# DRI-flexpcb-12s4p-compact.net
KiCad netlist of a schematic drawn in EAGLE
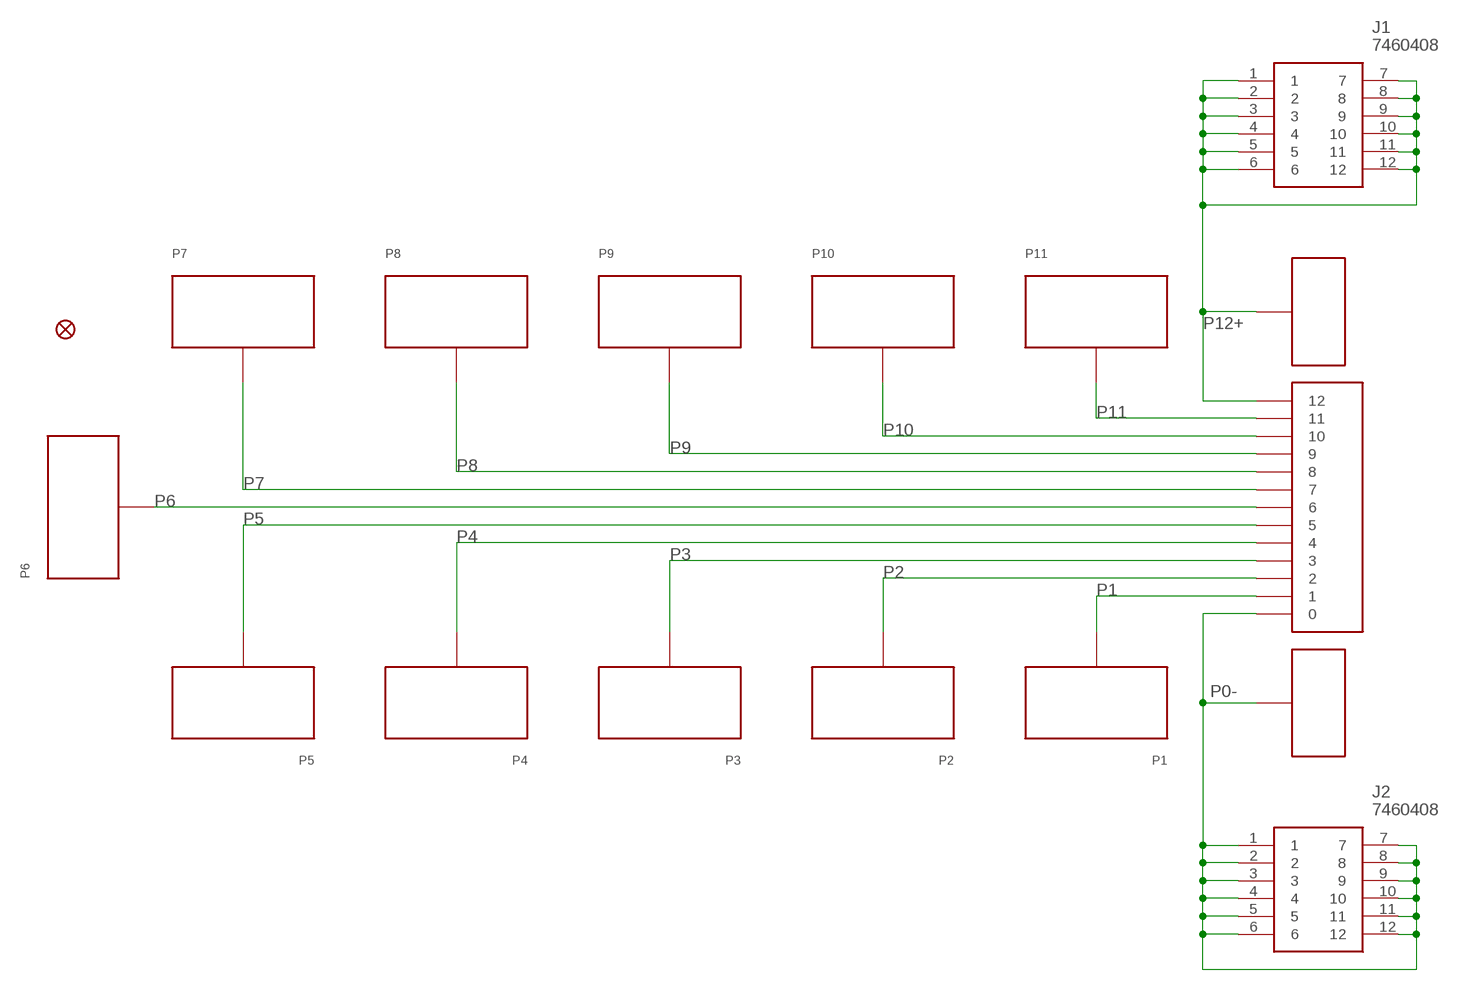
[diagram p0: schematic, sheet 1]

(export (version "E")
  (design (tool "Eeschema 10.0.6"))
  (components
    (comp (ref "FD2")
      (value "FIDUCIAL1X2")
      (footprint "eagle-import:FIDUCIAL-1X2")
      (libsource (lib "eagle-import") (part "FIDUCIAL1X2"))
    )
    (comp (ref "J1")
      (value "7460408")
      (footprint "eagle-import:7460408")
      (fields (field (name "MOUSER_PART_NUMBER") "710-7460408"))
      (libsource (lib "eagle-import") (part "7460408"))
    )
    (comp (ref "J2")
      (value "7460408")
      (footprint "eagle-import:7460408")
      (fields (field (name "MOUSER_PART_NUMBER") "710-7460408"))
      (libsource (lib "eagle-import") (part "7460408"))
    )
    (comp (ref "JP1")
      (value "13P-JST-2MM")
      (footprint "eagle-import:13P-JST-2MM")
      (libsource (lib "eagle-import") (part "13P-JST-2MM"))
    )
    (comp (ref "P0")
      (value "BUS-TERM-PAD-")
      (footprint "eagle-import:TERM-PAD-")
      (libsource (lib "eagle-import") (part "BUS-TERM-PAD-"))
    )
    (comp (ref "P1")
      (value "BAT-TERM-L")
      (footprint "eagle-import:BAT-TERM-L")
      (libsource (lib "eagle-import") (part "BAT-TERM-L"))
    )
    (comp (ref "P2")
      (value "BAT-TERM-L")
      (footprint "eagle-import:BAT-TERM-L")
      (libsource (lib "eagle-import") (part "BAT-TERM-L"))
    )
    (comp (ref "P3")
      (value "BAT-TERM-L")
      (footprint "eagle-import:BAT-TERM-L")
      (libsource (lib "eagle-import") (part "BAT-TERM-L"))
    )
    (comp (ref "P4")
      (value "BAT-TERM-L")
      (footprint "eagle-import:BAT-TERM-L")
      (libsource (lib "eagle-import") (part "BAT-TERM-L"))
    )
    (comp (ref "P5")
      (value "BAT-TERM-L")
      (footprint "eagle-import:BAT-TERM-L")
      (libsource (lib "eagle-import") (part "BAT-TERM-L"))
    )
    (comp (ref "P6")
      (value "BAT-TERM-END")
      (footprint "eagle-import:BAT-TERM-END")
      (libsource (lib "eagle-import") (part "BAT-TERM-END"))
    )
    (comp (ref "P7")
      (value "BAT-TERM-L")
      (footprint "eagle-import:BAT-TERM-L")
      (libsource (lib "eagle-import") (part "BAT-TERM-L"))
    )
    (comp (ref "P8")
      (value "BAT-TERM-L")
      (footprint "eagle-import:BAT-TERM-L")
      (libsource (lib "eagle-import") (part "BAT-TERM-L"))
    )
    (comp (ref "P9")
      (value "BAT-TERM-L")
      (footprint "eagle-import:BAT-TERM-L")
      (libsource (lib "eagle-import") (part "BAT-TERM-L"))
    )
    (comp (ref "P10")
      (value "BAT-TERM-L")
      (footprint "eagle-import:BAT-TERM-L")
      (libsource (lib "eagle-import") (part "BAT-TERM-L"))
    )
    (comp (ref "P11")
      (value "BAT-TERM-L")
      (footprint "eagle-import:BAT-TERM-L")
      (libsource (lib "eagle-import") (part "BAT-TERM-L"))
    )
    (comp (ref "P12")
      (value "BUS-TERM-PAD+")
      (footprint "eagle-import:TERM-PAD-")
      (libsource (lib "eagle-import") (part "BUS-TERM-PAD+"))
    )
  )
  (nets
    (net (code "1") (name "/P0-") (class "Default")
      (node (ref "J2") (pin "1") (pinfunction "1_1") (pintype "bidirectional"))
      (node (ref "J2") (pin "10") (pinfunction "10_10") (pintype "bidirectional"))
      (node (ref "J2") (pin "11") (pinfunction "11_11") (pintype "bidirectional"))
      (node (ref "J2") (pin "12") (pinfunction "12_12") (pintype "bidirectional"))
      (node (ref "J2") (pin "2") (pinfunction "2_2") (pintype "bidirectional"))
      (node (ref "J2") (pin "3") (pinfunction "3_3") (pintype "bidirectional"))
      (node (ref "J2") (pin "4") (pinfunction "4_4") (pintype "bidirectional"))
      (node (ref "J2") (pin "5") (pinfunction "5_5") (pintype "bidirectional"))
      (node (ref "J2") (pin "6") (pinfunction "6_6") (pintype "bidirectional"))
      (node (ref "J2") (pin "7") (pinfunction "7_7") (pintype "bidirectional"))
      (node (ref "J2") (pin "8") (pinfunction "8_8") (pintype "bidirectional"))
      (node (ref "J2") (pin "9") (pinfunction "9_9") (pintype "bidirectional"))
      (node (ref "JP1") (pin "P$1") (pinfunction "0_P$1") (pintype "bidirectional"))
      (node (ref "P0") (pin "P$10") (pinfunction "P$0_P$10") (pintype "power_in"))
      (node (ref "P0") (pin "P$100") (pinfunction "P$0_P$100") (pintype "power_in"))
      (node (ref "P0") (pin "P$101") (pinfunction "P$0_P$101") (pintype "power_in"))
      (node (ref "P0") (pin "P$102") (pinfunction "P$0_P$102") (pintype "power_in"))
      (node (ref "P0") (pin "P$103") (pinfunction "P$0_P$103") (pintype "power_in"))
      (node (ref "P0") (pin "P$104") (pinfunction "P$0_P$104") (pintype "power_in"))
      (node (ref "P0") (pin "P$105") (pinfunction "P$0_P$105") (pintype "power_in"))
      (node (ref "P0") (pin "P$106") (pinfunction "P$0_P$106") (pintype "power_in"))
      (node (ref "P0") (pin "P$107") (pinfunction "P$0_P$107") (pintype "power_in"))
      (node (ref "P0") (pin "P$108") (pinfunction "P$0_P$108") (pintype "power_in"))
      (node (ref "P0") (pin "P$109") (pinfunction "P$0_P$109") (pintype "power_in"))
      (node (ref "P0") (pin "P$11") (pinfunction "P$0_P$11") (pintype "power_in"))
      (node (ref "P0") (pin "P$110") (pinfunction "P$0_P$110") (pintype "power_in"))
      (node (ref "P0") (pin "P$12") (pinfunction "P$0_P$12") (pintype "power_in"))
      (node (ref "P0") (pin "P$13") (pinfunction "P$0_P$13") (pintype "power_in"))
      (node (ref "P0") (pin "P$14") (pinfunction "P$0_P$14") (pintype "power_in"))
      (node (ref "P0") (pin "P$15") (pinfunction "P$0_P$15") (pintype "power_in"))
      (node (ref "P0") (pin "P$16") (pinfunction "P$0_P$16") (pintype "power_in"))
      (node (ref "P0") (pin "P$17") (pinfunction "P$0_P$17") (pintype "power_in"))
      (node (ref "P0") (pin "P$18") (pinfunction "P$0_P$18") (pintype "power_in"))
      (node (ref "P0") (pin "P$181") (pinfunction "P$0_P$181") (pintype "power_in"))
      (node (ref "P0") (pin "P$182") (pinfunction "P$0_P$182") (pintype "power_in"))
      (node (ref "P0") (pin "P$183") (pinfunction "P$0_P$183") (pintype "power_in"))
      (node (ref "P0") (pin "P$184") (pinfunction "P$0_P$184") (pintype "power_in"))
      (node (ref "P0") (pin "P$185") (pinfunction "P$0_P$185") (pintype "power_in"))
      (node (ref "P0") (pin "P$186") (pinfunction "P$0_P$186") (pintype "power_in"))
      (node (ref "P0") (pin "P$187") (pinfunction "P$0_P$187") (pintype "power_in"))
      (node (ref "P0") (pin "P$188") (pinfunction "P$0_P$188") (pintype "power_in"))
      (node (ref "P0") (pin "P$189") (pinfunction "P$0_P$189") (pintype "power_in"))
      (node (ref "P0") (pin "P$19") (pinfunction "P$0_P$19") (pintype "power_in"))
      (node (ref "P0") (pin "P$190") (pinfunction "P$0_P$190") (pintype "power_in"))
      (node (ref "P0") (pin "P$191") (pinfunction "P$0_P$191") (pintype "power_in"))
      (node (ref "P0") (pin "P$192") (pinfunction "P$0_P$192") (pintype "power_in"))
      (node (ref "P0") (pin "P$193") (pinfunction "P$0_P$193") (pintype "power_in"))
      (node (ref "P0") (pin "P$194") (pinfunction "P$0_P$194") (pintype "power_in"))
      (node (ref "P0") (pin "P$195") (pinfunction "P$0_P$195") (pintype "power_in"))
      (node (ref "P0") (pin "P$196") (pinfunction "P$0_P$196") (pintype "power_in"))
      (node (ref "P0") (pin "P$197") (pinfunction "P$0_P$197") (pintype "power_in"))
      (node (ref "P0") (pin "P$198") (pinfunction "P$0_P$198") (pintype "power_in"))
      (node (ref "P0") (pin "P$199") (pinfunction "P$0_P$199") (pintype "power_in"))
      (node (ref "P0") (pin "P$20") (pinfunction "P$0_P$20") (pintype "power_in"))
      (node (ref "P0") (pin "P$200") (pinfunction "P$0_P$200") (pintype "power_in"))
      (node (ref "P0") (pin "P$201") (pinfunction "P$0_P$201") (pintype "power_in"))
      (node (ref "P0") (pin "P$202") (pinfunction "P$0_P$202") (pintype "power_in"))
      (node (ref "P0") (pin "P$203") (pinfunction "P$0_P$203") (pintype "power_in"))
      (node (ref "P0") (pin "P$204") (pinfunction "P$0_P$204") (pintype "power_in"))
      (node (ref "P0") (pin "P$205") (pinfunction "P$0_P$205") (pintype "power_in"))
      (node (ref "P0") (pin "P$206") (pinfunction "P$0_P$206") (pintype "power_in"))
      (node (ref "P0") (pin "P$207") (pinfunction "P$0_P$207") (pintype "power_in"))
      (node (ref "P0") (pin "P$208") (pinfunction "P$0_P$208") (pintype "power_in"))
      (node (ref "P0") (pin "P$209") (pinfunction "P$0_P$209") (pintype "power_in"))
      (node (ref "P0") (pin "P$21") (pinfunction "P$0_P$21") (pintype "power_in"))
      (node (ref "P0") (pin "P$210") (pinfunction "P$0_P$210") (pintype "power_in"))
      (node (ref "P0") (pin "P$211") (pinfunction "P$0_P$211") (pintype "power_in"))
      (node (ref "P0") (pin "P$212") (pinfunction "P$0_P$212") (pintype "power_in"))
      (node (ref "P0") (pin "P$213") (pinfunction "P$0_P$213") (pintype "power_in"))
      (node (ref "P0") (pin "P$214") (pinfunction "P$0_P$214") (pintype "power_in"))
      (node (ref "P0") (pin "P$215") (pinfunction "P$0_P$215") (pintype "power_in"))
      (node (ref "P0") (pin "P$216") (pinfunction "P$0_P$216") (pintype "power_in"))
      (node (ref "P0") (pin "P$217") (pinfunction "P$0_P$217") (pintype "power_in"))
      (node (ref "P0") (pin "P$218") (pinfunction "P$0_P$218") (pintype "power_in"))
      (node (ref "P0") (pin "P$219") (pinfunction "P$0_P$219") (pintype "power_in"))
      (node (ref "P0") (pin "P$22") (pinfunction "P$0_P$22") (pintype "power_in"))
      (node (ref "P0") (pin "P$220") (pinfunction "P$0_P$220") (pintype "power_in"))
      (node (ref "P0") (pin "P$221") (pinfunction "P$0_P$221") (pintype "power_in"))
      (node (ref "P0") (pin "P$222") (pinfunction "P$0_P$222") (pintype "power_in"))
      (node (ref "P0") (pin "P$223") (pinfunction "P$0_P$223") (pintype "power_in"))
      (node (ref "P0") (pin "P$224") (pinfunction "P$0_P$224") (pintype "power_in"))
      (node (ref "P0") (pin "P$225") (pinfunction "P$0_P$225") (pintype "power_in"))
      (node (ref "P0") (pin "P$226") (pinfunction "P$0_P$226") (pintype "power_in"))
      (node (ref "P0") (pin "P$227") (pinfunction "P$0_P$227") (pintype "power_in"))
      (node (ref "P0") (pin "P$228") (pinfunction "P$0_P$228") (pintype "power_in"))
      (node (ref "P0") (pin "P$229") (pinfunction "P$0_P$229") (pintype "power_in"))
      (node (ref "P0") (pin "P$23") (pinfunction "P$0_P$23") (pintype "power_in"))
      (node (ref "P0") (pin "P$230") (pinfunction "P$0_P$230") (pintype "power_in"))
      (node (ref "P0") (pin "P$231") (pinfunction "P$0_P$231") (pintype "power_in"))
      (node (ref "P0") (pin "P$232") (pinfunction "P$0_P$232") (pintype "power_in"))
      (node (ref "P0") (pin "P$233") (pinfunction "P$0_P$233") (pintype "power_in"))
      (node (ref "P0") (pin "P$234") (pinfunction "P$0_P$234") (pintype "power_in"))
      (node (ref "P0") (pin "P$235") (pinfunction "P$0_P$235") (pintype "power_in"))
      (node (ref "P0") (pin "P$236") (pinfunction "P$0_P$236") (pintype "power_in"))
      (node (ref "P0") (pin "P$237") (pinfunction "P$0_P$237") (pintype "power_in"))
      (node (ref "P0") (pin "P$238") (pinfunction "P$0_P$238") (pintype "power_in"))
      (node (ref "P0") (pin "P$239") (pinfunction "P$0_P$239") (pintype "power_in"))
      (node (ref "P0") (pin "P$24") (pinfunction "P$0_P$24") (pintype "power_in"))
      (node (ref "P0") (pin "P$240") (pinfunction "P$0_P$240") (pintype "power_in"))
      (node (ref "P0") (pin "P$241") (pinfunction "P$0_P$241") (pintype "power_in"))
      (node (ref "P0") (pin "P$242") (pinfunction "P$0_P$242") (pintype "power_in"))
      (node (ref "P0") (pin "P$243") (pinfunction "P$0_P$243") (pintype "power_in"))
      (node (ref "P0") (pin "P$244") (pinfunction "P$0_P$244") (pintype "power_in"))
      (node (ref "P0") (pin "P$245") (pinfunction "P$0_P$245") (pintype "power_in"))
      (node (ref "P0") (pin "P$246") (pinfunction "P$0_P$246") (pintype "power_in"))
      (node (ref "P0") (pin "P$247") (pinfunction "P$0_P$247") (pintype "power_in"))
      (node (ref "P0") (pin "P$248") (pinfunction "P$0_P$248") (pintype "power_in"))
      (node (ref "P0") (pin "P$249") (pinfunction "P$0_P$249") (pintype "power_in"))
      (node (ref "P0") (pin "P$25") (pinfunction "P$0_P$25") (pintype "power_in"))
      (node (ref "P0") (pin "P$250") (pinfunction "P$0_P$250") (pintype "power_in"))
      (node (ref "P0") (pin "P$251") (pinfunction "P$0_P$251") (pintype "power_in"))
      (node (ref "P0") (pin "P$252") (pinfunction "P$0_P$252") (pintype "power_in"))
      (node (ref "P0") (pin "P$253") (pinfunction "P$0_P$253") (pintype "power_in"))
      (node (ref "P0") (pin "P$254") (pinfunction "P$0_P$254") (pintype "power_in"))
      (node (ref "P0") (pin "P$255") (pinfunction "P$0_P$255") (pintype "power_in"))
      (node (ref "P0") (pin "P$256") (pinfunction "P$0_P$256") (pintype "power_in"))
      (node (ref "P0") (pin "P$257") (pinfunction "P$0_P$257") (pintype "power_in"))
      (node (ref "P0") (pin "P$258") (pinfunction "P$0_P$258") (pintype "power_in"))
      (node (ref "P0") (pin "P$259") (pinfunction "P$0_P$259") (pintype "power_in"))
      (node (ref "P0") (pin "P$26") (pinfunction "P$0_P$26") (pintype "power_in"))
      (node (ref "P0") (pin "P$260") (pinfunction "P$0_P$260") (pintype "power_in"))
      (node (ref "P0") (pin "P$261") (pinfunction "P$0_P$261") (pintype "power_in"))
      (node (ref "P0") (pin "P$262") (pinfunction "P$0_P$262") (pintype "power_in"))
      (node (ref "P0") (pin "P$263") (pinfunction "P$0_P$263") (pintype "power_in"))
      (node (ref "P0") (pin "P$264") (pinfunction "P$0_P$264") (pintype "power_in"))
      (node (ref "P0") (pin "P$265") (pinfunction "P$0_P$265") (pintype "power_in"))
      (node (ref "P0") (pin "P$266") (pinfunction "P$0_P$266") (pintype "power_in"))
      (node (ref "P0") (pin "P$267") (pinfunction "P$0_P$267") (pintype "power_in"))
      (node (ref "P0") (pin "P$268") (pinfunction "P$0_P$268") (pintype "power_in"))
      (node (ref "P0") (pin "P$269") (pinfunction "P$0_P$269") (pintype "power_in"))
      (node (ref "P0") (pin "P$27") (pinfunction "P$0_P$27") (pintype "power_in"))
      (node (ref "P0") (pin "P$270") (pinfunction "P$0_P$270") (pintype "power_in"))
      (node (ref "P0") (pin "P$271") (pinfunction "P$0_P$271") (pintype "power_in"))
      (node (ref "P0") (pin "P$272") (pinfunction "P$0_P$272") (pintype "power_in"))
      (node (ref "P0") (pin "P$273") (pinfunction "P$0_P$273") (pintype "power_in"))
      (node (ref "P0") (pin "P$274") (pinfunction "P$0_P$274") (pintype "power_in"))
      (node (ref "P0") (pin "P$275") (pinfunction "P$0_P$275") (pintype "power_in"))
      (node (ref "P0") (pin "P$276") (pinfunction "P$0_P$276") (pintype "power_in"))
      (node (ref "P0") (pin "P$277") (pinfunction "P$0_P$277") (pintype "power_in"))
      (node (ref "P0") (pin "P$278") (pinfunction "P$0_P$278") (pintype "power_in"))
      (node (ref "P0") (pin "P$279") (pinfunction "P$0_P$279") (pintype "power_in"))
      (node (ref "P0") (pin "P$28") (pinfunction "P$0_P$28") (pintype "power_in"))
      (node (ref "P0") (pin "P$280") (pinfunction "P$0_P$280") (pintype "power_in"))
      (node (ref "P0") (pin "P$281") (pinfunction "P$0_P$281") (pintype "power_in"))
      (node (ref "P0") (pin "P$282") (pinfunction "P$0_P$282") (pintype "power_in"))
      (node (ref "P0") (pin "P$283") (pinfunction "P$0_P$283") (pintype "power_in"))
      (node (ref "P0") (pin "P$284") (pinfunction "P$0_P$284") (pintype "power_in"))
      (node (ref "P0") (pin "P$285") (pinfunction "P$0_P$285") (pintype "power_in"))
      (node (ref "P0") (pin "P$286") (pinfunction "P$0_P$286") (pintype "power_in"))
      (node (ref "P0") (pin "P$287") (pinfunction "P$0_P$287") (pintype "power_in"))
      (node (ref "P0") (pin "P$288") (pinfunction "P$0_P$288") (pintype "power_in"))
      (node (ref "P0") (pin "P$289") (pinfunction "P$0_P$289") (pintype "power_in"))
      (node (ref "P0") (pin "P$29") (pinfunction "P$0_P$29") (pintype "power_in"))
      (node (ref "P0") (pin "P$290") (pinfunction "P$0_P$290") (pintype "power_in"))
      (node (ref "P0") (pin "P$291") (pinfunction "P$0_P$291") (pintype "power_in"))
      (node (ref "P0") (pin "P$292") (pinfunction "P$0_P$292") (pintype "power_in"))
      (node (ref "P0") (pin "P$293") (pinfunction "P$0_P$293") (pintype "power_in"))
      (node (ref "P0") (pin "P$294") (pinfunction "P$0_P$294") (pintype "power_in"))
      (node (ref "P0") (pin "P$295") (pinfunction "P$0_P$295") (pintype "power_in"))
      (node (ref "P0") (pin "P$296") (pinfunction "P$0_P$296") (pintype "power_in"))
      (node (ref "P0") (pin "P$297") (pinfunction "P$0_P$297") (pintype "power_in"))
      (node (ref "P0") (pin "P$298") (pinfunction "P$0_P$298") (pintype "power_in"))
      (node (ref "P0") (pin "P$299") (pinfunction "P$0_P$299") (pintype "power_in"))
      (node (ref "P0") (pin "P$3") (pinfunction "P$0_P$3") (pintype "power_in"))
      (node (ref "P0") (pin "P$30") (pinfunction "P$0_P$30") (pintype "power_in"))
      (node (ref "P0") (pin "P$300") (pinfunction "P$0_P$300") (pintype "power_in"))
      (node (ref "P0") (pin "P$301") (pinfunction "P$0_P$301") (pintype "power_in"))
      (node (ref "P0") (pin "P$302") (pinfunction "P$0_P$302") (pintype "power_in"))
      (node (ref "P0") (pin "P$303") (pinfunction "P$0_P$303") (pintype "power_in"))
      (node (ref "P0") (pin "P$304") (pinfunction "P$0_P$304") (pintype "power_in"))
      (node (ref "P0") (pin "P$305") (pinfunction "P$0_P$305") (pintype "power_in"))
      (node (ref "P0") (pin "P$306") (pinfunction "P$0_P$306") (pintype "power_in"))
      (node (ref "P0") (pin "P$307") (pinfunction "P$0_P$307") (pintype "power_in"))
      (node (ref "P0") (pin "P$308") (pinfunction "P$0_P$308") (pintype "power_in"))
      (node (ref "P0") (pin "P$309") (pinfunction "P$0_P$309") (pintype "power_in"))
      (node (ref "P0") (pin "P$31") (pinfunction "P$0_P$31") (pintype "power_in"))
      (node (ref "P0") (pin "P$310") (pinfunction "P$0_P$310") (pintype "power_in"))
      (node (ref "P0") (pin "P$311") (pinfunction "P$0_P$311") (pintype "power_in"))
      (node (ref "P0") (pin "P$312") (pinfunction "P$0_P$312") (pintype "power_in"))
      (node (ref "P0") (pin "P$313") (pinfunction "P$0_P$313") (pintype "power_in"))
      (node (ref "P0") (pin "P$314") (pinfunction "P$0_P$314") (pintype "power_in"))
      (node (ref "P0") (pin "P$315") (pinfunction "P$0_P$315") (pintype "power_in"))
      (node (ref "P0") (pin "P$316") (pinfunction "P$0_P$316") (pintype "power_in"))
      (node (ref "P0") (pin "P$317") (pinfunction "P$0_P$317") (pintype "power_in"))
      (node (ref "P0") (pin "P$318") (pinfunction "P$0_P$318") (pintype "power_in"))
      (node (ref "P0") (pin "P$319") (pinfunction "P$0_P$319") (pintype "power_in"))
      (node (ref "P0") (pin "P$32") (pinfunction "P$0_P$32") (pintype "power_in"))
      (node (ref "P0") (pin "P$320") (pinfunction "P$0_P$320") (pintype "power_in"))
      (node (ref "P0") (pin "P$321") (pinfunction "P$0_P$321") (pintype "power_in"))
      (node (ref "P0") (pin "P$322") (pinfunction "P$0_P$322") (pintype "power_in"))
      (node (ref "P0") (pin "P$323") (pinfunction "P$0_P$323") (pintype "power_in"))
      (node (ref "P0") (pin "P$324") (pinfunction "P$0_P$324") (pintype "power_in"))
      (node (ref "P0") (pin "P$325") (pinfunction "P$0_P$325") (pintype "power_in"))
      (node (ref "P0") (pin "P$326") (pinfunction "P$0_P$326") (pintype "power_in"))
      (node (ref "P0") (pin "P$327") (pinfunction "P$0_P$327") (pintype "power_in"))
      (node (ref "P0") (pin "P$328") (pinfunction "P$0_P$328") (pintype "power_in"))
      (node (ref "P0") (pin "P$329") (pinfunction "P$0_P$329") (pintype "power_in"))
      (node (ref "P0") (pin "P$33") (pinfunction "P$0_P$33") (pintype "power_in"))
      (node (ref "P0") (pin "P$330") (pinfunction "P$0_P$330") (pintype "power_in"))
      (node (ref "P0") (pin "P$331") (pinfunction "P$0_P$331") (pintype "power_in"))
      (node (ref "P0") (pin "P$332") (pinfunction "P$0_P$332") (pintype "power_in"))
      (node (ref "P0") (pin "P$333") (pinfunction "P$0_P$333") (pintype "power_in"))
      (node (ref "P0") (pin "P$334") (pinfunction "P$0_P$334") (pintype "power_in"))
      (node (ref "P0") (pin "P$335") (pinfunction "P$0_P$335") (pintype "power_in"))
      (node (ref "P0") (pin "P$336") (pinfunction "P$0_P$336") (pintype "power_in"))
      (node (ref "P0") (pin "P$337") (pinfunction "P$0_P$337") (pintype "power_in"))
      (node (ref "P0") (pin "P$338") (pinfunction "P$0_P$338") (pintype "power_in"))
      (node (ref "P0") (pin "P$339") (pinfunction "P$0_P$339") (pintype "power_in"))
      (node (ref "P0") (pin "P$34") (pinfunction "P$0_P$34") (pintype "power_in"))
      (node (ref "P0") (pin "P$340") (pinfunction "P$0_P$340") (pintype "power_in"))
      (node (ref "P0") (pin "P$341") (pinfunction "P$0_P$341") (pintype "power_in"))
      (node (ref "P0") (pin "P$342") (pinfunction "P$0_P$342") (pintype "power_in"))
      (node (ref "P0") (pin "P$343") (pinfunction "P$0_P$343") (pintype "power_in"))
      (node (ref "P0") (pin "P$344") (pinfunction "P$0_P$344") (pintype "power_in"))
      (node (ref "P0") (pin "P$345") (pinfunction "P$0_P$345") (pintype "power_in"))
      (node (ref "P0") (pin "P$346") (pinfunction "P$0_P$346") (pintype "power_in"))
      (node (ref "P0") (pin "P$347") (pinfunction "P$0_P$347") (pintype "power_in"))
      (node (ref "P0") (pin "P$348") (pinfunction "P$0_P$348") (pintype "power_in"))
      (node (ref "P0") (pin "P$349") (pinfunction "P$0_P$349") (pintype "power_in"))
      (node (ref "P0") (pin "P$35") (pinfunction "P$0_P$35") (pintype "power_in"))
      (node (ref "P0") (pin "P$350") (pinfunction "P$0_P$350") (pintype "power_in"))
      (node (ref "P0") (pin "P$351") (pinfunction "P$0_P$351") (pintype "power_in"))
      (node (ref "P0") (pin "P$352") (pinfunction "P$0_P$352") (pintype "power_in"))
      (node (ref "P0") (pin "P$353") (pinfunction "P$0_P$353") (pintype "power_in"))
      (node (ref "P0") (pin "P$354") (pinfunction "P$0_P$354") (pintype "power_in"))
      (node (ref "P0") (pin "P$355") (pinfunction "P$0_P$355") (pintype "power_in"))
      (node (ref "P0") (pin "P$356") (pinfunction "P$0_P$356") (pintype "power_in"))
      (node (ref "P0") (pin "P$357") (pinfunction "P$0_P$357") (pintype "power_in"))
      (node (ref "P0") (pin "P$358") (pinfunction "P$0_P$358") (pintype "power_in"))
      (node (ref "P0") (pin "P$359") (pinfunction "P$0_P$359") (pintype "power_in"))
      (node (ref "P0") (pin "P$36") (pinfunction "P$0_P$36") (pintype "power_in"))
      (node (ref "P0") (pin "P$360") (pinfunction "P$0_P$360") (pintype "power_in"))
      (node (ref "P0") (pin "P$37") (pinfunction "P$0_P$37") (pintype "power_in"))
      (node (ref "P0") (pin "P$38") (pinfunction "P$0_P$38") (pintype "power_in"))
      (node (ref "P0") (pin "P$39") (pinfunction "P$0_P$39") (pintype "power_in"))
      (node (ref "P0") (pin "P$4") (pinfunction "P$0_P$4") (pintype "power_in"))
      (node (ref "P0") (pin "P$40") (pinfunction "P$0_P$40") (pintype "power_in"))
      (node (ref "P0") (pin "P$41") (pinfunction "P$0_P$41") (pintype "power_in"))
      (node (ref "P0") (pin "P$42") (pinfunction "P$0_P$42") (pintype "power_in"))
      (node (ref "P0") (pin "P$43") (pinfunction "P$0_P$43") (pintype "power_in"))
      (node (ref "P0") (pin "P$44") (pinfunction "P$0_P$44") (pintype "power_in"))
      (node (ref "P0") (pin "P$45") (pinfunction "P$0_P$45") (pintype "power_in"))
      (node (ref "P0") (pin "P$46") (pinfunction "P$0_P$46") (pintype "power_in"))
      (node (ref "P0") (pin "P$47") (pinfunction "P$0_P$47") (pintype "power_in"))
      (node (ref "P0") (pin "P$48") (pinfunction "P$0_P$48") (pintype "power_in"))
      (node (ref "P0") (pin "P$49") (pinfunction "P$0_P$49") (pintype "power_in"))
      (node (ref "P0") (pin "P$5") (pinfunction "P$0_P$5") (pintype "power_in"))
      (node (ref "P0") (pin "P$50") (pinfunction "P$0_P$50") (pintype "power_in"))
      (node (ref "P0") (pin "P$51") (pinfunction "P$0_P$51") (pintype "power_in"))
      (node (ref "P0") (pin "P$52") (pinfunction "P$0_P$52") (pintype "power_in"))
      (node (ref "P0") (pin "P$53") (pinfunction "P$0_P$53") (pintype "power_in"))
      (node (ref "P0") (pin "P$54") (pinfunction "P$0_P$54") (pintype "power_in"))
      (node (ref "P0") (pin "P$55") (pinfunction "P$0_P$55") (pintype "power_in"))
      (node (ref "P0") (pin "P$56") (pinfunction "P$0_P$56") (pintype "power_in"))
      (node (ref "P0") (pin "P$57") (pinfunction "P$0_P$57") (pintype "power_in"))
      (node (ref "P0") (pin "P$58") (pinfunction "P$0_P$58") (pintype "power_in"))
      (node (ref "P0") (pin "P$59") (pinfunction "P$0_P$59") (pintype "power_in"))
      (node (ref "P0") (pin "P$6") (pinfunction "P$0_P$6") (pintype "power_in"))
      (node (ref "P0") (pin "P$60") (pinfunction "P$0_P$60") (pintype "power_in"))
      (node (ref "P0") (pin "P$61") (pinfunction "P$0_P$61") (pintype "power_in"))
      (node (ref "P0") (pin "P$62") (pinfunction "P$0_P$62") (pintype "power_in"))
      (node (ref "P0") (pin "P$63") (pinfunction "P$0_P$63") (pintype "power_in"))
      (node (ref "P0") (pin "P$64") (pinfunction "P$0_P$64") (pintype "power_in"))
      (node (ref "P0") (pin "P$65") (pinfunction "P$0_P$65") (pintype "power_in"))
      (node (ref "P0") (pin "P$66") (pinfunction "P$0_P$66") (pintype "power_in"))
      (node (ref "P0") (pin "P$67") (pinfunction "P$0_P$67") (pintype "power_in"))
      (node (ref "P0") (pin "P$68") (pinfunction "P$0_P$68") (pintype "power_in"))
      (node (ref "P0") (pin "P$69") (pinfunction "P$0_P$69") (pintype "power_in"))
      (node (ref "P0") (pin "P$7") (pinfunction "P$0_P$7") (pintype "power_in"))
      (node (ref "P0") (pin "P$70") (pinfunction "P$0_P$70") (pintype "power_in"))
      (node (ref "P0") (pin "P$71") (pinfunction "P$0_P$71") (pintype "power_in"))
      (node (ref "P0") (pin "P$72") (pinfunction "P$0_P$72") (pintype "power_in"))
      (node (ref "P0") (pin "P$73") (pinfunction "P$0_P$73") (pintype "power_in"))
      (node (ref "P0") (pin "P$74") (pinfunction "P$0_P$74") (pintype "power_in"))
      (node (ref "P0") (pin "P$75") (pinfunction "P$0_P$75") (pintype "power_in"))
      (node (ref "P0") (pin "P$76") (pinfunction "P$0_P$76") (pintype "power_in"))
      (node (ref "P0") (pin "P$77") (pinfunction "P$0_P$77") (pintype "power_in"))
      (node (ref "P0") (pin "P$78") (pinfunction "P$0_P$78") (pintype "power_in"))
      (node (ref "P0") (pin "P$79") (pinfunction "P$0_P$79") (pintype "power_in"))
      (node (ref "P0") (pin "P$8") (pinfunction "P$0_P$8") (pintype "power_in"))
      (node (ref "P0") (pin "P$80") (pinfunction "P$0_P$80") (pintype "power_in"))
      (node (ref "P0") (pin "P$81") (pinfunction "P$0_P$81") (pintype "power_in"))
      (node (ref "P0") (pin "P$82") (pinfunction "P$0_P$82") (pintype "power_in"))
      (node (ref "P0") (pin "P$83") (pinfunction "P$0_P$83") (pintype "power_in"))
      (node (ref "P0") (pin "P$84") (pinfunction "P$0_P$84") (pintype "power_in"))
      (node (ref "P0") (pin "P$85") (pinfunction "P$0_P$85") (pintype "power_in"))
      (node (ref "P0") (pin "P$86") (pinfunction "P$0_P$86") (pintype "power_in"))
      (node (ref "P0") (pin "P$87") (pinfunction "P$0_P$87") (pintype "power_in"))
      (node (ref "P0") (pin "P$88") (pinfunction "P$0_P$88") (pintype "power_in"))
      (node (ref "P0") (pin "P$89") (pinfunction "P$0_P$89") (pintype "power_in"))
      (node (ref "P0") (pin "P$9") (pinfunction "P$0_P$9") (pintype "power_in"))
      (node (ref "P0") (pin "P$90") (pinfunction "P$0_P$90") (pintype "power_in"))
      (node (ref "P0") (pin "P$91") (pinfunction "P$0_P$91") (pintype "power_in"))
      (node (ref "P0") (pin "P$92") (pinfunction "P$0_P$92") (pintype "power_in"))
      (node (ref "P0") (pin "P$93") (pinfunction "P$0_P$93") (pintype "power_in"))
      (node (ref "P0") (pin "P$94") (pinfunction "P$0_P$94") (pintype "power_in"))
      (node (ref "P0") (pin "P$95") (pinfunction "P$0_P$95") (pintype "power_in"))
      (node (ref "P0") (pin "P$96") (pinfunction "P$0_P$96") (pintype "power_in"))
      (node (ref "P0") (pin "P$97") (pinfunction "P$0_P$97") (pintype "power_in"))
      (node (ref "P0") (pin "P$98") (pinfunction "P$0_P$98") (pintype "power_in"))
      (node (ref "P0") (pin "P$99") (pinfunction "P$0_P$99") (pintype "power_in"))
    )
    (net (code "2") (name "/P1") (class "Default")
      (node (ref "JP1") (pin "P$2") (pinfunction "1_P$2") (pintype "bidirectional"))
      (node (ref "P1") (pin "P$1") (pinfunction "P$1_P$1") (pintype "power_in"))
      (node (ref "P1") (pin "P$10") (pinfunction "P$1_P$10") (pintype "power_in"))
      (node (ref "P1") (pin "P$100") (pinfunction "P$1_P$100") (pintype "power_in"))
      (node (ref "P1") (pin "P$101") (pinfunction "P$1_P$101") (pintype "power_in"))
      (node (ref "P1") (pin "P$102") (pinfunction "P$1_P$102") (pintype "power_in"))
      (node (ref "P1") (pin "P$103") (pinfunction "P$1_P$103") (pintype "power_in"))
      (node (ref "P1") (pin "P$104") (pinfunction "P$1_P$104") (pintype "power_in"))
      (node (ref "P1") (pin "P$105") (pinfunction "P$1_P$105") (pintype "power_in"))
      (node (ref "P1") (pin "P$106") (pinfunction "P$1_P$106") (pintype "power_in"))
      (node (ref "P1") (pin "P$107") (pinfunction "P$1_P$107") (pintype "power_in"))
      (node (ref "P1") (pin "P$108") (pinfunction "P$1_P$108") (pintype "power_in"))
      (node (ref "P1") (pin "P$109") (pinfunction "P$1_P$109") (pintype "power_in"))
      (node (ref "P1") (pin "P$11") (pinfunction "P$1_P$11") (pintype "power_in"))
      (node (ref "P1") (pin "P$110") (pinfunction "P$1_P$110") (pintype "power_in"))
      (node (ref "P1") (pin "P$111") (pinfunction "P$1_P$111") (pintype "power_in"))
      (node (ref "P1") (pin "P$112") (pinfunction "P$1_P$112") (pintype "power_in"))
      (node (ref "P1") (pin "P$113") (pinfunction "P$1_P$113") (pintype "power_in"))
      (node (ref "P1") (pin "P$114") (pinfunction "P$1_P$114") (pintype "power_in"))
      (node (ref "P1") (pin "P$115") (pinfunction "P$1_P$115") (pintype "power_in"))
      (node (ref "P1") (pin "P$116") (pinfunction "P$1_P$116") (pintype "power_in"))
      (node (ref "P1") (pin "P$117") (pinfunction "P$1_P$117") (pintype "power_in"))
      (node (ref "P1") (pin "P$118") (pinfunction "P$1_P$118") (pintype "power_in"))
      (node (ref "P1") (pin "P$119") (pinfunction "P$1_P$119") (pintype "power_in"))
      (node (ref "P1") (pin "P$12") (pinfunction "P$1_P$12") (pintype "power_in"))
      (node (ref "P1") (pin "P$120") (pinfunction "P$1_P$120") (pintype "power_in"))
      (node (ref "P1") (pin "P$121") (pinfunction "P$1_P$121") (pintype "power_in"))
      (node (ref "P1") (pin "P$122") (pinfunction "P$1_P$122") (pintype "power_in"))
      (node (ref "P1") (pin "P$123") (pinfunction "P$1_P$123") (pintype "power_in"))
      (node (ref "P1") (pin "P$124") (pinfunction "P$1_P$124") (pintype "power_in"))
      (node (ref "P1") (pin "P$125") (pinfunction "P$1_P$125") (pintype "power_in"))
      (node (ref "P1") (pin "P$126") (pinfunction "P$1_P$126") (pintype "power_in"))
      (node (ref "P1") (pin "P$127") (pinfunction "P$1_P$127") (pintype "power_in"))
      (node (ref "P1") (pin "P$128") (pinfunction "P$1_P$128") (pintype "power_in"))
      (node (ref "P1") (pin "P$129") (pinfunction "P$1_P$129") (pintype "power_in"))
      (node (ref "P1") (pin "P$13") (pinfunction "P$1_P$13") (pintype "power_in"))
      (node (ref "P1") (pin "P$130") (pinfunction "P$1_P$130") (pintype "power_in"))
      (node (ref "P1") (pin "P$131") (pinfunction "P$1_P$131") (pintype "power_in"))
      (node (ref "P1") (pin "P$132") (pinfunction "P$1_P$132") (pintype "power_in"))
      (node (ref "P1") (pin "P$133") (pinfunction "P$1_P$133") (pintype "power_in"))
      (node (ref "P1") (pin "P$134") (pinfunction "P$1_P$134") (pintype "power_in"))
      (node (ref "P1") (pin "P$135") (pinfunction "P$1_P$135") (pintype "power_in"))
      (node (ref "P1") (pin "P$136") (pinfunction "P$1_P$136") (pintype "power_in"))
      (node (ref "P1") (pin "P$137") (pinfunction "P$1_P$137") (pintype "power_in"))
      (node (ref "P1") (pin "P$138") (pinfunction "P$1_P$138") (pintype "power_in"))
      (node (ref "P1") (pin "P$139") (pinfunction "P$1_P$139") (pintype "power_in"))
      (node (ref "P1") (pin "P$14") (pinfunction "P$1_P$14") (pintype "power_in"))
      (node (ref "P1") (pin "P$140") (pinfunction "P$1_P$140") (pintype "power_in"))
      (node (ref "P1") (pin "P$141") (pinfunction "P$1_P$141") (pintype "power_in"))
      (node (ref "P1") (pin "P$142") (pinfunction "P$1_P$142") (pintype "power_in"))
      (node (ref "P1") (pin "P$143") (pinfunction "P$1_P$143") (pintype "power_in"))
      (node (ref "P1") (pin "P$144") (pinfunction "P$1_P$144") (pintype "power_in"))
      (node (ref "P1") (pin "P$145") (pinfunction "P$1_P$145") (pintype "power_in"))
      (node (ref "P1") (pin "P$146") (pinfunction "P$1_P$146") (pintype "power_in"))
      (node (ref "P1") (pin "P$147") (pinfunction "P$1_P$147") (pintype "power_in"))
      (node (ref "P1") (pin "P$148") (pinfunction "P$1_P$148") (pintype "power_in"))
      (node (ref "P1") (pin "P$149") (pinfunction "P$1_P$149") (pintype "power_in"))
      (node (ref "P1") (pin "P$15") (pinfunction "P$1_P$15") (pintype "power_in"))
      (node (ref "P1") (pin "P$150") (pinfunction "P$1_P$150") (pintype "power_in"))
      (node (ref "P1") (pin "P$151") (pinfunction "P$1_P$151") (pintype "power_in"))
      (node (ref "P1") (pin "P$152") (pinfunction "P$1_P$152") (pintype "power_in"))
      (node (ref "P1") (pin "P$153") (pinfunction "P$1_P$153") (pintype "power_in"))
      (node (ref "P1") (pin "P$154") (pinfunction "P$1_P$154") (pintype "power_in"))
      (node (ref "P1") (pin "P$155") (pinfunction "P$1_P$155") (pintype "power_in"))
      (node (ref "P1") (pin "P$156") (pinfunction "P$1_P$156") (pintype "power_in"))
      (node (ref "P1") (pin "P$157") (pinfunction "P$1_P$157") (pintype "power_in"))
      (node (ref "P1") (pin "P$158") (pinfunction "P$1_P$158") (pintype "power_in"))
      (node (ref "P1") (pin "P$159") (pinfunction "P$1_P$159") (pintype "power_in"))
      (node (ref "P1") (pin "P$16") (pinfunction "P$1_P$16") (pintype "power_in"))
      (node (ref "P1") (pin "P$160") (pinfunction "P$1_P$160") (pintype "power_in"))
      (node (ref "P1") (pin "P$161") (pinfunction "P$1_P$161") (pintype "power_in"))
      (node (ref "P1") (pin "P$162") (pinfunction "P$1_P$162") (pintype "power_in"))
      (node (ref "P1") (pin "P$163") (pinfunction "P$1_P$163") (pintype "power_in"))
      (node (ref "P1") (pin "P$164") (pinfunction "P$1_P$164") (pintype "power_in"))
      (node (ref "P1") (pin "P$165") (pinfunction "P$1_P$165") (pintype "power_in"))
      (node (ref "P1") (pin "P$166") (pinfunction "P$1_P$166") (pintype "power_in"))
      (node (ref "P1") (pin "P$167") (pinfunction "P$1_P$167") (pintype "power_in"))
      (node (ref "P1") (pin "P$168") (pinfunction "P$1_P$168") (pintype "power_in"))
      (node (ref "P1") (pin "P$169") (pinfunction "P$1_P$169") (pintype "power_in"))
      (node (ref "P1") (pin "P$17") (pinfunction "P$1_P$17") (pintype "power_in"))
      (node (ref "P1") (pin "P$170") (pinfunction "P$1_P$170") (pintype "power_in"))
      (node (ref "P1") (pin "P$171") (pinfunction "P$1_P$171") (pintype "power_in"))
      (node (ref "P1") (pin "P$172") (pinfunction "P$1_P$172") (pintype "power_in"))
      (node (ref "P1") (pin "P$173") (pinfunction "P$1_P$173") (pintype "power_in"))
      (node (ref "P1") (pin "P$174") (pinfunction "P$1_P$174") (pintype "power_in"))
      (node (ref "P1") (pin "P$175") (pinfunction "P$1_P$175") (pintype "power_in"))
      (node (ref "P1") (pin "P$176") (pinfunction "P$1_P$176") (pintype "power_in"))
      (node (ref "P1") (pin "P$177") (pinfunction "P$1_P$177") (pintype "power_in"))
      (node (ref "P1") (pin "P$178") (pinfunction "P$1_P$178") (pintype "power_in"))
      (node (ref "P1") (pin "P$179") (pinfunction "P$1_P$179") (pintype "power_in"))
      (node (ref "P1") (pin "P$18") (pinfunction "P$1_P$18") (pintype "power_in"))
      (node (ref "P1") (pin "P$180") (pinfunction "P$1_P$180") (pintype "power_in"))
      (node (ref "P1") (pin "P$181") (pinfunction "P$1_P$181") (pintype "power_in"))
      (node (ref "P1") (pin "P$182") (pinfunction "P$1_P$182") (pintype "power_in"))
      (node (ref "P1") (pin "P$183") (pinfunction "P$1_P$183") (pintype "power_in"))
      (node (ref "P1") (pin "P$184") (pinfunction "P$1_P$184") (pintype "power_in"))
      (node (ref "P1") (pin "P$185") (pinfunction "P$1_P$185") (pintype "power_in"))
      (node (ref "P1") (pin "P$186") (pinfunction "P$1_P$186") (pintype "power_in"))
      (node (ref "P1") (pin "P$187") (pinfunction "P$1_P$187") (pintype "power_in"))
      (node (ref "P1") (pin "P$188") (pinfunction "P$1_P$188") (pintype "power_in"))
      (node (ref "P1") (pin "P$189") (pinfunction "P$1_P$189") (pintype "power_in"))
      (node (ref "P1") (pin "P$19") (pinfunction "P$1_P$19") (pintype "power_in"))
      (node (ref "P1") (pin "P$190") (pinfunction "P$1_P$190") (pintype "power_in"))
      (node (ref "P1") (pin "P$191") (pinfunction "P$1_P$191") (pintype "power_in"))
      (node (ref "P1") (pin "P$192") (pinfunction "P$1_P$192") (pintype "power_in"))
      (node (ref "P1") (pin "P$193") (pinfunction "P$1_P$193") (pintype "power_in"))
      (node (ref "P1") (pin "P$194") (pinfunction "P$1_P$194") (pintype "power_in"))
      (node (ref "P1") (pin "P$195") (pinfunction "P$1_P$195") (pintype "power_in"))
      (node (ref "P1") (pin "P$196") (pinfunction "P$1_P$196") (pintype "power_in"))
      (node (ref "P1") (pin "P$197") (pinfunction "P$1_P$197") (pintype "power_in"))
      (node (ref "P1") (pin "P$198") (pinfunction "P$1_P$198") (pintype "power_in"))
      (node (ref "P1") (pin "P$199") (pinfunction "P$1_P$199") (pintype "power_in"))
      (node (ref "P1") (pin "P$2") (pinfunction "P$1_P$2") (pintype "power_in"))
      (node (ref "P1") (pin "P$20") (pinfunction "P$1_P$20") (pintype "power_in"))
      (node (ref "P1") (pin "P$200") (pinfunction "P$1_P$200") (pintype "power_in"))
      (node (ref "P1") (pin "P$201") (pinfunction "P$1_P$201") (pintype "power_in"))
      (node (ref "P1") (pin "P$202") (pinfunction "P$1_P$202") (pintype "power_in"))
      (node (ref "P1") (pin "P$203") (pinfunction "P$1_P$203") (pintype "power_in"))
      (node (ref "P1") (pin "P$204") (pinfunction "P$1_P$204") (pintype "power_in"))
      (node (ref "P1") (pin "P$205") (pinfunction "P$1_P$205") (pintype "power_in"))
      (node (ref "P1") (pin "P$206") (pinfunction "P$1_P$206") (pintype "power_in"))
      (node (ref "P1") (pin "P$207") (pinfunction "P$1_P$207") (pintype "power_in"))
      (node (ref "P1") (pin "P$208") (pinfunction "P$1_P$208") (pintype "power_in"))
      (node (ref "P1") (pin "P$209") (pinfunction "P$1_P$209") (pintype "power_in"))
      (node (ref "P1") (pin "P$21") (pinfunction "P$1_P$21") (pintype "power_in"))
      (node (ref "P1") (pin "P$210") (pinfunction "P$1_P$210") (pintype "power_in"))
      (node (ref "P1") (pin "P$211") (pinfunction "P$1_P$211") (pintype "power_in"))
      (node (ref "P1") (pin "P$212") (pinfunction "P$1_P$212") (pintype "power_in"))
      (node (ref "P1") (pin "P$213") (pinfunction "P$1_P$213") (pintype "power_in"))
      (node (ref "P1") (pin "P$214") (pinfunction "P$1_P$214") (pintype "power_in"))
      (node (ref "P1") (pin "P$215") (pinfunction "P$1_P$215") (pintype "power_in"))
      (node (ref "P1") (pin "P$216") (pinfunction "P$1_P$216") (pintype "power_in"))
      (node (ref "P1") (pin "P$217") (pinfunction "P$1_P$217") (pintype "power_in"))
      (node (ref "P1") (pin "P$218") (pinfunction "P$1_P$218") (pintype "power_in"))
      (node (ref "P1") (pin "P$219") (pinfunction "P$1_P$219") (pintype "power_in"))
      (node (ref "P1") (pin "P$22") (pinfunction "P$1_P$22") (pintype "power_in"))
      (node (ref "P1") (pin "P$220") (pinfunction "P$1_P$220") (pintype "power_in"))
      (node (ref "P1") (pin "P$221") (pinfunction "P$1_P$221") (pintype "power_in"))
      (node (ref "P1") (pin "P$222") (pinfunction "P$1_P$222") (pintype "power_in"))
      (node (ref "P1") (pin "P$223") (pinfunction "P$1_P$223") (pintype "power_in"))
      (node (ref "P1") (pin "P$224") (pinfunction "P$1_P$224") (pintype "power_in"))
      (node (ref "P1") (pin "P$225") (pinfunction "P$1_P$225") (pintype "power_in"))
      (node (ref "P1") (pin "P$226") (pinfunction "P$1_P$226") (pintype "power_in"))
      (node (ref "P1") (pin "P$227") (pinfunction "P$1_P$227") (pintype "power_in"))
      (node (ref "P1") (pin "P$228") (pinfunction "P$1_P$228") (pintype "power_in"))
      (node (ref "P1") (pin "P$229") (pinfunction "P$1_P$229") (pintype "power_in"))
      (node (ref "P1") (pin "P$23") (pinfunction "P$1_P$23") (pintype "power_in"))
      (node (ref "P1") (pin "P$230") (pinfunction "P$1_P$230") (pintype "power_in"))
      (node (ref "P1") (pin "P$231") (pinfunction "P$1_P$231") (pintype "power_in"))
      (node (ref "P1") (pin "P$232") (pinfunction "P$1_P$232") (pintype "power_in"))
      (node (ref "P1") (pin "P$233") (pinfunction "P$1_P$233") (pintype "power_in"))
      (node (ref "P1") (pin "P$234") (pinfunction "P$1_P$234") (pintype "power_in"))
      (node (ref "P1") (pin "P$235") (pinfunction "P$1_P$235") (pintype "power_in"))
      (node (ref "P1") (pin "P$236") (pinfunction "P$1_P$236") (pintype "power_in"))
      (node (ref "P1") (pin "P$237") (pinfunction "P$1_P$237") (pintype "power_in"))
      (node (ref "P1") (pin "P$238") (pinfunction "P$1_P$238") (pintype "power_in"))
      (node (ref "P1") (pin "P$239") (pinfunction "P$1_P$239") (pintype "power_in"))
      (node (ref "P1") (pin "P$24") (pinfunction "P$1_P$24") (pintype "power_in"))
      (node (ref "P1") (pin "P$240") (pinfunction "P$1_P$240") (pintype "power_in"))
      (node (ref "P1") (pin "P$241") (pinfunction "P$1_P$241") (pintype "power_in"))
      (node (ref "P1") (pin "P$242") (pinfunction "P$1_P$242") (pintype "power_in"))
      (node (ref "P1") (pin "P$243") (pinfunction "P$1_P$243") (pintype "power_in"))
      (node (ref "P1") (pin "P$244") (pinfunction "P$1_P$244") (pintype "power_in"))
      (node (ref "P1") (pin "P$245") (pinfunction "P$1_P$245") (pintype "power_in"))
      (node (ref "P1") (pin "P$246") (pinfunction "P$1_P$246") (pintype "power_in"))
      (node (ref "P1") (pin "P$247") (pinfunction "P$1_P$247") (pintype "power_in"))
      (node (ref "P1") (pin "P$248") (pinfunction "P$1_P$248") (pintype "power_in"))
      (node (ref "P1") (pin "P$249") (pinfunction "P$1_P$249") (pintype "power_in"))
      (node (ref "P1") (pin "P$25") (pinfunction "P$1_P$25") (pintype "power_in"))
      (node (ref "P1") (pin "P$250") (pinfunction "P$1_P$250") (pintype "power_in"))
      (node (ref "P1") (pin "P$251") (pinfunction "P$1_P$251") (pintype "power_in"))
      (node (ref "P1") (pin "P$252") (pinfunction "P$1_P$252") (pintype "power_in"))
      (node (ref "P1") (pin "P$253") (pinfunction "P$1_P$253") (pintype "power_in"))
      (node (ref "P1") (pin "P$254") (pinfunction "P$1_P$254") (pintype "power_in"))
      (node (ref "P1") (pin "P$255") (pinfunction "P$1_P$255") (pintype "power_in"))
      (node (ref "P1") (pin "P$256") (pinfunction "P$1_P$256") (pintype "power_in"))
      (node (ref "P1") (pin "P$257") (pinfunction "P$1_P$257") (pintype "power_in"))
      (node (ref "P1") (pin "P$258") (pinfunction "P$1_P$258") (pintype "power_in"))
      (node (ref "P1") (pin "P$259") (pinfunction "P$1_P$259") (pintype "power_in"))
      (node (ref "P1") (pin "P$26") (pinfunction "P$1_P$26") (pintype "power_in"))
      (node (ref "P1") (pin "P$260") (pinfunction "P$1_P$260") (pintype "power_in"))
      (node (ref "P1") (pin "P$261") (pinfunction "P$1_P$261") (pintype "power_in"))
      (node (ref "P1") (pin "P$262") (pinfunction "P$1_P$262") (pintype "power_in"))
      (node (ref "P1") (pin "P$263") (pinfunction "P$1_P$263") (pintype "power_in"))
      (node (ref "P1") (pin "P$264") (pinfunction "P$1_P$264") (pintype "power_in"))
      (node (ref "P1") (pin "P$265") (pinfunction "P$1_P$265") (pintype "power_in"))
      (node (ref "P1") (pin "P$266") (pinfunction "P$1_P$266") (pintype "power_in"))
      (node (ref "P1") (pin "P$267") (pinfunction "P$1_P$267") (pintype "power_in"))
      (node (ref "P1") (pin "P$268") (pinfunction "P$1_P$268") (pintype "power_in"))
      (node (ref "P1") (pin "P$269") (pinfunction "P$1_P$269") (pintype "power_in"))
      (node (ref "P1") (pin "P$27") (pinfunction "P$1_P$27") (pintype "power_in"))
      (node (ref "P1") (pin "P$270") (pinfunction "P$1_P$270") (pintype "power_in"))
      (node (ref "P1") (pin "P$271") (pinfunction "P$1_P$271") (pintype "power_in"))
      (node (ref "P1") (pin "P$272") (pinfunction "P$1_P$272") (pintype "power_in"))
      (node (ref "P1") (pin "P$273") (pinfunction "P$1_P$273") (pintype "power_in"))
      (node (ref "P1") (pin "P$274") (pinfunction "P$1_P$274") (pintype "power_in"))
      (node (ref "P1") (pin "P$275") (pinfunction "P$1_P$275") (pintype "power_in"))
      (node (ref "P1") (pin "P$276") (pinfunction "P$1_P$276") (pintype "power_in"))
      (node (ref "P1") (pin "P$277") (pinfunction "P$1_P$277") (pintype "power_in"))
      (node (ref "P1") (pin "P$278") (pinfunction "P$1_P$278") (pintype "power_in"))
      (node (ref "P1") (pin "P$279") (pinfunction "P$1_P$279") (pintype "power_in"))
      (node (ref "P1") (pin "P$28") (pinfunction "P$1_P$28") (pintype "power_in"))
      (node (ref "P1") (pin "P$280") (pinfunction "P$1_P$280") (pintype "power_in"))
      (node (ref "P1") (pin "P$281") (pinfunction "P$1_P$281") (pintype "power_in"))
      (node (ref "P1") (pin "P$282") (pinfunction "P$1_P$282") (pintype "power_in"))
      (node (ref "P1") (pin "P$283") (pinfunction "P$1_P$283") (pintype "power_in"))
      (node (ref "P1") (pin "P$284") (pinfunction "P$1_P$284") (pintype "power_in"))
      (node (ref "P1") (pin "P$285") (pinfunction "P$1_P$285") (pintype "power_in"))
      (node (ref "P1") (pin "P$286") (pinfunction "P$1_P$286") (pintype "power_in"))
      (node (ref "P1") (pin "P$287") (pinfunction "P$1_P$287") (pintype "power_in"))
      (node (ref "P1") (pin "P$288") (pinfunction "P$1_P$288") (pintype "power_in"))
      (node (ref "P1") (pin "P$29") (pinfunction "P$1_P$29") (pintype "power_in"))
      (node (ref "P1") (pin "P$3") (pinfunction "P$1_P$3") (pintype "power_in"))
      (node (ref "P1") (pin "P$30") (pinfunction "P$1_P$30") (pintype "power_in"))
      (node (ref "P1") (pin "P$31") (pinfunction "P$1_P$31") (pintype "power_in"))
      (node (ref "P1") (pin "P$32") (pinfunction "P$1_P$32") (pintype "power_in"))
      (node (ref "P1") (pin "P$33") (pinfunction "P$1_P$33") (pintype "power_in"))
      (node (ref "P1") (pin "P$34") (pinfunction "P$1_P$34") (pintype "power_in"))
      (node (ref "P1") (pin "P$35") (pinfunction "P$1_P$35") (pintype "power_in"))
      (node (ref "P1") (pin "P$36") (pinfunction "P$1_P$36") (pintype "power_in"))
      (node (ref "P1") (pin "P$37") (pinfunction "P$1_P$37") (pintype "power_in"))
      (node (ref "P1") (pin "P$38") (pinfunction "P$1_P$38") (pintype "power_in"))
      (node (ref "P1") (pin "P$39") (pinfunction "P$1_P$39") (pintype "power_in"))
      (node (ref "P1") (pin "P$4") (pinfunction "P$1_P$4") (pintype "power_in"))
      (node (ref "P1") (pin "P$40") (pinfunction "P$1_P$40") (pintype "power_in"))
      (node (ref "P1") (pin "P$41") (pinfunction "P$1_P$41") (pintype "power_in"))
      (node (ref "P1") (pin "P$42") (pinfunction "P$1_P$42") (pintype "power_in"))
      (node (ref "P1") (pin "P$43") (pinfunction "P$1_P$43") (pintype "power_in"))
      (node (ref "P1") (pin "P$44") (pinfunction "P$1_P$44") (pintype "power_in"))
      (node (ref "P1") (pin "P$45") (pinfunction "P$1_P$45") (pintype "power_in"))
      (node (ref "P1") (pin "P$46") (pinfunction "P$1_P$46") (pintype "power_in"))
      (node (ref "P1") (pin "P$47") (pinfunction "P$1_P$47") (pintype "power_in"))
      (node (ref "P1") (pin "P$48") (pinfunction "P$1_P$48") (pintype "power_in"))
      (node (ref "P1") (pin "P$49") (pinfunction "P$1_P$49") (pintype "power_in"))
      (node (ref "P1") (pin "P$5") (pinfunction "P$1_P$5") (pintype "power_in"))
      (node (ref "P1") (pin "P$50") (pinfunction "P$1_P$50") (pintype "power_in"))
      (node (ref "P1") (pin "P$51") (pinfunction "P$1_P$51") (pintype "power_in"))
      (node (ref "P1") (pin "P$52") (pinfunction "P$1_P$52") (pintype "power_in"))
      (node (ref "P1") (pin "P$53") (pinfunction "P$1_P$53") (pintype "power_in"))
      (node (ref "P1") (pin "P$54") (pinfunction "P$1_P$54") (pintype "power_in"))
      (node (ref "P1") (pin "P$55") (pinfunction "P$1_P$55") (pintype "power_in"))
      (node (ref "P1") (pin "P$56") (pinfunction "P$1_P$56") (pintype "power_in"))
      (node (ref "P1") (pin "P$57") (pinfunction "P$1_P$57") (pintype "power_in"))
      (node (ref "P1") (pin "P$58") (pinfunction "P$1_P$58") (pintype "power_in"))
      (node (ref "P1") (pin "P$59") (pinfunction "P$1_P$59") (pintype "power_in"))
      (node (ref "P1") (pin "P$6") (pinfunction "P$1_P$6") (pintype "power_in"))
      (node (ref "P1") (pin "P$60") (pinfunction "P$1_P$60") (pintype "power_in"))
      (node (ref "P1") (pin "P$61") (pinfunction "P$1_P$61") (pintype "power_in"))
      (node (ref "P1") (pin "P$62") (pinfunction "P$1_P$62") (pintype "power_in"))
      (node (ref "P1") (pin "P$63") (pinfunction "P$1_P$63") (pintype "power_in"))
      (node (ref "P1") (pin "P$64") (pinfunction "P$1_P$64") (pintype "power_in"))
      (node (ref "P1") (pin "P$65") (pinfunction "P$1_P$65") (pintype "power_in"))
      (node (ref "P1") (pin "P$66") (pinfunction "P$1_P$66") (pintype "power_in"))
      (node (ref "P1") (pin "P$67") (pinfunction "P$1_P$67") (pintype "power_in"))
      (node (ref "P1") (pin "P$68") (pinfunction "P$1_P$68") (pintype "power_in"))
      (node (ref "P1") (pin "P$69") (pinfunction "P$1_P$69") (pintype "power_in"))
      (node (ref "P1") (pin "P$7") (pinfunction "P$1_P$7") (pintype "power_in"))
      (node (ref "P1") (pin "P$70") (pinfunction "P$1_P$70") (pintype "power_in"))
      (node (ref "P1") (pin "P$71") (pinfunction "P$1_P$71") (pintype "power_in"))
      (node (ref "P1") (pin "P$72") (pinfunction "P$1_P$72") (pintype "power_in"))
      (node (ref "P1") (pin "P$73") (pinfunction "P$1_P$73") (pintype "power_in"))
      (node (ref "P1") (pin "P$74") (pinfunction "P$1_P$74") (pintype "power_in"))
      (node (ref "P1") (pin "P$75") (pinfunction "P$1_P$75") (pintype "power_in"))
      (node (ref "P1") (pin "P$76") (pinfunction "P$1_P$76") (pintype "power_in"))
      (node (ref "P1") (pin "P$77") (pinfunction "P$1_P$77") (pintype "power_in"))
      (node (ref "P1") (pin "P$78") (pinfunction "P$1_P$78") (pintype "power_in"))
      (node (ref "P1") (pin "P$79") (pinfunction "P$1_P$79") (pintype "power_in"))
      (node (ref "P1") (pin "P$8") (pinfunction "P$1_P$8") (pintype "power_in"))
      (node (ref "P1") (pin "P$80") (pinfunction "P$1_P$80") (pintype "power_in"))
      (node (ref "P1") (pin "P$81") (pinfunction "P$1_P$81") (pintype "power_in"))
      (node (ref "P1") (pin "P$82") (pinfunction "P$1_P$82") (pintype "power_in"))
      (node (ref "P1") (pin "P$83") (pinfunction "P$1_P$83") (pintype "power_in"))
      (node (ref "P1") (pin "P$84") (pinfunction "P$1_P$84") (pintype "power_in"))
      (node (ref "P1") (pin "P$85") (pinfunction "P$1_P$85") (pintype "power_in"))
      (node (ref "P1") (pin "P$86") (pinfunction "P$1_P$86") (pintype "power_in"))
      (node (ref "P1") (pin "P$87") (pinfunction "P$1_P$87") (pintype "power_in"))
      (node (ref "P1") (pin "P$88") (pinfunction "P$1_P$88") (pintype "power_in"))
      (node (ref "P1") (pin "P$89") (pinfunction "P$1_P$89") (pintype "power_in"))
      (node (ref "P1") (pin "P$9") (pinfunction "P$1_P$9") (pintype "power_in"))
      (node (ref "P1") (pin "P$90") (pinfunction "P$1_P$90") (pintype "power_in"))
      (node (ref "P1") (pin "P$91") (pinfunction "P$1_P$91") (pintype "power_in"))
      (node (ref "P1") (pin "P$92") (pinfunction "P$1_P$92") (pintype "power_in"))
      (node (ref "P1") (pin "P$93") (pinfunction "P$1_P$93") (pintype "power_in"))
      (node (ref "P1") (pin "P$94") (pinfunction "P$1_P$94") (pintype "power_in"))
      (node (ref "P1") (pin "P$95") (pinfunction "P$1_P$95") (pintype "power_in"))
      (node (ref "P1") (pin "P$96") (pinfunction "P$1_P$96") (pintype "power_in"))
      (node (ref "P1") (pin "P$97") (pinfunction "P$1_P$97") (pintype "power_in"))
      (node (ref "P1") (pin "P$98") (pinfunction "P$1_P$98") (pintype "power_in"))
      (node (ref "P1") (pin "P$99") (pinfunction "P$1_P$99") (pintype "power_in"))
    )
    (net (code "3") (name "/P2") (class "Default")
      (node (ref "JP1") (pin "P$3") (pinfunction "2_P$3") (pintype "bidirectional"))
      (node (ref "P2") (pin "P$1") (pinfunction "P$1_P$1") (pintype "power_in"))
      (node (ref "P2") (pin "P$10") (pinfunction "P$1_P$10") (pintype "power_in"))
      (node (ref "P2") (pin "P$100") (pinfunction "P$1_P$100") (pintype "power_in"))
      (node (ref "P2") (pin "P$101") (pinfunction "P$1_P$101") (pintype "power_in"))
      (node (ref "P2") (pin "P$102") (pinfunction "P$1_P$102") (pintype "power_in"))
      (node (ref "P2") (pin "P$103") (pinfunction "P$1_P$103") (pintype "power_in"))
      (node (ref "P2") (pin "P$104") (pinfunction "P$1_P$104") (pintype "power_in"))
      (node (ref "P2") (pin "P$105") (pinfunction "P$1_P$105") (pintype "power_in"))
      (node (ref "P2") (pin "P$106") (pinfunction "P$1_P$106") (pintype "power_in"))
      (node (ref "P2") (pin "P$107") (pinfunction "P$1_P$107") (pintype "power_in"))
      (node (ref "P2") (pin "P$108") (pinfunction "P$1_P$108") (pintype "power_in"))
      (node (ref "P2") (pin "P$109") (pinfunction "P$1_P$109") (pintype "power_in"))
      (node (ref "P2") (pin "P$11") (pinfunction "P$1_P$11") (pintype "power_in"))
      (node (ref "P2") (pin "P$110") (pinfunction "P$1_P$110") (pintype "power_in"))
      (node (ref "P2") (pin "P$111") (pinfunction "P$1_P$111") (pintype "power_in"))
      (node (ref "P2") (pin "P$112") (pinfunction "P$1_P$112") (pintype "power_in"))
      (node (ref "P2") (pin "P$113") (pinfunction "P$1_P$113") (pintype "power_in"))
      (node (ref "P2") (pin "P$114") (pinfunction "P$1_P$114") (pintype "power_in"))
      (node (ref "P2") (pin "P$115") (pinfunction "P$1_P$115") (pintype "power_in"))
      (node (ref "P2") (pin "P$116") (pinfunction "P$1_P$116") (pintype "power_in"))
      (node (ref "P2") (pin "P$117") (pinfunction "P$1_P$117") (pintype "power_in"))
      (node (ref "P2") (pin "P$118") (pinfunction "P$1_P$118") (pintype "power_in"))
      (node (ref "P2") (pin "P$119") (pinfunction "P$1_P$119") (pintype "power_in"))
      (node (ref "P2") (pin "P$12") (pinfunction "P$1_P$12") (pintype "power_in"))
      (node (ref "P2") (pin "P$120") (pinfunction "P$1_P$120") (pintype "power_in"))
      (node (ref "P2") (pin "P$121") (pinfunction "P$1_P$121") (pintype "power_in"))
      (node (ref "P2") (pin "P$122") (pinfunction "P$1_P$122") (pintype "power_in"))
      (node (ref "P2") (pin "P$123") (pinfunction "P$1_P$123") (pintype "power_in"))
      (node (ref "P2") (pin "P$124") (pinfunction "P$1_P$124") (pintype "power_in"))
      (node (ref "P2") (pin "P$125") (pinfunction "P$1_P$125") (pintype "power_in"))
      (node (ref "P2") (pin "P$126") (pinfunction "P$1_P$126") (pintype "power_in"))
      (node (ref "P2") (pin "P$127") (pinfunction "P$1_P$127") (pintype "power_in"))
      (node (ref "P2") (pin "P$128") (pinfunction "P$1_P$128") (pintype "power_in"))
      (node (ref "P2") (pin "P$129") (pinfunction "P$1_P$129") (pintype "power_in"))
      (node (ref "P2") (pin "P$13") (pinfunction "P$1_P$13") (pintype "power_in"))
      (node (ref "P2") (pin "P$130") (pinfunction "P$1_P$130") (pintype "power_in"))
      (node (ref "P2") (pin "P$131") (pinfunction "P$1_P$131") (pintype "power_in"))
      (node (ref "P2") (pin "P$132") (pinfunction "P$1_P$132") (pintype "power_in"))
      (node (ref "P2") (pin "P$133") (pinfunction "P$1_P$133") (pintype "power_in"))
      (node (ref "P2") (pin "P$134") (pinfunction "P$1_P$134") (pintype "power_in"))
      (node (ref "P2") (pin "P$135") (pinfunction "P$1_P$135") (pintype "power_in"))
      (node (ref "P2") (pin "P$136") (pinfunction "P$1_P$136") (pintype "power_in"))
      (node (ref "P2") (pin "P$137") (pinfunction "P$1_P$137") (pintype "power_in"))
      (node (ref "P2") (pin "P$138") (pinfunction "P$1_P$138") (pintype "power_in"))
      (node (ref "P2") (pin "P$139") (pinfunction "P$1_P$139") (pintype "power_in"))
      (node (ref "P2") (pin "P$14") (pinfunction "P$1_P$14") (pintype "power_in"))
      (node (ref "P2") (pin "P$140") (pinfunction "P$1_P$140") (pintype "power_in"))
      (node (ref "P2") (pin "P$141") (pinfunction "P$1_P$141") (pintype "power_in"))
      (node (ref "P2") (pin "P$142") (pinfunction "P$1_P$142") (pintype "power_in"))
      (node (ref "P2") (pin "P$143") (pinfunction "P$1_P$143") (pintype "power_in"))
      (node (ref "P2") (pin "P$144") (pinfunction "P$1_P$144") (pintype "power_in"))
      (node (ref "P2") (pin "P$145") (pinfunction "P$1_P$145") (pintype "power_in"))
      (node (ref "P2") (pin "P$146") (pinfunction "P$1_P$146") (pintype "power_in"))
      (node (ref "P2") (pin "P$147") (pinfunction "P$1_P$147") (pintype "power_in"))
      (node (ref "P2") (pin "P$148") (pinfunction "P$1_P$148") (pintype "power_in"))
      (node (ref "P2") (pin "P$149") (pinfunction "P$1_P$149") (pintype "power_in"))
      (node (ref "P2") (pin "P$15") (pinfunction "P$1_P$15") (pintype "power_in"))
      (node (ref "P2") (pin "P$150") (pinfunction "P$1_P$150") (pintype "power_in"))
      (node (ref "P2") (pin "P$151") (pinfunction "P$1_P$151") (pintype "power_in"))
      (node (ref "P2") (pin "P$152") (pinfunction "P$1_P$152") (pintype "power_in"))
      (node (ref "P2") (pin "P$153") (pinfunction "P$1_P$153") (pintype "power_in"))
      (node (ref "P2") (pin "P$154") (pinfunction "P$1_P$154") (pintype "power_in"))
      (node (ref "P2") (pin "P$155") (pinfunction "P$1_P$155") (pintype "power_in"))
      (node (ref "P2") (pin "P$156") (pinfunction "P$1_P$156") (pintype "power_in"))
      (node (ref "P2") (pin "P$157") (pinfunction "P$1_P$157") (pintype "power_in"))
      (node (ref "P2") (pin "P$158") (pinfunction "P$1_P$158") (pintype "power_in"))
      (node (ref "P2") (pin "P$159") (pinfunction "P$1_P$159") (pintype "power_in"))
      (node (ref "P2") (pin "P$16") (pinfunction "P$1_P$16") (pintype "power_in"))
      (node (ref "P2") (pin "P$160") (pinfunction "P$1_P$160") (pintype "power_in"))
      (node (ref "P2") (pin "P$161") (pinfunction "P$1_P$161") (pintype "power_in"))
      (node (ref "P2") (pin "P$162") (pinfunction "P$1_P$162") (pintype "power_in"))
      (node (ref "P2") (pin "P$163") (pinfunction "P$1_P$163") (pintype "power_in"))
      (node (ref "P2") (pin "P$164") (pinfunction "P$1_P$164") (pintype "power_in"))
      (node (ref "P2") (pin "P$165") (pinfunction "P$1_P$165") (pintype "power_in"))
      (node (ref "P2") (pin "P$166") (pinfunction "P$1_P$166") (pintype "power_in"))
      (node (ref "P2") (pin "P$167") (pinfunction "P$1_P$167") (pintype "power_in"))
      (node (ref "P2") (pin "P$168") (pinfunction "P$1_P$168") (pintype "power_in"))
      (node (ref "P2") (pin "P$169") (pinfunction "P$1_P$169") (pintype "power_in"))
      (node (ref "P2") (pin "P$17") (pinfunction "P$1_P$17") (pintype "power_in"))
      (node (ref "P2") (pin "P$170") (pinfunction "P$1_P$170") (pintype "power_in"))
      (node (ref "P2") (pin "P$171") (pinfunction "P$1_P$171") (pintype "power_in"))
      (node (ref "P2") (pin "P$172") (pinfunction "P$1_P$172") (pintype "power_in"))
      (node (ref "P2") (pin "P$173") (pinfunction "P$1_P$173") (pintype "power_in"))
      (node (ref "P2") (pin "P$174") (pinfunction "P$1_P$174") (pintype "power_in"))
      (node (ref "P2") (pin "P$175") (pinfunction "P$1_P$175") (pintype "power_in"))
      (node (ref "P2") (pin "P$176") (pinfunction "P$1_P$176") (pintype "power_in"))
      (node (ref "P2") (pin "P$177") (pinfunction "P$1_P$177") (pintype "power_in"))
      (node (ref "P2") (pin "P$178") (pinfunction "P$1_P$178") (pintype "power_in"))
      (node (ref "P2") (pin "P$179") (pinfunction "P$1_P$179") (pintype "power_in"))
      (node (ref "P2") (pin "P$18") (pinfunction "P$1_P$18") (pintype "power_in"))
      (node (ref "P2") (pin "P$180") (pinfunction "P$1_P$180") (pintype "power_in"))
      (node (ref "P2") (pin "P$181") (pinfunction "P$1_P$181") (pintype "power_in"))
      (node (ref "P2") (pin "P$182") (pinfunction "P$1_P$182") (pintype "power_in"))
      (node (ref "P2") (pin "P$183") (pinfunction "P$1_P$183") (pintype "power_in"))
      (node (ref "P2") (pin "P$184") (pinfunction "P$1_P$184") (pintype "power_in"))
      (node (ref "P2") (pin "P$185") (pinfunction "P$1_P$185") (pintype "power_in"))
      (node (ref "P2") (pin "P$186") (pinfunction "P$1_P$186") (pintype "power_in"))
      (node (ref "P2") (pin "P$187") (pinfunction "P$1_P$187") (pintype "power_in"))
      (node (ref "P2") (pin "P$188") (pinfunction "P$1_P$188") (pintype "power_in"))
      (node (ref "P2") (pin "P$189") (pinfunction "P$1_P$189") (pintype "power_in"))
      (node (ref "P2") (pin "P$19") (pinfunction "P$1_P$19") (pintype "power_in"))
      (node (ref "P2") (pin "P$190") (pinfunction "P$1_P$190") (pintype "power_in"))
      (node (ref "P2") (pin "P$191") (pinfunction "P$1_P$191") (pintype "power_in"))
      (node (ref "P2") (pin "P$192") (pinfunction "P$1_P$192") (pintype "power_in"))
      (node (ref "P2") (pin "P$193") (pinfunction "P$1_P$193") (pintype "power_in"))
      (node (ref "P2") (pin "P$194") (pinfunction "P$1_P$194") (pintype "power_in"))
      (node (ref "P2") (pin "P$195") (pinfunction "P$1_P$195") (pintype "power_in"))
      (node (ref "P2") (pin "P$196") (pinfunction "P$1_P$196") (pintype "power_in"))
      (node (ref "P2") (pin "P$197") (pinfunction "P$1_P$197") (pintype "power_in"))
      (node (ref "P2") (pin "P$198") (pinfunction "P$1_P$198") (pintype "power_in"))
      (node (ref "P2") (pin "P$199") (pinfunction "P$1_P$199") (pintype "power_in"))
      (node (ref "P2") (pin "P$2") (pinfunction "P$1_P$2") (pintype "power_in"))
      (node (ref "P2") (pin "P$20") (pinfunction "P$1_P$20") (pintype "power_in"))
      (node (ref "P2") (pin "P$200") (pinfunction "P$1_P$200") (pintype "power_in"))
      (node (ref "P2") (pin "P$201") (pinfunction "P$1_P$201") (pintype "power_in"))
      (node (ref "P2") (pin "P$202") (pinfunction "P$1_P$202") (pintype "power_in"))
      (node (ref "P2") (pin "P$203") (pinfunction "P$1_P$203") (pintype "power_in"))
      (node (ref "P2") (pin "P$204") (pinfunction "P$1_P$204") (pintype "power_in"))
      (node (ref "P2") (pin "P$205") (pinfunction "P$1_P$205") (pintype "power_in"))
      (node (ref "P2") (pin "P$206") (pinfunction "P$1_P$206") (pintype "power_in"))
      (node (ref "P2") (pin "P$207") (pinfunction "P$1_P$207") (pintype "power_in"))
      (node (ref "P2") (pin "P$208") (pinfunction "P$1_P$208") (pintype "power_in"))
      (node (ref "P2") (pin "P$209") (pinfunction "P$1_P$209") (pintype "power_in"))
      (node (ref "P2") (pin "P$21") (pinfunction "P$1_P$21") (pintype "power_in"))
      (node (ref "P2") (pin "P$210") (pinfunction "P$1_P$210") (pintype "power_in"))
      (node (ref "P2") (pin "P$211") (pinfunction "P$1_P$211") (pintype "power_in"))
      (node (ref "P2") (pin "P$212") (pinfunction "P$1_P$212") (pintype "power_in"))
      (node (ref "P2") (pin "P$213") (pinfunction "P$1_P$213") (pintype "power_in"))
      (node (ref "P2") (pin "P$214") (pinfunction "P$1_P$214") (pintype "power_in"))
      (node (ref "P2") (pin "P$215") (pinfunction "P$1_P$215") (pintype "power_in"))
      (node (ref "P2") (pin "P$216") (pinfunction "P$1_P$216") (pintype "power_in"))
      (node (ref "P2") (pin "P$217") (pinfunction "P$1_P$217") (pintype "power_in"))
      (node (ref "P2") (pin "P$218") (pinfunction "P$1_P$218") (pintype "power_in"))
      (node (ref "P2") (pin "P$219") (pinfunction "P$1_P$219") (pintype "power_in"))
      (node (ref "P2") (pin "P$22") (pinfunction "P$1_P$22") (pintype "power_in"))
      (node (ref "P2") (pin "P$220") (pinfunction "P$1_P$220") (pintype "power_in"))
      (node (ref "P2") (pin "P$221") (pinfunction "P$1_P$221") (pintype "power_in"))
      (node (ref "P2") (pin "P$222") (pinfunction "P$1_P$222") (pintype "power_in"))
      (node (ref "P2") (pin "P$223") (pinfunction "P$1_P$223") (pintype "power_in"))
      (node (ref "P2") (pin "P$224") (pinfunction "P$1_P$224") (pintype "power_in"))
      (node (ref "P2") (pin "P$225") (pinfunction "P$1_P$225") (pintype "power_in"))
      (node (ref "P2") (pin "P$226") (pinfunction "P$1_P$226") (pintype "power_in"))
      (node (ref "P2") (pin "P$227") (pinfunction "P$1_P$227") (pintype "power_in"))
      (node (ref "P2") (pin "P$228") (pinfunction "P$1_P$228") (pintype "power_in"))
      (node (ref "P2") (pin "P$229") (pinfunction "P$1_P$229") (pintype "power_in"))
      (node (ref "P2") (pin "P$23") (pinfunction "P$1_P$23") (pintype "power_in"))
      (node (ref "P2") (pin "P$230") (pinfunction "P$1_P$230") (pintype "power_in"))
      (node (ref "P2") (pin "P$231") (pinfunction "P$1_P$231") (pintype "power_in"))
      (node (ref "P2") (pin "P$232") (pinfunction "P$1_P$232") (pintype "power_in"))
      (node (ref "P2") (pin "P$233") (pinfunction "P$1_P$233") (pintype "power_in"))
      (node (ref "P2") (pin "P$234") (pinfunction "P$1_P$234") (pintype "power_in"))
      (node (ref "P2") (pin "P$235") (pinfunction "P$1_P$235") (pintype "power_in"))
      (node (ref "P2") (pin "P$236") (pinfunction "P$1_P$236") (pintype "power_in"))
      (node (ref "P2") (pin "P$237") (pinfunction "P$1_P$237") (pintype "power_in"))
      (node (ref "P2") (pin "P$238") (pinfunction "P$1_P$238") (pintype "power_in"))
      (node (ref "P2") (pin "P$239") (pinfunction "P$1_P$239") (pintype "power_in"))
      (node (ref "P2") (pin "P$24") (pinfunction "P$1_P$24") (pintype "power_in"))
      (node (ref "P2") (pin "P$240") (pinfunction "P$1_P$240") (pintype "power_in"))
      (node (ref "P2") (pin "P$241") (pinfunction "P$1_P$241") (pintype "power_in"))
      (node (ref "P2") (pin "P$242") (pinfunction "P$1_P$242") (pintype "power_in"))
      (node (ref "P2") (pin "P$243") (pinfunction "P$1_P$243") (pintype "power_in"))
      (node (ref "P2") (pin "P$244") (pinfunction "P$1_P$244") (pintype "power_in"))
      (node (ref "P2") (pin "P$245") (pinfunction "P$1_P$245") (pintype "power_in"))
      (node (ref "P2") (pin "P$246") (pinfunction "P$1_P$246") (pintype "power_in"))
      (node (ref "P2") (pin "P$247") (pinfunction "P$1_P$247") (pintype "power_in"))
      (node (ref "P2") (pin "P$248") (pinfunction "P$1_P$248") (pintype "power_in"))
      (node (ref "P2") (pin "P$249") (pinfunction "P$1_P$249") (pintype "power_in"))
      (node (ref "P2") (pin "P$25") (pinfunction "P$1_P$25") (pintype "power_in"))
      (node (ref "P2") (pin "P$250") (pinfunction "P$1_P$250") (pintype "power_in"))
      (node (ref "P2") (pin "P$251") (pinfunction "P$1_P$251") (pintype "power_in"))
      (node (ref "P2") (pin "P$252") (pinfunction "P$1_P$252") (pintype "power_in"))
      (node (ref "P2") (pin "P$253") (pinfunction "P$1_P$253") (pintype "power_in"))
      (node (ref "P2") (pin "P$254") (pinfunction "P$1_P$254") (pintype "power_in"))
      (node (ref "P2") (pin "P$255") (pinfunction "P$1_P$255") (pintype "power_in"))
      (node (ref "P2") (pin "P$256") (pinfunction "P$1_P$256") (pintype "power_in"))
      (node (ref "P2") (pin "P$257") (pinfunction "P$1_P$257") (pintype "power_in"))
      (node (ref "P2") (pin "P$258") (pinfunction "P$1_P$258") (pintype "power_in"))
      (node (ref "P2") (pin "P$259") (pinfunction "P$1_P$259") (pintype "power_in"))
      (node (ref "P2") (pin "P$26") (pinfunction "P$1_P$26") (pintype "power_in"))
      (node (ref "P2") (pin "P$260") (pinfunction "P$1_P$260") (pintype "power_in"))
      (node (ref "P2") (pin "P$261") (pinfunction "P$1_P$261") (pintype "power_in"))
      (node (ref "P2") (pin "P$262") (pinfunction "P$1_P$262") (pintype "power_in"))
      (node (ref "P2") (pin "P$263") (pinfunction "P$1_P$263") (pintype "power_in"))
      (node (ref "P2") (pin "P$264") (pinfunction "P$1_P$264") (pintype "power_in"))
      (node (ref "P2") (pin "P$265") (pinfunction "P$1_P$265") (pintype "power_in"))
      (node (ref "P2") (pin "P$266") (pinfunction "P$1_P$266") (pintype "power_in"))
      (node (ref "P2") (pin "P$267") (pinfunction "P$1_P$267") (pintype "power_in"))
      (node (ref "P2") (pin "P$268") (pinfunction "P$1_P$268") (pintype "power_in"))
      (node (ref "P2") (pin "P$269") (pinfunction "P$1_P$269") (pintype "power_in"))
      (node (ref "P2") (pin "P$27") (pinfunction "P$1_P$27") (pintype "power_in"))
      (node (ref "P2") (pin "P$270") (pinfunction "P$1_P$270") (pintype "power_in"))
      (node (ref "P2") (pin "P$271") (pinfunction "P$1_P$271") (pintype "power_in"))
      (node (ref "P2") (pin "P$272") (pinfunction "P$1_P$272") (pintype "power_in"))
      (node (ref "P2") (pin "P$273") (pinfunction "P$1_P$273") (pintype "power_in"))
      (node (ref "P2") (pin "P$274") (pinfunction "P$1_P$274") (pintype "power_in"))
      (node (ref "P2") (pin "P$275") (pinfunction "P$1_P$275") (pintype "power_in"))
      (node (ref "P2") (pin "P$276") (pinfunction "P$1_P$276") (pintype "power_in"))
      (node (ref "P2") (pin "P$277") (pinfunction "P$1_P$277") (pintype "power_in"))
      (node (ref "P2") (pin "P$278") (pinfunction "P$1_P$278") (pintype "power_in"))
      (node (ref "P2") (pin "P$279") (pinfunction "P$1_P$279") (pintype "power_in"))
      (node (ref "P2") (pin "P$28") (pinfunction "P$1_P$28") (pintype "power_in"))
      (node (ref "P2") (pin "P$280") (pinfunction "P$1_P$280") (pintype "power_in"))
      (node (ref "P2") (pin "P$281") (pinfunction "P$1_P$281") (pintype "power_in"))
      (node (ref "P2") (pin "P$282") (pinfunction "P$1_P$282") (pintype "power_in"))
      (node (ref "P2") (pin "P$283") (pinfunction "P$1_P$283") (pintype "power_in"))
      (node (ref "P2") (pin "P$284") (pinfunction "P$1_P$284") (pintype "power_in"))
      (node (ref "P2") (pin "P$285") (pinfunction "P$1_P$285") (pintype "power_in"))
      (node (ref "P2") (pin "P$286") (pinfunction "P$1_P$286") (pintype "power_in"))
      (node (ref "P2") (pin "P$287") (pinfunction "P$1_P$287") (pintype "power_in"))
      (node (ref "P2") (pin "P$288") (pinfunction "P$1_P$288") (pintype "power_in"))
      (node (ref "P2") (pin "P$29") (pinfunction "P$1_P$29") (pintype "power_in"))
      (node (ref "P2") (pin "P$3") (pinfunction "P$1_P$3") (pintype "power_in"))
      (node (ref "P2") (pin "P$30") (pinfunction "P$1_P$30") (pintype "power_in"))
      (node (ref "P2") (pin "P$31") (pinfunction "P$1_P$31") (pintype "power_in"))
      (node (ref "P2") (pin "P$32") (pinfunction "P$1_P$32") (pintype "power_in"))
      (node (ref "P2") (pin "P$33") (pinfunction "P$1_P$33") (pintype "power_in"))
      (node (ref "P2") (pin "P$34") (pinfunction "P$1_P$34") (pintype "power_in"))
      (node (ref "P2") (pin "P$35") (pinfunction "P$1_P$35") (pintype "power_in"))
      (node (ref "P2") (pin "P$36") (pinfunction "P$1_P$36") (pintype "power_in"))
      (node (ref "P2") (pin "P$37") (pinfunction "P$1_P$37") (pintype "power_in"))
      (node (ref "P2") (pin "P$38") (pinfunction "P$1_P$38") (pintype "power_in"))
      (node (ref "P2") (pin "P$39") (pinfunction "P$1_P$39") (pintype "power_in"))
      (node (ref "P2") (pin "P$4") (pinfunction "P$1_P$4") (pintype "power_in"))
      (node (ref "P2") (pin "P$40") (pinfunction "P$1_P$40") (pintype "power_in"))
      (node (ref "P2") (pin "P$41") (pinfunction "P$1_P$41") (pintype "power_in"))
      (node (ref "P2") (pin "P$42") (pinfunction "P$1_P$42") (pintype "power_in"))
      (node (ref "P2") (pin "P$43") (pinfunction "P$1_P$43") (pintype "power_in"))
      (node (ref "P2") (pin "P$44") (pinfunction "P$1_P$44") (pintype "power_in"))
      (node (ref "P2") (pin "P$45") (pinfunction "P$1_P$45") (pintype "power_in"))
      (node (ref "P2") (pin "P$46") (pinfunction "P$1_P$46") (pintype "power_in"))
      (node (ref "P2") (pin "P$47") (pinfunction "P$1_P$47") (pintype "power_in"))
      (node (ref "P2") (pin "P$48") (pinfunction "P$1_P$48") (pintype "power_in"))
      (node (ref "P2") (pin "P$49") (pinfunction "P$1_P$49") (pintype "power_in"))
      (node (ref "P2") (pin "P$5") (pinfunction "P$1_P$5") (pintype "power_in"))
      (node (ref "P2") (pin "P$50") (pinfunction "P$1_P$50") (pintype "power_in"))
      (node (ref "P2") (pin "P$51") (pinfunction "P$1_P$51") (pintype "power_in"))
      (node (ref "P2") (pin "P$52") (pinfunction "P$1_P$52") (pintype "power_in"))
      (node (ref "P2") (pin "P$53") (pinfunction "P$1_P$53") (pintype "power_in"))
      (node (ref "P2") (pin "P$54") (pinfunction "P$1_P$54") (pintype "power_in"))
      (node (ref "P2") (pin "P$55") (pinfunction "P$1_P$55") (pintype "power_in"))
      (node (ref "P2") (pin "P$56") (pinfunction "P$1_P$56") (pintype "power_in"))
      (node (ref "P2") (pin "P$57") (pinfunction "P$1_P$57") (pintype "power_in"))
      (node (ref "P2") (pin "P$58") (pinfunction "P$1_P$58") (pintype "power_in"))
      (node (ref "P2") (pin "P$59") (pinfunction "P$1_P$59") (pintype "power_in"))
      (node (ref "P2") (pin "P$6") (pinfunction "P$1_P$6") (pintype "power_in"))
      (node (ref "P2") (pin "P$60") (pinfunction "P$1_P$60") (pintype "power_in"))
      (node (ref "P2") (pin "P$61") (pinfunction "P$1_P$61") (pintype "power_in"))
      (node (ref "P2") (pin "P$62") (pinfunction "P$1_P$62") (pintype "power_in"))
      (node (ref "P2") (pin "P$63") (pinfunction "P$1_P$63") (pintype "power_in"))
      (node (ref "P2") (pin "P$64") (pinfunction "P$1_P$64") (pintype "power_in"))
      (node (ref "P2") (pin "P$65") (pinfunction "P$1_P$65") (pintype "power_in"))
      (node (ref "P2") (pin "P$66") (pinfunction "P$1_P$66") (pintype "power_in"))
      (node (ref "P2") (pin "P$67") (pinfunction "P$1_P$67") (pintype "power_in"))
      (node (ref "P2") (pin "P$68") (pinfunction "P$1_P$68") (pintype "power_in"))
      (node (ref "P2") (pin "P$69") (pinfunction "P$1_P$69") (pintype "power_in"))
      (node (ref "P2") (pin "P$7") (pinfunction "P$1_P$7") (pintype "power_in"))
      (node (ref "P2") (pin "P$70") (pinfunction "P$1_P$70") (pintype "power_in"))
      (node (ref "P2") (pin "P$71") (pinfunction "P$1_P$71") (pintype "power_in"))
      (node (ref "P2") (pin "P$72") (pinfunction "P$1_P$72") (pintype "power_in"))
      (node (ref "P2") (pin "P$73") (pinfunction "P$1_P$73") (pintype "power_in"))
      (node (ref "P2") (pin "P$74") (pinfunction "P$1_P$74") (pintype "power_in"))
      (node (ref "P2") (pin "P$75") (pinfunction "P$1_P$75") (pintype "power_in"))
      (node (ref "P2") (pin "P$76") (pinfunction "P$1_P$76") (pintype "power_in"))
      (node (ref "P2") (pin "P$77") (pinfunction "P$1_P$77") (pintype "power_in"))
      (node (ref "P2") (pin "P$78") (pinfunction "P$1_P$78") (pintype "power_in"))
      (node (ref "P2") (pin "P$79") (pinfunction "P$1_P$79") (pintype "power_in"))
      (node (ref "P2") (pin "P$8") (pinfunction "P$1_P$8") (pintype "power_in"))
      (node (ref "P2") (pin "P$80") (pinfunction "P$1_P$80") (pintype "power_in"))
      (node (ref "P2") (pin "P$81") (pinfunction "P$1_P$81") (pintype "power_in"))
      (node (ref "P2") (pin "P$82") (pinfunction "P$1_P$82") (pintype "power_in"))
      (node (ref "P2") (pin "P$83") (pinfunction "P$1_P$83") (pintype "power_in"))
      (node (ref "P2") (pin "P$84") (pinfunction "P$1_P$84") (pintype "power_in"))
      (node (ref "P2") (pin "P$85") (pinfunction "P$1_P$85") (pintype "power_in"))
      (node (ref "P2") (pin "P$86") (pinfunction "P$1_P$86") (pintype "power_in"))
      (node (ref "P2") (pin "P$87") (pinfunction "P$1_P$87") (pintype "power_in"))
      (node (ref "P2") (pin "P$88") (pinfunction "P$1_P$88") (pintype "power_in"))
      (node (ref "P2") (pin "P$89") (pinfunction "P$1_P$89") (pintype "power_in"))
      (node (ref "P2") (pin "P$9") (pinfunction "P$1_P$9") (pintype "power_in"))
      (node (ref "P2") (pin "P$90") (pinfunction "P$1_P$90") (pintype "power_in"))
      (node (ref "P2") (pin "P$91") (pinfunction "P$1_P$91") (pintype "power_in"))
      (node (ref "P2") (pin "P$92") (pinfunction "P$1_P$92") (pintype "power_in"))
      (node (ref "P2") (pin "P$93") (pinfunction "P$1_P$93") (pintype "power_in"))
      (node (ref "P2") (pin "P$94") (pinfunction "P$1_P$94") (pintype "power_in"))
      (node (ref "P2") (pin "P$95") (pinfunction "P$1_P$95") (pintype "power_in"))
      (node (ref "P2") (pin "P$96") (pinfunction "P$1_P$96") (pintype "power_in"))
      (node (ref "P2") (pin "P$97") (pinfunction "P$1_P$97") (pintype "power_in"))
      (node (ref "P2") (pin "P$98") (pinfunction "P$1_P$98") (pintype "power_in"))
      (node (ref "P2") (pin "P$99") (pinfunction "P$1_P$99") (pintype "power_in"))
    )
    (net (code "4") (name "/P3") (class "Default")
      (node (ref "JP1") (pin "P$4") (pinfunction "3_P$4") (pintype "bidirectional"))
      (node (ref "P3") (pin "P$1") (pinfunction "P$1_P$1") (pintype "power_in"))
      (node (ref "P3") (pin "P$10") (pinfunction "P$1_P$10") (pintype "power_in"))
      (node (ref "P3") (pin "P$100") (pinfunction "P$1_P$100") (pintype "power_in"))
      (node (ref "P3") (pin "P$101") (pinfunction "P$1_P$101") (pintype "power_in"))
      (node (ref "P3") (pin "P$102") (pinfunction "P$1_P$102") (pintype "power_in"))
      (node (ref "P3") (pin "P$103") (pinfunction "P$1_P$103") (pintype "power_in"))
      (node (ref "P3") (pin "P$104") (pinfunction "P$1_P$104") (pintype "power_in"))
      (node (ref "P3") (pin "P$105") (pinfunction "P$1_P$105") (pintype "power_in"))
      (node (ref "P3") (pin "P$106") (pinfunction "P$1_P$106") (pintype "power_in"))
      (node (ref "P3") (pin "P$107") (pinfunction "P$1_P$107") (pintype "power_in"))
      (node (ref "P3") (pin "P$108") (pinfunction "P$1_P$108") (pintype "power_in"))
      (node (ref "P3") (pin "P$109") (pinfunction "P$1_P$109") (pintype "power_in"))
      (node (ref "P3") (pin "P$11") (pinfunction "P$1_P$11") (pintype "power_in"))
      (node (ref "P3") (pin "P$110") (pinfunction "P$1_P$110") (pintype "power_in"))
      (node (ref "P3") (pin "P$111") (pinfunction "P$1_P$111") (pintype "power_in"))
      (node (ref "P3") (pin "P$112") (pinfunction "P$1_P$112") (pintype "power_in"))
      (node (ref "P3") (pin "P$113") (pinfunction "P$1_P$113") (pintype "power_in"))
      (node (ref "P3") (pin "P$114") (pinfunction "P$1_P$114") (pintype "power_in"))
      (node (ref "P3") (pin "P$115") (pinfunction "P$1_P$115") (pintype "power_in"))
      (node (ref "P3") (pin "P$116") (pinfunction "P$1_P$116") (pintype "power_in"))
      (node (ref "P3") (pin "P$117") (pinfunction "P$1_P$117") (pintype "power_in"))
      (node (ref "P3") (pin "P$118") (pinfunction "P$1_P$118") (pintype "power_in"))
      (node (ref "P3") (pin "P$119") (pinfunction "P$1_P$119") (pintype "power_in"))
      (node (ref "P3") (pin "P$12") (pinfunction "P$1_P$12") (pintype "power_in"))
      (node (ref "P3") (pin "P$120") (pinfunction "P$1_P$120") (pintype "power_in"))
      (node (ref "P3") (pin "P$121") (pinfunction "P$1_P$121") (pintype "power_in"))
      (node (ref "P3") (pin "P$122") (pinfunction "P$1_P$122") (pintype "power_in"))
      (node (ref "P3") (pin "P$123") (pinfunction "P$1_P$123") (pintype "power_in"))
      (node (ref "P3") (pin "P$124") (pinfunction "P$1_P$124") (pintype "power_in"))
      (node (ref "P3") (pin "P$125") (pinfunction "P$1_P$125") (pintype "power_in"))
      (node (ref "P3") (pin "P$126") (pinfunction "P$1_P$126") (pintype "power_in"))
      (node (ref "P3") (pin "P$127") (pinfunction "P$1_P$127") (pintype "power_in"))
      (node (ref "P3") (pin "P$128") (pinfunction "P$1_P$128") (pintype "power_in"))
      (node (ref "P3") (pin "P$129") (pinfunction "P$1_P$129") (pintype "power_in"))
      (node (ref "P3") (pin "P$13") (pinfunction "P$1_P$13") (pintype "power_in"))
      (node (ref "P3") (pin "P$130") (pinfunction "P$1_P$130") (pintype "power_in"))
      (node (ref "P3") (pin "P$131") (pinfunction "P$1_P$131") (pintype "power_in"))
      (node (ref "P3") (pin "P$132") (pinfunction "P$1_P$132") (pintype "power_in"))
      (node (ref "P3") (pin "P$133") (pinfunction "P$1_P$133") (pintype "power_in"))
      (node (ref "P3") (pin "P$134") (pinfunction "P$1_P$134") (pintype "power_in"))
      (node (ref "P3") (pin "P$135") (pinfunction "P$1_P$135") (pintype "power_in"))
      (node (ref "P3") (pin "P$136") (pinfunction "P$1_P$136") (pintype "power_in"))
      (node (ref "P3") (pin "P$137") (pinfunction "P$1_P$137") (pintype "power_in"))
      (node (ref "P3") (pin "P$138") (pinfunction "P$1_P$138") (pintype "power_in"))
      (node (ref "P3") (pin "P$139") (pinfunction "P$1_P$139") (pintype "power_in"))
      (node (ref "P3") (pin "P$14") (pinfunction "P$1_P$14") (pintype "power_in"))
      (node (ref "P3") (pin "P$140") (pinfunction "P$1_P$140") (pintype "power_in"))
      (node (ref "P3") (pin "P$141") (pinfunction "P$1_P$141") (pintype "power_in"))
      (node (ref "P3") (pin "P$142") (pinfunction "P$1_P$142") (pintype "power_in"))
      (node (ref "P3") (pin "P$143") (pinfunction "P$1_P$143") (pintype "power_in"))
      (node (ref "P3") (pin "P$144") (pinfunction "P$1_P$144") (pintype "power_in"))
      (node (ref "P3") (pin "P$145") (pinfunction "P$1_P$145") (pintype "power_in"))
      (node (ref "P3") (pin "P$146") (pinfunction "P$1_P$146") (pintype "power_in"))
      (node (ref "P3") (pin "P$147") (pinfunction "P$1_P$147") (pintype "power_in"))
      (node (ref "P3") (pin "P$148") (pinfunction "P$1_P$148") (pintype "power_in"))
      (node (ref "P3") (pin "P$149") (pinfunction "P$1_P$149") (pintype "power_in"))
      (node (ref "P3") (pin "P$15") (pinfunction "P$1_P$15") (pintype "power_in"))
      (node (ref "P3") (pin "P$150") (pinfunction "P$1_P$150") (pintype "power_in"))
      (node (ref "P3") (pin "P$151") (pinfunction "P$1_P$151") (pintype "power_in"))
      (node (ref "P3") (pin "P$152") (pinfunction "P$1_P$152") (pintype "power_in"))
      (node (ref "P3") (pin "P$153") (pinfunction "P$1_P$153") (pintype "power_in"))
      (node (ref "P3") (pin "P$154") (pinfunction "P$1_P$154") (pintype "power_in"))
      (node (ref "P3") (pin "P$155") (pinfunction "P$1_P$155") (pintype "power_in"))
      (node (ref "P3") (pin "P$156") (pinfunction "P$1_P$156") (pintype "power_in"))
      (node (ref "P3") (pin "P$157") (pinfunction "P$1_P$157") (pintype "power_in"))
      (node (ref "P3") (pin "P$158") (pinfunction "P$1_P$158") (pintype "power_in"))
      (node (ref "P3") (pin "P$159") (pinfunction "P$1_P$159") (pintype "power_in"))
      (node (ref "P3") (pin "P$16") (pinfunction "P$1_P$16") (pintype "power_in"))
      (node (ref "P3") (pin "P$160") (pinfunction "P$1_P$160") (pintype "power_in"))
      (node (ref "P3") (pin "P$161") (pinfunction "P$1_P$161") (pintype "power_in"))
      (node (ref "P3") (pin "P$162") (pinfunction "P$1_P$162") (pintype "power_in"))
      (node (ref "P3") (pin "P$163") (pinfunction "P$1_P$163") (pintype "power_in"))
      (node (ref "P3") (pin "P$164") (pinfunction "P$1_P$164") (pintype "power_in"))
      (node (ref "P3") (pin "P$165") (pinfunction "P$1_P$165") (pintype "power_in"))
      (node (ref "P3") (pin "P$166") (pinfunction "P$1_P$166") (pintype "power_in"))
      (node (ref "P3") (pin "P$167") (pinfunction "P$1_P$167") (pintype "power_in"))
      (node (ref "P3") (pin "P$168") (pinfunction "P$1_P$168") (pintype "power_in"))
      (node (ref "P3") (pin "P$169") (pinfunction "P$1_P$169") (pintype "power_in"))
      (node (ref "P3") (pin "P$17") (pinfunction "P$1_P$17") (pintype "power_in"))
      (node (ref "P3") (pin "P$170") (pinfunction "P$1_P$170") (pintype "power_in"))
      (node (ref "P3") (pin "P$171") (pinfunction "P$1_P$171") (pintype "power_in"))
      (node (ref "P3") (pin "P$172") (pinfunction "P$1_P$172") (pintype "power_in"))
      (node (ref "P3") (pin "P$173") (pinfunction "P$1_P$173") (pintype "power_in"))
      (node (ref "P3") (pin "P$174") (pinfunction "P$1_P$174") (pintype "power_in"))
      (node (ref "P3") (pin "P$175") (pinfunction "P$1_P$175") (pintype "power_in"))
      (node (ref "P3") (pin "P$176") (pinfunction "P$1_P$176") (pintype "power_in"))
      (node (ref "P3") (pin "P$177") (pinfunction "P$1_P$177") (pintype "power_in"))
      (node (ref "P3") (pin "P$178") (pinfunction "P$1_P$178") (pintype "power_in"))
      (node (ref "P3") (pin "P$179") (pinfunction "P$1_P$179") (pintype "power_in"))
      (node (ref "P3") (pin "P$18") (pinfunction "P$1_P$18") (pintype "power_in"))
      (node (ref "P3") (pin "P$180") (pinfunction "P$1_P$180") (pintype "power_in"))
      (node (ref "P3") (pin "P$181") (pinfunction "P$1_P$181") (pintype "power_in"))
      (node (ref "P3") (pin "P$182") (pinfunction "P$1_P$182") (pintype "power_in"))
      (node (ref "P3") (pin "P$183") (pinfunction "P$1_P$183") (pintype "power_in"))
      (node (ref "P3") (pin "P$184") (pinfunction "P$1_P$184") (pintype "power_in"))
      (node (ref "P3") (pin "P$185") (pinfunction "P$1_P$185") (pintype "power_in"))
      (node (ref "P3") (pin "P$186") (pinfunction "P$1_P$186") (pintype "power_in"))
      (node (ref "P3") (pin "P$187") (pinfunction "P$1_P$187") (pintype "power_in"))
      (node (ref "P3") (pin "P$188") (pinfunction "P$1_P$188") (pintype "power_in"))
      (node (ref "P3") (pin "P$189") (pinfunction "P$1_P$189") (pintype "power_in"))
      (node (ref "P3") (pin "P$19") (pinfunction "P$1_P$19") (pintype "power_in"))
      (node (ref "P3") (pin "P$190") (pinfunction "P$1_P$190") (pintype "power_in"))
      (node (ref "P3") (pin "P$191") (pinfunction "P$1_P$191") (pintype "power_in"))
      (node (ref "P3") (pin "P$192") (pinfunction "P$1_P$192") (pintype "power_in"))
      (node (ref "P3") (pin "P$193") (pinfunction "P$1_P$193") (pintype "power_in"))
      (node (ref "P3") (pin "P$194") (pinfunction "P$1_P$194") (pintype "power_in"))
      (node (ref "P3") (pin "P$195") (pinfunction "P$1_P$195") (pintype "power_in"))
      (node (ref "P3") (pin "P$196") (pinfunction "P$1_P$196") (pintype "power_in"))
      (node (ref "P3") (pin "P$197") (pinfunction "P$1_P$197") (pintype "power_in"))
      (node (ref "P3") (pin "P$198") (pinfunction "P$1_P$198") (pintype "power_in"))
      (node (ref "P3") (pin "P$199") (pinfunction "P$1_P$199") (pintype "power_in"))
      (node (ref "P3") (pin "P$2") (pinfunction "P$1_P$2") (pintype "power_in"))
      (node (ref "P3") (pin "P$20") (pinfunction "P$1_P$20") (pintype "power_in"))
      (node (ref "P3") (pin "P$200") (pinfunction "P$1_P$200") (pintype "power_in"))
      (node (ref "P3") (pin "P$201") (pinfunction "P$1_P$201") (pintype "power_in"))
      (node (ref "P3") (pin "P$202") (pinfunction "P$1_P$202") (pintype "power_in"))
      (node (ref "P3") (pin "P$203") (pinfunction "P$1_P$203") (pintype "power_in"))
      (node (ref "P3") (pin "P$204") (pinfunction "P$1_P$204") (pintype "power_in"))
      (node (ref "P3") (pin "P$205") (pinfunction "P$1_P$205") (pintype "power_in"))
      (node (ref "P3") (pin "P$206") (pinfunction "P$1_P$206") (pintype "power_in"))
      (node (ref "P3") (pin "P$207") (pinfunction "P$1_P$207") (pintype "power_in"))
      (node (ref "P3") (pin "P$208") (pinfunction "P$1_P$208") (pintype "power_in"))
      (node (ref "P3") (pin "P$209") (pinfunction "P$1_P$209") (pintype "power_in"))
      (node (ref "P3") (pin "P$21") (pinfunction "P$1_P$21") (pintype "power_in"))
      (node (ref "P3") (pin "P$210") (pinfunction "P$1_P$210") (pintype "power_in"))
      (node (ref "P3") (pin "P$211") (pinfunction "P$1_P$211") (pintype "power_in"))
      (node (ref "P3") (pin "P$212") (pinfunction "P$1_P$212") (pintype "power_in"))
      (node (ref "P3") (pin "P$213") (pinfunction "P$1_P$213") (pintype "power_in"))
      (node (ref "P3") (pin "P$214") (pinfunction "P$1_P$214") (pintype "power_in"))
      (node (ref "P3") (pin "P$215") (pinfunction "P$1_P$215") (pintype "power_in"))
      (node (ref "P3") (pin "P$216") (pinfunction "P$1_P$216") (pintype "power_in"))
      (node (ref "P3") (pin "P$217") (pinfunction "P$1_P$217") (pintype "power_in"))
      (node (ref "P3") (pin "P$218") (pinfunction "P$1_P$218") (pintype "power_in"))
      (node (ref "P3") (pin "P$219") (pinfunction "P$1_P$219") (pintype "power_in"))
      (node (ref "P3") (pin "P$22") (pinfunction "P$1_P$22") (pintype "power_in"))
      (node (ref "P3") (pin "P$220") (pinfunction "P$1_P$220") (pintype "power_in"))
      (node (ref "P3") (pin "P$221") (pinfunction "P$1_P$221") (pintype "power_in"))
      (node (ref "P3") (pin "P$222") (pinfunction "P$1_P$222") (pintype "power_in"))
      (node (ref "P3") (pin "P$223") (pinfunction "P$1_P$223") (pintype "power_in"))
      (node (ref "P3") (pin "P$224") (pinfunction "P$1_P$224") (pintype "power_in"))
      (node (ref "P3") (pin "P$225") (pinfunction "P$1_P$225") (pintype "power_in"))
      (node (ref "P3") (pin "P$226") (pinfunction "P$1_P$226") (pintype "power_in"))
      (node (ref "P3") (pin "P$227") (pinfunction "P$1_P$227") (pintype "power_in"))
      (node (ref "P3") (pin "P$228") (pinfunction "P$1_P$228") (pintype "power_in"))
      (node (ref "P3") (pin "P$229") (pinfunction "P$1_P$229") (pintype "power_in"))
      (node (ref "P3") (pin "P$23") (pinfunction "P$1_P$23") (pintype "power_in"))
      (node (ref "P3") (pin "P$230") (pinfunction "P$1_P$230") (pintype "power_in"))
      (node (ref "P3") (pin "P$231") (pinfunction "P$1_P$231") (pintype "power_in"))
      (node (ref "P3") (pin "P$232") (pinfunction "P$1_P$232") (pintype "power_in"))
      (node (ref "P3") (pin "P$233") (pinfunction "P$1_P$233") (pintype "power_in"))
      (node (ref "P3") (pin "P$234") (pinfunction "P$1_P$234") (pintype "power_in"))
      (node (ref "P3") (pin "P$235") (pinfunction "P$1_P$235") (pintype "power_in"))
      (node (ref "P3") (pin "P$236") (pinfunction "P$1_P$236") (pintype "power_in"))
      (node (ref "P3") (pin "P$237") (pinfunction "P$1_P$237") (pintype "power_in"))
      (node (ref "P3") (pin "P$238") (pinfunction "P$1_P$238") (pintype "power_in"))
      (node (ref "P3") (pin "P$239") (pinfunction "P$1_P$239") (pintype "power_in"))
      (node (ref "P3") (pin "P$24") (pinfunction "P$1_P$24") (pintype "power_in"))
      (node (ref "P3") (pin "P$240") (pinfunction "P$1_P$240") (pintype "power_in"))
      (node (ref "P3") (pin "P$241") (pinfunction "P$1_P$241") (pintype "power_in"))
      (node (ref "P3") (pin "P$242") (pinfunction "P$1_P$242") (pintype "power_in"))
      (node (ref "P3") (pin "P$243") (pinfunction "P$1_P$243") (pintype "power_in"))
      (node (ref "P3") (pin "P$244") (pinfunction "P$1_P$244") (pintype "power_in"))
      (node (ref "P3") (pin "P$245") (pinfunction "P$1_P$245") (pintype "power_in"))
      (node (ref "P3") (pin "P$246") (pinfunction "P$1_P$246") (pintype "power_in"))
      (node (ref "P3") (pin "P$247") (pinfunction "P$1_P$247") (pintype "power_in"))
      (node (ref "P3") (pin "P$248") (pinfunction "P$1_P$248") (pintype "power_in"))
      (node (ref "P3") (pin "P$249") (pinfunction "P$1_P$249") (pintype "power_in"))
      (node (ref "P3") (pin "P$25") (pinfunction "P$1_P$25") (pintype "power_in"))
      (node (ref "P3") (pin "P$250") (pinfunction "P$1_P$250") (pintype "power_in"))
      (node (ref "P3") (pin "P$251") (pinfunction "P$1_P$251") (pintype "power_in"))
      (node (ref "P3") (pin "P$252") (pinfunction "P$1_P$252") (pintype "power_in"))
      (node (ref "P3") (pin "P$253") (pinfunction "P$1_P$253") (pintype "power_in"))
      (node (ref "P3") (pin "P$254") (pinfunction "P$1_P$254") (pintype "power_in"))
      (node (ref "P3") (pin "P$255") (pinfunction "P$1_P$255") (pintype "power_in"))
      (node (ref "P3") (pin "P$256") (pinfunction "P$1_P$256") (pintype "power_in"))
      (node (ref "P3") (pin "P$257") (pinfunction "P$1_P$257") (pintype "power_in"))
      (node (ref "P3") (pin "P$258") (pinfunction "P$1_P$258") (pintype "power_in"))
      (node (ref "P3") (pin "P$259") (pinfunction "P$1_P$259") (pintype "power_in"))
      (node (ref "P3") (pin "P$26") (pinfunction "P$1_P$26") (pintype "power_in"))
      (node (ref "P3") (pin "P$260") (pinfunction "P$1_P$260") (pintype "power_in"))
      (node (ref "P3") (pin "P$261") (pinfunction "P$1_P$261") (pintype "power_in"))
      (node (ref "P3") (pin "P$262") (pinfunction "P$1_P$262") (pintype "power_in"))
      (node (ref "P3") (pin "P$263") (pinfunction "P$1_P$263") (pintype "power_in"))
      (node (ref "P3") (pin "P$264") (pinfunction "P$1_P$264") (pintype "power_in"))
      (node (ref "P3") (pin "P$265") (pinfunction "P$1_P$265") (pintype "power_in"))
      (node (ref "P3") (pin "P$266") (pinfunction "P$1_P$266") (pintype "power_in"))
      (node (ref "P3") (pin "P$267") (pinfunction "P$1_P$267") (pintype "power_in"))
      (node (ref "P3") (pin "P$268") (pinfunction "P$1_P$268") (pintype "power_in"))
      (node (ref "P3") (pin "P$269") (pinfunction "P$1_P$269") (pintype "power_in"))
      (node (ref "P3") (pin "P$27") (pinfunction "P$1_P$27") (pintype "power_in"))
      (node (ref "P3") (pin "P$270") (pinfunction "P$1_P$270") (pintype "power_in"))
      (node (ref "P3") (pin "P$271") (pinfunction "P$1_P$271") (pintype "power_in"))
      (node (ref "P3") (pin "P$272") (pinfunction "P$1_P$272") (pintype "power_in"))
      (node (ref "P3") (pin "P$273") (pinfunction "P$1_P$273") (pintype "power_in"))
      (node (ref "P3") (pin "P$274") (pinfunction "P$1_P$274") (pintype "power_in"))
      (node (ref "P3") (pin "P$275") (pinfunction "P$1_P$275") (pintype "power_in"))
      (node (ref "P3") (pin "P$276") (pinfunction "P$1_P$276") (pintype "power_in"))
      (node (ref "P3") (pin "P$277") (pinfunction "P$1_P$277") (pintype "power_in"))
      (node (ref "P3") (pin "P$278") (pinfunction "P$1_P$278") (pintype "power_in"))
      (node (ref "P3") (pin "P$279") (pinfunction "P$1_P$279") (pintype "power_in"))
      (node (ref "P3") (pin "P$28") (pinfunction "P$1_P$28") (pintype "power_in"))
      (node (ref "P3") (pin "P$280") (pinfunction "P$1_P$280") (pintype "power_in"))
      (node (ref "P3") (pin "P$281") (pinfunction "P$1_P$281") (pintype "power_in"))
      (node (ref "P3") (pin "P$282") (pinfunction "P$1_P$282") (pintype "power_in"))
      (node (ref "P3") (pin "P$283") (pinfunction "P$1_P$283") (pintype "power_in"))
      (node (ref "P3") (pin "P$284") (pinfunction "P$1_P$284") (pintype "power_in"))
      (node (ref "P3") (pin "P$285") (pinfunction "P$1_P$285") (pintype "power_in"))
      (node (ref "P3") (pin "P$286") (pinfunction "P$1_P$286") (pintype "power_in"))
      (node (ref "P3") (pin "P$287") (pinfunction "P$1_P$287") (pintype "power_in"))
      (node (ref "P3") (pin "P$288") (pinfunction "P$1_P$288") (pintype "power_in"))
      (node (ref "P3") (pin "P$29") (pinfunction "P$1_P$29") (pintype "power_in"))
      (node (ref "P3") (pin "P$3") (pinfunction "P$1_P$3") (pintype "power_in"))
      (node (ref "P3") (pin "P$30") (pinfunction "P$1_P$30") (pintype "power_in"))
      (node (ref "P3") (pin "P$31") (pinfunction "P$1_P$31") (pintype "power_in"))
      (node (ref "P3") (pin "P$32") (pinfunction "P$1_P$32") (pintype "power_in"))
      (node (ref "P3") (pin "P$33") (pinfunction "P$1_P$33") (pintype "power_in"))
      (node (ref "P3") (pin "P$34") (pinfunction "P$1_P$34") (pintype "power_in"))
      (node (ref "P3") (pin "P$35") (pinfunction "P$1_P$35") (pintype "power_in"))
      (node (ref "P3") (pin "P$36") (pinfunction "P$1_P$36") (pintype "power_in"))
      (node (ref "P3") (pin "P$37") (pinfunction "P$1_P$37") (pintype "power_in"))
      (node (ref "P3") (pin "P$38") (pinfunction "P$1_P$38") (pintype "power_in"))
      (node (ref "P3") (pin "P$39") (pinfunction "P$1_P$39") (pintype "power_in"))
      (node (ref "P3") (pin "P$4") (pinfunction "P$1_P$4") (pintype "power_in"))
      (node (ref "P3") (pin "P$40") (pinfunction "P$1_P$40") (pintype "power_in"))
      (node (ref "P3") (pin "P$41") (pinfunction "P$1_P$41") (pintype "power_in"))
      (node (ref "P3") (pin "P$42") (pinfunction "P$1_P$42") (pintype "power_in"))
      (node (ref "P3") (pin "P$43") (pinfunction "P$1_P$43") (pintype "power_in"))
      (node (ref "P3") (pin "P$44") (pinfunction "P$1_P$44") (pintype "power_in"))
      (node (ref "P3") (pin "P$45") (pinfunction "P$1_P$45") (pintype "power_in"))
      (node (ref "P3") (pin "P$46") (pinfunction "P$1_P$46") (pintype "power_in"))
      (node (ref "P3") (pin "P$47") (pinfunction "P$1_P$47") (pintype "power_in"))
      (node (ref "P3") (pin "P$48") (pinfunction "P$1_P$48") (pintype "power_in"))
      (node (ref "P3") (pin "P$49") (pinfunction "P$1_P$49") (pintype "power_in"))
      (node (ref "P3") (pin "P$5") (pinfunction "P$1_P$5") (pintype "power_in"))
      (node (ref "P3") (pin "P$50") (pinfunction "P$1_P$50") (pintype "power_in"))
      (node (ref "P3") (pin "P$51") (pinfunction "P$1_P$51") (pintype "power_in"))
      (node (ref "P3") (pin "P$52") (pinfunction "P$1_P$52") (pintype "power_in"))
      (node (ref "P3") (pin "P$53") (pinfunction "P$1_P$53") (pintype "power_in"))
      (node (ref "P3") (pin "P$54") (pinfunction "P$1_P$54") (pintype "power_in"))
      (node (ref "P3") (pin "P$55") (pinfunction "P$1_P$55") (pintype "power_in"))
      (node (ref "P3") (pin "P$56") (pinfunction "P$1_P$56") (pintype "power_in"))
      (node (ref "P3") (pin "P$57") (pinfunction "P$1_P$57") (pintype "power_in"))
      (node (ref "P3") (pin "P$58") (pinfunction "P$1_P$58") (pintype "power_in"))
      (node (ref "P3") (pin "P$59") (pinfunction "P$1_P$59") (pintype "power_in"))
      (node (ref "P3") (pin "P$6") (pinfunction "P$1_P$6") (pintype "power_in"))
      (node (ref "P3") (pin "P$60") (pinfunction "P$1_P$60") (pintype "power_in"))
      (node (ref "P3") (pin "P$61") (pinfunction "P$1_P$61") (pintype "power_in"))
      (node (ref "P3") (pin "P$62") (pinfunction "P$1_P$62") (pintype "power_in"))
      (node (ref "P3") (pin "P$63") (pinfunction "P$1_P$63") (pintype "power_in"))
      (node (ref "P3") (pin "P$64") (pinfunction "P$1_P$64") (pintype "power_in"))
      (node (ref "P3") (pin "P$65") (pinfunction "P$1_P$65") (pintype "power_in"))
      (node (ref "P3") (pin "P$66") (pinfunction "P$1_P$66") (pintype "power_in"))
      (node (ref "P3") (pin "P$67") (pinfunction "P$1_P$67") (pintype "power_in"))
      (node (ref "P3") (pin "P$68") (pinfunction "P$1_P$68") (pintype "power_in"))
      (node (ref "P3") (pin "P$69") (pinfunction "P$1_P$69") (pintype "power_in"))
      (node (ref "P3") (pin "P$7") (pinfunction "P$1_P$7") (pintype "power_in"))
      (node (ref "P3") (pin "P$70") (pinfunction "P$1_P$70") (pintype "power_in"))
      (node (ref "P3") (pin "P$71") (pinfunction "P$1_P$71") (pintype "power_in"))
      (node (ref "P3") (pin "P$72") (pinfunction "P$1_P$72") (pintype "power_in"))
      (node (ref "P3") (pin "P$73") (pinfunction "P$1_P$73") (pintype "power_in"))
      (node (ref "P3") (pin "P$74") (pinfunction "P$1_P$74") (pintype "power_in"))
      (node (ref "P3") (pin "P$75") (pinfunction "P$1_P$75") (pintype "power_in"))
      (node (ref "P3") (pin "P$76") (pinfunction "P$1_P$76") (pintype "power_in"))
      (node (ref "P3") (pin "P$77") (pinfunction "P$1_P$77") (pintype "power_in"))
      (node (ref "P3") (pin "P$78") (pinfunction "P$1_P$78") (pintype "power_in"))
      (node (ref "P3") (pin "P$79") (pinfunction "P$1_P$79") (pintype "power_in"))
      (node (ref "P3") (pin "P$8") (pinfunction "P$1_P$8") (pintype "power_in"))
      (node (ref "P3") (pin "P$80") (pinfunction "P$1_P$80") (pintype "power_in"))
      (node (ref "P3") (pin "P$81") (pinfunction "P$1_P$81") (pintype "power_in"))
      (node (ref "P3") (pin "P$82") (pinfunction "P$1_P$82") (pintype "power_in"))
      (node (ref "P3") (pin "P$83") (pinfunction "P$1_P$83") (pintype "power_in"))
      (node (ref "P3") (pin "P$84") (pinfunction "P$1_P$84") (pintype "power_in"))
      (node (ref "P3") (pin "P$85") (pinfunction "P$1_P$85") (pintype "power_in"))
      (node (ref "P3") (pin "P$86") (pinfunction "P$1_P$86") (pintype "power_in"))
      (node (ref "P3") (pin "P$87") (pinfunction "P$1_P$87") (pintype "power_in"))
      (node (ref "P3") (pin "P$88") (pinfunction "P$1_P$88") (pintype "power_in"))
      (node (ref "P3") (pin "P$89") (pinfunction "P$1_P$89") (pintype "power_in"))
      (node (ref "P3") (pin "P$9") (pinfunction "P$1_P$9") (pintype "power_in"))
      (node (ref "P3") (pin "P$90") (pinfunction "P$1_P$90") (pintype "power_in"))
      (node (ref "P3") (pin "P$91") (pinfunction "P$1_P$91") (pintype "power_in"))
      (node (ref "P3") (pin "P$92") (pinfunction "P$1_P$92") (pintype "power_in"))
      (node (ref "P3") (pin "P$93") (pinfunction "P$1_P$93") (pintype "power_in"))
      (node (ref "P3") (pin "P$94") (pinfunction "P$1_P$94") (pintype "power_in"))
      (node (ref "P3") (pin "P$95") (pinfunction "P$1_P$95") (pintype "power_in"))
      (node (ref "P3") (pin "P$96") (pinfunction "P$1_P$96") (pintype "power_in"))
      (node (ref "P3") (pin "P$97") (pinfunction "P$1_P$97") (pintype "power_in"))
      (node (ref "P3") (pin "P$98") (pinfunction "P$1_P$98") (pintype "power_in"))
      (node (ref "P3") (pin "P$99") (pinfunction "P$1_P$99") (pintype "power_in"))
    )
    (net (code "5") (name "/P4") (class "Default")
      (node (ref "JP1") (pin "P$5") (pinfunction "4_P$5") (pintype "bidirectional"))
      (node (ref "P4") (pin "P$1") (pinfunction "P$1_P$1") (pintype "power_in"))
      (node (ref "P4") (pin "P$10") (pinfunction "P$1_P$10") (pintype "power_in"))
      (node (ref "P4") (pin "P$100") (pinfunction "P$1_P$100") (pintype "power_in"))
      (node (ref "P4") (pin "P$101") (pinfunction "P$1_P$101") (pintype "power_in"))
      (node (ref "P4") (pin "P$102") (pinfunction "P$1_P$102") (pintype "power_in"))
      (node (ref "P4") (pin "P$103") (pinfunction "P$1_P$103") (pintype "power_in"))
      (node (ref "P4") (pin "P$104") (pinfunction "P$1_P$104") (pintype "power_in"))
      (node (ref "P4") (pin "P$105") (pinfunction "P$1_P$105") (pintype "power_in"))
      (node (ref "P4") (pin "P$106") (pinfunction "P$1_P$106") (pintype "power_in"))
      (node (ref "P4") (pin "P$107") (pinfunction "P$1_P$107") (pintype "power_in"))
      (node (ref "P4") (pin "P$108") (pinfunction "P$1_P$108") (pintype "power_in"))
      (node (ref "P4") (pin "P$109") (pinfunction "P$1_P$109") (pintype "power_in"))
      (node (ref "P4") (pin "P$11") (pinfunction "P$1_P$11") (pintype "power_in"))
      (node (ref "P4") (pin "P$110") (pinfunction "P$1_P$110") (pintype "power_in"))
      (node (ref "P4") (pin "P$111") (pinfunction "P$1_P$111") (pintype "power_in"))
      (node (ref "P4") (pin "P$112") (pinfunction "P$1_P$112") (pintype "power_in"))
      (node (ref "P4") (pin "P$113") (pinfunction "P$1_P$113") (pintype "power_in"))
      (node (ref "P4") (pin "P$114") (pinfunction "P$1_P$114") (pintype "power_in"))
      (node (ref "P4") (pin "P$115") (pinfunction "P$1_P$115") (pintype "power_in"))
      (node (ref "P4") (pin "P$116") (pinfunction "P$1_P$116") (pintype "power_in"))
      (node (ref "P4") (pin "P$117") (pinfunction "P$1_P$117") (pintype "power_in"))
      (node (ref "P4") (pin "P$118") (pinfunction "P$1_P$118") (pintype "power_in"))
      (node (ref "P4") (pin "P$119") (pinfunction "P$1_P$119") (pintype "power_in"))
      (node (ref "P4") (pin "P$12") (pinfunction "P$1_P$12") (pintype "power_in"))
      (node (ref "P4") (pin "P$120") (pinfunction "P$1_P$120") (pintype "power_in"))
      (node (ref "P4") (pin "P$121") (pinfunction "P$1_P$121") (pintype "power_in"))
      (node (ref "P4") (pin "P$122") (pinfunction "P$1_P$122") (pintype "power_in"))
      (node (ref "P4") (pin "P$123") (pinfunction "P$1_P$123") (pintype "power_in"))
      (node (ref "P4") (pin "P$124") (pinfunction "P$1_P$124") (pintype "power_in"))
      (node (ref "P4") (pin "P$125") (pinfunction "P$1_P$125") (pintype "power_in"))
      (node (ref "P4") (pin "P$126") (pinfunction "P$1_P$126") (pintype "power_in"))
      (node (ref "P4") (pin "P$127") (pinfunction "P$1_P$127") (pintype "power_in"))
      (node (ref "P4") (pin "P$128") (pinfunction "P$1_P$128") (pintype "power_in"))
      (node (ref "P4") (pin "P$129") (pinfunction "P$1_P$129") (pintype "power_in"))
      (node (ref "P4") (pin "P$13") (pinfunction "P$1_P$13") (pintype "power_in"))
      (node (ref "P4") (pin "P$130") (pinfunction "P$1_P$130") (pintype "power_in"))
      (node (ref "P4") (pin "P$131") (pinfunction "P$1_P$131") (pintype "power_in"))
      (node (ref "P4") (pin "P$132") (pinfunction "P$1_P$132") (pintype "power_in"))
      (node (ref "P4") (pin "P$133") (pinfunction "P$1_P$133") (pintype "power_in"))
      (node (ref "P4") (pin "P$134") (pinfunction "P$1_P$134") (pintype "power_in"))
      (node (ref "P4") (pin "P$135") (pinfunction "P$1_P$135") (pintype "power_in"))
      (node (ref "P4") (pin "P$136") (pinfunction "P$1_P$136") (pintype "power_in"))
      (node (ref "P4") (pin "P$137") (pinfunction "P$1_P$137") (pintype "power_in"))
      (node (ref "P4") (pin "P$138") (pinfunction "P$1_P$138") (pintype "power_in"))
      (node (ref "P4") (pin "P$139") (pinfunction "P$1_P$139") (pintype "power_in"))
      (node (ref "P4") (pin "P$14") (pinfunction "P$1_P$14") (pintype "power_in"))
      (node (ref "P4") (pin "P$140") (pinfunction "P$1_P$140") (pintype "power_in"))
      (node (ref "P4") (pin "P$141") (pinfunction "P$1_P$141") (pintype "power_in"))
      (node (ref "P4") (pin "P$142") (pinfunction "P$1_P$142") (pintype "power_in"))
      (node (ref "P4") (pin "P$143") (pinfunction "P$1_P$143") (pintype "power_in"))
      (node (ref "P4") (pin "P$144") (pinfunction "P$1_P$144") (pintype "power_in"))
      (node (ref "P4") (pin "P$145") (pinfunction "P$1_P$145") (pintype "power_in"))
      (node (ref "P4") (pin "P$146") (pinfunction "P$1_P$146") (pintype "power_in"))
      (node (ref "P4") (pin "P$147") (pinfunction "P$1_P$147") (pintype "power_in"))
      (node (ref "P4") (pin "P$148") (pinfunction "P$1_P$148") (pintype "power_in"))
      (node (ref "P4") (pin "P$149") (pinfunction "P$1_P$149") (pintype "power_in"))
      (node (ref "P4") (pin "P$15") (pinfunction "P$1_P$15") (pintype "power_in"))
      (node (ref "P4") (pin "P$150") (pinfunction "P$1_P$150") (pintype "power_in"))
      (node (ref "P4") (pin "P$151") (pinfunction "P$1_P$151") (pintype "power_in"))
      (node (ref "P4") (pin "P$152") (pinfunction "P$1_P$152") (pintype "power_in"))
      (node (ref "P4") (pin "P$153") (pinfunction "P$1_P$153") (pintype "power_in"))
      (node (ref "P4") (pin "P$154") (pinfunction "P$1_P$154") (pintype "power_in"))
      (node (ref "P4") (pin "P$155") (pinfunction "P$1_P$155") (pintype "power_in"))
      (node (ref "P4") (pin "P$156") (pinfunction "P$1_P$156") (pintype "power_in"))
      (node (ref "P4") (pin "P$157") (pinfunction "P$1_P$157") (pintype "power_in"))
      (node (ref "P4") (pin "P$158") (pinfunction "P$1_P$158") (pintype "power_in"))
      (node (ref "P4") (pin "P$159") (pinfunction "P$1_P$159") (pintype "power_in"))
      (node (ref "P4") (pin "P$16") (pinfunction "P$1_P$16") (pintype "power_in"))
      (node (ref "P4") (pin "P$160") (pinfunction "P$1_P$160") (pintype "power_in"))
      (node (ref "P4") (pin "P$161") (pinfunction "P$1_P$161") (pintype "power_in"))
      (node (ref "P4") (pin "P$162") (pinfunction "P$1_P$162") (pintype "power_in"))
      (node (ref "P4") (pin "P$163") (pinfunction "P$1_P$163") (pintype "power_in"))
      (node (ref "P4") (pin "P$164") (pinfunction "P$1_P$164") (pintype "power_in"))
      (node (ref "P4") (pin "P$165") (pinfunction "P$1_P$165") (pintype "power_in"))
      (node (ref "P4") (pin "P$166") (pinfunction "P$1_P$166") (pintype "power_in"))
      (node (ref "P4") (pin "P$167") (pinfunction "P$1_P$167") (pintype "power_in"))
      (node (ref "P4") (pin "P$168") (pinfunction "P$1_P$168") (pintype "power_in"))
      (node (ref "P4") (pin "P$169") (pinfunction "P$1_P$169") (pintype "power_in"))
      (node (ref "P4") (pin "P$17") (pinfunction "P$1_P$17") (pintype "power_in"))
      (node (ref "P4") (pin "P$170") (pinfunction "P$1_P$170") (pintype "power_in"))
      (node (ref "P4") (pin "P$171") (pinfunction "P$1_P$171") (pintype "power_in"))
      (node (ref "P4") (pin "P$172") (pinfunction "P$1_P$172") (pintype "power_in"))
      (node (ref "P4") (pin "P$173") (pinfunction "P$1_P$173") (pintype "power_in"))
      (node (ref "P4") (pin "P$174") (pinfunction "P$1_P$174") (pintype "power_in"))
      (node (ref "P4") (pin "P$175") (pinfunction "P$1_P$175") (pintype "power_in"))
      (node (ref "P4") (pin "P$176") (pinfunction "P$1_P$176") (pintype "power_in"))
      (node (ref "P4") (pin "P$177") (pinfunction "P$1_P$177") (pintype "power_in"))
      (node (ref "P4") (pin "P$178") (pinfunction "P$1_P$178") (pintype "power_in"))
      (node (ref "P4") (pin "P$179") (pinfunction "P$1_P$179") (pintype "power_in"))
      (node (ref "P4") (pin "P$18") (pinfunction "P$1_P$18") (pintype "power_in"))
      (node (ref "P4") (pin "P$180") (pinfunction "P$1_P$180") (pintype "power_in"))
      (node (ref "P4") (pin "P$181") (pinfunction "P$1_P$181") (pintype "power_in"))
      (node (ref "P4") (pin "P$182") (pinfunction "P$1_P$182") (pintype "power_in"))
      (node (ref "P4") (pin "P$183") (pinfunction "P$1_P$183") (pintype "power_in"))
      (node (ref "P4") (pin "P$184") (pinfunction "P$1_P$184") (pintype "power_in"))
      (node (ref "P4") (pin "P$185") (pinfunction "P$1_P$185") (pintype "power_in"))
      (node (ref "P4") (pin "P$186") (pinfunction "P$1_P$186") (pintype "power_in"))
      (node (ref "P4") (pin "P$187") (pinfunction "P$1_P$187") (pintype "power_in"))
      (node (ref "P4") (pin "P$188") (pinfunction "P$1_P$188") (pintype "power_in"))
      (node (ref "P4") (pin "P$189") (pinfunction "P$1_P$189") (pintype "power_in"))
      (node (ref "P4") (pin "P$19") (pinfunction "P$1_P$19") (pintype "power_in"))
      (node (ref "P4") (pin "P$190") (pinfunction "P$1_P$190") (pintype "power_in"))
      (node (ref "P4") (pin "P$191") (pinfunction "P$1_P$191") (pintype "power_in"))
      (node (ref "P4") (pin "P$192") (pinfunction "P$1_P$192") (pintype "power_in"))
      (node (ref "P4") (pin "P$193") (pinfunction "P$1_P$193") (pintype "power_in"))
      (node (ref "P4") (pin "P$194") (pinfunction "P$1_P$194") (pintype "power_in"))
      (node (ref "P4") (pin "P$195") (pinfunction "P$1_P$195") (pintype "power_in"))
      (node (ref "P4") (pin "P$196") (pinfunction "P$1_P$196") (pintype "power_in"))
      (node (ref "P4") (pin "P$197") (pinfunction "P$1_P$197") (pintype "power_in"))
      (node (ref "P4") (pin "P$198") (pinfunction "P$1_P$198") (pintype "power_in"))
      (node (ref "P4") (pin "P$199") (pinfunction "P$1_P$199") (pintype "power_in"))
      (node (ref "P4") (pin "P$2") (pinfunction "P$1_P$2") (pintype "power_in"))
      (node (ref "P4") (pin "P$20") (pinfunction "P$1_P$20") (pintype "power_in"))
      (node (ref "P4") (pin "P$200") (pinfunction "P$1_P$200") (pintype "power_in"))
      (node (ref "P4") (pin "P$201") (pinfunction "P$1_P$201") (pintype "power_in"))
      (node (ref "P4") (pin "P$202") (pinfunction "P$1_P$202") (pintype "power_in"))
      (node (ref "P4") (pin "P$203") (pinfunction "P$1_P$203") (pintype "power_in"))
      (node (ref "P4") (pin "P$204") (pinfunction "P$1_P$204") (pintype "power_in"))
      (node (ref "P4") (pin "P$205") (pinfunction "P$1_P$205") (pintype "power_in"))
      (node (ref "P4") (pin "P$206") (pinfunction "P$1_P$206") (pintype "power_in"))
      (node (ref "P4") (pin "P$207") (pinfunction "P$1_P$207") (pintype "power_in"))
      (node (ref "P4") (pin "P$208") (pinfunction "P$1_P$208") (pintype "power_in"))
      (node (ref "P4") (pin "P$209") (pinfunction "P$1_P$209") (pintype "power_in"))
      (node (ref "P4") (pin "P$21") (pinfunction "P$1_P$21") (pintype "power_in"))
      (node (ref "P4") (pin "P$210") (pinfunction "P$1_P$210") (pintype "power_in"))
      (node (ref "P4") (pin "P$211") (pinfunction "P$1_P$211") (pintype "power_in"))
      (node (ref "P4") (pin "P$212") (pinfunction "P$1_P$212") (pintype "power_in"))
      (node (ref "P4") (pin "P$213") (pinfunction "P$1_P$213") (pintype "power_in"))
      (node (ref "P4") (pin "P$214") (pinfunction "P$1_P$214") (pintype "power_in"))
      (node (ref "P4") (pin "P$215") (pinfunction "P$1_P$215") (pintype "power_in"))
      (node (ref "P4") (pin "P$216") (pinfunction "P$1_P$216") (pintype "power_in"))
      (node (ref "P4") (pin "P$217") (pinfunction "P$1_P$217") (pintype "power_in"))
      (node (ref "P4") (pin "P$218") (pinfunction "P$1_P$218") (pintype "power_in"))
      (node (ref "P4") (pin "P$219") (pinfunction "P$1_P$219") (pintype "power_in"))
      (node (ref "P4") (pin "P$22") (pinfunction "P$1_P$22") (pintype "power_in"))
      (node (ref "P4") (pin "P$220") (pinfunction "P$1_P$220") (pintype "power_in"))
      (node (ref "P4") (pin "P$221") (pinfunction "P$1_P$221") (pintype "power_in"))
      (node (ref "P4") (pin "P$222") (pinfunction "P$1_P$222") (pintype "power_in"))
      (node (ref "P4") (pin "P$223") (pinfunction "P$1_P$223") (pintype "power_in"))
      (node (ref "P4") (pin "P$224") (pinfunction "P$1_P$224") (pintype "power_in"))
      (node (ref "P4") (pin "P$225") (pinfunction "P$1_P$225") (pintype "power_in"))
      (node (ref "P4") (pin "P$226") (pinfunction "P$1_P$226") (pintype "power_in"))
      (node (ref "P4") (pin "P$227") (pinfunction "P$1_P$227") (pintype "power_in"))
      (node (ref "P4") (pin "P$228") (pinfunction "P$1_P$228") (pintype "power_in"))
      (node (ref "P4") (pin "P$229") (pinfunction "P$1_P$229") (pintype "power_in"))
      (node (ref "P4") (pin "P$23") (pinfunction "P$1_P$23") (pintype "power_in"))
      (node (ref "P4") (pin "P$230") (pinfunction "P$1_P$230") (pintype "power_in"))
      (node (ref "P4") (pin "P$231") (pinfunction "P$1_P$231") (pintype "power_in"))
      (node (ref "P4") (pin "P$232") (pinfunction "P$1_P$232") (pintype "power_in"))
      (node (ref "P4") (pin "P$233") (pinfunction "P$1_P$233") (pintype "power_in"))
      (node (ref "P4") (pin "P$234") (pinfunction "P$1_P$234") (pintype "power_in"))
      (node (ref "P4") (pin "P$235") (pinfunction "P$1_P$235") (pintype "power_in"))
      (node (ref "P4") (pin "P$236") (pinfunction "P$1_P$236") (pintype "power_in"))
      (node (ref "P4") (pin "P$237") (pinfunction "P$1_P$237") (pintype "power_in"))
      (node (ref "P4") (pin "P$238") (pinfunction "P$1_P$238") (pintype "power_in"))
      (node (ref "P4") (pin "P$239") (pinfunction "P$1_P$239") (pintype "power_in"))
      (node (ref "P4") (pin "P$24") (pinfunction "P$1_P$24") (pintype "power_in"))
      (node (ref "P4") (pin "P$240") (pinfunction "P$1_P$240") (pintype "power_in"))
      (node (ref "P4") (pin "P$241") (pinfunction "P$1_P$241") (pintype "power_in"))
      (node (ref "P4") (pin "P$242") (pinfunction "P$1_P$242") (pintype "power_in"))
      (node (ref "P4") (pin "P$243") (pinfunction "P$1_P$243") (pintype "power_in"))
      (node (ref "P4") (pin "P$244") (pinfunction "P$1_P$244") (pintype "power_in"))
      (node (ref "P4") (pin "P$245") (pinfunction "P$1_P$245") (pintype "power_in"))
      (node (ref "P4") (pin "P$246") (pinfunction "P$1_P$246") (pintype "power_in"))
      (node (ref "P4") (pin "P$247") (pinfunction "P$1_P$247") (pintype "power_in"))
      (node (ref "P4") (pin "P$248") (pinfunction "P$1_P$248") (pintype "power_in"))
      (node (ref "P4") (pin "P$249") (pinfunction "P$1_P$249") (pintype "power_in"))
      (node (ref "P4") (pin "P$25") (pinfunction "P$1_P$25") (pintype "power_in"))
      (node (ref "P4") (pin "P$250") (pinfunction "P$1_P$250") (pintype "power_in"))
      (node (ref "P4") (pin "P$251") (pinfunction "P$1_P$251") (pintype "power_in"))
      (node (ref "P4") (pin "P$252") (pinfunction "P$1_P$252") (pintype "power_in"))
      (node (ref "P4") (pin "P$253") (pinfunction "P$1_P$253") (pintype "power_in"))
      (node (ref "P4") (pin "P$254") (pinfunction "P$1_P$254") (pintype "power_in"))
      (node (ref "P4") (pin "P$255") (pinfunction "P$1_P$255") (pintype "power_in"))
      (node (ref "P4") (pin "P$256") (pinfunction "P$1_P$256") (pintype "power_in"))
      (node (ref "P4") (pin "P$257") (pinfunction "P$1_P$257") (pintype "power_in"))
      (node (ref "P4") (pin "P$258") (pinfunction "P$1_P$258") (pintype "power_in"))
      (node (ref "P4") (pin "P$259") (pinfunction "P$1_P$259") (pintype "power_in"))
      (node (ref "P4") (pin "P$26") (pinfunction "P$1_P$26") (pintype "power_in"))
      (node (ref "P4") (pin "P$260") (pinfunction "P$1_P$260") (pintype "power_in"))
      (node (ref "P4") (pin "P$261") (pinfunction "P$1_P$261") (pintype "power_in"))
      (node (ref "P4") (pin "P$262") (pinfunction "P$1_P$262") (pintype "power_in"))
      (node (ref "P4") (pin "P$263") (pinfunction "P$1_P$263") (pintype "power_in"))
      (node (ref "P4") (pin "P$264") (pinfunction "P$1_P$264") (pintype "power_in"))
      (node (ref "P4") (pin "P$265") (pinfunction "P$1_P$265") (pintype "power_in"))
      (node (ref "P4") (pin "P$266") (pinfunction "P$1_P$266") (pintype "power_in"))
      (node (ref "P4") (pin "P$267") (pinfunction "P$1_P$267") (pintype "power_in"))
      (node (ref "P4") (pin "P$268") (pinfunction "P$1_P$268") (pintype "power_in"))
      (node (ref "P4") (pin "P$269") (pinfunction "P$1_P$269") (pintype "power_in"))
      (node (ref "P4") (pin "P$27") (pinfunction "P$1_P$27") (pintype "power_in"))
      (node (ref "P4") (pin "P$270") (pinfunction "P$1_P$270") (pintype "power_in"))
      (node (ref "P4") (pin "P$271") (pinfunction "P$1_P$271") (pintype "power_in"))
      (node (ref "P4") (pin "P$272") (pinfunction "P$1_P$272") (pintype "power_in"))
      (node (ref "P4") (pin "P$273") (pinfunction "P$1_P$273") (pintype "power_in"))
      (node (ref "P4") (pin "P$274") (pinfunction "P$1_P$274") (pintype "power_in"))
      (node (ref "P4") (pin "P$275") (pinfunction "P$1_P$275") (pintype "power_in"))
      (node (ref "P4") (pin "P$276") (pinfunction "P$1_P$276") (pintype "power_in"))
      (node (ref "P4") (pin "P$277") (pinfunction "P$1_P$277") (pintype "power_in"))
      (node (ref "P4") (pin "P$278") (pinfunction "P$1_P$278") (pintype "power_in"))
      (node (ref "P4") (pin "P$279") (pinfunction "P$1_P$279") (pintype "power_in"))
      (node (ref "P4") (pin "P$28") (pinfunction "P$1_P$28") (pintype "power_in"))
      (node (ref "P4") (pin "P$280") (pinfunction "P$1_P$280") (pintype "power_in"))
      (node (ref "P4") (pin "P$281") (pinfunction "P$1_P$281") (pintype "power_in"))
      (node (ref "P4") (pin "P$282") (pinfunction "P$1_P$282") (pintype "power_in"))
      (node (ref "P4") (pin "P$283") (pinfunction "P$1_P$283") (pintype "power_in"))
      (node (ref "P4") (pin "P$284") (pinfunction "P$1_P$284") (pintype "power_in"))
      (node (ref "P4") (pin "P$285") (pinfunction "P$1_P$285") (pintype "power_in"))
      (node (ref "P4") (pin "P$286") (pinfunction "P$1_P$286") (pintype "power_in"))
      (node (ref "P4") (pin "P$287") (pinfunction "P$1_P$287") (pintype "power_in"))
      (node (ref "P4") (pin "P$288") (pinfunction "P$1_P$288") (pintype "power_in"))
      (node (ref "P4") (pin "P$29") (pinfunction "P$1_P$29") (pintype "power_in"))
      (node (ref "P4") (pin "P$3") (pinfunction "P$1_P$3") (pintype "power_in"))
      (node (ref "P4") (pin "P$30") (pinfunction "P$1_P$30") (pintype "power_in"))
      (node (ref "P4") (pin "P$31") (pinfunction "P$1_P$31") (pintype "power_in"))
      (node (ref "P4") (pin "P$32") (pinfunction "P$1_P$32") (pintype "power_in"))
      (node (ref "P4") (pin "P$33") (pinfunction "P$1_P$33") (pintype "power_in"))
      (node (ref "P4") (pin "P$34") (pinfunction "P$1_P$34") (pintype "power_in"))
      (node (ref "P4") (pin "P$35") (pinfunction "P$1_P$35") (pintype "power_in"))
      (node (ref "P4") (pin "P$36") (pinfunction "P$1_P$36") (pintype "power_in"))
      (node (ref "P4") (pin "P$37") (pinfunction "P$1_P$37") (pintype "power_in"))
      (node (ref "P4") (pin "P$38") (pinfunction "P$1_P$38") (pintype "power_in"))
      (node (ref "P4") (pin "P$39") (pinfunction "P$1_P$39") (pintype "power_in"))
      (node (ref "P4") (pin "P$4") (pinfunction "P$1_P$4") (pintype "power_in"))
      (node (ref "P4") (pin "P$40") (pinfunction "P$1_P$40") (pintype "power_in"))
      (node (ref "P4") (pin "P$41") (pinfunction "P$1_P$41") (pintype "power_in"))
      (node (ref "P4") (pin "P$42") (pinfunction "P$1_P$42") (pintype "power_in"))
      (node (ref "P4") (pin "P$43") (pinfunction "P$1_P$43") (pintype "power_in"))
      (node (ref "P4") (pin "P$44") (pinfunction "P$1_P$44") (pintype "power_in"))
      (node (ref "P4") (pin "P$45") (pinfunction "P$1_P$45") (pintype "power_in"))
      (node (ref "P4") (pin "P$46") (pinfunction "P$1_P$46") (pintype "power_in"))
      (node (ref "P4") (pin "P$47") (pinfunction "P$1_P$47") (pintype "power_in"))
      (node (ref "P4") (pin "P$48") (pinfunction "P$1_P$48") (pintype "power_in"))
      (node (ref "P4") (pin "P$49") (pinfunction "P$1_P$49") (pintype "power_in"))
      (node (ref "P4") (pin "P$5") (pinfunction "P$1_P$5") (pintype "power_in"))
      (node (ref "P4") (pin "P$50") (pinfunction "P$1_P$50") (pintype "power_in"))
      (node (ref "P4") (pin "P$51") (pinfunction "P$1_P$51") (pintype "power_in"))
      (node (ref "P4") (pin "P$52") (pinfunction "P$1_P$52") (pintype "power_in"))
      (node (ref "P4") (pin "P$53") (pinfunction "P$1_P$53") (pintype "power_in"))
      (node (ref "P4") (pin "P$54") (pinfunction "P$1_P$54") (pintype "power_in"))
      (node (ref "P4") (pin "P$55") (pinfunction "P$1_P$55") (pintype "power_in"))
      (node (ref "P4") (pin "P$56") (pinfunction "P$1_P$56") (pintype "power_in"))
      (node (ref "P4") (pin "P$57") (pinfunction "P$1_P$57") (pintype "power_in"))
      (node (ref "P4") (pin "P$58") (pinfunction "P$1_P$58") (pintype "power_in"))
      (node (ref "P4") (pin "P$59") (pinfunction "P$1_P$59") (pintype "power_in"))
      (node (ref "P4") (pin "P$6") (pinfunction "P$1_P$6") (pintype "power_in"))
      (node (ref "P4") (pin "P$60") (pinfunction "P$1_P$60") (pintype "power_in"))
      (node (ref "P4") (pin "P$61") (pinfunction "P$1_P$61") (pintype "power_in"))
      (node (ref "P4") (pin "P$62") (pinfunction "P$1_P$62") (pintype "power_in"))
      (node (ref "P4") (pin "P$63") (pinfunction "P$1_P$63") (pintype "power_in"))
      (node (ref "P4") (pin "P$64") (pinfunction "P$1_P$64") (pintype "power_in"))
      (node (ref "P4") (pin "P$65") (pinfunction "P$1_P$65") (pintype "power_in"))
      (node (ref "P4") (pin "P$66") (pinfunction "P$1_P$66") (pintype "power_in"))
      (node (ref "P4") (pin "P$67") (pinfunction "P$1_P$67") (pintype "power_in"))
      (node (ref "P4") (pin "P$68") (pinfunction "P$1_P$68") (pintype "power_in"))
      (node (ref "P4") (pin "P$69") (pinfunction "P$1_P$69") (pintype "power_in"))
      (node (ref "P4") (pin "P$7") (pinfunction "P$1_P$7") (pintype "power_in"))
      (node (ref "P4") (pin "P$70") (pinfunction "P$1_P$70") (pintype "power_in"))
      (node (ref "P4") (pin "P$71") (pinfunction "P$1_P$71") (pintype "power_in"))
      (node (ref "P4") (pin "P$72") (pinfunction "P$1_P$72") (pintype "power_in"))
      (node (ref "P4") (pin "P$73") (pinfunction "P$1_P$73") (pintype "power_in"))
      (node (ref "P4") (pin "P$74") (pinfunction "P$1_P$74") (pintype "power_in"))
      (node (ref "P4") (pin "P$75") (pinfunction "P$1_P$75") (pintype "power_in"))
      (node (ref "P4") (pin "P$76") (pinfunction "P$1_P$76") (pintype "power_in"))
      (node (ref "P4") (pin "P$77") (pinfunction "P$1_P$77") (pintype "power_in"))
      (node (ref "P4") (pin "P$78") (pinfunction "P$1_P$78") (pintype "power_in"))
      (node (ref "P4") (pin "P$79") (pinfunction "P$1_P$79") (pintype "power_in"))
      (node (ref "P4") (pin "P$8") (pinfunction "P$1_P$8") (pintype "power_in"))
      (node (ref "P4") (pin "P$80") (pinfunction "P$1_P$80") (pintype "power_in"))
      (node (ref "P4") (pin "P$81") (pinfunction "P$1_P$81") (pintype "power_in"))
      (node (ref "P4") (pin "P$82") (pinfunction "P$1_P$82") (pintype "power_in"))
      (node (ref "P4") (pin "P$83") (pinfunction "P$1_P$83") (pintype "power_in"))
      (node (ref "P4") (pin "P$84") (pinfunction "P$1_P$84") (pintype "power_in"))
      (node (ref "P4") (pin "P$85") (pinfunction "P$1_P$85") (pintype "power_in"))
      (node (ref "P4") (pin "P$86") (pinfunction "P$1_P$86") (pintype "power_in"))
      (node (ref "P4") (pin "P$87") (pinfunction "P$1_P$87") (pintype "power_in"))
      (node (ref "P4") (pin "P$88") (pinfunction "P$1_P$88") (pintype "power_in"))
      (node (ref "P4") (pin "P$89") (pinfunction "P$1_P$89") (pintype "power_in"))
      (node (ref "P4") (pin "P$9") (pinfunction "P$1_P$9") (pintype "power_in"))
      (node (ref "P4") (pin "P$90") (pinfunction "P$1_P$90") (pintype "power_in"))
      (node (ref "P4") (pin "P$91") (pinfunction "P$1_P$91") (pintype "power_in"))
      (node (ref "P4") (pin "P$92") (pinfunction "P$1_P$92") (pintype "power_in"))
      (node (ref "P4") (pin "P$93") (pinfunction "P$1_P$93") (pintype "power_in"))
      (node (ref "P4") (pin "P$94") (pinfunction "P$1_P$94") (pintype "power_in"))
      (node (ref "P4") (pin "P$95") (pinfunction "P$1_P$95") (pintype "power_in"))
      (node (ref "P4") (pin "P$96") (pinfunction "P$1_P$96") (pintype "power_in"))
      (node (ref "P4") (pin "P$97") (pinfunction "P$1_P$97") (pintype "power_in"))
      (node (ref "P4") (pin "P$98") (pinfunction "P$1_P$98") (pintype "power_in"))
      (node (ref "P4") (pin "P$99") (pinfunction "P$1_P$99") (pintype "power_in"))
    )
    (net (code "6") (name "/P5") (class "Default")
      (node (ref "JP1") (pin "P$6") (pinfunction "5_P$6") (pintype "bidirectional"))
      (node (ref "P5") (pin "P$1") (pinfunction "P$1_P$1") (pintype "power_in"))
      (node (ref "P5") (pin "P$10") (pinfunction "P$1_P$10") (pintype "power_in"))
      (node (ref "P5") (pin "P$100") (pinfunction "P$1_P$100") (pintype "power_in"))
      (node (ref "P5") (pin "P$101") (pinfunction "P$1_P$101") (pintype "power_in"))
      (node (ref "P5") (pin "P$102") (pinfunction "P$1_P$102") (pintype "power_in"))
      (node (ref "P5") (pin "P$103") (pinfunction "P$1_P$103") (pintype "power_in"))
      (node (ref "P5") (pin "P$104") (pinfunction "P$1_P$104") (pintype "power_in"))
      (node (ref "P5") (pin "P$105") (pinfunction "P$1_P$105") (pintype "power_in"))
      (node (ref "P5") (pin "P$106") (pinfunction "P$1_P$106") (pintype "power_in"))
      (node (ref "P5") (pin "P$107") (pinfunction "P$1_P$107") (pintype "power_in"))
      (node (ref "P5") (pin "P$108") (pinfunction "P$1_P$108") (pintype "power_in"))
      (node (ref "P5") (pin "P$109") (pinfunction "P$1_P$109") (pintype "power_in"))
      (node (ref "P5") (pin "P$11") (pinfunction "P$1_P$11") (pintype "power_in"))
      (node (ref "P5") (pin "P$110") (pinfunction "P$1_P$110") (pintype "power_in"))
      (node (ref "P5") (pin "P$111") (pinfunction "P$1_P$111") (pintype "power_in"))
      (node (ref "P5") (pin "P$112") (pinfunction "P$1_P$112") (pintype "power_in"))
      (node (ref "P5") (pin "P$113") (pinfunction "P$1_P$113") (pintype "power_in"))
      (node (ref "P5") (pin "P$114") (pinfunction "P$1_P$114") (pintype "power_in"))
      (node (ref "P5") (pin "P$115") (pinfunction "P$1_P$115") (pintype "power_in"))
      (node (ref "P5") (pin "P$116") (pinfunction "P$1_P$116") (pintype "power_in"))
      (node (ref "P5") (pin "P$117") (pinfunction "P$1_P$117") (pintype "power_in"))
      (node (ref "P5") (pin "P$118") (pinfunction "P$1_P$118") (pintype "power_in"))
      (node (ref "P5") (pin "P$119") (pinfunction "P$1_P$119") (pintype "power_in"))
      (node (ref "P5") (pin "P$12") (pinfunction "P$1_P$12") (pintype "power_in"))
      (node (ref "P5") (pin "P$120") (pinfunction "P$1_P$120") (pintype "power_in"))
      (node (ref "P5") (pin "P$121") (pinfunction "P$1_P$121") (pintype "power_in"))
      (node (ref "P5") (pin "P$122") (pinfunction "P$1_P$122") (pintype "power_in"))
      (node (ref "P5") (pin "P$123") (pinfunction "P$1_P$123") (pintype "power_in"))
      (node (ref "P5") (pin "P$124") (pinfunction "P$1_P$124") (pintype "power_in"))
      (node (ref "P5") (pin "P$125") (pinfunction "P$1_P$125") (pintype "power_in"))
      (node (ref "P5") (pin "P$126") (pinfunction "P$1_P$126") (pintype "power_in"))
      (node (ref "P5") (pin "P$127") (pinfunction "P$1_P$127") (pintype "power_in"))
      (node (ref "P5") (pin "P$128") (pinfunction "P$1_P$128") (pintype "power_in"))
      (node (ref "P5") (pin "P$129") (pinfunction "P$1_P$129") (pintype "power_in"))
      (node (ref "P5") (pin "P$13") (pinfunction "P$1_P$13") (pintype "power_in"))
      (node (ref "P5") (pin "P$130") (pinfunction "P$1_P$130") (pintype "power_in"))
      (node (ref "P5") (pin "P$131") (pinfunction "P$1_P$131") (pintype "power_in"))
      (node (ref "P5") (pin "P$132") (pinfunction "P$1_P$132") (pintype "power_in"))
      (node (ref "P5") (pin "P$133") (pinfunction "P$1_P$133") (pintype "power_in"))
      (node (ref "P5") (pin "P$134") (pinfunction "P$1_P$134") (pintype "power_in"))
      (node (ref "P5") (pin "P$135") (pinfunction "P$1_P$135") (pintype "power_in"))
      (node (ref "P5") (pin "P$136") (pinfunction "P$1_P$136") (pintype "power_in"))
      (node (ref "P5") (pin "P$137") (pinfunction "P$1_P$137") (pintype "power_in"))
      (node (ref "P5") (pin "P$138") (pinfunction "P$1_P$138") (pintype "power_in"))
      (node (ref "P5") (pin "P$139") (pinfunction "P$1_P$139") (pintype "power_in"))
      (node (ref "P5") (pin "P$14") (pinfunction "P$1_P$14") (pintype "power_in"))
      (node (ref "P5") (pin "P$140") (pinfunction "P$1_P$140") (pintype "power_in"))
      (node (ref "P5") (pin "P$141") (pinfunction "P$1_P$141") (pintype "power_in"))
      (node (ref "P5") (pin "P$142") (pinfunction "P$1_P$142") (pintype "power_in"))
      (node (ref "P5") (pin "P$143") (pinfunction "P$1_P$143") (pintype "power_in"))
      (node (ref "P5") (pin "P$144") (pinfunction "P$1_P$144") (pintype "power_in"))
      (node (ref "P5") (pin "P$145") (pinfunction "P$1_P$145") (pintype "power_in"))
      (node (ref "P5") (pin "P$146") (pinfunction "P$1_P$146") (pintype "power_in"))
      (node (ref "P5") (pin "P$147") (pinfunction "P$1_P$147") (pintype "power_in"))
      (node (ref "P5") (pin "P$148") (pinfunction "P$1_P$148") (pintype "power_in"))
      (node (ref "P5") (pin "P$149") (pinfunction "P$1_P$149") (pintype "power_in"))
      (node (ref "P5") (pin "P$15") (pinfunction "P$1_P$15") (pintype "power_in"))
      (node (ref "P5") (pin "P$150") (pinfunction "P$1_P$150") (pintype "power_in"))
      (node (ref "P5") (pin "P$151") (pinfunction "P$1_P$151") (pintype "power_in"))
      (node (ref "P5") (pin "P$152") (pinfunction "P$1_P$152") (pintype "power_in"))
      (node (ref "P5") (pin "P$153") (pinfunction "P$1_P$153") (pintype "power_in"))
      (node (ref "P5") (pin "P$154") (pinfunction "P$1_P$154") (pintype "power_in"))
      (node (ref "P5") (pin "P$155") (pinfunction "P$1_P$155") (pintype "power_in"))
      (node (ref "P5") (pin "P$156") (pinfunction "P$1_P$156") (pintype "power_in"))
      (node (ref "P5") (pin "P$157") (pinfunction "P$1_P$157") (pintype "power_in"))
      (node (ref "P5") (pin "P$158") (pinfunction "P$1_P$158") (pintype "power_in"))
      (node (ref "P5") (pin "P$159") (pinfunction "P$1_P$159") (pintype "power_in"))
      (node (ref "P5") (pin "P$16") (pinfunction "P$1_P$16") (pintype "power_in"))
      (node (ref "P5") (pin "P$160") (pinfunction "P$1_P$160") (pintype "power_in"))
      (node (ref "P5") (pin "P$161") (pinfunction "P$1_P$161") (pintype "power_in"))
      (node (ref "P5") (pin "P$162") (pinfunction "P$1_P$162") (pintype "power_in"))
      (node (ref "P5") (pin "P$163") (pinfunction "P$1_P$163") (pintype "power_in"))
      (node (ref "P5") (pin "P$164") (pinfunction "P$1_P$164") (pintype "power_in"))
      (node (ref "P5") (pin "P$165") (pinfunction "P$1_P$165") (pintype "power_in"))
      (node (ref "P5") (pin "P$166") (pinfunction "P$1_P$166") (pintype "power_in"))
      (node (ref "P5") (pin "P$167") (pinfunction "P$1_P$167") (pintype "power_in"))
      (node (ref "P5") (pin "P$168") (pinfunction "P$1_P$168") (pintype "power_in"))
      (node (ref "P5") (pin "P$169") (pinfunction "P$1_P$169") (pintype "power_in"))
      (node (ref "P5") (pin "P$17") (pinfunction "P$1_P$17") (pintype "power_in"))
      (node (ref "P5") (pin "P$170") (pinfunction "P$1_P$170") (pintype "power_in"))
      (node (ref "P5") (pin "P$171") (pinfunction "P$1_P$171") (pintype "power_in"))
      (node (ref "P5") (pin "P$172") (pinfunction "P$1_P$172") (pintype "power_in"))
      (node (ref "P5") (pin "P$173") (pinfunction "P$1_P$173") (pintype "power_in"))
      (node (ref "P5") (pin "P$174") (pinfunction "P$1_P$174") (pintype "power_in"))
      (node (ref "P5") (pin "P$175") (pinfunction "P$1_P$175") (pintype "power_in"))
      (node (ref "P5") (pin "P$176") (pinfunction "P$1_P$176") (pintype "power_in"))
      (node (ref "P5") (pin "P$177") (pinfunction "P$1_P$177") (pintype "power_in"))
      (node (ref "P5") (pin "P$178") (pinfunction "P$1_P$178") (pintype "power_in"))
      (node (ref "P5") (pin "P$179") (pinfunction "P$1_P$179") (pintype "power_in"))
      (node (ref "P5") (pin "P$18") (pinfunction "P$1_P$18") (pintype "power_in"))
      (node (ref "P5") (pin "P$180") (pinfunction "P$1_P$180") (pintype "power_in"))
      (node (ref "P5") (pin "P$181") (pinfunction "P$1_P$181") (pintype "power_in"))
      (node (ref "P5") (pin "P$182") (pinfunction "P$1_P$182") (pintype "power_in"))
      (node (ref "P5") (pin "P$183") (pinfunction "P$1_P$183") (pintype "power_in"))
      (node (ref "P5") (pin "P$184") (pinfunction "P$1_P$184") (pintype "power_in"))
      (node (ref "P5") (pin "P$185") (pinfunction "P$1_P$185") (pintype "power_in"))
      (node (ref "P5") (pin "P$186") (pinfunction "P$1_P$186") (pintype "power_in"))
      (node (ref "P5") (pin "P$187") (pinfunction "P$1_P$187") (pintype "power_in"))
      (node (ref "P5") (pin "P$188") (pinfunction "P$1_P$188") (pintype "power_in"))
      (node (ref "P5") (pin "P$189") (pinfunction "P$1_P$189") (pintype "power_in"))
      (node (ref "P5") (pin "P$19") (pinfunction "P$1_P$19") (pintype "power_in"))
      (node (ref "P5") (pin "P$190") (pinfunction "P$1_P$190") (pintype "power_in"))
      (node (ref "P5") (pin "P$191") (pinfunction "P$1_P$191") (pintype "power_in"))
      (node (ref "P5") (pin "P$192") (pinfunction "P$1_P$192") (pintype "power_in"))
      (node (ref "P5") (pin "P$193") (pinfunction "P$1_P$193") (pintype "power_in"))
      (node (ref "P5") (pin "P$194") (pinfunction "P$1_P$194") (pintype "power_in"))
      (node (ref "P5") (pin "P$195") (pinfunction "P$1_P$195") (pintype "power_in"))
      (node (ref "P5") (pin "P$196") (pinfunction "P$1_P$196") (pintype "power_in"))
      (node (ref "P5") (pin "P$197") (pinfunction "P$1_P$197") (pintype "power_in"))
      (node (ref "P5") (pin "P$198") (pinfunction "P$1_P$198") (pintype "power_in"))
      (node (ref "P5") (pin "P$199") (pinfunction "P$1_P$199") (pintype "power_in"))
      (node (ref "P5") (pin "P$2") (pinfunction "P$1_P$2") (pintype "power_in"))
      (node (ref "P5") (pin "P$20") (pinfunction "P$1_P$20") (pintype "power_in"))
      (node (ref "P5") (pin "P$200") (pinfunction "P$1_P$200") (pintype "power_in"))
      (node (ref "P5") (pin "P$201") (pinfunction "P$1_P$201") (pintype "power_in"))
      (node (ref "P5") (pin "P$202") (pinfunction "P$1_P$202") (pintype "power_in"))
      (node (ref "P5") (pin "P$203") (pinfunction "P$1_P$203") (pintype "power_in"))
      (node (ref "P5") (pin "P$204") (pinfunction "P$1_P$204") (pintype "power_in"))
      (node (ref "P5") (pin "P$205") (pinfunction "P$1_P$205") (pintype "power_in"))
      (node (ref "P5") (pin "P$206") (pinfunction "P$1_P$206") (pintype "power_in"))
      (node (ref "P5") (pin "P$207") (pinfunction "P$1_P$207") (pintype "power_in"))
      (node (ref "P5") (pin "P$208") (pinfunction "P$1_P$208") (pintype "power_in"))
      (node (ref "P5") (pin "P$209") (pinfunction "P$1_P$209") (pintype "power_in"))
      (node (ref "P5") (pin "P$21") (pinfunction "P$1_P$21") (pintype "power_in"))
      (node (ref "P5") (pin "P$210") (pinfunction "P$1_P$210") (pintype "power_in"))
      (node (ref "P5") (pin "P$211") (pinfunction "P$1_P$211") (pintype "power_in"))
      (node (ref "P5") (pin "P$212") (pinfunction "P$1_P$212") (pintype "power_in"))
      (node (ref "P5") (pin "P$213") (pinfunction "P$1_P$213") (pintype "power_in"))
      (node (ref "P5") (pin "P$214") (pinfunction "P$1_P$214") (pintype "power_in"))
      (node (ref "P5") (pin "P$215") (pinfunction "P$1_P$215") (pintype "power_in"))
      (node (ref "P5") (pin "P$216") (pinfunction "P$1_P$216") (pintype "power_in"))
      (node (ref "P5") (pin "P$217") (pinfunction "P$1_P$217") (pintype "power_in"))
      (node (ref "P5") (pin "P$218") (pinfunction "P$1_P$218") (pintype "power_in"))
      (node (ref "P5") (pin "P$219") (pinfunction "P$1_P$219") (pintype "power_in"))
      (node (ref "P5") (pin "P$22") (pinfunction "P$1_P$22") (pintype "power_in"))
      (node (ref "P5") (pin "P$220") (pinfunction "P$1_P$220") (pintype "power_in"))
      (node (ref "P5") (pin "P$221") (pinfunction "P$1_P$221") (pintype "power_in"))
      (node (ref "P5") (pin "P$222") (pinfunction "P$1_P$222") (pintype "power_in"))
      (node (ref "P5") (pin "P$223") (pinfunction "P$1_P$223") (pintype "power_in"))
      (node (ref "P5") (pin "P$224") (pinfunction "P$1_P$224") (pintype "power_in"))
      (node (ref "P5") (pin "P$225") (pinfunction "P$1_P$225") (pintype "power_in"))
      (node (ref "P5") (pin "P$226") (pinfunction "P$1_P$226") (pintype "power_in"))
      (node (ref "P5") (pin "P$227") (pinfunction "P$1_P$227") (pintype "power_in"))
      (node (ref "P5") (pin "P$228") (pinfunction "P$1_P$228") (pintype "power_in"))
      (node (ref "P5") (pin "P$229") (pinfunction "P$1_P$229") (pintype "power_in"))
      (node (ref "P5") (pin "P$23") (pinfunction "P$1_P$23") (pintype "power_in"))
      (node (ref "P5") (pin "P$230") (pinfunction "P$1_P$230") (pintype "power_in"))
      (node (ref "P5") (pin "P$231") (pinfunction "P$1_P$231") (pintype "power_in"))
      (node (ref "P5") (pin "P$232") (pinfunction "P$1_P$232") (pintype "power_in"))
      (node (ref "P5") (pin "P$233") (pinfunction "P$1_P$233") (pintype "power_in"))
      (node (ref "P5") (pin "P$234") (pinfunction "P$1_P$234") (pintype "power_in"))
      (node (ref "P5") (pin "P$235") (pinfunction "P$1_P$235") (pintype "power_in"))
      (node (ref "P5") (pin "P$236") (pinfunction "P$1_P$236") (pintype "power_in"))
      (node (ref "P5") (pin "P$237") (pinfunction "P$1_P$237") (pintype "power_in"))
      (node (ref "P5") (pin "P$238") (pinfunction "P$1_P$238") (pintype "power_in"))
      (node (ref "P5") (pin "P$239") (pinfunction "P$1_P$239") (pintype "power_in"))
      (node (ref "P5") (pin "P$24") (pinfunction "P$1_P$24") (pintype "power_in"))
      (node (ref "P5") (pin "P$240") (pinfunction "P$1_P$240") (pintype "power_in"))
      (node (ref "P5") (pin "P$241") (pinfunction "P$1_P$241") (pintype "power_in"))
      (node (ref "P5") (pin "P$242") (pinfunction "P$1_P$242") (pintype "power_in"))
      (node (ref "P5") (pin "P$243") (pinfunction "P$1_P$243") (pintype "power_in"))
      (node (ref "P5") (pin "P$244") (pinfunction "P$1_P$244") (pintype "power_in"))
      (node (ref "P5") (pin "P$245") (pinfunction "P$1_P$245") (pintype "power_in"))
      (node (ref "P5") (pin "P$246") (pinfunction "P$1_P$246") (pintype "power_in"))
      (node (ref "P5") (pin "P$247") (pinfunction "P$1_P$247") (pintype "power_in"))
      (node (ref "P5") (pin "P$248") (pinfunction "P$1_P$248") (pintype "power_in"))
      (node (ref "P5") (pin "P$249") (pinfunction "P$1_P$249") (pintype "power_in"))
      (node (ref "P5") (pin "P$25") (pinfunction "P$1_P$25") (pintype "power_in"))
      (node (ref "P5") (pin "P$250") (pinfunction "P$1_P$250") (pintype "power_in"))
      (node (ref "P5") (pin "P$251") (pinfunction "P$1_P$251") (pintype "power_in"))
      (node (ref "P5") (pin "P$252") (pinfunction "P$1_P$252") (pintype "power_in"))
      (node (ref "P5") (pin "P$253") (pinfunction "P$1_P$253") (pintype "power_in"))
      (node (ref "P5") (pin "P$254") (pinfunction "P$1_P$254") (pintype "power_in"))
      (node (ref "P5") (pin "P$255") (pinfunction "P$1_P$255") (pintype "power_in"))
      (node (ref "P5") (pin "P$256") (pinfunction "P$1_P$256") (pintype "power_in"))
      (node (ref "P5") (pin "P$257") (pinfunction "P$1_P$257") (pintype "power_in"))
      (node (ref "P5") (pin "P$258") (pinfunction "P$1_P$258") (pintype "power_in"))
      (node (ref "P5") (pin "P$259") (pinfunction "P$1_P$259") (pintype "power_in"))
      (node (ref "P5") (pin "P$26") (pinfunction "P$1_P$26") (pintype "power_in"))
      (node (ref "P5") (pin "P$260") (pinfunction "P$1_P$260") (pintype "power_in"))
      (node (ref "P5") (pin "P$261") (pinfunction "P$1_P$261") (pintype "power_in"))
      (node (ref "P5") (pin "P$262") (pinfunction "P$1_P$262") (pintype "power_in"))
      (node (ref "P5") (pin "P$263") (pinfunction "P$1_P$263") (pintype "power_in"))
      (node (ref "P5") (pin "P$264") (pinfunction "P$1_P$264") (pintype "power_in"))
      (node (ref "P5") (pin "P$265") (pinfunction "P$1_P$265") (pintype "power_in"))
      (node (ref "P5") (pin "P$266") (pinfunction "P$1_P$266") (pintype "power_in"))
      (node (ref "P5") (pin "P$267") (pinfunction "P$1_P$267") (pintype "power_in"))
      (node (ref "P5") (pin "P$268") (pinfunction "P$1_P$268") (pintype "power_in"))
      (node (ref "P5") (pin "P$269") (pinfunction "P$1_P$269") (pintype "power_in"))
      (node (ref "P5") (pin "P$27") (pinfunction "P$1_P$27") (pintype "power_in"))
      (node (ref "P5") (pin "P$270") (pinfunction "P$1_P$270") (pintype "power_in"))
      (node (ref "P5") (pin "P$271") (pinfunction "P$1_P$271") (pintype "power_in"))
      (node (ref "P5") (pin "P$272") (pinfunction "P$1_P$272") (pintype "power_in"))
      (node (ref "P5") (pin "P$273") (pinfunction "P$1_P$273") (pintype "power_in"))
      (node (ref "P5") (pin "P$274") (pinfunction "P$1_P$274") (pintype "power_in"))
      (node (ref "P5") (pin "P$275") (pinfunction "P$1_P$275") (pintype "power_in"))
      (node (ref "P5") (pin "P$276") (pinfunction "P$1_P$276") (pintype "power_in"))
      (node (ref "P5") (pin "P$277") (pinfunction "P$1_P$277") (pintype "power_in"))
      (node (ref "P5") (pin "P$278") (pinfunction "P$1_P$278") (pintype "power_in"))
      (node (ref "P5") (pin "P$279") (pinfunction "P$1_P$279") (pintype "power_in"))
      (node (ref "P5") (pin "P$28") (pinfunction "P$1_P$28") (pintype "power_in"))
      (node (ref "P5") (pin "P$280") (pinfunction "P$1_P$280") (pintype "power_in"))
      (node (ref "P5") (pin "P$281") (pinfunction "P$1_P$281") (pintype "power_in"))
      (node (ref "P5") (pin "P$282") (pinfunction "P$1_P$282") (pintype "power_in"))
      (node (ref "P5") (pin "P$283") (pinfunction "P$1_P$283") (pintype "power_in"))
      (node (ref "P5") (pin "P$284") (pinfunction "P$1_P$284") (pintype "power_in"))
      (node (ref "P5") (pin "P$285") (pinfunction "P$1_P$285") (pintype "power_in"))
      (node (ref "P5") (pin "P$286") (pinfunction "P$1_P$286") (pintype "power_in"))
      (node (ref "P5") (pin "P$287") (pinfunction "P$1_P$287") (pintype "power_in"))
      (node (ref "P5") (pin "P$288") (pinfunction "P$1_P$288") (pintype "power_in"))
      (node (ref "P5") (pin "P$29") (pinfunction "P$1_P$29") (pintype "power_in"))
      (node (ref "P5") (pin "P$3") (pinfunction "P$1_P$3") (pintype "power_in"))
      (node (ref "P5") (pin "P$30") (pinfunction "P$1_P$30") (pintype "power_in"))
      (node (ref "P5") (pin "P$31") (pinfunction "P$1_P$31") (pintype "power_in"))
      (node (ref "P5") (pin "P$32") (pinfunction "P$1_P$32") (pintype "power_in"))
      (node (ref "P5") (pin "P$33") (pinfunction "P$1_P$33") (pintype "power_in"))
      (node (ref "P5") (pin "P$34") (pinfunction "P$1_P$34") (pintype "power_in"))
      (node (ref "P5") (pin "P$35") (pinfunction "P$1_P$35") (pintype "power_in"))
      (node (ref "P5") (pin "P$36") (pinfunction "P$1_P$36") (pintype "power_in"))
      (node (ref "P5") (pin "P$37") (pinfunction "P$1_P$37") (pintype "power_in"))
      (node (ref "P5") (pin "P$38") (pinfunction "P$1_P$38") (pintype "power_in"))
      (node (ref "P5") (pin "P$39") (pinfunction "P$1_P$39") (pintype "power_in"))
      (node (ref "P5") (pin "P$4") (pinfunction "P$1_P$4") (pintype "power_in"))
      (node (ref "P5") (pin "P$40") (pinfunction "P$1_P$40") (pintype "power_in"))
      (node (ref "P5") (pin "P$41") (pinfunction "P$1_P$41") (pintype "power_in"))
      (node (ref "P5") (pin "P$42") (pinfunction "P$1_P$42") (pintype "power_in"))
      (node (ref "P5") (pin "P$43") (pinfunction "P$1_P$43") (pintype "power_in"))
      (node (ref "P5") (pin "P$44") (pinfunction "P$1_P$44") (pintype "power_in"))
      (node (ref "P5") (pin "P$45") (pinfunction "P$1_P$45") (pintype "power_in"))
      (node (ref "P5") (pin "P$46") (pinfunction "P$1_P$46") (pintype "power_in"))
      (node (ref "P5") (pin "P$47") (pinfunction "P$1_P$47") (pintype "power_in"))
      (node (ref "P5") (pin "P$48") (pinfunction "P$1_P$48") (pintype "power_in"))
      (node (ref "P5") (pin "P$49") (pinfunction "P$1_P$49") (pintype "power_in"))
      (node (ref "P5") (pin "P$5") (pinfunction "P$1_P$5") (pintype "power_in"))
      (node (ref "P5") (pin "P$50") (pinfunction "P$1_P$50") (pintype "power_in"))
      (node (ref "P5") (pin "P$51") (pinfunction "P$1_P$51") (pintype "power_in"))
      (node (ref "P5") (pin "P$52") (pinfunction "P$1_P$52") (pintype "power_in"))
      (node (ref "P5") (pin "P$53") (pinfunction "P$1_P$53") (pintype "power_in"))
      (node (ref "P5") (pin "P$54") (pinfunction "P$1_P$54") (pintype "power_in"))
      (node (ref "P5") (pin "P$55") (pinfunction "P$1_P$55") (pintype "power_in"))
      (node (ref "P5") (pin "P$56") (pinfunction "P$1_P$56") (pintype "power_in"))
      (node (ref "P5") (pin "P$57") (pinfunction "P$1_P$57") (pintype "power_in"))
      (node (ref "P5") (pin "P$58") (pinfunction "P$1_P$58") (pintype "power_in"))
      (node (ref "P5") (pin "P$59") (pinfunction "P$1_P$59") (pintype "power_in"))
      (node (ref "P5") (pin "P$6") (pinfunction "P$1_P$6") (pintype "power_in"))
      (node (ref "P5") (pin "P$60") (pinfunction "P$1_P$60") (pintype "power_in"))
      (node (ref "P5") (pin "P$61") (pinfunction "P$1_P$61") (pintype "power_in"))
      (node (ref "P5") (pin "P$62") (pinfunction "P$1_P$62") (pintype "power_in"))
      (node (ref "P5") (pin "P$63") (pinfunction "P$1_P$63") (pintype "power_in"))
      (node (ref "P5") (pin "P$64") (pinfunction "P$1_P$64") (pintype "power_in"))
      (node (ref "P5") (pin "P$65") (pinfunction "P$1_P$65") (pintype "power_in"))
      (node (ref "P5") (pin "P$66") (pinfunction "P$1_P$66") (pintype "power_in"))
      (node (ref "P5") (pin "P$67") (pinfunction "P$1_P$67") (pintype "power_in"))
      (node (ref "P5") (pin "P$68") (pinfunction "P$1_P$68") (pintype "power_in"))
      (node (ref "P5") (pin "P$69") (pinfunction "P$1_P$69") (pintype "power_in"))
      (node (ref "P5") (pin "P$7") (pinfunction "P$1_P$7") (pintype "power_in"))
      (node (ref "P5") (pin "P$70") (pinfunction "P$1_P$70") (pintype "power_in"))
      (node (ref "P5") (pin "P$71") (pinfunction "P$1_P$71") (pintype "power_in"))
      (node (ref "P5") (pin "P$72") (pinfunction "P$1_P$72") (pintype "power_in"))
      (node (ref "P5") (pin "P$73") (pinfunction "P$1_P$73") (pintype "power_in"))
      (node (ref "P5") (pin "P$74") (pinfunction "P$1_P$74") (pintype "power_in"))
      (node (ref "P5") (pin "P$75") (pinfunction "P$1_P$75") (pintype "power_in"))
      (node (ref "P5") (pin "P$76") (pinfunction "P$1_P$76") (pintype "power_in"))
      (node (ref "P5") (pin "P$77") (pinfunction "P$1_P$77") (pintype "power_in"))
      (node (ref "P5") (pin "P$78") (pinfunction "P$1_P$78") (pintype "power_in"))
      (node (ref "P5") (pin "P$79") (pinfunction "P$1_P$79") (pintype "power_in"))
      (node (ref "P5") (pin "P$8") (pinfunction "P$1_P$8") (pintype "power_in"))
      (node (ref "P5") (pin "P$80") (pinfunction "P$1_P$80") (pintype "power_in"))
      (node (ref "P5") (pin "P$81") (pinfunction "P$1_P$81") (pintype "power_in"))
      (node (ref "P5") (pin "P$82") (pinfunction "P$1_P$82") (pintype "power_in"))
      (node (ref "P5") (pin "P$83") (pinfunction "P$1_P$83") (pintype "power_in"))
      (node (ref "P5") (pin "P$84") (pinfunction "P$1_P$84") (pintype "power_in"))
      (node (ref "P5") (pin "P$85") (pinfunction "P$1_P$85") (pintype "power_in"))
      (node (ref "P5") (pin "P$86") (pinfunction "P$1_P$86") (pintype "power_in"))
      (node (ref "P5") (pin "P$87") (pinfunction "P$1_P$87") (pintype "power_in"))
      (node (ref "P5") (pin "P$88") (pinfunction "P$1_P$88") (pintype "power_in"))
      (node (ref "P5") (pin "P$89") (pinfunction "P$1_P$89") (pintype "power_in"))
      (node (ref "P5") (pin "P$9") (pinfunction "P$1_P$9") (pintype "power_in"))
      (node (ref "P5") (pin "P$90") (pinfunction "P$1_P$90") (pintype "power_in"))
      (node (ref "P5") (pin "P$91") (pinfunction "P$1_P$91") (pintype "power_in"))
      (node (ref "P5") (pin "P$92") (pinfunction "P$1_P$92") (pintype "power_in"))
      (node (ref "P5") (pin "P$93") (pinfunction "P$1_P$93") (pintype "power_in"))
      (node (ref "P5") (pin "P$94") (pinfunction "P$1_P$94") (pintype "power_in"))
      (node (ref "P5") (pin "P$95") (pinfunction "P$1_P$95") (pintype "power_in"))
      (node (ref "P5") (pin "P$96") (pinfunction "P$1_P$96") (pintype "power_in"))
      (node (ref "P5") (pin "P$97") (pinfunction "P$1_P$97") (pintype "power_in"))
      (node (ref "P5") (pin "P$98") (pinfunction "P$1_P$98") (pintype "power_in"))
      (node (ref "P5") (pin "P$99") (pinfunction "P$1_P$99") (pintype "power_in"))
    )
    (net (code "7") (name "/P6") (class "Default")
      (node (ref "JP1") (pin "P$7") (pinfunction "6_P$7") (pintype "bidirectional"))
      (node (ref "P6") (pin "P$1") (pinfunction "P$1_P$1") (pintype "power_in"))
      (node (ref "P6") (pin "P$10") (pinfunction "P$1_P$10") (pintype "power_in"))
      (node (ref "P6") (pin "P$100") (pinfunction "P$1_P$100") (pintype "power_in"))
      (node (ref "P6") (pin "P$101") (pinfunction "P$1_P$101") (pintype "power_in"))
      (node (ref "P6") (pin "P$102") (pinfunction "P$1_P$102") (pintype "power_in"))
      (node (ref "P6") (pin "P$103") (pinfunction "P$1_P$103") (pintype "power_in"))
      (node (ref "P6") (pin "P$104") (pinfunction "P$1_P$104") (pintype "power_in"))
      (node (ref "P6") (pin "P$105") (pinfunction "P$1_P$105") (pintype "power_in"))
      (node (ref "P6") (pin "P$106") (pinfunction "P$1_P$106") (pintype "power_in"))
      (node (ref "P6") (pin "P$107") (pinfunction "P$1_P$107") (pintype "power_in"))
      (node (ref "P6") (pin "P$108") (pinfunction "P$1_P$108") (pintype "power_in"))
      (node (ref "P6") (pin "P$109") (pinfunction "P$1_P$109") (pintype "power_in"))
      (node (ref "P6") (pin "P$11") (pinfunction "P$1_P$11") (pintype "power_in"))
      (node (ref "P6") (pin "P$110") (pinfunction "P$1_P$110") (pintype "power_in"))
      (node (ref "P6") (pin "P$111") (pinfunction "P$1_P$111") (pintype "power_in"))
      (node (ref "P6") (pin "P$112") (pinfunction "P$1_P$112") (pintype "power_in"))
      (node (ref "P6") (pin "P$113") (pinfunction "P$1_P$113") (pintype "power_in"))
      (node (ref "P6") (pin "P$114") (pinfunction "P$1_P$114") (pintype "power_in"))
      (node (ref "P6") (pin "P$115") (pinfunction "P$1_P$115") (pintype "power_in"))
      (node (ref "P6") (pin "P$116") (pinfunction "P$1_P$116") (pintype "power_in"))
      (node (ref "P6") (pin "P$117") (pinfunction "P$1_P$117") (pintype "power_in"))
      (node (ref "P6") (pin "P$118") (pinfunction "P$1_P$118") (pintype "power_in"))
      (node (ref "P6") (pin "P$119") (pinfunction "P$1_P$119") (pintype "power_in"))
      (node (ref "P6") (pin "P$12") (pinfunction "P$1_P$12") (pintype "power_in"))
      (node (ref "P6") (pin "P$120") (pinfunction "P$1_P$120") (pintype "power_in"))
      (node (ref "P6") (pin "P$121") (pinfunction "P$1_P$121") (pintype "power_in"))
      (node (ref "P6") (pin "P$122") (pinfunction "P$1_P$122") (pintype "power_in"))
      (node (ref "P6") (pin "P$123") (pinfunction "P$1_P$123") (pintype "power_in"))
      (node (ref "P6") (pin "P$124") (pinfunction "P$1_P$124") (pintype "power_in"))
      (node (ref "P6") (pin "P$125") (pinfunction "P$1_P$125") (pintype "power_in"))
      (node (ref "P6") (pin "P$126") (pinfunction "P$1_P$126") (pintype "power_in"))
      (node (ref "P6") (pin "P$127") (pinfunction "P$1_P$127") (pintype "power_in"))
      (node (ref "P6") (pin "P$128") (pinfunction "P$1_P$128") (pintype "power_in"))
      (node (ref "P6") (pin "P$129") (pinfunction "P$1_P$129") (pintype "power_in"))
      (node (ref "P6") (pin "P$13") (pinfunction "P$1_P$13") (pintype "power_in"))
      (node (ref "P6") (pin "P$130") (pinfunction "P$1_P$130") (pintype "power_in"))
      (node (ref "P6") (pin "P$131") (pinfunction "P$1_P$131") (pintype "power_in"))
      (node (ref "P6") (pin "P$132") (pinfunction "P$1_P$132") (pintype "power_in"))
      (node (ref "P6") (pin "P$133") (pinfunction "P$1_P$133") (pintype "power_in"))
      (node (ref "P6") (pin "P$134") (pinfunction "P$1_P$134") (pintype "power_in"))
      (node (ref "P6") (pin "P$135") (pinfunction "P$1_P$135") (pintype "power_in"))
      (node (ref "P6") (pin "P$136") (pinfunction "P$1_P$136") (pintype "power_in"))
      (node (ref "P6") (pin "P$137") (pinfunction "P$1_P$137") (pintype "power_in"))
      (node (ref "P6") (pin "P$138") (pinfunction "P$1_P$138") (pintype "power_in"))
      (node (ref "P6") (pin "P$139") (pinfunction "P$1_P$139") (pintype "power_in"))
      (node (ref "P6") (pin "P$14") (pinfunction "P$1_P$14") (pintype "power_in"))
      (node (ref "P6") (pin "P$140") (pinfunction "P$1_P$140") (pintype "power_in"))
      (node (ref "P6") (pin "P$141") (pinfunction "P$1_P$141") (pintype "power_in"))
      (node (ref "P6") (pin "P$142") (pinfunction "P$1_P$142") (pintype "power_in"))
      (node (ref "P6") (pin "P$143") (pinfunction "P$1_P$143") (pintype "power_in"))
      (node (ref "P6") (pin "P$144") (pinfunction "P$1_P$144") (pintype "power_in"))
      (node (ref "P6") (pin "P$145") (pinfunction "P$1_P$145") (pintype "power_in"))
      (node (ref "P6") (pin "P$146") (pinfunction "P$1_P$146") (pintype "power_in"))
      (node (ref "P6") (pin "P$147") (pinfunction "P$1_P$147") (pintype "power_in"))
      (node (ref "P6") (pin "P$148") (pinfunction "P$1_P$148") (pintype "power_in"))
      (node (ref "P6") (pin "P$149") (pinfunction "P$1_P$149") (pintype "power_in"))
      (node (ref "P6") (pin "P$15") (pinfunction "P$1_P$15") (pintype "power_in"))
      (node (ref "P6") (pin "P$150") (pinfunction "P$1_P$150") (pintype "power_in"))
      (node (ref "P6") (pin "P$151") (pinfunction "P$1_P$151") (pintype "power_in"))
      (node (ref "P6") (pin "P$152") (pinfunction "P$1_P$152") (pintype "power_in"))
      (node (ref "P6") (pin "P$153") (pinfunction "P$1_P$153") (pintype "power_in"))
      (node (ref "P6") (pin "P$154") (pinfunction "P$1_P$154") (pintype "power_in"))
      (node (ref "P6") (pin "P$155") (pinfunction "P$1_P$155") (pintype "power_in"))
      (node (ref "P6") (pin "P$156") (pinfunction "P$1_P$156") (pintype "power_in"))
      (node (ref "P6") (pin "P$157") (pinfunction "P$1_P$157") (pintype "power_in"))
      (node (ref "P6") (pin "P$158") (pinfunction "P$1_P$158") (pintype "power_in"))
      (node (ref "P6") (pin "P$159") (pinfunction "P$1_P$159") (pintype "power_in"))
      (node (ref "P6") (pin "P$16") (pinfunction "P$1_P$16") (pintype "power_in"))
      (node (ref "P6") (pin "P$160") (pinfunction "P$1_P$160") (pintype "power_in"))
      (node (ref "P6") (pin "P$161") (pinfunction "P$1_P$161") (pintype "power_in"))
      (node (ref "P6") (pin "P$162") (pinfunction "P$1_P$162") (pintype "power_in"))
      (node (ref "P6") (pin "P$163") (pinfunction "P$1_P$163") (pintype "power_in"))
      (node (ref "P6") (pin "P$164") (pinfunction "P$1_P$164") (pintype "power_in"))
      (node (ref "P6") (pin "P$165") (pinfunction "P$1_P$165") (pintype "power_in"))
      (node (ref "P6") (pin "P$166") (pinfunction "P$1_P$166") (pintype "power_in"))
      (node (ref "P6") (pin "P$167") (pinfunction "P$1_P$167") (pintype "power_in"))
      (node (ref "P6") (pin "P$168") (pinfunction "P$1_P$168") (pintype "power_in"))
      (node (ref "P6") (pin "P$169") (pinfunction "P$1_P$169") (pintype "power_in"))
      (node (ref "P6") (pin "P$17") (pinfunction "P$1_P$17") (pintype "power_in"))
      (node (ref "P6") (pin "P$170") (pinfunction "P$1_P$170") (pintype "power_in"))
      (node (ref "P6") (pin "P$171") (pinfunction "P$1_P$171") (pintype "power_in"))
      (node (ref "P6") (pin "P$172") (pinfunction "P$1_P$172") (pintype "power_in"))
      (node (ref "P6") (pin "P$173") (pinfunction "P$1_P$173") (pintype "power_in"))
      (node (ref "P6") (pin "P$174") (pinfunction "P$1_P$174") (pintype "power_in"))
      (node (ref "P6") (pin "P$175") (pinfunction "P$1_P$175") (pintype "power_in"))
      (node (ref "P6") (pin "P$176") (pinfunction "P$1_P$176") (pintype "power_in"))
      (node (ref "P6") (pin "P$177") (pinfunction "P$1_P$177") (pintype "power_in"))
      (node (ref "P6") (pin "P$178") (pinfunction "P$1_P$178") (pintype "power_in"))
      (node (ref "P6") (pin "P$179") (pinfunction "P$1_P$179") (pintype "power_in"))
      (node (ref "P6") (pin "P$18") (pinfunction "P$1_P$18") (pintype "power_in"))
      (node (ref "P6") (pin "P$180") (pinfunction "P$1_P$180") (pintype "power_in"))
      (node (ref "P6") (pin "P$181") (pinfunction "P$1_P$181") (pintype "power_in"))
      (node (ref "P6") (pin "P$182") (pinfunction "P$1_P$182") (pintype "power_in"))
      (node (ref "P6") (pin "P$183") (pinfunction "P$1_P$183") (pintype "power_in"))
      (node (ref "P6") (pin "P$184") (pinfunction "P$1_P$184") (pintype "power_in"))
      (node (ref "P6") (pin "P$185") (pinfunction "P$1_P$185") (pintype "power_in"))
      (node (ref "P6") (pin "P$186") (pinfunction "P$1_P$186") (pintype "power_in"))
      (node (ref "P6") (pin "P$187") (pinfunction "P$1_P$187") (pintype "power_in"))
      (node (ref "P6") (pin "P$188") (pinfunction "P$1_P$188") (pintype "power_in"))
      (node (ref "P6") (pin "P$189") (pinfunction "P$1_P$189") (pintype "power_in"))
      (node (ref "P6") (pin "P$19") (pinfunction "P$1_P$19") (pintype "power_in"))
      (node (ref "P6") (pin "P$190") (pinfunction "P$1_P$190") (pintype "power_in"))
      (node (ref "P6") (pin "P$191") (pinfunction "P$1_P$191") (pintype "power_in"))
      (node (ref "P6") (pin "P$192") (pinfunction "P$1_P$192") (pintype "power_in"))
      (node (ref "P6") (pin "P$193") (pinfunction "P$1_P$193") (pintype "power_in"))
      (node (ref "P6") (pin "P$194") (pinfunction "P$1_P$194") (pintype "power_in"))
      (node (ref "P6") (pin "P$195") (pinfunction "P$1_P$195") (pintype "power_in"))
      (node (ref "P6") (pin "P$196") (pinfunction "P$1_P$196") (pintype "power_in"))
      (node (ref "P6") (pin "P$197") (pinfunction "P$1_P$197") (pintype "power_in"))
      (node (ref "P6") (pin "P$198") (pinfunction "P$1_P$198") (pintype "power_in"))
      (node (ref "P6") (pin "P$199") (pinfunction "P$1_P$199") (pintype "power_in"))
      (node (ref "P6") (pin "P$2") (pinfunction "P$1_P$2") (pintype "power_in"))
      (node (ref "P6") (pin "P$20") (pinfunction "P$1_P$20") (pintype "power_in"))
      (node (ref "P6") (pin "P$200") (pinfunction "P$1_P$200") (pintype "power_in"))
      (node (ref "P6") (pin "P$201") (pinfunction "P$1_P$201") (pintype "power_in"))
      (node (ref "P6") (pin "P$202") (pinfunction "P$1_P$202") (pintype "power_in"))
      (node (ref "P6") (pin "P$203") (pinfunction "P$1_P$203") (pintype "power_in"))
      (node (ref "P6") (pin "P$204") (pinfunction "P$1_P$204") (pintype "power_in"))
      (node (ref "P6") (pin "P$205") (pinfunction "P$1_P$205") (pintype "power_in"))
      (node (ref "P6") (pin "P$206") (pinfunction "P$1_P$206") (pintype "power_in"))
      (node (ref "P6") (pin "P$207") (pinfunction "P$1_P$207") (pintype "power_in"))
      (node (ref "P6") (pin "P$208") (pinfunction "P$1_P$208") (pintype "power_in"))
      (node (ref "P6") (pin "P$209") (pinfunction "P$1_P$209") (pintype "power_in"))
      (node (ref "P6") (pin "P$21") (pinfunction "P$1_P$21") (pintype "power_in"))
      (node (ref "P6") (pin "P$210") (pinfunction "P$1_P$210") (pintype "power_in"))
      (node (ref "P6") (pin "P$211") (pinfunction "P$1_P$211") (pintype "power_in"))
      (node (ref "P6") (pin "P$212") (pinfunction "P$1_P$212") (pintype "power_in"))
      (node (ref "P6") (pin "P$213") (pinfunction "P$1_P$213") (pintype "power_in"))
      (node (ref "P6") (pin "P$214") (pinfunction "P$1_P$214") (pintype "power_in"))
      (node (ref "P6") (pin "P$215") (pinfunction "P$1_P$215") (pintype "power_in"))
      (node (ref "P6") (pin "P$216") (pinfunction "P$1_P$216") (pintype "power_in"))
      (node (ref "P6") (pin "P$217") (pinfunction "P$1_P$217") (pintype "power_in"))
      (node (ref "P6") (pin "P$218") (pinfunction "P$1_P$218") (pintype "power_in"))
      (node (ref "P6") (pin "P$219") (pinfunction "P$1_P$219") (pintype "power_in"))
      (node (ref "P6") (pin "P$22") (pinfunction "P$1_P$22") (pintype "power_in"))
      (node (ref "P6") (pin "P$220") (pinfunction "P$1_P$220") (pintype "power_in"))
      (node (ref "P6") (pin "P$221") (pinfunction "P$1_P$221") (pintype "power_in"))
      (node (ref "P6") (pin "P$222") (pinfunction "P$1_P$222") (pintype "power_in"))
      (node (ref "P6") (pin "P$223") (pinfunction "P$1_P$223") (pintype "power_in"))
      (node (ref "P6") (pin "P$224") (pinfunction "P$1_P$224") (pintype "power_in"))
      (node (ref "P6") (pin "P$225") (pinfunction "P$1_P$225") (pintype "power_in"))
      (node (ref "P6") (pin "P$226") (pinfunction "P$1_P$226") (pintype "power_in"))
      (node (ref "P6") (pin "P$227") (pinfunction "P$1_P$227") (pintype "power_in"))
      (node (ref "P6") (pin "P$228") (pinfunction "P$1_P$228") (pintype "power_in"))
      (node (ref "P6") (pin "P$229") (pinfunction "P$1_P$229") (pintype "power_in"))
      (node (ref "P6") (pin "P$23") (pinfunction "P$1_P$23") (pintype "power_in"))
      (node (ref "P6") (pin "P$230") (pinfunction "P$1_P$230") (pintype "power_in"))
      (node (ref "P6") (pin "P$231") (pinfunction "P$1_P$231") (pintype "power_in"))
      (node (ref "P6") (pin "P$232") (pinfunction "P$1_P$232") (pintype "power_in"))
      (node (ref "P6") (pin "P$233") (pinfunction "P$1_P$233") (pintype "power_in"))
      (node (ref "P6") (pin "P$234") (pinfunction "P$1_P$234") (pintype "power_in"))
      (node (ref "P6") (pin "P$235") (pinfunction "P$1_P$235") (pintype "power_in"))
      (node (ref "P6") (pin "P$236") (pinfunction "P$1_P$236") (pintype "power_in"))
      (node (ref "P6") (pin "P$237") (pinfunction "P$1_P$237") (pintype "power_in"))
      (node (ref "P6") (pin "P$238") (pinfunction "P$1_P$238") (pintype "power_in"))
      (node (ref "P6") (pin "P$239") (pinfunction "P$1_P$239") (pintype "power_in"))
      (node (ref "P6") (pin "P$24") (pinfunction "P$1_P$24") (pintype "power_in"))
      (node (ref "P6") (pin "P$240") (pinfunction "P$1_P$240") (pintype "power_in"))
      (node (ref "P6") (pin "P$241") (pinfunction "P$1_P$241") (pintype "power_in"))
      (node (ref "P6") (pin "P$242") (pinfunction "P$1_P$242") (pintype "power_in"))
      (node (ref "P6") (pin "P$243") (pinfunction "P$1_P$243") (pintype "power_in"))
      (node (ref "P6") (pin "P$244") (pinfunction "P$1_P$244") (pintype "power_in"))
      (node (ref "P6") (pin "P$245") (pinfunction "P$1_P$245") (pintype "power_in"))
      (node (ref "P6") (pin "P$246") (pinfunction "P$1_P$246") (pintype "power_in"))
      (node (ref "P6") (pin "P$247") (pinfunction "P$1_P$247") (pintype "power_in"))
      (node (ref "P6") (pin "P$248") (pinfunction "P$1_P$248") (pintype "power_in"))
      (node (ref "P6") (pin "P$249") (pinfunction "P$1_P$249") (pintype "power_in"))
      (node (ref "P6") (pin "P$25") (pinfunction "P$1_P$25") (pintype "power_in"))
      (node (ref "P6") (pin "P$250") (pinfunction "P$1_P$250") (pintype "power_in"))
      (node (ref "P6") (pin "P$251") (pinfunction "P$1_P$251") (pintype "power_in"))
      (node (ref "P6") (pin "P$252") (pinfunction "P$1_P$252") (pintype "power_in"))
      (node (ref "P6") (pin "P$253") (pinfunction "P$1_P$253") (pintype "power_in"))
      (node (ref "P6") (pin "P$254") (pinfunction "P$1_P$254") (pintype "power_in"))
      (node (ref "P6") (pin "P$255") (pinfunction "P$1_P$255") (pintype "power_in"))
      (node (ref "P6") (pin "P$256") (pinfunction "P$1_P$256") (pintype "power_in"))
      (node (ref "P6") (pin "P$257") (pinfunction "P$1_P$257") (pintype "power_in"))
      (node (ref "P6") (pin "P$258") (pinfunction "P$1_P$258") (pintype "power_in"))
      (node (ref "P6") (pin "P$259") (pinfunction "P$1_P$259") (pintype "power_in"))
      (node (ref "P6") (pin "P$26") (pinfunction "P$1_P$26") (pintype "power_in"))
      (node (ref "P6") (pin "P$260") (pinfunction "P$1_P$260") (pintype "power_in"))
      (node (ref "P6") (pin "P$261") (pinfunction "P$1_P$261") (pintype "power_in"))
      (node (ref "P6") (pin "P$262") (pinfunction "P$1_P$262") (pintype "power_in"))
      (node (ref "P6") (pin "P$263") (pinfunction "P$1_P$263") (pintype "power_in"))
      (node (ref "P6") (pin "P$264") (pinfunction "P$1_P$264") (pintype "power_in"))
      (node (ref "P6") (pin "P$265") (pinfunction "P$1_P$265") (pintype "power_in"))
      (node (ref "P6") (pin "P$266") (pinfunction "P$1_P$266") (pintype "power_in"))
      (node (ref "P6") (pin "P$267") (pinfunction "P$1_P$267") (pintype "power_in"))
      (node (ref "P6") (pin "P$268") (pinfunction "P$1_P$268") (pintype "power_in"))
      (node (ref "P6") (pin "P$269") (pinfunction "P$1_P$269") (pintype "power_in"))
      (node (ref "P6") (pin "P$27") (pinfunction "P$1_P$27") (pintype "power_in"))
      (node (ref "P6") (pin "P$270") (pinfunction "P$1_P$270") (pintype "power_in"))
      (node (ref "P6") (pin "P$271") (pinfunction "P$1_P$271") (pintype "power_in"))
      (node (ref "P6") (pin "P$272") (pinfunction "P$1_P$272") (pintype "power_in"))
      (node (ref "P6") (pin "P$273") (pinfunction "P$1_P$273") (pintype "power_in"))
      (node (ref "P6") (pin "P$274") (pinfunction "P$1_P$274") (pintype "power_in"))
      (node (ref "P6") (pin "P$275") (pinfunction "P$1_P$275") (pintype "power_in"))
      (node (ref "P6") (pin "P$276") (pinfunction "P$1_P$276") (pintype "power_in"))
      (node (ref "P6") (pin "P$277") (pinfunction "P$1_P$277") (pintype "power_in"))
      (node (ref "P6") (pin "P$278") (pinfunction "P$1_P$278") (pintype "power_in"))
      (node (ref "P6") (pin "P$279") (pinfunction "P$1_P$279") (pintype "power_in"))
      (node (ref "P6") (pin "P$28") (pinfunction "P$1_P$28") (pintype "power_in"))
      (node (ref "P6") (pin "P$280") (pinfunction "P$1_P$280") (pintype "power_in"))
      (node (ref "P6") (pin "P$281") (pinfunction "P$1_P$281") (pintype "power_in"))
      (node (ref "P6") (pin "P$282") (pinfunction "P$1_P$282") (pintype "power_in"))
      (node (ref "P6") (pin "P$283") (pinfunction "P$1_P$283") (pintype "power_in"))
      (node (ref "P6") (pin "P$284") (pinfunction "P$1_P$284") (pintype "power_in"))
      (node (ref "P6") (pin "P$285") (pinfunction "P$1_P$285") (pintype "power_in"))
      (node (ref "P6") (pin "P$286") (pinfunction "P$1_P$286") (pintype "power_in"))
      (node (ref "P6") (pin "P$287") (pinfunction "P$1_P$287") (pintype "power_in"))
      (node (ref "P6") (pin "P$288") (pinfunction "P$1_P$288") (pintype "power_in"))
      (node (ref "P6") (pin "P$289") (pinfunction "P$1_P$289") (pintype "power_in"))
      (node (ref "P6") (pin "P$29") (pinfunction "P$1_P$29") (pintype "power_in"))
      (node (ref "P6") (pin "P$290") (pinfunction "P$1_P$290") (pintype "power_in"))
      (node (ref "P6") (pin "P$291") (pinfunction "P$1_P$291") (pintype "power_in"))
      (node (ref "P6") (pin "P$292") (pinfunction "P$1_P$292") (pintype "power_in"))
      (node (ref "P6") (pin "P$293") (pinfunction "P$1_P$293") (pintype "power_in"))
      (node (ref "P6") (pin "P$294") (pinfunction "P$1_P$294") (pintype "power_in"))
      (node (ref "P6") (pin "P$295") (pinfunction "P$1_P$295") (pintype "power_in"))
      (node (ref "P6") (pin "P$296") (pinfunction "P$1_P$296") (pintype "power_in"))
      (node (ref "P6") (pin "P$297") (pinfunction "P$1_P$297") (pintype "power_in"))
      (node (ref "P6") (pin "P$298") (pinfunction "P$1_P$298") (pintype "power_in"))
      (node (ref "P6") (pin "P$299") (pinfunction "P$1_P$299") (pintype "power_in"))
      (node (ref "P6") (pin "P$3") (pinfunction "P$1_P$3") (pintype "power_in"))
      (node (ref "P6") (pin "P$30") (pinfunction "P$1_P$30") (pintype "power_in"))
      (node (ref "P6") (pin "P$300") (pinfunction "P$1_P$300") (pintype "power_in"))
      (node (ref "P6") (pin "P$301") (pinfunction "P$1_P$301") (pintype "power_in"))
      (node (ref "P6") (pin "P$302") (pinfunction "P$1_P$302") (pintype "power_in"))
      (node (ref "P6") (pin "P$303") (pinfunction "P$1_P$303") (pintype "power_in"))
      (node (ref "P6") (pin "P$304") (pinfunction "P$1_P$304") (pintype "power_in"))
      (node (ref "P6") (pin "P$305") (pinfunction "P$1_P$305") (pintype "power_in"))
      (node (ref "P6") (pin "P$306") (pinfunction "P$1_P$306") (pintype "power_in"))
      (node (ref "P6") (pin "P$307") (pinfunction "P$1_P$307") (pintype "power_in"))
      (node (ref "P6") (pin "P$308") (pinfunction "P$1_P$308") (pintype "power_in"))
      (node (ref "P6") (pin "P$309") (pinfunction "P$1_P$309") (pintype "power_in"))
      (node (ref "P6") (pin "P$31") (pinfunction "P$1_P$31") (pintype "power_in"))
      (node (ref "P6") (pin "P$310") (pinfunction "P$1_P$310") (pintype "power_in"))
      (node (ref "P6") (pin "P$311") (pinfunction "P$1_P$311") (pintype "power_in"))
      (node (ref "P6") (pin "P$312") (pinfunction "P$1_P$312") (pintype "power_in"))
      (node (ref "P6") (pin "P$313") (pinfunction "P$1_P$313") (pintype "power_in"))
      (node (ref "P6") (pin "P$314") (pinfunction "P$1_P$314") (pintype "power_in"))
      (node (ref "P6") (pin "P$315") (pinfunction "P$1_P$315") (pintype "power_in"))
      (node (ref "P6") (pin "P$316") (pinfunction "P$1_P$316") (pintype "power_in"))
      (node (ref "P6") (pin "P$317") (pinfunction "P$1_P$317") (pintype "power_in"))
      (node (ref "P6") (pin "P$318") (pinfunction "P$1_P$318") (pintype "power_in"))
      (node (ref "P6") (pin "P$319") (pinfunction "P$1_P$319") (pintype "power_in"))
      (node (ref "P6") (pin "P$32") (pinfunction "P$1_P$32") (pintype "power_in"))
      (node (ref "P6") (pin "P$320") (pinfunction "P$1_P$320") (pintype "power_in"))
      (node (ref "P6") (pin "P$321") (pinfunction "P$1_P$321") (pintype "power_in"))
      (node (ref "P6") (pin "P$322") (pinfunction "P$1_P$322") (pintype "power_in"))
      (node (ref "P6") (pin "P$323") (pinfunction "P$1_P$323") (pintype "power_in"))
      (node (ref "P6") (pin "P$324") (pinfunction "P$1_P$324") (pintype "power_in"))
      (node (ref "P6") (pin "P$325") (pinfunction "P$1_P$325") (pintype "power_in"))
      (node (ref "P6") (pin "P$326") (pinfunction "P$1_P$326") (pintype "power_in"))
      (node (ref "P6") (pin "P$327") (pinfunction "P$1_P$327") (pintype "power_in"))
      (node (ref "P6") (pin "P$328") (pinfunction "P$1_P$328") (pintype "power_in"))
      (node (ref "P6") (pin "P$329") (pinfunction "P$1_P$329") (pintype "power_in"))
      (node (ref "P6") (pin "P$33") (pinfunction "P$1_P$33") (pintype "power_in"))
      (node (ref "P6") (pin "P$330") (pinfunction "P$1_P$330") (pintype "power_in"))
      (node (ref "P6") (pin "P$331") (pinfunction "P$1_P$331") (pintype "power_in"))
      (node (ref "P6") (pin "P$332") (pinfunction "P$1_P$332") (pintype "power_in"))
      (node (ref "P6") (pin "P$333") (pinfunction "P$1_P$333") (pintype "power_in"))
      (node (ref "P6") (pin "P$334") (pinfunction "P$1_P$334") (pintype "power_in"))
      (node (ref "P6") (pin "P$335") (pinfunction "P$1_P$335") (pintype "power_in"))
      (node (ref "P6") (pin "P$336") (pinfunction "P$1_P$336") (pintype "power_in"))
      (node (ref "P6") (pin "P$337") (pinfunction "P$1_P$337") (pintype "power_in"))
      (node (ref "P6") (pin "P$338") (pinfunction "P$1_P$338") (pintype "power_in"))
      (node (ref "P6") (pin "P$339") (pinfunction "P$1_P$339") (pintype "power_in"))
      (node (ref "P6") (pin "P$34") (pinfunction "P$1_P$34") (pintype "power_in"))
      (node (ref "P6") (pin "P$340") (pinfunction "P$1_P$340") (pintype "power_in"))
      (node (ref "P6") (pin "P$341") (pinfunction "P$1_P$341") (pintype "power_in"))
      (node (ref "P6") (pin "P$342") (pinfunction "P$1_P$342") (pintype "power_in"))
      (node (ref "P6") (pin "P$343") (pinfunction "P$1_P$343") (pintype "power_in"))
      (node (ref "P6") (pin "P$344") (pinfunction "P$1_P$344") (pintype "power_in"))
      (node (ref "P6") (pin "P$345") (pinfunction "P$1_P$345") (pintype "power_in"))
      (node (ref "P6") (pin "P$346") (pinfunction "P$1_P$346") (pintype "power_in"))
      (node (ref "P6") (pin "P$347") (pinfunction "P$1_P$347") (pintype "power_in"))
      (node (ref "P6") (pin "P$348") (pinfunction "P$1_P$348") (pintype "power_in"))
      (node (ref "P6") (pin "P$349") (pinfunction "P$1_P$349") (pintype "power_in"))
      (node (ref "P6") (pin "P$35") (pinfunction "P$1_P$35") (pintype "power_in"))
      (node (ref "P6") (pin "P$350") (pinfunction "P$1_P$350") (pintype "power_in"))
      (node (ref "P6") (pin "P$351") (pinfunction "P$1_P$351") (pintype "power_in"))
      (node (ref "P6") (pin "P$352") (pinfunction "P$1_P$352") (pintype "power_in"))
      (node (ref "P6") (pin "P$353") (pinfunction "P$1_P$353") (pintype "power_in"))
      (node (ref "P6") (pin "P$354") (pinfunction "P$1_P$354") (pintype "power_in"))
      (node (ref "P6") (pin "P$355") (pinfunction "P$1_P$355") (pintype "power_in"))
      (node (ref "P6") (pin "P$356") (pinfunction "P$1_P$356") (pintype "power_in"))
      (node (ref "P6") (pin "P$357") (pinfunction "P$1_P$357") (pintype "power_in"))
      (node (ref "P6") (pin "P$358") (pinfunction "P$1_P$358") (pintype "power_in"))
      (node (ref "P6") (pin "P$359") (pinfunction "P$1_P$359") (pintype "power_in"))
      (node (ref "P6") (pin "P$36") (pinfunction "P$1_P$36") (pintype "power_in"))
      (node (ref "P6") (pin "P$360") (pinfunction "P$1_P$360") (pintype "power_in"))
      (node (ref "P6") (pin "P$361") (pinfunction "P$1_P$361") (pintype "power_in"))
      (node (ref "P6") (pin "P$362") (pinfunction "P$1_P$362") (pintype "power_in"))
      (node (ref "P6") (pin "P$363") (pinfunction "P$1_P$363") (pintype "power_in"))
      (node (ref "P6") (pin "P$364") (pinfunction "P$1_P$364") (pintype "power_in"))
      (node (ref "P6") (pin "P$365") (pinfunction "P$1_P$365") (pintype "power_in"))
      (node (ref "P6") (pin "P$366") (pinfunction "P$1_P$366") (pintype "power_in"))
      (node (ref "P6") (pin "P$367") (pinfunction "P$1_P$367") (pintype "power_in"))
      (node (ref "P6") (pin "P$368") (pinfunction "P$1_P$368") (pintype "power_in"))
      (node (ref "P6") (pin "P$369") (pinfunction "P$1_P$369") (pintype "power_in"))
      (node (ref "P6") (pin "P$37") (pinfunction "P$1_P$37") (pintype "power_in"))
      (node (ref "P6") (pin "P$370") (pinfunction "P$1_P$370") (pintype "power_in"))
      (node (ref "P6") (pin "P$371") (pinfunction "P$1_P$371") (pintype "power_in"))
      (node (ref "P6") (pin "P$372") (pinfunction "P$1_P$372") (pintype "power_in"))
      (node (ref "P6") (pin "P$373") (pinfunction "P$1_P$373") (pintype "power_in"))
      (node (ref "P6") (pin "P$374") (pinfunction "P$1_P$374") (pintype "power_in"))
      (node (ref "P6") (pin "P$375") (pinfunction "P$1_P$375") (pintype "power_in"))
      (node (ref "P6") (pin "P$376") (pinfunction "P$1_P$376") (pintype "power_in"))
      (node (ref "P6") (pin "P$377") (pinfunction "P$1_P$377") (pintype "power_in"))
      (node (ref "P6") (pin "P$378") (pinfunction "P$1_P$378") (pintype "power_in"))
      (node (ref "P6") (pin "P$379") (pinfunction "P$1_P$379") (pintype "power_in"))
      (node (ref "P6") (pin "P$38") (pinfunction "P$1_P$38") (pintype "power_in"))
      (node (ref "P6") (pin "P$380") (pinfunction "P$1_P$380") (pintype "power_in"))
      (node (ref "P6") (pin "P$381") (pinfunction "P$1_P$381") (pintype "power_in"))
      (node (ref "P6") (pin "P$382") (pinfunction "P$1_P$382") (pintype "power_in"))
      (node (ref "P6") (pin "P$383") (pinfunction "P$1_P$383") (pintype "power_in"))
      (node (ref "P6") (pin "P$384") (pinfunction "P$1_P$384") (pintype "power_in"))
      (node (ref "P6") (pin "P$385") (pinfunction "P$1_P$385") (pintype "power_in"))
      (node (ref "P6") (pin "P$386") (pinfunction "P$1_P$386") (pintype "power_in"))
      (node (ref "P6") (pin "P$387") (pinfunction "P$1_P$387") (pintype "power_in"))
      (node (ref "P6") (pin "P$388") (pinfunction "P$1_P$388") (pintype "power_in"))
      (node (ref "P6") (pin "P$389") (pinfunction "P$1_P$389") (pintype "power_in"))
      (node (ref "P6") (pin "P$39") (pinfunction "P$1_P$39") (pintype "power_in"))
      (node (ref "P6") (pin "P$390") (pinfunction "P$1_P$390") (pintype "power_in"))
      (node (ref "P6") (pin "P$391") (pinfunction "P$1_P$391") (pintype "power_in"))
      (node (ref "P6") (pin "P$392") (pinfunction "P$1_P$392") (pintype "power_in"))
      (node (ref "P6") (pin "P$393") (pinfunction "P$1_P$393") (pintype "power_in"))
      (node (ref "P6") (pin "P$394") (pinfunction "P$1_P$394") (pintype "power_in"))
      (node (ref "P6") (pin "P$395") (pinfunction "P$1_P$395") (pintype "power_in"))
      (node (ref "P6") (pin "P$396") (pinfunction "P$1_P$396") (pintype "power_in"))
      (node (ref "P6") (pin "P$397") (pinfunction "P$1_P$397") (pintype "power_in"))
      (node (ref "P6") (pin "P$398") (pinfunction "P$1_P$398") (pintype "power_in"))
      (node (ref "P6") (pin "P$399") (pinfunction "P$1_P$399") (pintype "power_in"))
      (node (ref "P6") (pin "P$4") (pinfunction "P$1_P$4") (pintype "power_in"))
      (node (ref "P6") (pin "P$40") (pinfunction "P$1_P$40") (pintype "power_in"))
      (node (ref "P6") (pin "P$400") (pinfunction "P$1_P$400") (pintype "power_in"))
      (node (ref "P6") (pin "P$401") (pinfunction "P$1_P$401") (pintype "power_in"))
      (node (ref "P6") (pin "P$402") (pinfunction "P$1_P$402") (pintype "power_in"))
      (node (ref "P6") (pin "P$403") (pinfunction "P$1_P$403") (pintype "power_in"))
      (node (ref "P6") (pin "P$404") (pinfunction "P$1_P$404") (pintype "power_in"))
      (node (ref "P6") (pin "P$405") (pinfunction "P$1_P$405") (pintype "power_in"))
      (node (ref "P6") (pin "P$406") (pinfunction "P$1_P$406") (pintype "power_in"))
      (node (ref "P6") (pin "P$407") (pinfunction "P$1_P$407") (pintype "power_in"))
      (node (ref "P6") (pin "P$408") (pinfunction "P$1_P$408") (pintype "power_in"))
      (node (ref "P6") (pin "P$409") (pinfunction "P$1_P$409") (pintype "power_in"))
      (node (ref "P6") (pin "P$41") (pinfunction "P$1_P$41") (pintype "power_in"))
      (node (ref "P6") (pin "P$410") (pinfunction "P$1_P$410") (pintype "power_in"))
      (node (ref "P6") (pin "P$411") (pinfunction "P$1_P$411") (pintype "power_in"))
      (node (ref "P6") (pin "P$412") (pinfunction "P$1_P$412") (pintype "power_in"))
      (node (ref "P6") (pin "P$413") (pinfunction "P$1_P$413") (pintype "power_in"))
      (node (ref "P6") (pin "P$414") (pinfunction "P$1_P$414") (pintype "power_in"))
      (node (ref "P6") (pin "P$415") (pinfunction "P$1_P$415") (pintype "power_in"))
      (node (ref "P6") (pin "P$416") (pinfunction "P$1_P$416") (pintype "power_in"))
      (node (ref "P6") (pin "P$417") (pinfunction "P$1_P$417") (pintype "power_in"))
      (node (ref "P6") (pin "P$418") (pinfunction "P$1_P$418") (pintype "power_in"))
      (node (ref "P6") (pin "P$419") (pinfunction "P$1_P$419") (pintype "power_in"))
      (node (ref "P6") (pin "P$42") (pinfunction "P$1_P$42") (pintype "power_in"))
      (node (ref "P6") (pin "P$420") (pinfunction "P$1_P$420") (pintype "power_in"))
      (node (ref "P6") (pin "P$421") (pinfunction "P$1_P$421") (pintype "power_in"))
      (node (ref "P6") (pin "P$422") (pinfunction "P$1_P$422") (pintype "power_in"))
      (node (ref "P6") (pin "P$423") (pinfunction "P$1_P$423") (pintype "power_in"))
      (node (ref "P6") (pin "P$424") (pinfunction "P$1_P$424") (pintype "power_in"))
      (node (ref "P6") (pin "P$425") (pinfunction "P$1_P$425") (pintype "power_in"))
      (node (ref "P6") (pin "P$426") (pinfunction "P$1_P$426") (pintype "power_in"))
      (node (ref "P6") (pin "P$427") (pinfunction "P$1_P$427") (pintype "power_in"))
      (node (ref "P6") (pin "P$428") (pinfunction "P$1_P$428") (pintype "power_in"))
      (node (ref "P6") (pin "P$429") (pinfunction "P$1_P$429") (pintype "power_in"))
      (node (ref "P6") (pin "P$43") (pinfunction "P$1_P$43") (pintype "power_in"))
      (node (ref "P6") (pin "P$430") (pinfunction "P$1_P$430") (pintype "power_in"))
      (node (ref "P6") (pin "P$431") (pinfunction "P$1_P$431") (pintype "power_in"))
      (node (ref "P6") (pin "P$432") (pinfunction "P$1_P$432") (pintype "power_in"))
      (node (ref "P6") (pin "P$433") (pinfunction "P$1_P$433") (pintype "power_in"))
      (node (ref "P6") (pin "P$434") (pinfunction "P$1_P$434") (pintype "power_in"))
      (node (ref "P6") (pin "P$435") (pinfunction "P$1_P$435") (pintype "power_in"))
      (node (ref "P6") (pin "P$436") (pinfunction "P$1_P$436") (pintype "power_in"))
      (node (ref "P6") (pin "P$437") (pinfunction "P$1_P$437") (pintype "power_in"))
      (node (ref "P6") (pin "P$438") (pinfunction "P$1_P$438") (pintype "power_in"))
      (node (ref "P6") (pin "P$439") (pinfunction "P$1_P$439") (pintype "power_in"))
      (node (ref "P6") (pin "P$44") (pinfunction "P$1_P$44") (pintype "power_in"))
      (node (ref "P6") (pin "P$440") (pinfunction "P$1_P$440") (pintype "power_in"))
      (node (ref "P6") (pin "P$441") (pinfunction "P$1_P$441") (pintype "power_in"))
      (node (ref "P6") (pin "P$442") (pinfunction "P$1_P$442") (pintype "power_in"))
      (node (ref "P6") (pin "P$443") (pinfunction "P$1_P$443") (pintype "power_in"))
      (node (ref "P6") (pin "P$444") (pinfunction "P$1_P$444") (pintype "power_in"))
      (node (ref "P6") (pin "P$445") (pinfunction "P$1_P$445") (pintype "power_in"))
      (node (ref "P6") (pin "P$446") (pinfunction "P$1_P$446") (pintype "power_in"))
      (node (ref "P6") (pin "P$447") (pinfunction "P$1_P$447") (pintype "power_in"))
      (node (ref "P6") (pin "P$448") (pinfunction "P$1_P$448") (pintype "power_in"))
      (node (ref "P6") (pin "P$449") (pinfunction "P$1_P$449") (pintype "power_in"))
      (node (ref "P6") (pin "P$45") (pinfunction "P$1_P$45") (pintype "power_in"))
      (node (ref "P6") (pin "P$450") (pinfunction "P$1_P$450") (pintype "power_in"))
      (node (ref "P6") (pin "P$451") (pinfunction "P$1_P$451") (pintype "power_in"))
      (node (ref "P6") (pin "P$452") (pinfunction "P$1_P$452") (pintype "power_in"))
      (node (ref "P6") (pin "P$453") (pinfunction "P$1_P$453") (pintype "power_in"))
      (node (ref "P6") (pin "P$454") (pinfunction "P$1_P$454") (pintype "power_in"))
      (node (ref "P6") (pin "P$455") (pinfunction "P$1_P$455") (pintype "power_in"))
      (node (ref "P6") (pin "P$456") (pinfunction "P$1_P$456") (pintype "power_in"))
      (node (ref "P6") (pin "P$457") (pinfunction "P$1_P$457") (pintype "power_in"))
      (node (ref "P6") (pin "P$458") (pinfunction "P$1_P$458") (pintype "power_in"))
      (node (ref "P6") (pin "P$459") (pinfunction "P$1_P$459") (pintype "power_in"))
      (node (ref "P6") (pin "P$46") (pinfunction "P$1_P$46") (pintype "power_in"))
      (node (ref "P6") (pin "P$460") (pinfunction "P$1_P$460") (pintype "power_in"))
      (node (ref "P6") (pin "P$461") (pinfunction "P$1_P$461") (pintype "power_in"))
      (node (ref "P6") (pin "P$462") (pinfunction "P$1_P$462") (pintype "power_in"))
      (node (ref "P6") (pin "P$463") (pinfunction "P$1_P$463") (pintype "power_in"))
      (node (ref "P6") (pin "P$464") (pinfunction "P$1_P$464") (pintype "power_in"))
      (node (ref "P6") (pin "P$465") (pinfunction "P$1_P$465") (pintype "power_in"))
      (node (ref "P6") (pin "P$466") (pinfunction "P$1_P$466") (pintype "power_in"))
      (node (ref "P6") (pin "P$467") (pinfunction "P$1_P$467") (pintype "power_in"))
      (node (ref "P6") (pin "P$468") (pinfunction "P$1_P$468") (pintype "power_in"))
      (node (ref "P6") (pin "P$469") (pinfunction "P$1_P$469") (pintype "power_in"))
      (node (ref "P6") (pin "P$47") (pinfunction "P$1_P$47") (pintype "power_in"))
      (node (ref "P6") (pin "P$470") (pinfunction "P$1_P$470") (pintype "power_in"))
      (node (ref "P6") (pin "P$471") (pinfunction "P$1_P$471") (pintype "power_in"))
      (node (ref "P6") (pin "P$472") (pinfunction "P$1_P$472") (pintype "power_in"))
      (node (ref "P6") (pin "P$473") (pinfunction "P$1_P$473") (pintype "power_in"))
      (node (ref "P6") (pin "P$474") (pinfunction "P$1_P$474") (pintype "power_in"))
      (node (ref "P6") (pin "P$475") (pinfunction "P$1_P$475") (pintype "power_in"))
      (node (ref "P6") (pin "P$476") (pinfunction "P$1_P$476") (pintype "power_in"))
      (node (ref "P6") (pin "P$477") (pinfunction "P$1_P$477") (pintype "power_in"))
      (node (ref "P6") (pin "P$478") (pinfunction "P$1_P$478") (pintype "power_in"))
      (node (ref "P6") (pin "P$479") (pinfunction "P$1_P$479") (pintype "power_in"))
      (node (ref "P6") (pin "P$48") (pinfunction "P$1_P$48") (pintype "power_in"))
      (node (ref "P6") (pin "P$480") (pinfunction "P$1_P$480") (pintype "power_in"))
      (node (ref "P6") (pin "P$481") (pinfunction "P$1_P$481") (pintype "power_in"))
      (node (ref "P6") (pin "P$482") (pinfunction "P$1_P$482") (pintype "power_in"))
      (node (ref "P6") (pin "P$483") (pinfunction "P$1_P$483") (pintype "power_in"))
      (node (ref "P6") (pin "P$484") (pinfunction "P$1_P$484") (pintype "power_in"))
      (node (ref "P6") (pin "P$485") (pinfunction "P$1_P$485") (pintype "power_in"))
      (node (ref "P6") (pin "P$486") (pinfunction "P$1_P$486") (pintype "power_in"))
      (node (ref "P6") (pin "P$487") (pinfunction "P$1_P$487") (pintype "power_in"))
      (node (ref "P6") (pin "P$488") (pinfunction "P$1_P$488") (pintype "power_in"))
      (node (ref "P6") (pin "P$489") (pinfunction "P$1_P$489") (pintype "power_in"))
      (node (ref "P6") (pin "P$49") (pinfunction "P$1_P$49") (pintype "power_in"))
      (node (ref "P6") (pin "P$490") (pinfunction "P$1_P$490") (pintype "power_in"))
      (node (ref "P6") (pin "P$491") (pinfunction "P$1_P$491") (pintype "power_in"))
      (node (ref "P6") (pin "P$492") (pinfunction "P$1_P$492") (pintype "power_in"))
      (node (ref "P6") (pin "P$493") (pinfunction "P$1_P$493") (pintype "power_in"))
      (node (ref "P6") (pin "P$494") (pinfunction "P$1_P$494") (pintype "power_in"))
      (node (ref "P6") (pin "P$495") (pinfunction "P$1_P$495") (pintype "power_in"))
      (node (ref "P6") (pin "P$496") (pinfunction "P$1_P$496") (pintype "power_in"))
      (node (ref "P6") (pin "P$497") (pinfunction "P$1_P$497") (pintype "power_in"))
      (node (ref "P6") (pin "P$498") (pinfunction "P$1_P$498") (pintype "power_in"))
      (node (ref "P6") (pin "P$499") (pinfunction "P$1_P$499") (pintype "power_in"))
      (node (ref "P6") (pin "P$5") (pinfunction "P$1_P$5") (pintype "power_in"))
      (node (ref "P6") (pin "P$50") (pinfunction "P$1_P$50") (pintype "power_in"))
      (node (ref "P6") (pin "P$500") (pinfunction "P$1_P$500") (pintype "power_in"))
      (node (ref "P6") (pin "P$501") (pinfunction "P$1_P$501") (pintype "power_in"))
      (node (ref "P6") (pin "P$502") (pinfunction "P$1_P$502") (pintype "power_in"))
      (node (ref "P6") (pin "P$503") (pinfunction "P$1_P$503") (pintype "power_in"))
      (node (ref "P6") (pin "P$504") (pinfunction "P$1_P$504") (pintype "power_in"))
      (node (ref "P6") (pin "P$505") (pinfunction "P$1_P$505") (pintype "power_in"))
      (node (ref "P6") (pin "P$506") (pinfunction "P$1_P$506") (pintype "power_in"))
      (node (ref "P6") (pin "P$507") (pinfunction "P$1_P$507") (pintype "power_in"))
      (node (ref "P6") (pin "P$508") (pinfunction "P$1_P$508") (pintype "power_in"))
      (node (ref "P6") (pin "P$509") (pinfunction "P$1_P$509") (pintype "power_in"))
      (node (ref "P6") (pin "P$51") (pinfunction "P$1_P$51") (pintype "power_in"))
      (node (ref "P6") (pin "P$510") (pinfunction "P$1_P$510") (pintype "power_in"))
      (node (ref "P6") (pin "P$511") (pinfunction "P$1_P$511") (pintype "power_in"))
      (node (ref "P6") (pin "P$512") (pinfunction "P$1_P$512") (pintype "power_in"))
      (node (ref "P6") (pin "P$513") (pinfunction "P$1_P$513") (pintype "power_in"))
      (node (ref "P6") (pin "P$514") (pinfunction "P$1_P$514") (pintype "power_in"))
      (node (ref "P6") (pin "P$515") (pinfunction "P$1_P$515") (pintype "power_in"))
      (node (ref "P6") (pin "P$516") (pinfunction "P$1_P$516") (pintype "power_in"))
      (node (ref "P6") (pin "P$517") (pinfunction "P$1_P$517") (pintype "power_in"))
      (node (ref "P6") (pin "P$518") (pinfunction "P$1_P$518") (pintype "power_in"))
      (node (ref "P6") (pin "P$519") (pinfunction "P$1_P$519") (pintype "power_in"))
      (node (ref "P6") (pin "P$52") (pinfunction "P$1_P$52") (pintype "power_in"))
      (node (ref "P6") (pin "P$520") (pinfunction "P$1_P$520") (pintype "power_in"))
      (node (ref "P6") (pin "P$521") (pinfunction "P$1_P$521") (pintype "power_in"))
      (node (ref "P6") (pin "P$522") (pinfunction "P$1_P$522") (pintype "power_in"))
      (node (ref "P6") (pin "P$523") (pinfunction "P$1_P$523") (pintype "power_in"))
      (node (ref "P6") (pin "P$524") (pinfunction "P$1_P$524") (pintype "power_in"))
      (node (ref "P6") (pin "P$525") (pinfunction "P$1_P$525") (pintype "power_in"))
      (node (ref "P6") (pin "P$526") (pinfunction "P$1_P$526") (pintype "power_in"))
      (node (ref "P6") (pin "P$527") (pinfunction "P$1_P$527") (pintype "power_in"))
      (node (ref "P6") (pin "P$528") (pinfunction "P$1_P$528") (pintype "power_in"))
      (node (ref "P6") (pin "P$529") (pinfunction "P$1_P$529") (pintype "power_in"))
      (node (ref "P6") (pin "P$53") (pinfunction "P$1_P$53") (pintype "power_in"))
      (node (ref "P6") (pin "P$530") (pinfunction "P$1_P$530") (pintype "power_in"))
      (node (ref "P6") (pin "P$531") (pinfunction "P$1_P$531") (pintype "power_in"))
      (node (ref "P6") (pin "P$532") (pinfunction "P$1_P$532") (pintype "power_in"))
      (node (ref "P6") (pin "P$533") (pinfunction "P$1_P$533") (pintype "power_in"))
      (node (ref "P6") (pin "P$534") (pinfunction "P$1_P$534") (pintype "power_in"))
      (node (ref "P6") (pin "P$535") (pinfunction "P$1_P$535") (pintype "power_in"))
      (node (ref "P6") (pin "P$536") (pinfunction "P$1_P$536") (pintype "power_in"))
      (node (ref "P6") (pin "P$537") (pinfunction "P$1_P$537") (pintype "power_in"))
      (node (ref "P6") (pin "P$538") (pinfunction "P$1_P$538") (pintype "power_in"))
      (node (ref "P6") (pin "P$539") (pinfunction "P$1_P$539") (pintype "power_in"))
      (node (ref "P6") (pin "P$54") (pinfunction "P$1_P$54") (pintype "power_in"))
      (node (ref "P6") (pin "P$540") (pinfunction "P$1_P$540") (pintype "power_in"))
      (node (ref "P6") (pin "P$541") (pinfunction "P$1_P$541") (pintype "power_in"))
      (node (ref "P6") (pin "P$542") (pinfunction "P$1_P$542") (pintype "power_in"))
      (node (ref "P6") (pin "P$543") (pinfunction "P$1_P$543") (pintype "power_in"))
      (node (ref "P6") (pin "P$544") (pinfunction "P$1_P$544") (pintype "power_in"))
      (node (ref "P6") (pin "P$545") (pinfunction "P$1_P$545") (pintype "power_in"))
      (node (ref "P6") (pin "P$546") (pinfunction "P$1_P$546") (pintype "power_in"))
      (node (ref "P6") (pin "P$547") (pinfunction "P$1_P$547") (pintype "power_in"))
      (node (ref "P6") (pin "P$548") (pinfunction "P$1_P$548") (pintype "power_in"))
      (node (ref "P6") (pin "P$549") (pinfunction "P$1_P$549") (pintype "power_in"))
      (node (ref "P6") (pin "P$55") (pinfunction "P$1_P$55") (pintype "power_in"))
      (node (ref "P6") (pin "P$550") (pinfunction "P$1_P$550") (pintype "power_in"))
      (node (ref "P6") (pin "P$551") (pinfunction "P$1_P$551") (pintype "power_in"))
      (node (ref "P6") (pin "P$552") (pinfunction "P$1_P$552") (pintype "power_in"))
      (node (ref "P6") (pin "P$553") (pinfunction "P$1_P$553") (pintype "power_in"))
      (node (ref "P6") (pin "P$554") (pinfunction "P$1_P$554") (pintype "power_in"))
      (node (ref "P6") (pin "P$555") (pinfunction "P$1_P$555") (pintype "power_in"))
      (node (ref "P6") (pin "P$556") (pinfunction "P$1_P$556") (pintype "power_in"))
      (node (ref "P6") (pin "P$557") (pinfunction "P$1_P$557") (pintype "power_in"))
      (node (ref "P6") (pin "P$558") (pinfunction "P$1_P$558") (pintype "power_in"))
      (node (ref "P6") (pin "P$559") (pinfunction "P$1_P$559") (pintype "power_in"))
      (node (ref "P6") (pin "P$56") (pinfunction "P$1_P$56") (pintype "power_in"))
      (node (ref "P6") (pin "P$560") (pinfunction "P$1_P$560") (pintype "power_in"))
      (node (ref "P6") (pin "P$561") (pinfunction "P$1_P$561") (pintype "power_in"))
      (node (ref "P6") (pin "P$562") (pinfunction "P$1_P$562") (pintype "power_in"))
      (node (ref "P6") (pin "P$563") (pinfunction "P$1_P$563") (pintype "power_in"))
      (node (ref "P6") (pin "P$564") (pinfunction "P$1_P$564") (pintype "power_in"))
      (node (ref "P6") (pin "P$565") (pinfunction "P$1_P$565") (pintype "power_in"))
      (node (ref "P6") (pin "P$566") (pinfunction "P$1_P$566") (pintype "power_in"))
      (node (ref "P6") (pin "P$567") (pinfunction "P$1_P$567") (pintype "power_in"))
      (node (ref "P6") (pin "P$568") (pinfunction "P$1_P$568") (pintype "power_in"))
      (node (ref "P6") (pin "P$569") (pinfunction "P$1_P$569") (pintype "power_in"))
      (node (ref "P6") (pin "P$57") (pinfunction "P$1_P$57") (pintype "power_in"))
      (node (ref "P6") (pin "P$570") (pinfunction "P$1_P$570") (pintype "power_in"))
      (node (ref "P6") (pin "P$571") (pinfunction "P$1_P$571") (pintype "power_in"))
      (node (ref "P6") (pin "P$572") (pinfunction "P$1_P$572") (pintype "power_in"))
      (node (ref "P6") (pin "P$573") (pinfunction "P$1_P$573") (pintype "power_in"))
      (node (ref "P6") (pin "P$574") (pinfunction "P$1_P$574") (pintype "power_in"))
      (node (ref "P6") (pin "P$575") (pinfunction "P$1_P$575") (pintype "power_in"))
      (node (ref "P6") (pin "P$576") (pinfunction "P$1_P$576") (pintype "power_in"))
      (node (ref "P6") (pin "P$577") (pinfunction "P$1_P$577") (pintype "power_in"))
      (node (ref "P6") (pin "P$578") (pinfunction "P$1_P$578") (pintype "power_in"))
      (node (ref "P6") (pin "P$579") (pinfunction "P$1_P$579") (pintype "power_in"))
      (node (ref "P6") (pin "P$58") (pinfunction "P$1_P$58") (pintype "power_in"))
      (node (ref "P6") (pin "P$580") (pinfunction "P$1_P$580") (pintype "power_in"))
      (node (ref "P6") (pin "P$581") (pinfunction "P$1_P$581") (pintype "power_in"))
      (node (ref "P6") (pin "P$582") (pinfunction "P$1_P$582") (pintype "power_in"))
      (node (ref "P6") (pin "P$583") (pinfunction "P$1_P$583") (pintype "power_in"))
      (node (ref "P6") (pin "P$584") (pinfunction "P$1_P$584") (pintype "power_in"))
      (node (ref "P6") (pin "P$585") (pinfunction "P$1_P$585") (pintype "power_in"))
      (node (ref "P6") (pin "P$586") (pinfunction "P$1_P$586") (pintype "power_in"))
      (node (ref "P6") (pin "P$587") (pinfunction "P$1_P$587") (pintype "power_in"))
      (node (ref "P6") (pin "P$588") (pinfunction "P$1_P$588") (pintype "power_in"))
      (node (ref "P6") (pin "P$589") (pinfunction "P$1_P$589") (pintype "power_in"))
      (node (ref "P6") (pin "P$59") (pinfunction "P$1_P$59") (pintype "power_in"))
      (node (ref "P6") (pin "P$590") (pinfunction "P$1_P$590") (pintype "power_in"))
      (node (ref "P6") (pin "P$591") (pinfunction "P$1_P$591") (pintype "power_in"))
      (node (ref "P6") (pin "P$592") (pinfunction "P$1_P$592") (pintype "power_in"))
      (node (ref "P6") (pin "P$593") (pinfunction "P$1_P$593") (pintype "power_in"))
      (node (ref "P6") (pin "P$594") (pinfunction "P$1_P$594") (pintype "power_in"))
      (node (ref "P6") (pin "P$595") (pinfunction "P$1_P$595") (pintype "power_in"))
      (node (ref "P6") (pin "P$596") (pinfunction "P$1_P$596") (pintype "power_in"))
      (node (ref "P6") (pin "P$597") (pinfunction "P$1_P$597") (pintype "power_in"))
      (node (ref "P6") (pin "P$598") (pinfunction "P$1_P$598") (pintype "power_in"))
      (node (ref "P6") (pin "P$599") (pinfunction "P$1_P$599") (pintype "power_in"))
      (node (ref "P6") (pin "P$6") (pinfunction "P$1_P$6") (pintype "power_in"))
      (node (ref "P6") (pin "P$60") (pinfunction "P$1_P$60") (pintype "power_in"))
      (node (ref "P6") (pin "P$600") (pinfunction "P$1_P$600") (pintype "power_in"))
      (node (ref "P6") (pin "P$601") (pinfunction "P$1_P$601") (pintype "power_in"))
      (node (ref "P6") (pin "P$602") (pinfunction "P$1_P$602") (pintype "power_in"))
      (node (ref "P6") (pin "P$603") (pinfunction "P$1_P$603") (pintype "power_in"))
      (node (ref "P6") (pin "P$604") (pinfunction "P$1_P$604") (pintype "power_in"))
      (node (ref "P6") (pin "P$605") (pinfunction "P$1_P$605") (pintype "power_in"))
      (node (ref "P6") (pin "P$606") (pinfunction "P$1_P$606") (pintype "power_in"))
      (node (ref "P6") (pin "P$607") (pinfunction "P$1_P$607") (pintype "power_in"))
      (node (ref "P6") (pin "P$608") (pinfunction "P$1_P$608") (pintype "power_in"))
      (node (ref "P6") (pin "P$609") (pinfunction "P$1_P$609") (pintype "power_in"))
      (node (ref "P6") (pin "P$61") (pinfunction "P$1_P$61") (pintype "power_in"))
      (node (ref "P6") (pin "P$610") (pinfunction "P$1_P$610") (pintype "power_in"))
      (node (ref "P6") (pin "P$611") (pinfunction "P$1_P$611") (pintype "power_in"))
      (node (ref "P6") (pin "P$612") (pinfunction "P$1_P$612") (pintype "power_in"))
      (node (ref "P6") (pin "P$613") (pinfunction "P$1_P$613") (pintype "power_in"))
      (node (ref "P6") (pin "P$614") (pinfunction "P$1_P$614") (pintype "power_in"))
      (node (ref "P6") (pin "P$615") (pinfunction "P$1_P$615") (pintype "power_in"))
      (node (ref "P6") (pin "P$616") (pinfunction "P$1_P$616") (pintype "power_in"))
      (node (ref "P6") (pin "P$617") (pinfunction "P$1_P$617") (pintype "power_in"))
      (node (ref "P6") (pin "P$618") (pinfunction "P$1_P$618") (pintype "power_in"))
      (node (ref "P6") (pin "P$619") (pinfunction "P$1_P$619") (pintype "power_in"))
      (node (ref "P6") (pin "P$62") (pinfunction "P$1_P$62") (pintype "power_in"))
      (node (ref "P6") (pin "P$620") (pinfunction "P$1_P$620") (pintype "power_in"))
      (node (ref "P6") (pin "P$621") (pinfunction "P$1_P$621") (pintype "power_in"))
      (node (ref "P6") (pin "P$622") (pinfunction "P$1_P$622") (pintype "power_in"))
      (node (ref "P6") (pin "P$623") (pinfunction "P$1_P$623") (pintype "power_in"))
      (node (ref "P6") (pin "P$624") (pinfunction "P$1_P$624") (pintype "power_in"))
      (node (ref "P6") (pin "P$625") (pinfunction "P$1_P$625") (pintype "power_in"))
      (node (ref "P6") (pin "P$626") (pinfunction "P$1_P$626") (pintype "power_in"))
      (node (ref "P6") (pin "P$627") (pinfunction "P$1_P$627") (pintype "power_in"))
      (node (ref "P6") (pin "P$628") (pinfunction "P$1_P$628") (pintype "power_in"))
      (node (ref "P6") (pin "P$629") (pinfunction "P$1_P$629") (pintype "power_in"))
      (node (ref "P6") (pin "P$63") (pinfunction "P$1_P$63") (pintype "power_in"))
      (node (ref "P6") (pin "P$630") (pinfunction "P$1_P$630") (pintype "power_in"))
      (node (ref "P6") (pin "P$631") (pinfunction "P$1_P$631") (pintype "power_in"))
      (node (ref "P6") (pin "P$632") (pinfunction "P$1_P$632") (pintype "power_in"))
      (node (ref "P6") (pin "P$633") (pinfunction "P$1_P$633") (pintype "power_in"))
      (node (ref "P6") (pin "P$634") (pinfunction "P$1_P$634") (pintype "power_in"))
      (node (ref "P6") (pin "P$635") (pinfunction "P$1_P$635") (pintype "power_in"))
      (node (ref "P6") (pin "P$636") (pinfunction "P$1_P$636") (pintype "power_in"))
      (node (ref "P6") (pin "P$637") (pinfunction "P$1_P$637") (pintype "power_in"))
      (node (ref "P6") (pin "P$638") (pinfunction "P$1_P$638") (pintype "power_in"))
      (node (ref "P6") (pin "P$639") (pinfunction "P$1_P$639") (pintype "power_in"))
      (node (ref "P6") (pin "P$64") (pinfunction "P$1_P$64") (pintype "power_in"))
      (node (ref "P6") (pin "P$640") (pinfunction "P$1_P$640") (pintype "power_in"))
      (node (ref "P6") (pin "P$641") (pinfunction "P$1_P$641") (pintype "power_in"))
      (node (ref "P6") (pin "P$642") (pinfunction "P$1_P$642") (pintype "power_in"))
      (node (ref "P6") (pin "P$643") (pinfunction "P$1_P$643") (pintype "power_in"))
      (node (ref "P6") (pin "P$644") (pinfunction "P$1_P$644") (pintype "power_in"))
      (node (ref "P6") (pin "P$645") (pinfunction "P$1_P$645") (pintype "power_in"))
      (node (ref "P6") (pin "P$646") (pinfunction "P$1_P$646") (pintype "power_in"))
      (node (ref "P6") (pin "P$647") (pinfunction "P$1_P$647") (pintype "power_in"))
      (node (ref "P6") (pin "P$648") (pinfunction "P$1_P$648") (pintype "power_in"))
      (node (ref "P6") (pin "P$649") (pinfunction "P$1_P$649") (pintype "power_in"))
      (node (ref "P6") (pin "P$65") (pinfunction "P$1_P$65") (pintype "power_in"))
      (node (ref "P6") (pin "P$650") (pinfunction "P$1_P$650") (pintype "power_in"))
      (node (ref "P6") (pin "P$651") (pinfunction "P$1_P$651") (pintype "power_in"))
      (node (ref "P6") (pin "P$652") (pinfunction "P$1_P$652") (pintype "power_in"))
      (node (ref "P6") (pin "P$653") (pinfunction "P$1_P$653") (pintype "power_in"))
      (node (ref "P6") (pin "P$654") (pinfunction "P$1_P$654") (pintype "power_in"))
      (node (ref "P6") (pin "P$655") (pinfunction "P$1_P$655") (pintype "power_in"))
      (node (ref "P6") (pin "P$656") (pinfunction "P$1_P$656") (pintype "power_in"))
      (node (ref "P6") (pin "P$657") (pinfunction "P$1_P$657") (pintype "power_in"))
      (node (ref "P6") (pin "P$658") (pinfunction "P$1_P$658") (pintype "power_in"))
      (node (ref "P6") (pin "P$659") (pinfunction "P$1_P$659") (pintype "power_in"))
      (node (ref "P6") (pin "P$66") (pinfunction "P$1_P$66") (pintype "power_in"))
      (node (ref "P6") (pin "P$660") (pinfunction "P$1_P$660") (pintype "power_in"))
      (node (ref "P6") (pin "P$661") (pinfunction "P$1_P$661") (pintype "power_in"))
      (node (ref "P6") (pin "P$662") (pinfunction "P$1_P$662") (pintype "power_in"))
      (node (ref "P6") (pin "P$663") (pinfunction "P$1_P$663") (pintype "power_in"))
      (node (ref "P6") (pin "P$664") (pinfunction "P$1_P$664") (pintype "power_in"))
      (node (ref "P6") (pin "P$665") (pinfunction "P$1_P$665") (pintype "power_in"))
      (node (ref "P6") (pin "P$666") (pinfunction "P$1_P$666") (pintype "power_in"))
      (node (ref "P6") (pin "P$667") (pinfunction "P$1_P$667") (pintype "power_in"))
      (node (ref "P6") (pin "P$668") (pinfunction "P$1_P$668") (pintype "power_in"))
      (node (ref "P6") (pin "P$669") (pinfunction "P$1_P$669") (pintype "power_in"))
      (node (ref "P6") (pin "P$67") (pinfunction "P$1_P$67") (pintype "power_in"))
      (node (ref "P6") (pin "P$670") (pinfunction "P$1_P$670") (pintype "power_in"))
      (node (ref "P6") (pin "P$671") (pinfunction "P$1_P$671") (pintype "power_in"))
      (node (ref "P6") (pin "P$672") (pinfunction "P$1_P$672") (pintype "power_in"))
      (node (ref "P6") (pin "P$673") (pinfunction "P$1_P$673") (pintype "power_in"))
      (node (ref "P6") (pin "P$674") (pinfunction "P$1_P$674") (pintype "power_in"))
      (node (ref "P6") (pin "P$675") (pinfunction "P$1_P$675") (pintype "power_in"))
      (node (ref "P6") (pin "P$676") (pinfunction "P$1_P$676") (pintype "power_in"))
      (node (ref "P6") (pin "P$677") (pinfunction "P$1_P$677") (pintype "power_in"))
      (node (ref "P6") (pin "P$678") (pinfunction "P$1_P$678") (pintype "power_in"))
      (node (ref "P6") (pin "P$679") (pinfunction "P$1_P$679") (pintype "power_in"))
      (node (ref "P6") (pin "P$68") (pinfunction "P$1_P$68") (pintype "power_in"))
      (node (ref "P6") (pin "P$680") (pinfunction "P$1_P$680") (pintype "power_in"))
      (node (ref "P6") (pin "P$681") (pinfunction "P$1_P$681") (pintype "power_in"))
      (node (ref "P6") (pin "P$682") (pinfunction "P$1_P$682") (pintype "power_in"))
      (node (ref "P6") (pin "P$683") (pinfunction "P$1_P$683") (pintype "power_in"))
      (node (ref "P6") (pin "P$684") (pinfunction "P$1_P$684") (pintype "power_in"))
      (node (ref "P6") (pin "P$685") (pinfunction "P$1_P$685") (pintype "power_in"))
      (node (ref "P6") (pin "P$686") (pinfunction "P$1_P$686") (pintype "power_in"))
      (node (ref "P6") (pin "P$687") (pinfunction "P$1_P$687") (pintype "power_in"))
      (node (ref "P6") (pin "P$688") (pinfunction "P$1_P$688") (pintype "power_in"))
      (node (ref "P6") (pin "P$689") (pinfunction "P$1_P$689") (pintype "power_in"))
      (node (ref "P6") (pin "P$69") (pinfunction "P$1_P$69") (pintype "power_in"))
      (node (ref "P6") (pin "P$690") (pinfunction "P$1_P$690") (pintype "power_in"))
      (node (ref "P6") (pin "P$691") (pinfunction "P$1_P$691") (pintype "power_in"))
      (node (ref "P6") (pin "P$692") (pinfunction "P$1_P$692") (pintype "power_in"))
      (node (ref "P6") (pin "P$693") (pinfunction "P$1_P$693") (pintype "power_in"))
      (node (ref "P6") (pin "P$694") (pinfunction "P$1_P$694") (pintype "power_in"))
      (node (ref "P6") (pin "P$695") (pinfunction "P$1_P$695") (pintype "power_in"))
      (node (ref "P6") (pin "P$696") (pinfunction "P$1_P$696") (pintype "power_in"))
      (node (ref "P6") (pin "P$697") (pinfunction "P$1_P$697") (pintype "power_in"))
      (node (ref "P6") (pin "P$698") (pinfunction "P$1_P$698") (pintype "power_in"))
      (node (ref "P6") (pin "P$699") (pinfunction "P$1_P$699") (pintype "power_in"))
      (node (ref "P6") (pin "P$7") (pinfunction "P$1_P$7") (pintype "power_in"))
      (node (ref "P6") (pin "P$70") (pinfunction "P$1_P$70") (pintype "power_in"))
      (node (ref "P6") (pin "P$700") (pinfunction "P$1_P$700") (pintype "power_in"))
      (node (ref "P6") (pin "P$701") (pinfunction "P$1_P$701") (pintype "power_in"))
      (node (ref "P6") (pin "P$702") (pinfunction "P$1_P$702") (pintype "power_in"))
      (node (ref "P6") (pin "P$703") (pinfunction "P$1_P$703") (pintype "power_in"))
      (node (ref "P6") (pin "P$704") (pinfunction "P$1_P$704") (pintype "power_in"))
      (node (ref "P6") (pin "P$705") (pinfunction "P$1_P$705") (pintype "power_in"))
      (node (ref "P6") (pin "P$706") (pinfunction "P$1_P$706") (pintype "power_in"))
      (node (ref "P6") (pin "P$707") (pinfunction "P$1_P$707") (pintype "power_in"))
      (node (ref "P6") (pin "P$708") (pinfunction "P$1_P$708") (pintype "power_in"))
      (node (ref "P6") (pin "P$709") (pinfunction "P$1_P$709") (pintype "power_in"))
      (node (ref "P6") (pin "P$71") (pinfunction "P$1_P$71") (pintype "power_in"))
      (node (ref "P6") (pin "P$710") (pinfunction "P$1_P$710") (pintype "power_in"))
      (node (ref "P6") (pin "P$711") (pinfunction "P$1_P$711") (pintype "power_in"))
      (node (ref "P6") (pin "P$712") (pinfunction "P$1_P$712") (pintype "power_in"))
      (node (ref "P6") (pin "P$713") (pinfunction "P$1_P$713") (pintype "power_in"))
      (node (ref "P6") (pin "P$714") (pinfunction "P$1_P$714") (pintype "power_in"))
      (node (ref "P6") (pin "P$715") (pinfunction "P$1_P$715") (pintype "power_in"))
      (node (ref "P6") (pin "P$716") (pinfunction "P$1_P$716") (pintype "power_in"))
      (node (ref "P6") (pin "P$717") (pinfunction "P$1_P$717") (pintype "power_in"))
      (node (ref "P6") (pin "P$718") (pinfunction "P$1_P$718") (pintype "power_in"))
      (node (ref "P6") (pin "P$719") (pinfunction "P$1_P$719") (pintype "power_in"))
      (node (ref "P6") (pin "P$72") (pinfunction "P$1_P$72") (pintype "power_in"))
      (node (ref "P6") (pin "P$720") (pinfunction "P$1_P$720") (pintype "power_in"))
      (node (ref "P6") (pin "P$73") (pinfunction "P$1_P$73") (pintype "power_in"))
      (node (ref "P6") (pin "P$74") (pinfunction "P$1_P$74") (pintype "power_in"))
      (node (ref "P6") (pin "P$75") (pinfunction "P$1_P$75") (pintype "power_in"))
      (node (ref "P6") (pin "P$76") (pinfunction "P$1_P$76") (pintype "power_in"))
      (node (ref "P6") (pin "P$77") (pinfunction "P$1_P$77") (pintype "power_in"))
      (node (ref "P6") (pin "P$78") (pinfunction "P$1_P$78") (pintype "power_in"))
      (node (ref "P6") (pin "P$79") (pinfunction "P$1_P$79") (pintype "power_in"))
      (node (ref "P6") (pin "P$8") (pinfunction "P$1_P$8") (pintype "power_in"))
      (node (ref "P6") (pin "P$80") (pinfunction "P$1_P$80") (pintype "power_in"))
      (node (ref "P6") (pin "P$81") (pinfunction "P$1_P$81") (pintype "power_in"))
      (node (ref "P6") (pin "P$82") (pinfunction "P$1_P$82") (pintype "power_in"))
      (node (ref "P6") (pin "P$83") (pinfunction "P$1_P$83") (pintype "power_in"))
      (node (ref "P6") (pin "P$84") (pinfunction "P$1_P$84") (pintype "power_in"))
      (node (ref "P6") (pin "P$85") (pinfunction "P$1_P$85") (pintype "power_in"))
      (node (ref "P6") (pin "P$86") (pinfunction "P$1_P$86") (pintype "power_in"))
      (node (ref "P6") (pin "P$87") (pinfunction "P$1_P$87") (pintype "power_in"))
      (node (ref "P6") (pin "P$88") (pinfunction "P$1_P$88") (pintype "power_in"))
      (node (ref "P6") (pin "P$89") (pinfunction "P$1_P$89") (pintype "power_in"))
      (node (ref "P6") (pin "P$9") (pinfunction "P$1_P$9") (pintype "power_in"))
      (node (ref "P6") (pin "P$90") (pinfunction "P$1_P$90") (pintype "power_in"))
      (node (ref "P6") (pin "P$91") (pinfunction "P$1_P$91") (pintype "power_in"))
      (node (ref "P6") (pin "P$92") (pinfunction "P$1_P$92") (pintype "power_in"))
      (node (ref "P6") (pin "P$93") (pinfunction "P$1_P$93") (pintype "power_in"))
      (node (ref "P6") (pin "P$94") (pinfunction "P$1_P$94") (pintype "power_in"))
      (node (ref "P6") (pin "P$95") (pinfunction "P$1_P$95") (pintype "power_in"))
      (node (ref "P6") (pin "P$96") (pinfunction "P$1_P$96") (pintype "power_in"))
      (node (ref "P6") (pin "P$97") (pinfunction "P$1_P$97") (pintype "power_in"))
      (node (ref "P6") (pin "P$98") (pinfunction "P$1_P$98") (pintype "power_in"))
      (node (ref "P6") (pin "P$99") (pinfunction "P$1_P$99") (pintype "power_in"))
    )
    (net (code "8") (name "/P7") (class "Default")
      (node (ref "JP1") (pin "P$8") (pinfunction "7_P$8") (pintype "bidirectional"))
      (node (ref "P7") (pin "P$1") (pinfunction "P$1_P$1") (pintype "power_in"))
      (node (ref "P7") (pin "P$10") (pinfunction "P$1_P$10") (pintype "power_in"))
      (node (ref "P7") (pin "P$100") (pinfunction "P$1_P$100") (pintype "power_in"))
      (node (ref "P7") (pin "P$101") (pinfunction "P$1_P$101") (pintype "power_in"))
      (node (ref "P7") (pin "P$102") (pinfunction "P$1_P$102") (pintype "power_in"))
      (node (ref "P7") (pin "P$103") (pinfunction "P$1_P$103") (pintype "power_in"))
      (node (ref "P7") (pin "P$104") (pinfunction "P$1_P$104") (pintype "power_in"))
      (node (ref "P7") (pin "P$105") (pinfunction "P$1_P$105") (pintype "power_in"))
      (node (ref "P7") (pin "P$106") (pinfunction "P$1_P$106") (pintype "power_in"))
      (node (ref "P7") (pin "P$107") (pinfunction "P$1_P$107") (pintype "power_in"))
      (node (ref "P7") (pin "P$108") (pinfunction "P$1_P$108") (pintype "power_in"))
      (node (ref "P7") (pin "P$109") (pinfunction "P$1_P$109") (pintype "power_in"))
      (node (ref "P7") (pin "P$11") (pinfunction "P$1_P$11") (pintype "power_in"))
      (node (ref "P7") (pin "P$110") (pinfunction "P$1_P$110") (pintype "power_in"))
      (node (ref "P7") (pin "P$111") (pinfunction "P$1_P$111") (pintype "power_in"))
      (node (ref "P7") (pin "P$112") (pinfunction "P$1_P$112") (pintype "power_in"))
      (node (ref "P7") (pin "P$113") (pinfunction "P$1_P$113") (pintype "power_in"))
      (node (ref "P7") (pin "P$114") (pinfunction "P$1_P$114") (pintype "power_in"))
      (node (ref "P7") (pin "P$115") (pinfunction "P$1_P$115") (pintype "power_in"))
      (node (ref "P7") (pin "P$116") (pinfunction "P$1_P$116") (pintype "power_in"))
      (node (ref "P7") (pin "P$117") (pinfunction "P$1_P$117") (pintype "power_in"))
      (node (ref "P7") (pin "P$118") (pinfunction "P$1_P$118") (pintype "power_in"))
      (node (ref "P7") (pin "P$119") (pinfunction "P$1_P$119") (pintype "power_in"))
      (node (ref "P7") (pin "P$12") (pinfunction "P$1_P$12") (pintype "power_in"))
      (node (ref "P7") (pin "P$120") (pinfunction "P$1_P$120") (pintype "power_in"))
      (node (ref "P7") (pin "P$121") (pinfunction "P$1_P$121") (pintype "power_in"))
      (node (ref "P7") (pin "P$122") (pinfunction "P$1_P$122") (pintype "power_in"))
      (node (ref "P7") (pin "P$123") (pinfunction "P$1_P$123") (pintype "power_in"))
      (node (ref "P7") (pin "P$124") (pinfunction "P$1_P$124") (pintype "power_in"))
      (node (ref "P7") (pin "P$125") (pinfunction "P$1_P$125") (pintype "power_in"))
      (node (ref "P7") (pin "P$126") (pinfunction "P$1_P$126") (pintype "power_in"))
      (node (ref "P7") (pin "P$127") (pinfunction "P$1_P$127") (pintype "power_in"))
      (node (ref "P7") (pin "P$128") (pinfunction "P$1_P$128") (pintype "power_in"))
      (node (ref "P7") (pin "P$129") (pinfunction "P$1_P$129") (pintype "power_in"))
      (node (ref "P7") (pin "P$13") (pinfunction "P$1_P$13") (pintype "power_in"))
      (node (ref "P7") (pin "P$130") (pinfunction "P$1_P$130") (pintype "power_in"))
      (node (ref "P7") (pin "P$131") (pinfunction "P$1_P$131") (pintype "power_in"))
      (node (ref "P7") (pin "P$132") (pinfunction "P$1_P$132") (pintype "power_in"))
      (node (ref "P7") (pin "P$133") (pinfunction "P$1_P$133") (pintype "power_in"))
      (node (ref "P7") (pin "P$134") (pinfunction "P$1_P$134") (pintype "power_in"))
      (node (ref "P7") (pin "P$135") (pinfunction "P$1_P$135") (pintype "power_in"))
      (node (ref "P7") (pin "P$136") (pinfunction "P$1_P$136") (pintype "power_in"))
      (node (ref "P7") (pin "P$137") (pinfunction "P$1_P$137") (pintype "power_in"))
      (node (ref "P7") (pin "P$138") (pinfunction "P$1_P$138") (pintype "power_in"))
      (node (ref "P7") (pin "P$139") (pinfunction "P$1_P$139") (pintype "power_in"))
      (node (ref "P7") (pin "P$14") (pinfunction "P$1_P$14") (pintype "power_in"))
      (node (ref "P7") (pin "P$140") (pinfunction "P$1_P$140") (pintype "power_in"))
      (node (ref "P7") (pin "P$141") (pinfunction "P$1_P$141") (pintype "power_in"))
      (node (ref "P7") (pin "P$142") (pinfunction "P$1_P$142") (pintype "power_in"))
      (node (ref "P7") (pin "P$143") (pinfunction "P$1_P$143") (pintype "power_in"))
      (node (ref "P7") (pin "P$144") (pinfunction "P$1_P$144") (pintype "power_in"))
      (node (ref "P7") (pin "P$145") (pinfunction "P$1_P$145") (pintype "power_in"))
      (node (ref "P7") (pin "P$146") (pinfunction "P$1_P$146") (pintype "power_in"))
      (node (ref "P7") (pin "P$147") (pinfunction "P$1_P$147") (pintype "power_in"))
      (node (ref "P7") (pin "P$148") (pinfunction "P$1_P$148") (pintype "power_in"))
      (node (ref "P7") (pin "P$149") (pinfunction "P$1_P$149") (pintype "power_in"))
      (node (ref "P7") (pin "P$15") (pinfunction "P$1_P$15") (pintype "power_in"))
      (node (ref "P7") (pin "P$150") (pinfunction "P$1_P$150") (pintype "power_in"))
      (node (ref "P7") (pin "P$151") (pinfunction "P$1_P$151") (pintype "power_in"))
      (node (ref "P7") (pin "P$152") (pinfunction "P$1_P$152") (pintype "power_in"))
      (node (ref "P7") (pin "P$153") (pinfunction "P$1_P$153") (pintype "power_in"))
      (node (ref "P7") (pin "P$154") (pinfunction "P$1_P$154") (pintype "power_in"))
      (node (ref "P7") (pin "P$155") (pinfunction "P$1_P$155") (pintype "power_in"))
      (node (ref "P7") (pin "P$156") (pinfunction "P$1_P$156") (pintype "power_in"))
      (node (ref "P7") (pin "P$157") (pinfunction "P$1_P$157") (pintype "power_in"))
      (node (ref "P7") (pin "P$158") (pinfunction "P$1_P$158") (pintype "power_in"))
      (node (ref "P7") (pin "P$159") (pinfunction "P$1_P$159") (pintype "power_in"))
      (node (ref "P7") (pin "P$16") (pinfunction "P$1_P$16") (pintype "power_in"))
      (node (ref "P7") (pin "P$160") (pinfunction "P$1_P$160") (pintype "power_in"))
      (node (ref "P7") (pin "P$161") (pinfunction "P$1_P$161") (pintype "power_in"))
      (node (ref "P7") (pin "P$162") (pinfunction "P$1_P$162") (pintype "power_in"))
      (node (ref "P7") (pin "P$163") (pinfunction "P$1_P$163") (pintype "power_in"))
      (node (ref "P7") (pin "P$164") (pinfunction "P$1_P$164") (pintype "power_in"))
      (node (ref "P7") (pin "P$165") (pinfunction "P$1_P$165") (pintype "power_in"))
      (node (ref "P7") (pin "P$166") (pinfunction "P$1_P$166") (pintype "power_in"))
      (node (ref "P7") (pin "P$167") (pinfunction "P$1_P$167") (pintype "power_in"))
      (node (ref "P7") (pin "P$168") (pinfunction "P$1_P$168") (pintype "power_in"))
      (node (ref "P7") (pin "P$169") (pinfunction "P$1_P$169") (pintype "power_in"))
      (node (ref "P7") (pin "P$17") (pinfunction "P$1_P$17") (pintype "power_in"))
      (node (ref "P7") (pin "P$170") (pinfunction "P$1_P$170") (pintype "power_in"))
      (node (ref "P7") (pin "P$171") (pinfunction "P$1_P$171") (pintype "power_in"))
      (node (ref "P7") (pin "P$172") (pinfunction "P$1_P$172") (pintype "power_in"))
      (node (ref "P7") (pin "P$173") (pinfunction "P$1_P$173") (pintype "power_in"))
      (node (ref "P7") (pin "P$174") (pinfunction "P$1_P$174") (pintype "power_in"))
      (node (ref "P7") (pin "P$175") (pinfunction "P$1_P$175") (pintype "power_in"))
      (node (ref "P7") (pin "P$176") (pinfunction "P$1_P$176") (pintype "power_in"))
      (node (ref "P7") (pin "P$177") (pinfunction "P$1_P$177") (pintype "power_in"))
      (node (ref "P7") (pin "P$178") (pinfunction "P$1_P$178") (pintype "power_in"))
      (node (ref "P7") (pin "P$179") (pinfunction "P$1_P$179") (pintype "power_in"))
      (node (ref "P7") (pin "P$18") (pinfunction "P$1_P$18") (pintype "power_in"))
      (node (ref "P7") (pin "P$180") (pinfunction "P$1_P$180") (pintype "power_in"))
      (node (ref "P7") (pin "P$181") (pinfunction "P$1_P$181") (pintype "power_in"))
      (node (ref "P7") (pin "P$182") (pinfunction "P$1_P$182") (pintype "power_in"))
      (node (ref "P7") (pin "P$183") (pinfunction "P$1_P$183") (pintype "power_in"))
      (node (ref "P7") (pin "P$184") (pinfunction "P$1_P$184") (pintype "power_in"))
      (node (ref "P7") (pin "P$185") (pinfunction "P$1_P$185") (pintype "power_in"))
      (node (ref "P7") (pin "P$186") (pinfunction "P$1_P$186") (pintype "power_in"))
      (node (ref "P7") (pin "P$187") (pinfunction "P$1_P$187") (pintype "power_in"))
      (node (ref "P7") (pin "P$188") (pinfunction "P$1_P$188") (pintype "power_in"))
      (node (ref "P7") (pin "P$189") (pinfunction "P$1_P$189") (pintype "power_in"))
      (node (ref "P7") (pin "P$19") (pinfunction "P$1_P$19") (pintype "power_in"))
      (node (ref "P7") (pin "P$190") (pinfunction "P$1_P$190") (pintype "power_in"))
      (node (ref "P7") (pin "P$191") (pinfunction "P$1_P$191") (pintype "power_in"))
      (node (ref "P7") (pin "P$192") (pinfunction "P$1_P$192") (pintype "power_in"))
      (node (ref "P7") (pin "P$193") (pinfunction "P$1_P$193") (pintype "power_in"))
      (node (ref "P7") (pin "P$194") (pinfunction "P$1_P$194") (pintype "power_in"))
      (node (ref "P7") (pin "P$195") (pinfunction "P$1_P$195") (pintype "power_in"))
      (node (ref "P7") (pin "P$196") (pinfunction "P$1_P$196") (pintype "power_in"))
      (node (ref "P7") (pin "P$197") (pinfunction "P$1_P$197") (pintype "power_in"))
      (node (ref "P7") (pin "P$198") (pinfunction "P$1_P$198") (pintype "power_in"))
      (node (ref "P7") (pin "P$199") (pinfunction "P$1_P$199") (pintype "power_in"))
      (node (ref "P7") (pin "P$2") (pinfunction "P$1_P$2") (pintype "power_in"))
      (node (ref "P7") (pin "P$20") (pinfunction "P$1_P$20") (pintype "power_in"))
      (node (ref "P7") (pin "P$200") (pinfunction "P$1_P$200") (pintype "power_in"))
      (node (ref "P7") (pin "P$201") (pinfunction "P$1_P$201") (pintype "power_in"))
      (node (ref "P7") (pin "P$202") (pinfunction "P$1_P$202") (pintype "power_in"))
      (node (ref "P7") (pin "P$203") (pinfunction "P$1_P$203") (pintype "power_in"))
      (node (ref "P7") (pin "P$204") (pinfunction "P$1_P$204") (pintype "power_in"))
      (node (ref "P7") (pin "P$205") (pinfunction "P$1_P$205") (pintype "power_in"))
      (node (ref "P7") (pin "P$206") (pinfunction "P$1_P$206") (pintype "power_in"))
      (node (ref "P7") (pin "P$207") (pinfunction "P$1_P$207") (pintype "power_in"))
      (node (ref "P7") (pin "P$208") (pinfunction "P$1_P$208") (pintype "power_in"))
      (node (ref "P7") (pin "P$209") (pinfunction "P$1_P$209") (pintype "power_in"))
      (node (ref "P7") (pin "P$21") (pinfunction "P$1_P$21") (pintype "power_in"))
      (node (ref "P7") (pin "P$210") (pinfunction "P$1_P$210") (pintype "power_in"))
      (node (ref "P7") (pin "P$211") (pinfunction "P$1_P$211") (pintype "power_in"))
      (node (ref "P7") (pin "P$212") (pinfunction "P$1_P$212") (pintype "power_in"))
      (node (ref "P7") (pin "P$213") (pinfunction "P$1_P$213") (pintype "power_in"))
      (node (ref "P7") (pin "P$214") (pinfunction "P$1_P$214") (pintype "power_in"))
      (node (ref "P7") (pin "P$215") (pinfunction "P$1_P$215") (pintype "power_in"))
      (node (ref "P7") (pin "P$216") (pinfunction "P$1_P$216") (pintype "power_in"))
      (node (ref "P7") (pin "P$217") (pinfunction "P$1_P$217") (pintype "power_in"))
      (node (ref "P7") (pin "P$218") (pinfunction "P$1_P$218") (pintype "power_in"))
      (node (ref "P7") (pin "P$219") (pinfunction "P$1_P$219") (pintype "power_in"))
      (node (ref "P7") (pin "P$22") (pinfunction "P$1_P$22") (pintype "power_in"))
      (node (ref "P7") (pin "P$220") (pinfunction "P$1_P$220") (pintype "power_in"))
      (node (ref "P7") (pin "P$221") (pinfunction "P$1_P$221") (pintype "power_in"))
      (node (ref "P7") (pin "P$222") (pinfunction "P$1_P$222") (pintype "power_in"))
      (node (ref "P7") (pin "P$223") (pinfunction "P$1_P$223") (pintype "power_in"))
      (node (ref "P7") (pin "P$224") (pinfunction "P$1_P$224") (pintype "power_in"))
      (node (ref "P7") (pin "P$225") (pinfunction "P$1_P$225") (pintype "power_in"))
      (node (ref "P7") (pin "P$226") (pinfunction "P$1_P$226") (pintype "power_in"))
      (node (ref "P7") (pin "P$227") (pinfunction "P$1_P$227") (pintype "power_in"))
      (node (ref "P7") (pin "P$228") (pinfunction "P$1_P$228") (pintype "power_in"))
      (node (ref "P7") (pin "P$229") (pinfunction "P$1_P$229") (pintype "power_in"))
      (node (ref "P7") (pin "P$23") (pinfunction "P$1_P$23") (pintype "power_in"))
      (node (ref "P7") (pin "P$230") (pinfunction "P$1_P$230") (pintype "power_in"))
      (node (ref "P7") (pin "P$231") (pinfunction "P$1_P$231") (pintype "power_in"))
      (node (ref "P7") (pin "P$232") (pinfunction "P$1_P$232") (pintype "power_in"))
      (node (ref "P7") (pin "P$233") (pinfunction "P$1_P$233") (pintype "power_in"))
      (node (ref "P7") (pin "P$234") (pinfunction "P$1_P$234") (pintype "power_in"))
      (node (ref "P7") (pin "P$235") (pinfunction "P$1_P$235") (pintype "power_in"))
      (node (ref "P7") (pin "P$236") (pinfunction "P$1_P$236") (pintype "power_in"))
      (node (ref "P7") (pin "P$237") (pinfunction "P$1_P$237") (pintype "power_in"))
      (node (ref "P7") (pin "P$238") (pinfunction "P$1_P$238") (pintype "power_in"))
      (node (ref "P7") (pin "P$239") (pinfunction "P$1_P$239") (pintype "power_in"))
      (node (ref "P7") (pin "P$24") (pinfunction "P$1_P$24") (pintype "power_in"))
      (node (ref "P7") (pin "P$240") (pinfunction "P$1_P$240") (pintype "power_in"))
      (node (ref "P7") (pin "P$241") (pinfunction "P$1_P$241") (pintype "power_in"))
      (node (ref "P7") (pin "P$242") (pinfunction "P$1_P$242") (pintype "power_in"))
      (node (ref "P7") (pin "P$243") (pinfunction "P$1_P$243") (pintype "power_in"))
      (node (ref "P7") (pin "P$244") (pinfunction "P$1_P$244") (pintype "power_in"))
      (node (ref "P7") (pin "P$245") (pinfunction "P$1_P$245") (pintype "power_in"))
      (node (ref "P7") (pin "P$246") (pinfunction "P$1_P$246") (pintype "power_in"))
      (node (ref "P7") (pin "P$247") (pinfunction "P$1_P$247") (pintype "power_in"))
      (node (ref "P7") (pin "P$248") (pinfunction "P$1_P$248") (pintype "power_in"))
      (node (ref "P7") (pin "P$249") (pinfunction "P$1_P$249") (pintype "power_in"))
      (node (ref "P7") (pin "P$25") (pinfunction "P$1_P$25") (pintype "power_in"))
      (node (ref "P7") (pin "P$250") (pinfunction "P$1_P$250") (pintype "power_in"))
      (node (ref "P7") (pin "P$251") (pinfunction "P$1_P$251") (pintype "power_in"))
      (node (ref "P7") (pin "P$252") (pinfunction "P$1_P$252") (pintype "power_in"))
      (node (ref "P7") (pin "P$253") (pinfunction "P$1_P$253") (pintype "power_in"))
      (node (ref "P7") (pin "P$254") (pinfunction "P$1_P$254") (pintype "power_in"))
      (node (ref "P7") (pin "P$255") (pinfunction "P$1_P$255") (pintype "power_in"))
      (node (ref "P7") (pin "P$256") (pinfunction "P$1_P$256") (pintype "power_in"))
      (node (ref "P7") (pin "P$257") (pinfunction "P$1_P$257") (pintype "power_in"))
      (node (ref "P7") (pin "P$258") (pinfunction "P$1_P$258") (pintype "power_in"))
      (node (ref "P7") (pin "P$259") (pinfunction "P$1_P$259") (pintype "power_in"))
      (node (ref "P7") (pin "P$26") (pinfunction "P$1_P$26") (pintype "power_in"))
      (node (ref "P7") (pin "P$260") (pinfunction "P$1_P$260") (pintype "power_in"))
      (node (ref "P7") (pin "P$261") (pinfunction "P$1_P$261") (pintype "power_in"))
      (node (ref "P7") (pin "P$262") (pinfunction "P$1_P$262") (pintype "power_in"))
      (node (ref "P7") (pin "P$263") (pinfunction "P$1_P$263") (pintype "power_in"))
      (node (ref "P7") (pin "P$264") (pinfunction "P$1_P$264") (pintype "power_in"))
      (node (ref "P7") (pin "P$265") (pinfunction "P$1_P$265") (pintype "power_in"))
      (node (ref "P7") (pin "P$266") (pinfunction "P$1_P$266") (pintype "power_in"))
      (node (ref "P7") (pin "P$267") (pinfunction "P$1_P$267") (pintype "power_in"))
      (node (ref "P7") (pin "P$268") (pinfunction "P$1_P$268") (pintype "power_in"))
      (node (ref "P7") (pin "P$269") (pinfunction "P$1_P$269") (pintype "power_in"))
      (node (ref "P7") (pin "P$27") (pinfunction "P$1_P$27") (pintype "power_in"))
      (node (ref "P7") (pin "P$270") (pinfunction "P$1_P$270") (pintype "power_in"))
      (node (ref "P7") (pin "P$271") (pinfunction "P$1_P$271") (pintype "power_in"))
      (node (ref "P7") (pin "P$272") (pinfunction "P$1_P$272") (pintype "power_in"))
      (node (ref "P7") (pin "P$273") (pinfunction "P$1_P$273") (pintype "power_in"))
      (node (ref "P7") (pin "P$274") (pinfunction "P$1_P$274") (pintype "power_in"))
      (node (ref "P7") (pin "P$275") (pinfunction "P$1_P$275") (pintype "power_in"))
      (node (ref "P7") (pin "P$276") (pinfunction "P$1_P$276") (pintype "power_in"))
      (node (ref "P7") (pin "P$277") (pinfunction "P$1_P$277") (pintype "power_in"))
      (node (ref "P7") (pin "P$278") (pinfunction "P$1_P$278") (pintype "power_in"))
      (node (ref "P7") (pin "P$279") (pinfunction "P$1_P$279") (pintype "power_in"))
      (node (ref "P7") (pin "P$28") (pinfunction "P$1_P$28") (pintype "power_in"))
      (node (ref "P7") (pin "P$280") (pinfunction "P$1_P$280") (pintype "power_in"))
      (node (ref "P7") (pin "P$281") (pinfunction "P$1_P$281") (pintype "power_in"))
      (node (ref "P7") (pin "P$282") (pinfunction "P$1_P$282") (pintype "power_in"))
      (node (ref "P7") (pin "P$283") (pinfunction "P$1_P$283") (pintype "power_in"))
      (node (ref "P7") (pin "P$284") (pinfunction "P$1_P$284") (pintype "power_in"))
      (node (ref "P7") (pin "P$285") (pinfunction "P$1_P$285") (pintype "power_in"))
      (node (ref "P7") (pin "P$286") (pinfunction "P$1_P$286") (pintype "power_in"))
      (node (ref "P7") (pin "P$287") (pinfunction "P$1_P$287") (pintype "power_in"))
      (node (ref "P7") (pin "P$288") (pinfunction "P$1_P$288") (pintype "power_in"))
      (node (ref "P7") (pin "P$29") (pinfunction "P$1_P$29") (pintype "power_in"))
      (node (ref "P7") (pin "P$3") (pinfunction "P$1_P$3") (pintype "power_in"))
      (node (ref "P7") (pin "P$30") (pinfunction "P$1_P$30") (pintype "power_in"))
      (node (ref "P7") (pin "P$31") (pinfunction "P$1_P$31") (pintype "power_in"))
      (node (ref "P7") (pin "P$32") (pinfunction "P$1_P$32") (pintype "power_in"))
      (node (ref "P7") (pin "P$33") (pinfunction "P$1_P$33") (pintype "power_in"))
      (node (ref "P7") (pin "P$34") (pinfunction "P$1_P$34") (pintype "power_in"))
      (node (ref "P7") (pin "P$35") (pinfunction "P$1_P$35") (pintype "power_in"))
      (node (ref "P7") (pin "P$36") (pinfunction "P$1_P$36") (pintype "power_in"))
      (node (ref "P7") (pin "P$37") (pinfunction "P$1_P$37") (pintype "power_in"))
      (node (ref "P7") (pin "P$38") (pinfunction "P$1_P$38") (pintype "power_in"))
      (node (ref "P7") (pin "P$39") (pinfunction "P$1_P$39") (pintype "power_in"))
      (node (ref "P7") (pin "P$4") (pinfunction "P$1_P$4") (pintype "power_in"))
      (node (ref "P7") (pin "P$40") (pinfunction "P$1_P$40") (pintype "power_in"))
      (node (ref "P7") (pin "P$41") (pinfunction "P$1_P$41") (pintype "power_in"))
      (node (ref "P7") (pin "P$42") (pinfunction "P$1_P$42") (pintype "power_in"))
      (node (ref "P7") (pin "P$43") (pinfunction "P$1_P$43") (pintype "power_in"))
      (node (ref "P7") (pin "P$44") (pinfunction "P$1_P$44") (pintype "power_in"))
      (node (ref "P7") (pin "P$45") (pinfunction "P$1_P$45") (pintype "power_in"))
      (node (ref "P7") (pin "P$46") (pinfunction "P$1_P$46") (pintype "power_in"))
      (node (ref "P7") (pin "P$47") (pinfunction "P$1_P$47") (pintype "power_in"))
      (node (ref "P7") (pin "P$48") (pinfunction "P$1_P$48") (pintype "power_in"))
      (node (ref "P7") (pin "P$49") (pinfunction "P$1_P$49") (pintype "power_in"))
      (node (ref "P7") (pin "P$5") (pinfunction "P$1_P$5") (pintype "power_in"))
      (node (ref "P7") (pin "P$50") (pinfunction "P$1_P$50") (pintype "power_in"))
      (node (ref "P7") (pin "P$51") (pinfunction "P$1_P$51") (pintype "power_in"))
      (node (ref "P7") (pin "P$52") (pinfunction "P$1_P$52") (pintype "power_in"))
      (node (ref "P7") (pin "P$53") (pinfunction "P$1_P$53") (pintype "power_in"))
      (node (ref "P7") (pin "P$54") (pinfunction "P$1_P$54") (pintype "power_in"))
      (node (ref "P7") (pin "P$55") (pinfunction "P$1_P$55") (pintype "power_in"))
      (node (ref "P7") (pin "P$56") (pinfunction "P$1_P$56") (pintype "power_in"))
      (node (ref "P7") (pin "P$57") (pinfunction "P$1_P$57") (pintype "power_in"))
      (node (ref "P7") (pin "P$58") (pinfunction "P$1_P$58") (pintype "power_in"))
      (node (ref "P7") (pin "P$59") (pinfunction "P$1_P$59") (pintype "power_in"))
      (node (ref "P7") (pin "P$6") (pinfunction "P$1_P$6") (pintype "power_in"))
      (node (ref "P7") (pin "P$60") (pinfunction "P$1_P$60") (pintype "power_in"))
      (node (ref "P7") (pin "P$61") (pinfunction "P$1_P$61") (pintype "power_in"))
      (node (ref "P7") (pin "P$62") (pinfunction "P$1_P$62") (pintype "power_in"))
      (node (ref "P7") (pin "P$63") (pinfunction "P$1_P$63") (pintype "power_in"))
      (node (ref "P7") (pin "P$64") (pinfunction "P$1_P$64") (pintype "power_in"))
      (node (ref "P7") (pin "P$65") (pinfunction "P$1_P$65") (pintype "power_in"))
      (node (ref "P7") (pin "P$66") (pinfunction "P$1_P$66") (pintype "power_in"))
      (node (ref "P7") (pin "P$67") (pinfunction "P$1_P$67") (pintype "power_in"))
      (node (ref "P7") (pin "P$68") (pinfunction "P$1_P$68") (pintype "power_in"))
      (node (ref "P7") (pin "P$69") (pinfunction "P$1_P$69") (pintype "power_in"))
      (node (ref "P7") (pin "P$7") (pinfunction "P$1_P$7") (pintype "power_in"))
      (node (ref "P7") (pin "P$70") (pinfunction "P$1_P$70") (pintype "power_in"))
      (node (ref "P7") (pin "P$71") (pinfunction "P$1_P$71") (pintype "power_in"))
      (node (ref "P7") (pin "P$72") (pinfunction "P$1_P$72") (pintype "power_in"))
      (node (ref "P7") (pin "P$73") (pinfunction "P$1_P$73") (pintype "power_in"))
      (node (ref "P7") (pin "P$74") (pinfunction "P$1_P$74") (pintype "power_in"))
      (node (ref "P7") (pin "P$75") (pinfunction "P$1_P$75") (pintype "power_in"))
      (node (ref "P7") (pin "P$76") (pinfunction "P$1_P$76") (pintype "power_in"))
      (node (ref "P7") (pin "P$77") (pinfunction "P$1_P$77") (pintype "power_in"))
      (node (ref "P7") (pin "P$78") (pinfunction "P$1_P$78") (pintype "power_in"))
      (node (ref "P7") (pin "P$79") (pinfunction "P$1_P$79") (pintype "power_in"))
      (node (ref "P7") (pin "P$8") (pinfunction "P$1_P$8") (pintype "power_in"))
      (node (ref "P7") (pin "P$80") (pinfunction "P$1_P$80") (pintype "power_in"))
      (node (ref "P7") (pin "P$81") (pinfunction "P$1_P$81") (pintype "power_in"))
      (node (ref "P7") (pin "P$82") (pinfunction "P$1_P$82") (pintype "power_in"))
      (node (ref "P7") (pin "P$83") (pinfunction "P$1_P$83") (pintype "power_in"))
      (node (ref "P7") (pin "P$84") (pinfunction "P$1_P$84") (pintype "power_in"))
      (node (ref "P7") (pin "P$85") (pinfunction "P$1_P$85") (pintype "power_in"))
      (node (ref "P7") (pin "P$86") (pinfunction "P$1_P$86") (pintype "power_in"))
      (node (ref "P7") (pin "P$87") (pinfunction "P$1_P$87") (pintype "power_in"))
      (node (ref "P7") (pin "P$88") (pinfunction "P$1_P$88") (pintype "power_in"))
      (node (ref "P7") (pin "P$89") (pinfunction "P$1_P$89") (pintype "power_in"))
      (node (ref "P7") (pin "P$9") (pinfunction "P$1_P$9") (pintype "power_in"))
      (node (ref "P7") (pin "P$90") (pinfunction "P$1_P$90") (pintype "power_in"))
      (node (ref "P7") (pin "P$91") (pinfunction "P$1_P$91") (pintype "power_in"))
      (node (ref "P7") (pin "P$92") (pinfunction "P$1_P$92") (pintype "power_in"))
      (node (ref "P7") (pin "P$93") (pinfunction "P$1_P$93") (pintype "power_in"))
      (node (ref "P7") (pin "P$94") (pinfunction "P$1_P$94") (pintype "power_in"))
      (node (ref "P7") (pin "P$95") (pinfunction "P$1_P$95") (pintype "power_in"))
      (node (ref "P7") (pin "P$96") (pinfunction "P$1_P$96") (pintype "power_in"))
      (node (ref "P7") (pin "P$97") (pinfunction "P$1_P$97") (pintype "power_in"))
      (node (ref "P7") (pin "P$98") (pinfunction "P$1_P$98") (pintype "power_in"))
      (node (ref "P7") (pin "P$99") (pinfunction "P$1_P$99") (pintype "power_in"))
    )
    (net (code "9") (name "/P8") (class "Default")
      (node (ref "JP1") (pin "P$9") (pinfunction "8_P$9") (pintype "bidirectional"))
      (node (ref "P8") (pin "P$1") (pinfunction "P$1_P$1") (pintype "power_in"))
      (node (ref "P8") (pin "P$10") (pinfunction "P$1_P$10") (pintype "power_in"))
      (node (ref "P8") (pin "P$100") (pinfunction "P$1_P$100") (pintype "power_in"))
      (node (ref "P8") (pin "P$101") (pinfunction "P$1_P$101") (pintype "power_in"))
      (node (ref "P8") (pin "P$102") (pinfunction "P$1_P$102") (pintype "power_in"))
      (node (ref "P8") (pin "P$103") (pinfunction "P$1_P$103") (pintype "power_in"))
      (node (ref "P8") (pin "P$104") (pinfunction "P$1_P$104") (pintype "power_in"))
      (node (ref "P8") (pin "P$105") (pinfunction "P$1_P$105") (pintype "power_in"))
      (node (ref "P8") (pin "P$106") (pinfunction "P$1_P$106") (pintype "power_in"))
      (node (ref "P8") (pin "P$107") (pinfunction "P$1_P$107") (pintype "power_in"))
      (node (ref "P8") (pin "P$108") (pinfunction "P$1_P$108") (pintype "power_in"))
      (node (ref "P8") (pin "P$109") (pinfunction "P$1_P$109") (pintype "power_in"))
      (node (ref "P8") (pin "P$11") (pinfunction "P$1_P$11") (pintype "power_in"))
      (node (ref "P8") (pin "P$110") (pinfunction "P$1_P$110") (pintype "power_in"))
      (node (ref "P8") (pin "P$111") (pinfunction "P$1_P$111") (pintype "power_in"))
      (node (ref "P8") (pin "P$112") (pinfunction "P$1_P$112") (pintype "power_in"))
      (node (ref "P8") (pin "P$113") (pinfunction "P$1_P$113") (pintype "power_in"))
      (node (ref "P8") (pin "P$114") (pinfunction "P$1_P$114") (pintype "power_in"))
      (node (ref "P8") (pin "P$115") (pinfunction "P$1_P$115") (pintype "power_in"))
      (node (ref "P8") (pin "P$116") (pinfunction "P$1_P$116") (pintype "power_in"))
      (node (ref "P8") (pin "P$117") (pinfunction "P$1_P$117") (pintype "power_in"))
      (node (ref "P8") (pin "P$118") (pinfunction "P$1_P$118") (pintype "power_in"))
      (node (ref "P8") (pin "P$119") (pinfunction "P$1_P$119") (pintype "power_in"))
      (node (ref "P8") (pin "P$12") (pinfunction "P$1_P$12") (pintype "power_in"))
      (node (ref "P8") (pin "P$120") (pinfunction "P$1_P$120") (pintype "power_in"))
      (node (ref "P8") (pin "P$121") (pinfunction "P$1_P$121") (pintype "power_in"))
      (node (ref "P8") (pin "P$122") (pinfunction "P$1_P$122") (pintype "power_in"))
      (node (ref "P8") (pin "P$123") (pinfunction "P$1_P$123") (pintype "power_in"))
      (node (ref "P8") (pin "P$124") (pinfunction "P$1_P$124") (pintype "power_in"))
      (node (ref "P8") (pin "P$125") (pinfunction "P$1_P$125") (pintype "power_in"))
      (node (ref "P8") (pin "P$126") (pinfunction "P$1_P$126") (pintype "power_in"))
      (node (ref "P8") (pin "P$127") (pinfunction "P$1_P$127") (pintype "power_in"))
      (node (ref "P8") (pin "P$128") (pinfunction "P$1_P$128") (pintype "power_in"))
      (node (ref "P8") (pin "P$129") (pinfunction "P$1_P$129") (pintype "power_in"))
      (node (ref "P8") (pin "P$13") (pinfunction "P$1_P$13") (pintype "power_in"))
      (node (ref "P8") (pin "P$130") (pinfunction "P$1_P$130") (pintype "power_in"))
      (node (ref "P8") (pin "P$131") (pinfunction "P$1_P$131") (pintype "power_in"))
      (node (ref "P8") (pin "P$132") (pinfunction "P$1_P$132") (pintype "power_in"))
      (node (ref "P8") (pin "P$133") (pinfunction "P$1_P$133") (pintype "power_in"))
      (node (ref "P8") (pin "P$134") (pinfunction "P$1_P$134") (pintype "power_in"))
      (node (ref "P8") (pin "P$135") (pinfunction "P$1_P$135") (pintype "power_in"))
      (node (ref "P8") (pin "P$136") (pinfunction "P$1_P$136") (pintype "power_in"))
      (node (ref "P8") (pin "P$137") (pinfunction "P$1_P$137") (pintype "power_in"))
      (node (ref "P8") (pin "P$138") (pinfunction "P$1_P$138") (pintype "power_in"))
      (node (ref "P8") (pin "P$139") (pinfunction "P$1_P$139") (pintype "power_in"))
      (node (ref "P8") (pin "P$14") (pinfunction "P$1_P$14") (pintype "power_in"))
      (node (ref "P8") (pin "P$140") (pinfunction "P$1_P$140") (pintype "power_in"))
      (node (ref "P8") (pin "P$141") (pinfunction "P$1_P$141") (pintype "power_in"))
      (node (ref "P8") (pin "P$142") (pinfunction "P$1_P$142") (pintype "power_in"))
      (node (ref "P8") (pin "P$143") (pinfunction "P$1_P$143") (pintype "power_in"))
      (node (ref "P8") (pin "P$144") (pinfunction "P$1_P$144") (pintype "power_in"))
      (node (ref "P8") (pin "P$145") (pinfunction "P$1_P$145") (pintype "power_in"))
      (node (ref "P8") (pin "P$146") (pinfunction "P$1_P$146") (pintype "power_in"))
      (node (ref "P8") (pin "P$147") (pinfunction "P$1_P$147") (pintype "power_in"))
      (node (ref "P8") (pin "P$148") (pinfunction "P$1_P$148") (pintype "power_in"))
      (node (ref "P8") (pin "P$149") (pinfunction "P$1_P$149") (pintype "power_in"))
      (node (ref "P8") (pin "P$15") (pinfunction "P$1_P$15") (pintype "power_in"))
      (node (ref "P8") (pin "P$150") (pinfunction "P$1_P$150") (pintype "power_in"))
      (node (ref "P8") (pin "P$151") (pinfunction "P$1_P$151") (pintype "power_in"))
      (node (ref "P8") (pin "P$152") (pinfunction "P$1_P$152") (pintype "power_in"))
      (node (ref "P8") (pin "P$153") (pinfunction "P$1_P$153") (pintype "power_in"))
      (node (ref "P8") (pin "P$154") (pinfunction "P$1_P$154") (pintype "power_in"))
      (node (ref "P8") (pin "P$155") (pinfunction "P$1_P$155") (pintype "power_in"))
      (node (ref "P8") (pin "P$156") (pinfunction "P$1_P$156") (pintype "power_in"))
      (node (ref "P8") (pin "P$157") (pinfunction "P$1_P$157") (pintype "power_in"))
      (node (ref "P8") (pin "P$158") (pinfunction "P$1_P$158") (pintype "power_in"))
      (node (ref "P8") (pin "P$159") (pinfunction "P$1_P$159") (pintype "power_in"))
      (node (ref "P8") (pin "P$16") (pinfunction "P$1_P$16") (pintype "power_in"))
      (node (ref "P8") (pin "P$160") (pinfunction "P$1_P$160") (pintype "power_in"))
      (node (ref "P8") (pin "P$161") (pinfunction "P$1_P$161") (pintype "power_in"))
      (node (ref "P8") (pin "P$162") (pinfunction "P$1_P$162") (pintype "power_in"))
      (node (ref "P8") (pin "P$163") (pinfunction "P$1_P$163") (pintype "power_in"))
      (node (ref "P8") (pin "P$164") (pinfunction "P$1_P$164") (pintype "power_in"))
      (node (ref "P8") (pin "P$165") (pinfunction "P$1_P$165") (pintype "power_in"))
      (node (ref "P8") (pin "P$166") (pinfunction "P$1_P$166") (pintype "power_in"))
      (node (ref "P8") (pin "P$167") (pinfunction "P$1_P$167") (pintype "power_in"))
      (node (ref "P8") (pin "P$168") (pinfunction "P$1_P$168") (pintype "power_in"))
      (node (ref "P8") (pin "P$169") (pinfunction "P$1_P$169") (pintype "power_in"))
      (node (ref "P8") (pin "P$17") (pinfunction "P$1_P$17") (pintype "power_in"))
      (node (ref "P8") (pin "P$170") (pinfunction "P$1_P$170") (pintype "power_in"))
      (node (ref "P8") (pin "P$171") (pinfunction "P$1_P$171") (pintype "power_in"))
      (node (ref "P8") (pin "P$172") (pinfunction "P$1_P$172") (pintype "power_in"))
      (node (ref "P8") (pin "P$173") (pinfunction "P$1_P$173") (pintype "power_in"))
      (node (ref "P8") (pin "P$174") (pinfunction "P$1_P$174") (pintype "power_in"))
      (node (ref "P8") (pin "P$175") (pinfunction "P$1_P$175") (pintype "power_in"))
      (node (ref "P8") (pin "P$176") (pinfunction "P$1_P$176") (pintype "power_in"))
      (node (ref "P8") (pin "P$177") (pinfunction "P$1_P$177") (pintype "power_in"))
      (node (ref "P8") (pin "P$178") (pinfunction "P$1_P$178") (pintype "power_in"))
      (node (ref "P8") (pin "P$179") (pinfunction "P$1_P$179") (pintype "power_in"))
      (node (ref "P8") (pin "P$18") (pinfunction "P$1_P$18") (pintype "power_in"))
      (node (ref "P8") (pin "P$180") (pinfunction "P$1_P$180") (pintype "power_in"))
      (node (ref "P8") (pin "P$181") (pinfunction "P$1_P$181") (pintype "power_in"))
      (node (ref "P8") (pin "P$182") (pinfunction "P$1_P$182") (pintype "power_in"))
      (node (ref "P8") (pin "P$183") (pinfunction "P$1_P$183") (pintype "power_in"))
      (node (ref "P8") (pin "P$184") (pinfunction "P$1_P$184") (pintype "power_in"))
      (node (ref "P8") (pin "P$185") (pinfunction "P$1_P$185") (pintype "power_in"))
      (node (ref "P8") (pin "P$186") (pinfunction "P$1_P$186") (pintype "power_in"))
      (node (ref "P8") (pin "P$187") (pinfunction "P$1_P$187") (pintype "power_in"))
      (node (ref "P8") (pin "P$188") (pinfunction "P$1_P$188") (pintype "power_in"))
      (node (ref "P8") (pin "P$189") (pinfunction "P$1_P$189") (pintype "power_in"))
      (node (ref "P8") (pin "P$19") (pinfunction "P$1_P$19") (pintype "power_in"))
      (node (ref "P8") (pin "P$190") (pinfunction "P$1_P$190") (pintype "power_in"))
      (node (ref "P8") (pin "P$191") (pinfunction "P$1_P$191") (pintype "power_in"))
      (node (ref "P8") (pin "P$192") (pinfunction "P$1_P$192") (pintype "power_in"))
      (node (ref "P8") (pin "P$193") (pinfunction "P$1_P$193") (pintype "power_in"))
      (node (ref "P8") (pin "P$194") (pinfunction "P$1_P$194") (pintype "power_in"))
      (node (ref "P8") (pin "P$195") (pinfunction "P$1_P$195") (pintype "power_in"))
      (node (ref "P8") (pin "P$196") (pinfunction "P$1_P$196") (pintype "power_in"))
      (node (ref "P8") (pin "P$197") (pinfunction "P$1_P$197") (pintype "power_in"))
      (node (ref "P8") (pin "P$198") (pinfunction "P$1_P$198") (pintype "power_in"))
      (node (ref "P8") (pin "P$199") (pinfunction "P$1_P$199") (pintype "power_in"))
      (node (ref "P8") (pin "P$2") (pinfunction "P$1_P$2") (pintype "power_in"))
      (node (ref "P8") (pin "P$20") (pinfunction "P$1_P$20") (pintype "power_in"))
      (node (ref "P8") (pin "P$200") (pinfunction "P$1_P$200") (pintype "power_in"))
      (node (ref "P8") (pin "P$201") (pinfunction "P$1_P$201") (pintype "power_in"))
      (node (ref "P8") (pin "P$202") (pinfunction "P$1_P$202") (pintype "power_in"))
      (node (ref "P8") (pin "P$203") (pinfunction "P$1_P$203") (pintype "power_in"))
      (node (ref "P8") (pin "P$204") (pinfunction "P$1_P$204") (pintype "power_in"))
      (node (ref "P8") (pin "P$205") (pinfunction "P$1_P$205") (pintype "power_in"))
      (node (ref "P8") (pin "P$206") (pinfunction "P$1_P$206") (pintype "power_in"))
      (node (ref "P8") (pin "P$207") (pinfunction "P$1_P$207") (pintype "power_in"))
      (node (ref "P8") (pin "P$208") (pinfunction "P$1_P$208") (pintype "power_in"))
      (node (ref "P8") (pin "P$209") (pinfunction "P$1_P$209") (pintype "power_in"))
      (node (ref "P8") (pin "P$21") (pinfunction "P$1_P$21") (pintype "power_in"))
      (node (ref "P8") (pin "P$210") (pinfunction "P$1_P$210") (pintype "power_in"))
      (node (ref "P8") (pin "P$211") (pinfunction "P$1_P$211") (pintype "power_in"))
      (node (ref "P8") (pin "P$212") (pinfunction "P$1_P$212") (pintype "power_in"))
      (node (ref "P8") (pin "P$213") (pinfunction "P$1_P$213") (pintype "power_in"))
      (node (ref "P8") (pin "P$214") (pinfunction "P$1_P$214") (pintype "power_in"))
      (node (ref "P8") (pin "P$215") (pinfunction "P$1_P$215") (pintype "power_in"))
      (node (ref "P8") (pin "P$216") (pinfunction "P$1_P$216") (pintype "power_in"))
      (node (ref "P8") (pin "P$217") (pinfunction "P$1_P$217") (pintype "power_in"))
      (node (ref "P8") (pin "P$218") (pinfunction "P$1_P$218") (pintype "power_in"))
      (node (ref "P8") (pin "P$219") (pinfunction "P$1_P$219") (pintype "power_in"))
      (node (ref "P8") (pin "P$22") (pinfunction "P$1_P$22") (pintype "power_in"))
      (node (ref "P8") (pin "P$220") (pinfunction "P$1_P$220") (pintype "power_in"))
      (node (ref "P8") (pin "P$221") (pinfunction "P$1_P$221") (pintype "power_in"))
      (node (ref "P8") (pin "P$222") (pinfunction "P$1_P$222") (pintype "power_in"))
      (node (ref "P8") (pin "P$223") (pinfunction "P$1_P$223") (pintype "power_in"))
      (node (ref "P8") (pin "P$224") (pinfunction "P$1_P$224") (pintype "power_in"))
      (node (ref "P8") (pin "P$225") (pinfunction "P$1_P$225") (pintype "power_in"))
      (node (ref "P8") (pin "P$226") (pinfunction "P$1_P$226") (pintype "power_in"))
      (node (ref "P8") (pin "P$227") (pinfunction "P$1_P$227") (pintype "power_in"))
      (node (ref "P8") (pin "P$228") (pinfunction "P$1_P$228") (pintype "power_in"))
      (node (ref "P8") (pin "P$229") (pinfunction "P$1_P$229") (pintype "power_in"))
      (node (ref "P8") (pin "P$23") (pinfunction "P$1_P$23") (pintype "power_in"))
      (node (ref "P8") (pin "P$230") (pinfunction "P$1_P$230") (pintype "power_in"))
      (node (ref "P8") (pin "P$231") (pinfunction "P$1_P$231") (pintype "power_in"))
      (node (ref "P8") (pin "P$232") (pinfunction "P$1_P$232") (pintype "power_in"))
      (node (ref "P8") (pin "P$233") (pinfunction "P$1_P$233") (pintype "power_in"))
      (node (ref "P8") (pin "P$234") (pinfunction "P$1_P$234") (pintype "power_in"))
      (node (ref "P8") (pin "P$235") (pinfunction "P$1_P$235") (pintype "power_in"))
      (node (ref "P8") (pin "P$236") (pinfunction "P$1_P$236") (pintype "power_in"))
      (node (ref "P8") (pin "P$237") (pinfunction "P$1_P$237") (pintype "power_in"))
      (node (ref "P8") (pin "P$238") (pinfunction "P$1_P$238") (pintype "power_in"))
      (node (ref "P8") (pin "P$239") (pinfunction "P$1_P$239") (pintype "power_in"))
      (node (ref "P8") (pin "P$24") (pinfunction "P$1_P$24") (pintype "power_in"))
      (node (ref "P8") (pin "P$240") (pinfunction "P$1_P$240") (pintype "power_in"))
      (node (ref "P8") (pin "P$241") (pinfunction "P$1_P$241") (pintype "power_in"))
      (node (ref "P8") (pin "P$242") (pinfunction "P$1_P$242") (pintype "power_in"))
      (node (ref "P8") (pin "P$243") (pinfunction "P$1_P$243") (pintype "power_in"))
      (node (ref "P8") (pin "P$244") (pinfunction "P$1_P$244") (pintype "power_in"))
      (node (ref "P8") (pin "P$245") (pinfunction "P$1_P$245") (pintype "power_in"))
      (node (ref "P8") (pin "P$246") (pinfunction "P$1_P$246") (pintype "power_in"))
      (node (ref "P8") (pin "P$247") (pinfunction "P$1_P$247") (pintype "power_in"))
      (node (ref "P8") (pin "P$248") (pinfunction "P$1_P$248") (pintype "power_in"))
      (node (ref "P8") (pin "P$249") (pinfunction "P$1_P$249") (pintype "power_in"))
      (node (ref "P8") (pin "P$25") (pinfunction "P$1_P$25") (pintype "power_in"))
      (node (ref "P8") (pin "P$250") (pinfunction "P$1_P$250") (pintype "power_in"))
      (node (ref "P8") (pin "P$251") (pinfunction "P$1_P$251") (pintype "power_in"))
      (node (ref "P8") (pin "P$252") (pinfunction "P$1_P$252") (pintype "power_in"))
      (node (ref "P8") (pin "P$253") (pinfunction "P$1_P$253") (pintype "power_in"))
      (node (ref "P8") (pin "P$254") (pinfunction "P$1_P$254") (pintype "power_in"))
      (node (ref "P8") (pin "P$255") (pinfunction "P$1_P$255") (pintype "power_in"))
      (node (ref "P8") (pin "P$256") (pinfunction "P$1_P$256") (pintype "power_in"))
      (node (ref "P8") (pin "P$257") (pinfunction "P$1_P$257") (pintype "power_in"))
      (node (ref "P8") (pin "P$258") (pinfunction "P$1_P$258") (pintype "power_in"))
      (node (ref "P8") (pin "P$259") (pinfunction "P$1_P$259") (pintype "power_in"))
      (node (ref "P8") (pin "P$26") (pinfunction "P$1_P$26") (pintype "power_in"))
      (node (ref "P8") (pin "P$260") (pinfunction "P$1_P$260") (pintype "power_in"))
      (node (ref "P8") (pin "P$261") (pinfunction "P$1_P$261") (pintype "power_in"))
      (node (ref "P8") (pin "P$262") (pinfunction "P$1_P$262") (pintype "power_in"))
      (node (ref "P8") (pin "P$263") (pinfunction "P$1_P$263") (pintype "power_in"))
      (node (ref "P8") (pin "P$264") (pinfunction "P$1_P$264") (pintype "power_in"))
      (node (ref "P8") (pin "P$265") (pinfunction "P$1_P$265") (pintype "power_in"))
      (node (ref "P8") (pin "P$266") (pinfunction "P$1_P$266") (pintype "power_in"))
      (node (ref "P8") (pin "P$267") (pinfunction "P$1_P$267") (pintype "power_in"))
      (node (ref "P8") (pin "P$268") (pinfunction "P$1_P$268") (pintype "power_in"))
      (node (ref "P8") (pin "P$269") (pinfunction "P$1_P$269") (pintype "power_in"))
      (node (ref "P8") (pin "P$27") (pinfunction "P$1_P$27") (pintype "power_in"))
      (node (ref "P8") (pin "P$270") (pinfunction "P$1_P$270") (pintype "power_in"))
      (node (ref "P8") (pin "P$271") (pinfunction "P$1_P$271") (pintype "power_in"))
      (node (ref "P8") (pin "P$272") (pinfunction "P$1_P$272") (pintype "power_in"))
      (node (ref "P8") (pin "P$273") (pinfunction "P$1_P$273") (pintype "power_in"))
      (node (ref "P8") (pin "P$274") (pinfunction "P$1_P$274") (pintype "power_in"))
      (node (ref "P8") (pin "P$275") (pinfunction "P$1_P$275") (pintype "power_in"))
      (node (ref "P8") (pin "P$276") (pinfunction "P$1_P$276") (pintype "power_in"))
      (node (ref "P8") (pin "P$277") (pinfunction "P$1_P$277") (pintype "power_in"))
      (node (ref "P8") (pin "P$278") (pinfunction "P$1_P$278") (pintype "power_in"))
      (node (ref "P8") (pin "P$279") (pinfunction "P$1_P$279") (pintype "power_in"))
      (node (ref "P8") (pin "P$28") (pinfunction "P$1_P$28") (pintype "power_in"))
      (node (ref "P8") (pin "P$280") (pinfunction "P$1_P$280") (pintype "power_in"))
      (node (ref "P8") (pin "P$281") (pinfunction "P$1_P$281") (pintype "power_in"))
      (node (ref "P8") (pin "P$282") (pinfunction "P$1_P$282") (pintype "power_in"))
      (node (ref "P8") (pin "P$283") (pinfunction "P$1_P$283") (pintype "power_in"))
      (node (ref "P8") (pin "P$284") (pinfunction "P$1_P$284") (pintype "power_in"))
      (node (ref "P8") (pin "P$285") (pinfunction "P$1_P$285") (pintype "power_in"))
      (node (ref "P8") (pin "P$286") (pinfunction "P$1_P$286") (pintype "power_in"))
      (node (ref "P8") (pin "P$287") (pinfunction "P$1_P$287") (pintype "power_in"))
      (node (ref "P8") (pin "P$288") (pinfunction "P$1_P$288") (pintype "power_in"))
      (node (ref "P8") (pin "P$29") (pinfunction "P$1_P$29") (pintype "power_in"))
      (node (ref "P8") (pin "P$3") (pinfunction "P$1_P$3") (pintype "power_in"))
      (node (ref "P8") (pin "P$30") (pinfunction "P$1_P$30") (pintype "power_in"))
      (node (ref "P8") (pin "P$31") (pinfunction "P$1_P$31") (pintype "power_in"))
      (node (ref "P8") (pin "P$32") (pinfunction "P$1_P$32") (pintype "power_in"))
      (node (ref "P8") (pin "P$33") (pinfunction "P$1_P$33") (pintype "power_in"))
      (node (ref "P8") (pin "P$34") (pinfunction "P$1_P$34") (pintype "power_in"))
      (node (ref "P8") (pin "P$35") (pinfunction "P$1_P$35") (pintype "power_in"))
      (node (ref "P8") (pin "P$36") (pinfunction "P$1_P$36") (pintype "power_in"))
      (node (ref "P8") (pin "P$37") (pinfunction "P$1_P$37") (pintype "power_in"))
      (node (ref "P8") (pin "P$38") (pinfunction "P$1_P$38") (pintype "power_in"))
      (node (ref "P8") (pin "P$39") (pinfunction "P$1_P$39") (pintype "power_in"))
      (node (ref "P8") (pin "P$4") (pinfunction "P$1_P$4") (pintype "power_in"))
      (node (ref "P8") (pin "P$40") (pinfunction "P$1_P$40") (pintype "power_in"))
      (node (ref "P8") (pin "P$41") (pinfunction "P$1_P$41") (pintype "power_in"))
      (node (ref "P8") (pin "P$42") (pinfunction "P$1_P$42") (pintype "power_in"))
      (node (ref "P8") (pin "P$43") (pinfunction "P$1_P$43") (pintype "power_in"))
      (node (ref "P8") (pin "P$44") (pinfunction "P$1_P$44") (pintype "power_in"))
      (node (ref "P8") (pin "P$45") (pinfunction "P$1_P$45") (pintype "power_in"))
      (node (ref "P8") (pin "P$46") (pinfunction "P$1_P$46") (pintype "power_in"))
      (node (ref "P8") (pin "P$47") (pinfunction "P$1_P$47") (pintype "power_in"))
      (node (ref "P8") (pin "P$48") (pinfunction "P$1_P$48") (pintype "power_in"))
      (node (ref "P8") (pin "P$49") (pinfunction "P$1_P$49") (pintype "power_in"))
      (node (ref "P8") (pin "P$5") (pinfunction "P$1_P$5") (pintype "power_in"))
      (node (ref "P8") (pin "P$50") (pinfunction "P$1_P$50") (pintype "power_in"))
      (node (ref "P8") (pin "P$51") (pinfunction "P$1_P$51") (pintype "power_in"))
      (node (ref "P8") (pin "P$52") (pinfunction "P$1_P$52") (pintype "power_in"))
      (node (ref "P8") (pin "P$53") (pinfunction "P$1_P$53") (pintype "power_in"))
      (node (ref "P8") (pin "P$54") (pinfunction "P$1_P$54") (pintype "power_in"))
      (node (ref "P8") (pin "P$55") (pinfunction "P$1_P$55") (pintype "power_in"))
      (node (ref "P8") (pin "P$56") (pinfunction "P$1_P$56") (pintype "power_in"))
      (node (ref "P8") (pin "P$57") (pinfunction "P$1_P$57") (pintype "power_in"))
      (node (ref "P8") (pin "P$58") (pinfunction "P$1_P$58") (pintype "power_in"))
      (node (ref "P8") (pin "P$59") (pinfunction "P$1_P$59") (pintype "power_in"))
      (node (ref "P8") (pin "P$6") (pinfunction "P$1_P$6") (pintype "power_in"))
      (node (ref "P8") (pin "P$60") (pinfunction "P$1_P$60") (pintype "power_in"))
      (node (ref "P8") (pin "P$61") (pinfunction "P$1_P$61") (pintype "power_in"))
      (node (ref "P8") (pin "P$62") (pinfunction "P$1_P$62") (pintype "power_in"))
      (node (ref "P8") (pin "P$63") (pinfunction "P$1_P$63") (pintype "power_in"))
      (node (ref "P8") (pin "P$64") (pinfunction "P$1_P$64") (pintype "power_in"))
      (node (ref "P8") (pin "P$65") (pinfunction "P$1_P$65") (pintype "power_in"))
      (node (ref "P8") (pin "P$66") (pinfunction "P$1_P$66") (pintype "power_in"))
      (node (ref "P8") (pin "P$67") (pinfunction "P$1_P$67") (pintype "power_in"))
      (node (ref "P8") (pin "P$68") (pinfunction "P$1_P$68") (pintype "power_in"))
      (node (ref "P8") (pin "P$69") (pinfunction "P$1_P$69") (pintype "power_in"))
      (node (ref "P8") (pin "P$7") (pinfunction "P$1_P$7") (pintype "power_in"))
      (node (ref "P8") (pin "P$70") (pinfunction "P$1_P$70") (pintype "power_in"))
      (node (ref "P8") (pin "P$71") (pinfunction "P$1_P$71") (pintype "power_in"))
      (node (ref "P8") (pin "P$72") (pinfunction "P$1_P$72") (pintype "power_in"))
      (node (ref "P8") (pin "P$73") (pinfunction "P$1_P$73") (pintype "power_in"))
      (node (ref "P8") (pin "P$74") (pinfunction "P$1_P$74") (pintype "power_in"))
      (node (ref "P8") (pin "P$75") (pinfunction "P$1_P$75") (pintype "power_in"))
      (node (ref "P8") (pin "P$76") (pinfunction "P$1_P$76") (pintype "power_in"))
      (node (ref "P8") (pin "P$77") (pinfunction "P$1_P$77") (pintype "power_in"))
      (node (ref "P8") (pin "P$78") (pinfunction "P$1_P$78") (pintype "power_in"))
      (node (ref "P8") (pin "P$79") (pinfunction "P$1_P$79") (pintype "power_in"))
      (node (ref "P8") (pin "P$8") (pinfunction "P$1_P$8") (pintype "power_in"))
      (node (ref "P8") (pin "P$80") (pinfunction "P$1_P$80") (pintype "power_in"))
      (node (ref "P8") (pin "P$81") (pinfunction "P$1_P$81") (pintype "power_in"))
      (node (ref "P8") (pin "P$82") (pinfunction "P$1_P$82") (pintype "power_in"))
      (node (ref "P8") (pin "P$83") (pinfunction "P$1_P$83") (pintype "power_in"))
      (node (ref "P8") (pin "P$84") (pinfunction "P$1_P$84") (pintype "power_in"))
      (node (ref "P8") (pin "P$85") (pinfunction "P$1_P$85") (pintype "power_in"))
      (node (ref "P8") (pin "P$86") (pinfunction "P$1_P$86") (pintype "power_in"))
      (node (ref "P8") (pin "P$87") (pinfunction "P$1_P$87") (pintype "power_in"))
      (node (ref "P8") (pin "P$88") (pinfunction "P$1_P$88") (pintype "power_in"))
      (node (ref "P8") (pin "P$89") (pinfunction "P$1_P$89") (pintype "power_in"))
      (node (ref "P8") (pin "P$9") (pinfunction "P$1_P$9") (pintype "power_in"))
      (node (ref "P8") (pin "P$90") (pinfunction "P$1_P$90") (pintype "power_in"))
      (node (ref "P8") (pin "P$91") (pinfunction "P$1_P$91") (pintype "power_in"))
      (node (ref "P8") (pin "P$92") (pinfunction "P$1_P$92") (pintype "power_in"))
      (node (ref "P8") (pin "P$93") (pinfunction "P$1_P$93") (pintype "power_in"))
      (node (ref "P8") (pin "P$94") (pinfunction "P$1_P$94") (pintype "power_in"))
      (node (ref "P8") (pin "P$95") (pinfunction "P$1_P$95") (pintype "power_in"))
      (node (ref "P8") (pin "P$96") (pinfunction "P$1_P$96") (pintype "power_in"))
      (node (ref "P8") (pin "P$97") (pinfunction "P$1_P$97") (pintype "power_in"))
      (node (ref "P8") (pin "P$98") (pinfunction "P$1_P$98") (pintype "power_in"))
      (node (ref "P8") (pin "P$99") (pinfunction "P$1_P$99") (pintype "power_in"))
    )
    (net (code "10") (name "/P9") (class "Default")
      (node (ref "JP1") (pin "P$10") (pinfunction "9_P$10") (pintype "bidirectional"))
      (node (ref "P9") (pin "P$1") (pinfunction "P$1_P$1") (pintype "power_in"))
      (node (ref "P9") (pin "P$10") (pinfunction "P$1_P$10") (pintype "power_in"))
      (node (ref "P9") (pin "P$100") (pinfunction "P$1_P$100") (pintype "power_in"))
      (node (ref "P9") (pin "P$101") (pinfunction "P$1_P$101") (pintype "power_in"))
      (node (ref "P9") (pin "P$102") (pinfunction "P$1_P$102") (pintype "power_in"))
      (node (ref "P9") (pin "P$103") (pinfunction "P$1_P$103") (pintype "power_in"))
      (node (ref "P9") (pin "P$104") (pinfunction "P$1_P$104") (pintype "power_in"))
      (node (ref "P9") (pin "P$105") (pinfunction "P$1_P$105") (pintype "power_in"))
      (node (ref "P9") (pin "P$106") (pinfunction "P$1_P$106") (pintype "power_in"))
      (node (ref "P9") (pin "P$107") (pinfunction "P$1_P$107") (pintype "power_in"))
      (node (ref "P9") (pin "P$108") (pinfunction "P$1_P$108") (pintype "power_in"))
      (node (ref "P9") (pin "P$109") (pinfunction "P$1_P$109") (pintype "power_in"))
      (node (ref "P9") (pin "P$11") (pinfunction "P$1_P$11") (pintype "power_in"))
      (node (ref "P9") (pin "P$110") (pinfunction "P$1_P$110") (pintype "power_in"))
      (node (ref "P9") (pin "P$111") (pinfunction "P$1_P$111") (pintype "power_in"))
      (node (ref "P9") (pin "P$112") (pinfunction "P$1_P$112") (pintype "power_in"))
      (node (ref "P9") (pin "P$113") (pinfunction "P$1_P$113") (pintype "power_in"))
      (node (ref "P9") (pin "P$114") (pinfunction "P$1_P$114") (pintype "power_in"))
      (node (ref "P9") (pin "P$115") (pinfunction "P$1_P$115") (pintype "power_in"))
      (node (ref "P9") (pin "P$116") (pinfunction "P$1_P$116") (pintype "power_in"))
      (node (ref "P9") (pin "P$117") (pinfunction "P$1_P$117") (pintype "power_in"))
      (node (ref "P9") (pin "P$118") (pinfunction "P$1_P$118") (pintype "power_in"))
      (node (ref "P9") (pin "P$119") (pinfunction "P$1_P$119") (pintype "power_in"))
      (node (ref "P9") (pin "P$12") (pinfunction "P$1_P$12") (pintype "power_in"))
      (node (ref "P9") (pin "P$120") (pinfunction "P$1_P$120") (pintype "power_in"))
      (node (ref "P9") (pin "P$121") (pinfunction "P$1_P$121") (pintype "power_in"))
      (node (ref "P9") (pin "P$122") (pinfunction "P$1_P$122") (pintype "power_in"))
      (node (ref "P9") (pin "P$123") (pinfunction "P$1_P$123") (pintype "power_in"))
      (node (ref "P9") (pin "P$124") (pinfunction "P$1_P$124") (pintype "power_in"))
      (node (ref "P9") (pin "P$125") (pinfunction "P$1_P$125") (pintype "power_in"))
      (node (ref "P9") (pin "P$126") (pinfunction "P$1_P$126") (pintype "power_in"))
      (node (ref "P9") (pin "P$127") (pinfunction "P$1_P$127") (pintype "power_in"))
      (node (ref "P9") (pin "P$128") (pinfunction "P$1_P$128") (pintype "power_in"))
      (node (ref "P9") (pin "P$129") (pinfunction "P$1_P$129") (pintype "power_in"))
      (node (ref "P9") (pin "P$13") (pinfunction "P$1_P$13") (pintype "power_in"))
      (node (ref "P9") (pin "P$130") (pinfunction "P$1_P$130") (pintype "power_in"))
      (node (ref "P9") (pin "P$131") (pinfunction "P$1_P$131") (pintype "power_in"))
      (node (ref "P9") (pin "P$132") (pinfunction "P$1_P$132") (pintype "power_in"))
      (node (ref "P9") (pin "P$133") (pinfunction "P$1_P$133") (pintype "power_in"))
      (node (ref "P9") (pin "P$134") (pinfunction "P$1_P$134") (pintype "power_in"))
      (node (ref "P9") (pin "P$135") (pinfunction "P$1_P$135") (pintype "power_in"))
      (node (ref "P9") (pin "P$136") (pinfunction "P$1_P$136") (pintype "power_in"))
      (node (ref "P9") (pin "P$137") (pinfunction "P$1_P$137") (pintype "power_in"))
      (node (ref "P9") (pin "P$138") (pinfunction "P$1_P$138") (pintype "power_in"))
      (node (ref "P9") (pin "P$139") (pinfunction "P$1_P$139") (pintype "power_in"))
      (node (ref "P9") (pin "P$14") (pinfunction "P$1_P$14") (pintype "power_in"))
      (node (ref "P9") (pin "P$140") (pinfunction "P$1_P$140") (pintype "power_in"))
      (node (ref "P9") (pin "P$141") (pinfunction "P$1_P$141") (pintype "power_in"))
      (node (ref "P9") (pin "P$142") (pinfunction "P$1_P$142") (pintype "power_in"))
      (node (ref "P9") (pin "P$143") (pinfunction "P$1_P$143") (pintype "power_in"))
      (node (ref "P9") (pin "P$144") (pinfunction "P$1_P$144") (pintype "power_in"))
      (node (ref "P9") (pin "P$145") (pinfunction "P$1_P$145") (pintype "power_in"))
      (node (ref "P9") (pin "P$146") (pinfunction "P$1_P$146") (pintype "power_in"))
      (node (ref "P9") (pin "P$147") (pinfunction "P$1_P$147") (pintype "power_in"))
      (node (ref "P9") (pin "P$148") (pinfunction "P$1_P$148") (pintype "power_in"))
      (node (ref "P9") (pin "P$149") (pinfunction "P$1_P$149") (pintype "power_in"))
      (node (ref "P9") (pin "P$15") (pinfunction "P$1_P$15") (pintype "power_in"))
      (node (ref "P9") (pin "P$150") (pinfunction "P$1_P$150") (pintype "power_in"))
      (node (ref "P9") (pin "P$151") (pinfunction "P$1_P$151") (pintype "power_in"))
      (node (ref "P9") (pin "P$152") (pinfunction "P$1_P$152") (pintype "power_in"))
      (node (ref "P9") (pin "P$153") (pinfunction "P$1_P$153") (pintype "power_in"))
      (node (ref "P9") (pin "P$154") (pinfunction "P$1_P$154") (pintype "power_in"))
      (node (ref "P9") (pin "P$155") (pinfunction "P$1_P$155") (pintype "power_in"))
      (node (ref "P9") (pin "P$156") (pinfunction "P$1_P$156") (pintype "power_in"))
      (node (ref "P9") (pin "P$157") (pinfunction "P$1_P$157") (pintype "power_in"))
      (node (ref "P9") (pin "P$158") (pinfunction "P$1_P$158") (pintype "power_in"))
      (node (ref "P9") (pin "P$159") (pinfunction "P$1_P$159") (pintype "power_in"))
      (node (ref "P9") (pin "P$16") (pinfunction "P$1_P$16") (pintype "power_in"))
      (node (ref "P9") (pin "P$160") (pinfunction "P$1_P$160") (pintype "power_in"))
      (node (ref "P9") (pin "P$161") (pinfunction "P$1_P$161") (pintype "power_in"))
      (node (ref "P9") (pin "P$162") (pinfunction "P$1_P$162") (pintype "power_in"))
      (node (ref "P9") (pin "P$163") (pinfunction "P$1_P$163") (pintype "power_in"))
      (node (ref "P9") (pin "P$164") (pinfunction "P$1_P$164") (pintype "power_in"))
      (node (ref "P9") (pin "P$165") (pinfunction "P$1_P$165") (pintype "power_in"))
      (node (ref "P9") (pin "P$166") (pinfunction "P$1_P$166") (pintype "power_in"))
      (node (ref "P9") (pin "P$167") (pinfunction "P$1_P$167") (pintype "power_in"))
      (node (ref "P9") (pin "P$168") (pinfunction "P$1_P$168") (pintype "power_in"))
      (node (ref "P9") (pin "P$169") (pinfunction "P$1_P$169") (pintype "power_in"))
      (node (ref "P9") (pin "P$17") (pinfunction "P$1_P$17") (pintype "power_in"))
      (node (ref "P9") (pin "P$170") (pinfunction "P$1_P$170") (pintype "power_in"))
      (node (ref "P9") (pin "P$171") (pinfunction "P$1_P$171") (pintype "power_in"))
      (node (ref "P9") (pin "P$172") (pinfunction "P$1_P$172") (pintype "power_in"))
      (node (ref "P9") (pin "P$173") (pinfunction "P$1_P$173") (pintype "power_in"))
      (node (ref "P9") (pin "P$174") (pinfunction "P$1_P$174") (pintype "power_in"))
      (node (ref "P9") (pin "P$175") (pinfunction "P$1_P$175") (pintype "power_in"))
      (node (ref "P9") (pin "P$176") (pinfunction "P$1_P$176") (pintype "power_in"))
      (node (ref "P9") (pin "P$177") (pinfunction "P$1_P$177") (pintype "power_in"))
      (node (ref "P9") (pin "P$178") (pinfunction "P$1_P$178") (pintype "power_in"))
      (node (ref "P9") (pin "P$179") (pinfunction "P$1_P$179") (pintype "power_in"))
      (node (ref "P9") (pin "P$18") (pinfunction "P$1_P$18") (pintype "power_in"))
      (node (ref "P9") (pin "P$180") (pinfunction "P$1_P$180") (pintype "power_in"))
      (node (ref "P9") (pin "P$181") (pinfunction "P$1_P$181") (pintype "power_in"))
      (node (ref "P9") (pin "P$182") (pinfunction "P$1_P$182") (pintype "power_in"))
      (node (ref "P9") (pin "P$183") (pinfunction "P$1_P$183") (pintype "power_in"))
      (node (ref "P9") (pin "P$184") (pinfunction "P$1_P$184") (pintype "power_in"))
      (node (ref "P9") (pin "P$185") (pinfunction "P$1_P$185") (pintype "power_in"))
      (node (ref "P9") (pin "P$186") (pinfunction "P$1_P$186") (pintype "power_in"))
      (node (ref "P9") (pin "P$187") (pinfunction "P$1_P$187") (pintype "power_in"))
      (node (ref "P9") (pin "P$188") (pinfunction "P$1_P$188") (pintype "power_in"))
      (node (ref "P9") (pin "P$189") (pinfunction "P$1_P$189") (pintype "power_in"))
      (node (ref "P9") (pin "P$19") (pinfunction "P$1_P$19") (pintype "power_in"))
      (node (ref "P9") (pin "P$190") (pinfunction "P$1_P$190") (pintype "power_in"))
      (node (ref "P9") (pin "P$191") (pinfunction "P$1_P$191") (pintype "power_in"))
      (node (ref "P9") (pin "P$192") (pinfunction "P$1_P$192") (pintype "power_in"))
      (node (ref "P9") (pin "P$193") (pinfunction "P$1_P$193") (pintype "power_in"))
      (node (ref "P9") (pin "P$194") (pinfunction "P$1_P$194") (pintype "power_in"))
      (node (ref "P9") (pin "P$195") (pinfunction "P$1_P$195") (pintype "power_in"))
      (node (ref "P9") (pin "P$196") (pinfunction "P$1_P$196") (pintype "power_in"))
      (node (ref "P9") (pin "P$197") (pinfunction "P$1_P$197") (pintype "power_in"))
      (node (ref "P9") (pin "P$198") (pinfunction "P$1_P$198") (pintype "power_in"))
      (node (ref "P9") (pin "P$199") (pinfunction "P$1_P$199") (pintype "power_in"))
      (node (ref "P9") (pin "P$2") (pinfunction "P$1_P$2") (pintype "power_in"))
      (node (ref "P9") (pin "P$20") (pinfunction "P$1_P$20") (pintype "power_in"))
      (node (ref "P9") (pin "P$200") (pinfunction "P$1_P$200") (pintype "power_in"))
      (node (ref "P9") (pin "P$201") (pinfunction "P$1_P$201") (pintype "power_in"))
      (node (ref "P9") (pin "P$202") (pinfunction "P$1_P$202") (pintype "power_in"))
      (node (ref "P9") (pin "P$203") (pinfunction "P$1_P$203") (pintype "power_in"))
      (node (ref "P9") (pin "P$204") (pinfunction "P$1_P$204") (pintype "power_in"))
      (node (ref "P9") (pin "P$205") (pinfunction "P$1_P$205") (pintype "power_in"))
      (node (ref "P9") (pin "P$206") (pinfunction "P$1_P$206") (pintype "power_in"))
      (node (ref "P9") (pin "P$207") (pinfunction "P$1_P$207") (pintype "power_in"))
      (node (ref "P9") (pin "P$208") (pinfunction "P$1_P$208") (pintype "power_in"))
      (node (ref "P9") (pin "P$209") (pinfunction "P$1_P$209") (pintype "power_in"))
      (node (ref "P9") (pin "P$21") (pinfunction "P$1_P$21") (pintype "power_in"))
      (node (ref "P9") (pin "P$210") (pinfunction "P$1_P$210") (pintype "power_in"))
      (node (ref "P9") (pin "P$211") (pinfunction "P$1_P$211") (pintype "power_in"))
      (node (ref "P9") (pin "P$212") (pinfunction "P$1_P$212") (pintype "power_in"))
      (node (ref "P9") (pin "P$213") (pinfunction "P$1_P$213") (pintype "power_in"))
      (node (ref "P9") (pin "P$214") (pinfunction "P$1_P$214") (pintype "power_in"))
      (node (ref "P9") (pin "P$215") (pinfunction "P$1_P$215") (pintype "power_in"))
      (node (ref "P9") (pin "P$216") (pinfunction "P$1_P$216") (pintype "power_in"))
      (node (ref "P9") (pin "P$217") (pinfunction "P$1_P$217") (pintype "power_in"))
      (node (ref "P9") (pin "P$218") (pinfunction "P$1_P$218") (pintype "power_in"))
      (node (ref "P9") (pin "P$219") (pinfunction "P$1_P$219") (pintype "power_in"))
      (node (ref "P9") (pin "P$22") (pinfunction "P$1_P$22") (pintype "power_in"))
      (node (ref "P9") (pin "P$220") (pinfunction "P$1_P$220") (pintype "power_in"))
      (node (ref "P9") (pin "P$221") (pinfunction "P$1_P$221") (pintype "power_in"))
      (node (ref "P9") (pin "P$222") (pinfunction "P$1_P$222") (pintype "power_in"))
      (node (ref "P9") (pin "P$223") (pinfunction "P$1_P$223") (pintype "power_in"))
      (node (ref "P9") (pin "P$224") (pinfunction "P$1_P$224") (pintype "power_in"))
      (node (ref "P9") (pin "P$225") (pinfunction "P$1_P$225") (pintype "power_in"))
      (node (ref "P9") (pin "P$226") (pinfunction "P$1_P$226") (pintype "power_in"))
      (node (ref "P9") (pin "P$227") (pinfunction "P$1_P$227") (pintype "power_in"))
      (node (ref "P9") (pin "P$228") (pinfunction "P$1_P$228") (pintype "power_in"))
      (node (ref "P9") (pin "P$229") (pinfunction "P$1_P$229") (pintype "power_in"))
      (node (ref "P9") (pin "P$23") (pinfunction "P$1_P$23") (pintype "power_in"))
      (node (ref "P9") (pin "P$230") (pinfunction "P$1_P$230") (pintype "power_in"))
      (node (ref "P9") (pin "P$231") (pinfunction "P$1_P$231") (pintype "power_in"))
      (node (ref "P9") (pin "P$232") (pinfunction "P$1_P$232") (pintype "power_in"))
      (node (ref "P9") (pin "P$233") (pinfunction "P$1_P$233") (pintype "power_in"))
      (node (ref "P9") (pin "P$234") (pinfunction "P$1_P$234") (pintype "power_in"))
      (node (ref "P9") (pin "P$235") (pinfunction "P$1_P$235") (pintype "power_in"))
      (node (ref "P9") (pin "P$236") (pinfunction "P$1_P$236") (pintype "power_in"))
      (node (ref "P9") (pin "P$237") (pinfunction "P$1_P$237") (pintype "power_in"))
      (node (ref "P9") (pin "P$238") (pinfunction "P$1_P$238") (pintype "power_in"))
      (node (ref "P9") (pin "P$239") (pinfunction "P$1_P$239") (pintype "power_in"))
      (node (ref "P9") (pin "P$24") (pinfunction "P$1_P$24") (pintype "power_in"))
      (node (ref "P9") (pin "P$240") (pinfunction "P$1_P$240") (pintype "power_in"))
      (node (ref "P9") (pin "P$241") (pinfunction "P$1_P$241") (pintype "power_in"))
      (node (ref "P9") (pin "P$242") (pinfunction "P$1_P$242") (pintype "power_in"))
      (node (ref "P9") (pin "P$243") (pinfunction "P$1_P$243") (pintype "power_in"))
      (node (ref "P9") (pin "P$244") (pinfunction "P$1_P$244") (pintype "power_in"))
      (node (ref "P9") (pin "P$245") (pinfunction "P$1_P$245") (pintype "power_in"))
      (node (ref "P9") (pin "P$246") (pinfunction "P$1_P$246") (pintype "power_in"))
      (node (ref "P9") (pin "P$247") (pinfunction "P$1_P$247") (pintype "power_in"))
      (node (ref "P9") (pin "P$248") (pinfunction "P$1_P$248") (pintype "power_in"))
      (node (ref "P9") (pin "P$249") (pinfunction "P$1_P$249") (pintype "power_in"))
      (node (ref "P9") (pin "P$25") (pinfunction "P$1_P$25") (pintype "power_in"))
      (node (ref "P9") (pin "P$250") (pinfunction "P$1_P$250") (pintype "power_in"))
      (node (ref "P9") (pin "P$251") (pinfunction "P$1_P$251") (pintype "power_in"))
      (node (ref "P9") (pin "P$252") (pinfunction "P$1_P$252") (pintype "power_in"))
      (node (ref "P9") (pin "P$253") (pinfunction "P$1_P$253") (pintype "power_in"))
      (node (ref "P9") (pin "P$254") (pinfunction "P$1_P$254") (pintype "power_in"))
      (node (ref "P9") (pin "P$255") (pinfunction "P$1_P$255") (pintype "power_in"))
      (node (ref "P9") (pin "P$256") (pinfunction "P$1_P$256") (pintype "power_in"))
      (node (ref "P9") (pin "P$257") (pinfunction "P$1_P$257") (pintype "power_in"))
      (node (ref "P9") (pin "P$258") (pinfunction "P$1_P$258") (pintype "power_in"))
      (node (ref "P9") (pin "P$259") (pinfunction "P$1_P$259") (pintype "power_in"))
      (node (ref "P9") (pin "P$26") (pinfunction "P$1_P$26") (pintype "power_in"))
      (node (ref "P9") (pin "P$260") (pinfunction "P$1_P$260") (pintype "power_in"))
      (node (ref "P9") (pin "P$261") (pinfunction "P$1_P$261") (pintype "power_in"))
      (node (ref "P9") (pin "P$262") (pinfunction "P$1_P$262") (pintype "power_in"))
      (node (ref "P9") (pin "P$263") (pinfunction "P$1_P$263") (pintype "power_in"))
      (node (ref "P9") (pin "P$264") (pinfunction "P$1_P$264") (pintype "power_in"))
      (node (ref "P9") (pin "P$265") (pinfunction "P$1_P$265") (pintype "power_in"))
      (node (ref "P9") (pin "P$266") (pinfunction "P$1_P$266") (pintype "power_in"))
      (node (ref "P9") (pin "P$267") (pinfunction "P$1_P$267") (pintype "power_in"))
      (node (ref "P9") (pin "P$268") (pinfunction "P$1_P$268") (pintype "power_in"))
      (node (ref "P9") (pin "P$269") (pinfunction "P$1_P$269") (pintype "power_in"))
      (node (ref "P9") (pin "P$27") (pinfunction "P$1_P$27") (pintype "power_in"))
      (node (ref "P9") (pin "P$270") (pinfunction "P$1_P$270") (pintype "power_in"))
      (node (ref "P9") (pin "P$271") (pinfunction "P$1_P$271") (pintype "power_in"))
      (node (ref "P9") (pin "P$272") (pinfunction "P$1_P$272") (pintype "power_in"))
      (node (ref "P9") (pin "P$273") (pinfunction "P$1_P$273") (pintype "power_in"))
      (node (ref "P9") (pin "P$274") (pinfunction "P$1_P$274") (pintype "power_in"))
      (node (ref "P9") (pin "P$275") (pinfunction "P$1_P$275") (pintype "power_in"))
      (node (ref "P9") (pin "P$276") (pinfunction "P$1_P$276") (pintype "power_in"))
      (node (ref "P9") (pin "P$277") (pinfunction "P$1_P$277") (pintype "power_in"))
      (node (ref "P9") (pin "P$278") (pinfunction "P$1_P$278") (pintype "power_in"))
      (node (ref "P9") (pin "P$279") (pinfunction "P$1_P$279") (pintype "power_in"))
      (node (ref "P9") (pin "P$28") (pinfunction "P$1_P$28") (pintype "power_in"))
      (node (ref "P9") (pin "P$280") (pinfunction "P$1_P$280") (pintype "power_in"))
      (node (ref "P9") (pin "P$281") (pinfunction "P$1_P$281") (pintype "power_in"))
      (node (ref "P9") (pin "P$282") (pinfunction "P$1_P$282") (pintype "power_in"))
      (node (ref "P9") (pin "P$283") (pinfunction "P$1_P$283") (pintype "power_in"))
      (node (ref "P9") (pin "P$284") (pinfunction "P$1_P$284") (pintype "power_in"))
      (node (ref "P9") (pin "P$285") (pinfunction "P$1_P$285") (pintype "power_in"))
      (node (ref "P9") (pin "P$286") (pinfunction "P$1_P$286") (pintype "power_in"))
      (node (ref "P9") (pin "P$287") (pinfunction "P$1_P$287") (pintype "power_in"))
      (node (ref "P9") (pin "P$288") (pinfunction "P$1_P$288") (pintype "power_in"))
      (node (ref "P9") (pin "P$29") (pinfunction "P$1_P$29") (pintype "power_in"))
      (node (ref "P9") (pin "P$3") (pinfunction "P$1_P$3") (pintype "power_in"))
      (node (ref "P9") (pin "P$30") (pinfunction "P$1_P$30") (pintype "power_in"))
      (node (ref "P9") (pin "P$31") (pinfunction "P$1_P$31") (pintype "power_in"))
      (node (ref "P9") (pin "P$32") (pinfunction "P$1_P$32") (pintype "power_in"))
      (node (ref "P9") (pin "P$33") (pinfunction "P$1_P$33") (pintype "power_in"))
      (node (ref "P9") (pin "P$34") (pinfunction "P$1_P$34") (pintype "power_in"))
      (node (ref "P9") (pin "P$35") (pinfunction "P$1_P$35") (pintype "power_in"))
      (node (ref "P9") (pin "P$36") (pinfunction "P$1_P$36") (pintype "power_in"))
      (node (ref "P9") (pin "P$37") (pinfunction "P$1_P$37") (pintype "power_in"))
      (node (ref "P9") (pin "P$38") (pinfunction "P$1_P$38") (pintype "power_in"))
      (node (ref "P9") (pin "P$39") (pinfunction "P$1_P$39") (pintype "power_in"))
      (node (ref "P9") (pin "P$4") (pinfunction "P$1_P$4") (pintype "power_in"))
      (node (ref "P9") (pin "P$40") (pinfunction "P$1_P$40") (pintype "power_in"))
      (node (ref "P9") (pin "P$41") (pinfunction "P$1_P$41") (pintype "power_in"))
      (node (ref "P9") (pin "P$42") (pinfunction "P$1_P$42") (pintype "power_in"))
      (node (ref "P9") (pin "P$43") (pinfunction "P$1_P$43") (pintype "power_in"))
      (node (ref "P9") (pin "P$44") (pinfunction "P$1_P$44") (pintype "power_in"))
      (node (ref "P9") (pin "P$45") (pinfunction "P$1_P$45") (pintype "power_in"))
      (node (ref "P9") (pin "P$46") (pinfunction "P$1_P$46") (pintype "power_in"))
      (node (ref "P9") (pin "P$47") (pinfunction "P$1_P$47") (pintype "power_in"))
      (node (ref "P9") (pin "P$48") (pinfunction "P$1_P$48") (pintype "power_in"))
      (node (ref "P9") (pin "P$49") (pinfunction "P$1_P$49") (pintype "power_in"))
      (node (ref "P9") (pin "P$5") (pinfunction "P$1_P$5") (pintype "power_in"))
      (node (ref "P9") (pin "P$50") (pinfunction "P$1_P$50") (pintype "power_in"))
      (node (ref "P9") (pin "P$51") (pinfunction "P$1_P$51") (pintype "power_in"))
      (node (ref "P9") (pin "P$52") (pinfunction "P$1_P$52") (pintype "power_in"))
      (node (ref "P9") (pin "P$53") (pinfunction "P$1_P$53") (pintype "power_in"))
      (node (ref "P9") (pin "P$54") (pinfunction "P$1_P$54") (pintype "power_in"))
      (node (ref "P9") (pin "P$55") (pinfunction "P$1_P$55") (pintype "power_in"))
      (node (ref "P9") (pin "P$56") (pinfunction "P$1_P$56") (pintype "power_in"))
      (node (ref "P9") (pin "P$57") (pinfunction "P$1_P$57") (pintype "power_in"))
      (node (ref "P9") (pin "P$58") (pinfunction "P$1_P$58") (pintype "power_in"))
      (node (ref "P9") (pin "P$59") (pinfunction "P$1_P$59") (pintype "power_in"))
      (node (ref "P9") (pin "P$6") (pinfunction "P$1_P$6") (pintype "power_in"))
      (node (ref "P9") (pin "P$60") (pinfunction "P$1_P$60") (pintype "power_in"))
      (node (ref "P9") (pin "P$61") (pinfunction "P$1_P$61") (pintype "power_in"))
      (node (ref "P9") (pin "P$62") (pinfunction "P$1_P$62") (pintype "power_in"))
      (node (ref "P9") (pin "P$63") (pinfunction "P$1_P$63") (pintype "power_in"))
      (node (ref "P9") (pin "P$64") (pinfunction "P$1_P$64") (pintype "power_in"))
      (node (ref "P9") (pin "P$65") (pinfunction "P$1_P$65") (pintype "power_in"))
      (node (ref "P9") (pin "P$66") (pinfunction "P$1_P$66") (pintype "power_in"))
      (node (ref "P9") (pin "P$67") (pinfunction "P$1_P$67") (pintype "power_in"))
      (node (ref "P9") (pin "P$68") (pinfunction "P$1_P$68") (pintype "power_in"))
      (node (ref "P9") (pin "P$69") (pinfunction "P$1_P$69") (pintype "power_in"))
      (node (ref "P9") (pin "P$7") (pinfunction "P$1_P$7") (pintype "power_in"))
      (node (ref "P9") (pin "P$70") (pinfunction "P$1_P$70") (pintype "power_in"))
      (node (ref "P9") (pin "P$71") (pinfunction "P$1_P$71") (pintype "power_in"))
      (node (ref "P9") (pin "P$72") (pinfunction "P$1_P$72") (pintype "power_in"))
      (node (ref "P9") (pin "P$73") (pinfunction "P$1_P$73") (pintype "power_in"))
      (node (ref "P9") (pin "P$74") (pinfunction "P$1_P$74") (pintype "power_in"))
      (node (ref "P9") (pin "P$75") (pinfunction "P$1_P$75") (pintype "power_in"))
      (node (ref "P9") (pin "P$76") (pinfunction "P$1_P$76") (pintype "power_in"))
      (node (ref "P9") (pin "P$77") (pinfunction "P$1_P$77") (pintype "power_in"))
      (node (ref "P9") (pin "P$78") (pinfunction "P$1_P$78") (pintype "power_in"))
      (node (ref "P9") (pin "P$79") (pinfunction "P$1_P$79") (pintype "power_in"))
      (node (ref "P9") (pin "P$8") (pinfunction "P$1_P$8") (pintype "power_in"))
      (node (ref "P9") (pin "P$80") (pinfunction "P$1_P$80") (pintype "power_in"))
      (node (ref "P9") (pin "P$81") (pinfunction "P$1_P$81") (pintype "power_in"))
      (node (ref "P9") (pin "P$82") (pinfunction "P$1_P$82") (pintype "power_in"))
      (node (ref "P9") (pin "P$83") (pinfunction "P$1_P$83") (pintype "power_in"))
      (node (ref "P9") (pin "P$84") (pinfunction "P$1_P$84") (pintype "power_in"))
      (node (ref "P9") (pin "P$85") (pinfunction "P$1_P$85") (pintype "power_in"))
      (node (ref "P9") (pin "P$86") (pinfunction "P$1_P$86") (pintype "power_in"))
      (node (ref "P9") (pin "P$87") (pinfunction "P$1_P$87") (pintype "power_in"))
      (node (ref "P9") (pin "P$88") (pinfunction "P$1_P$88") (pintype "power_in"))
      (node (ref "P9") (pin "P$89") (pinfunction "P$1_P$89") (pintype "power_in"))
      (node (ref "P9") (pin "P$9") (pinfunction "P$1_P$9") (pintype "power_in"))
      (node (ref "P9") (pin "P$90") (pinfunction "P$1_P$90") (pintype "power_in"))
      (node (ref "P9") (pin "P$91") (pinfunction "P$1_P$91") (pintype "power_in"))
      (node (ref "P9") (pin "P$92") (pinfunction "P$1_P$92") (pintype "power_in"))
      (node (ref "P9") (pin "P$93") (pinfunction "P$1_P$93") (pintype "power_in"))
      (node (ref "P9") (pin "P$94") (pinfunction "P$1_P$94") (pintype "power_in"))
      (node (ref "P9") (pin "P$95") (pinfunction "P$1_P$95") (pintype "power_in"))
      (node (ref "P9") (pin "P$96") (pinfunction "P$1_P$96") (pintype "power_in"))
      (node (ref "P9") (pin "P$97") (pinfunction "P$1_P$97") (pintype "power_in"))
      (node (ref "P9") (pin "P$98") (pinfunction "P$1_P$98") (pintype "power_in"))
      (node (ref "P9") (pin "P$99") (pinfunction "P$1_P$99") (pintype "power_in"))
    )
    (net (code "11") (name "/P10") (class "Default")
      (node (ref "JP1") (pin "P$11") (pinfunction "10_P$11") (pintype "bidirectional"))
      (node (ref "P10") (pin "P$1") (pinfunction "P$1_P$1") (pintype "power_in"))
      (node (ref "P10") (pin "P$10") (pinfunction "P$1_P$10") (pintype "power_in"))
      (node (ref "P10") (pin "P$100") (pinfunction "P$1_P$100") (pintype "power_in"))
      (node (ref "P10") (pin "P$101") (pinfunction "P$1_P$101") (pintype "power_in"))
      (node (ref "P10") (pin "P$102") (pinfunction "P$1_P$102") (pintype "power_in"))
      (node (ref "P10") (pin "P$103") (pinfunction "P$1_P$103") (pintype "power_in"))
      (node (ref "P10") (pin "P$104") (pinfunction "P$1_P$104") (pintype "power_in"))
      (node (ref "P10") (pin "P$105") (pinfunction "P$1_P$105") (pintype "power_in"))
      (node (ref "P10") (pin "P$106") (pinfunction "P$1_P$106") (pintype "power_in"))
      (node (ref "P10") (pin "P$107") (pinfunction "P$1_P$107") (pintype "power_in"))
      (node (ref "P10") (pin "P$108") (pinfunction "P$1_P$108") (pintype "power_in"))
      (node (ref "P10") (pin "P$109") (pinfunction "P$1_P$109") (pintype "power_in"))
      (node (ref "P10") (pin "P$11") (pinfunction "P$1_P$11") (pintype "power_in"))
      (node (ref "P10") (pin "P$110") (pinfunction "P$1_P$110") (pintype "power_in"))
      (node (ref "P10") (pin "P$111") (pinfunction "P$1_P$111") (pintype "power_in"))
      (node (ref "P10") (pin "P$112") (pinfunction "P$1_P$112") (pintype "power_in"))
      (node (ref "P10") (pin "P$113") (pinfunction "P$1_P$113") (pintype "power_in"))
      (node (ref "P10") (pin "P$114") (pinfunction "P$1_P$114") (pintype "power_in"))
      (node (ref "P10") (pin "P$115") (pinfunction "P$1_P$115") (pintype "power_in"))
      (node (ref "P10") (pin "P$116") (pinfunction "P$1_P$116") (pintype "power_in"))
      (node (ref "P10") (pin "P$117") (pinfunction "P$1_P$117") (pintype "power_in"))
      (node (ref "P10") (pin "P$118") (pinfunction "P$1_P$118") (pintype "power_in"))
      (node (ref "P10") (pin "P$119") (pinfunction "P$1_P$119") (pintype "power_in"))
      (node (ref "P10") (pin "P$12") (pinfunction "P$1_P$12") (pintype "power_in"))
      (node (ref "P10") (pin "P$120") (pinfunction "P$1_P$120") (pintype "power_in"))
      (node (ref "P10") (pin "P$121") (pinfunction "P$1_P$121") (pintype "power_in"))
      (node (ref "P10") (pin "P$122") (pinfunction "P$1_P$122") (pintype "power_in"))
      (node (ref "P10") (pin "P$123") (pinfunction "P$1_P$123") (pintype "power_in"))
      (node (ref "P10") (pin "P$124") (pinfunction "P$1_P$124") (pintype "power_in"))
      (node (ref "P10") (pin "P$125") (pinfunction "P$1_P$125") (pintype "power_in"))
      (node (ref "P10") (pin "P$126") (pinfunction "P$1_P$126") (pintype "power_in"))
      (node (ref "P10") (pin "P$127") (pinfunction "P$1_P$127") (pintype "power_in"))
      (node (ref "P10") (pin "P$128") (pinfunction "P$1_P$128") (pintype "power_in"))
      (node (ref "P10") (pin "P$129") (pinfunction "P$1_P$129") (pintype "power_in"))
      (node (ref "P10") (pin "P$13") (pinfunction "P$1_P$13") (pintype "power_in"))
      (node (ref "P10") (pin "P$130") (pinfunction "P$1_P$130") (pintype "power_in"))
      (node (ref "P10") (pin "P$131") (pinfunction "P$1_P$131") (pintype "power_in"))
      (node (ref "P10") (pin "P$132") (pinfunction "P$1_P$132") (pintype "power_in"))
      (node (ref "P10") (pin "P$133") (pinfunction "P$1_P$133") (pintype "power_in"))
      (node (ref "P10") (pin "P$134") (pinfunction "P$1_P$134") (pintype "power_in"))
      (node (ref "P10") (pin "P$135") (pinfunction "P$1_P$135") (pintype "power_in"))
      (node (ref "P10") (pin "P$136") (pinfunction "P$1_P$136") (pintype "power_in"))
      (node (ref "P10") (pin "P$137") (pinfunction "P$1_P$137") (pintype "power_in"))
      (node (ref "P10") (pin "P$138") (pinfunction "P$1_P$138") (pintype "power_in"))
      (node (ref "P10") (pin "P$139") (pinfunction "P$1_P$139") (pintype "power_in"))
      (node (ref "P10") (pin "P$14") (pinfunction "P$1_P$14") (pintype "power_in"))
      (node (ref "P10") (pin "P$140") (pinfunction "P$1_P$140") (pintype "power_in"))
      (node (ref "P10") (pin "P$141") (pinfunction "P$1_P$141") (pintype "power_in"))
      (node (ref "P10") (pin "P$142") (pinfunction "P$1_P$142") (pintype "power_in"))
      (node (ref "P10") (pin "P$143") (pinfunction "P$1_P$143") (pintype "power_in"))
      (node (ref "P10") (pin "P$144") (pinfunction "P$1_P$144") (pintype "power_in"))
      (node (ref "P10") (pin "P$145") (pinfunction "P$1_P$145") (pintype "power_in"))
      (node (ref "P10") (pin "P$146") (pinfunction "P$1_P$146") (pintype "power_in"))
      (node (ref "P10") (pin "P$147") (pinfunction "P$1_P$147") (pintype "power_in"))
      (node (ref "P10") (pin "P$148") (pinfunction "P$1_P$148") (pintype "power_in"))
      (node (ref "P10") (pin "P$149") (pinfunction "P$1_P$149") (pintype "power_in"))
      (node (ref "P10") (pin "P$15") (pinfunction "P$1_P$15") (pintype "power_in"))
      (node (ref "P10") (pin "P$150") (pinfunction "P$1_P$150") (pintype "power_in"))
      (node (ref "P10") (pin "P$151") (pinfunction "P$1_P$151") (pintype "power_in"))
      (node (ref "P10") (pin "P$152") (pinfunction "P$1_P$152") (pintype "power_in"))
      (node (ref "P10") (pin "P$153") (pinfunction "P$1_P$153") (pintype "power_in"))
      (node (ref "P10") (pin "P$154") (pinfunction "P$1_P$154") (pintype "power_in"))
      (node (ref "P10") (pin "P$155") (pinfunction "P$1_P$155") (pintype "power_in"))
      (node (ref "P10") (pin "P$156") (pinfunction "P$1_P$156") (pintype "power_in"))
      (node (ref "P10") (pin "P$157") (pinfunction "P$1_P$157") (pintype "power_in"))
      (node (ref "P10") (pin "P$158") (pinfunction "P$1_P$158") (pintype "power_in"))
      (node (ref "P10") (pin "P$159") (pinfunction "P$1_P$159") (pintype "power_in"))
      (node (ref "P10") (pin "P$16") (pinfunction "P$1_P$16") (pintype "power_in"))
      (node (ref "P10") (pin "P$160") (pinfunction "P$1_P$160") (pintype "power_in"))
      (node (ref "P10") (pin "P$161") (pinfunction "P$1_P$161") (pintype "power_in"))
      (node (ref "P10") (pin "P$162") (pinfunction "P$1_P$162") (pintype "power_in"))
      (node (ref "P10") (pin "P$163") (pinfunction "P$1_P$163") (pintype "power_in"))
      (node (ref "P10") (pin "P$164") (pinfunction "P$1_P$164") (pintype "power_in"))
      (node (ref "P10") (pin "P$165") (pinfunction "P$1_P$165") (pintype "power_in"))
      (node (ref "P10") (pin "P$166") (pinfunction "P$1_P$166") (pintype "power_in"))
      (node (ref "P10") (pin "P$167") (pinfunction "P$1_P$167") (pintype "power_in"))
      (node (ref "P10") (pin "P$168") (pinfunction "P$1_P$168") (pintype "power_in"))
      (node (ref "P10") (pin "P$169") (pinfunction "P$1_P$169") (pintype "power_in"))
      (node (ref "P10") (pin "P$17") (pinfunction "P$1_P$17") (pintype "power_in"))
      (node (ref "P10") (pin "P$170") (pinfunction "P$1_P$170") (pintype "power_in"))
      (node (ref "P10") (pin "P$171") (pinfunction "P$1_P$171") (pintype "power_in"))
      (node (ref "P10") (pin "P$172") (pinfunction "P$1_P$172") (pintype "power_in"))
      (node (ref "P10") (pin "P$173") (pinfunction "P$1_P$173") (pintype "power_in"))
      (node (ref "P10") (pin "P$174") (pinfunction "P$1_P$174") (pintype "power_in"))
      (node (ref "P10") (pin "P$175") (pinfunction "P$1_P$175") (pintype "power_in"))
      (node (ref "P10") (pin "P$176") (pinfunction "P$1_P$176") (pintype "power_in"))
      (node (ref "P10") (pin "P$177") (pinfunction "P$1_P$177") (pintype "power_in"))
      (node (ref "P10") (pin "P$178") (pinfunction "P$1_P$178") (pintype "power_in"))
      (node (ref "P10") (pin "P$179") (pinfunction "P$1_P$179") (pintype "power_in"))
      (node (ref "P10") (pin "P$18") (pinfunction "P$1_P$18") (pintype "power_in"))
      (node (ref "P10") (pin "P$180") (pinfunction "P$1_P$180") (pintype "power_in"))
      (node (ref "P10") (pin "P$181") (pinfunction "P$1_P$181") (pintype "power_in"))
      (node (ref "P10") (pin "P$182") (pinfunction "P$1_P$182") (pintype "power_in"))
      (node (ref "P10") (pin "P$183") (pinfunction "P$1_P$183") (pintype "power_in"))
      (node (ref "P10") (pin "P$184") (pinfunction "P$1_P$184") (pintype "power_in"))
      (node (ref "P10") (pin "P$185") (pinfunction "P$1_P$185") (pintype "power_in"))
      (node (ref "P10") (pin "P$186") (pinfunction "P$1_P$186") (pintype "power_in"))
      (node (ref "P10") (pin "P$187") (pinfunction "P$1_P$187") (pintype "power_in"))
      (node (ref "P10") (pin "P$188") (pinfunction "P$1_P$188") (pintype "power_in"))
      (node (ref "P10") (pin "P$189") (pinfunction "P$1_P$189") (pintype "power_in"))
      (node (ref "P10") (pin "P$19") (pinfunction "P$1_P$19") (pintype "power_in"))
      (node (ref "P10") (pin "P$190") (pinfunction "P$1_P$190") (pintype "power_in"))
      (node (ref "P10") (pin "P$191") (pinfunction "P$1_P$191") (pintype "power_in"))
      (node (ref "P10") (pin "P$192") (pinfunction "P$1_P$192") (pintype "power_in"))
      (node (ref "P10") (pin "P$193") (pinfunction "P$1_P$193") (pintype "power_in"))
      (node (ref "P10") (pin "P$194") (pinfunction "P$1_P$194") (pintype "power_in"))
      (node (ref "P10") (pin "P$195") (pinfunction "P$1_P$195") (pintype "power_in"))
      (node (ref "P10") (pin "P$196") (pinfunction "P$1_P$196") (pintype "power_in"))
      (node (ref "P10") (pin "P$197") (pinfunction "P$1_P$197") (pintype "power_in"))
      (node (ref "P10") (pin "P$198") (pinfunction "P$1_P$198") (pintype "power_in"))
      (node (ref "P10") (pin "P$199") (pinfunction "P$1_P$199") (pintype "power_in"))
      (node (ref "P10") (pin "P$2") (pinfunction "P$1_P$2") (pintype "power_in"))
      (node (ref "P10") (pin "P$20") (pinfunction "P$1_P$20") (pintype "power_in"))
      (node (ref "P10") (pin "P$200") (pinfunction "P$1_P$200") (pintype "power_in"))
      (node (ref "P10") (pin "P$201") (pinfunction "P$1_P$201") (pintype "power_in"))
      (node (ref "P10") (pin "P$202") (pinfunction "P$1_P$202") (pintype "power_in"))
      (node (ref "P10") (pin "P$203") (pinfunction "P$1_P$203") (pintype "power_in"))
      (node (ref "P10") (pin "P$204") (pinfunction "P$1_P$204") (pintype "power_in"))
      (node (ref "P10") (pin "P$205") (pinfunction "P$1_P$205") (pintype "power_in"))
      (node (ref "P10") (pin "P$206") (pinfunction "P$1_P$206") (pintype "power_in"))
      (node (ref "P10") (pin "P$207") (pinfunction "P$1_P$207") (pintype "power_in"))
      (node (ref "P10") (pin "P$208") (pinfunction "P$1_P$208") (pintype "power_in"))
      (node (ref "P10") (pin "P$209") (pinfunction "P$1_P$209") (pintype "power_in"))
      (node (ref "P10") (pin "P$21") (pinfunction "P$1_P$21") (pintype "power_in"))
      (node (ref "P10") (pin "P$210") (pinfunction "P$1_P$210") (pintype "power_in"))
      (node (ref "P10") (pin "P$211") (pinfunction "P$1_P$211") (pintype "power_in"))
      (node (ref "P10") (pin "P$212") (pinfunction "P$1_P$212") (pintype "power_in"))
      (node (ref "P10") (pin "P$213") (pinfunction "P$1_P$213") (pintype "power_in"))
      (node (ref "P10") (pin "P$214") (pinfunction "P$1_P$214") (pintype "power_in"))
      (node (ref "P10") (pin "P$215") (pinfunction "P$1_P$215") (pintype "power_in"))
      (node (ref "P10") (pin "P$216") (pinfunction "P$1_P$216") (pintype "power_in"))
      (node (ref "P10") (pin "P$217") (pinfunction "P$1_P$217") (pintype "power_in"))
      (node (ref "P10") (pin "P$218") (pinfunction "P$1_P$218") (pintype "power_in"))
      (node (ref "P10") (pin "P$219") (pinfunction "P$1_P$219") (pintype "power_in"))
      (node (ref "P10") (pin "P$22") (pinfunction "P$1_P$22") (pintype "power_in"))
      (node (ref "P10") (pin "P$220") (pinfunction "P$1_P$220") (pintype "power_in"))
      (node (ref "P10") (pin "P$221") (pinfunction "P$1_P$221") (pintype "power_in"))
      (node (ref "P10") (pin "P$222") (pinfunction "P$1_P$222") (pintype "power_in"))
      (node (ref "P10") (pin "P$223") (pinfunction "P$1_P$223") (pintype "power_in"))
      (node (ref "P10") (pin "P$224") (pinfunction "P$1_P$224") (pintype "power_in"))
      (node (ref "P10") (pin "P$225") (pinfunction "P$1_P$225") (pintype "power_in"))
      (node (ref "P10") (pin "P$226") (pinfunction "P$1_P$226") (pintype "power_in"))
      (node (ref "P10") (pin "P$227") (pinfunction "P$1_P$227") (pintype "power_in"))
      (node (ref "P10") (pin "P$228") (pinfunction "P$1_P$228") (pintype "power_in"))
      (node (ref "P10") (pin "P$229") (pinfunction "P$1_P$229") (pintype "power_in"))
      (node (ref "P10") (pin "P$23") (pinfunction "P$1_P$23") (pintype "power_in"))
      (node (ref "P10") (pin "P$230") (pinfunction "P$1_P$230") (pintype "power_in"))
      (node (ref "P10") (pin "P$231") (pinfunction "P$1_P$231") (pintype "power_in"))
      (node (ref "P10") (pin "P$232") (pinfunction "P$1_P$232") (pintype "power_in"))
      (node (ref "P10") (pin "P$233") (pinfunction "P$1_P$233") (pintype "power_in"))
      (node (ref "P10") (pin "P$234") (pinfunction "P$1_P$234") (pintype "power_in"))
      (node (ref "P10") (pin "P$235") (pinfunction "P$1_P$235") (pintype "power_in"))
      (node (ref "P10") (pin "P$236") (pinfunction "P$1_P$236") (pintype "power_in"))
      (node (ref "P10") (pin "P$237") (pinfunction "P$1_P$237") (pintype "power_in"))
      (node (ref "P10") (pin "P$238") (pinfunction "P$1_P$238") (pintype "power_in"))
      (node (ref "P10") (pin "P$239") (pinfunction "P$1_P$239") (pintype "power_in"))
      (node (ref "P10") (pin "P$24") (pinfunction "P$1_P$24") (pintype "power_in"))
      (node (ref "P10") (pin "P$240") (pinfunction "P$1_P$240") (pintype "power_in"))
      (node (ref "P10") (pin "P$241") (pinfunction "P$1_P$241") (pintype "power_in"))
      (node (ref "P10") (pin "P$242") (pinfunction "P$1_P$242") (pintype "power_in"))
      (node (ref "P10") (pin "P$243") (pinfunction "P$1_P$243") (pintype "power_in"))
      (node (ref "P10") (pin "P$244") (pinfunction "P$1_P$244") (pintype "power_in"))
      (node (ref "P10") (pin "P$245") (pinfunction "P$1_P$245") (pintype "power_in"))
      (node (ref "P10") (pin "P$246") (pinfunction "P$1_P$246") (pintype "power_in"))
      (node (ref "P10") (pin "P$247") (pinfunction "P$1_P$247") (pintype "power_in"))
      (node (ref "P10") (pin "P$248") (pinfunction "P$1_P$248") (pintype "power_in"))
      (node (ref "P10") (pin "P$249") (pinfunction "P$1_P$249") (pintype "power_in"))
      (node (ref "P10") (pin "P$25") (pinfunction "P$1_P$25") (pintype "power_in"))
      (node (ref "P10") (pin "P$250") (pinfunction "P$1_P$250") (pintype "power_in"))
      (node (ref "P10") (pin "P$251") (pinfunction "P$1_P$251") (pintype "power_in"))
      (node (ref "P10") (pin "P$252") (pinfunction "P$1_P$252") (pintype "power_in"))
      (node (ref "P10") (pin "P$253") (pinfunction "P$1_P$253") (pintype "power_in"))
      (node (ref "P10") (pin "P$254") (pinfunction "P$1_P$254") (pintype "power_in"))
      (node (ref "P10") (pin "P$255") (pinfunction "P$1_P$255") (pintype "power_in"))
      (node (ref "P10") (pin "P$256") (pinfunction "P$1_P$256") (pintype "power_in"))
      (node (ref "P10") (pin "P$257") (pinfunction "P$1_P$257") (pintype "power_in"))
      (node (ref "P10") (pin "P$258") (pinfunction "P$1_P$258") (pintype "power_in"))
      (node (ref "P10") (pin "P$259") (pinfunction "P$1_P$259") (pintype "power_in"))
      (node (ref "P10") (pin "P$26") (pinfunction "P$1_P$26") (pintype "power_in"))
      (node (ref "P10") (pin "P$260") (pinfunction "P$1_P$260") (pintype "power_in"))
      (node (ref "P10") (pin "P$261") (pinfunction "P$1_P$261") (pintype "power_in"))
      (node (ref "P10") (pin "P$262") (pinfunction "P$1_P$262") (pintype "power_in"))
      (node (ref "P10") (pin "P$263") (pinfunction "P$1_P$263") (pintype "power_in"))
      (node (ref "P10") (pin "P$264") (pinfunction "P$1_P$264") (pintype "power_in"))
      (node (ref "P10") (pin "P$265") (pinfunction "P$1_P$265") (pintype "power_in"))
      (node (ref "P10") (pin "P$266") (pinfunction "P$1_P$266") (pintype "power_in"))
      (node (ref "P10") (pin "P$267") (pinfunction "P$1_P$267") (pintype "power_in"))
      (node (ref "P10") (pin "P$268") (pinfunction "P$1_P$268") (pintype "power_in"))
      (node (ref "P10") (pin "P$269") (pinfunction "P$1_P$269") (pintype "power_in"))
      (node (ref "P10") (pin "P$27") (pinfunction "P$1_P$27") (pintype "power_in"))
      (node (ref "P10") (pin "P$270") (pinfunction "P$1_P$270") (pintype "power_in"))
      (node (ref "P10") (pin "P$271") (pinfunction "P$1_P$271") (pintype "power_in"))
      (node (ref "P10") (pin "P$272") (pinfunction "P$1_P$272") (pintype "power_in"))
      (node (ref "P10") (pin "P$273") (pinfunction "P$1_P$273") (pintype "power_in"))
      (node (ref "P10") (pin "P$274") (pinfunction "P$1_P$274") (pintype "power_in"))
      (node (ref "P10") (pin "P$275") (pinfunction "P$1_P$275") (pintype "power_in"))
      (node (ref "P10") (pin "P$276") (pinfunction "P$1_P$276") (pintype "power_in"))
      (node (ref "P10") (pin "P$277") (pinfunction "P$1_P$277") (pintype "power_in"))
      (node (ref "P10") (pin "P$278") (pinfunction "P$1_P$278") (pintype "power_in"))
      (node (ref "P10") (pin "P$279") (pinfunction "P$1_P$279") (pintype "power_in"))
      (node (ref "P10") (pin "P$28") (pinfunction "P$1_P$28") (pintype "power_in"))
      (node (ref "P10") (pin "P$280") (pinfunction "P$1_P$280") (pintype "power_in"))
      (node (ref "P10") (pin "P$281") (pinfunction "P$1_P$281") (pintype "power_in"))
      (node (ref "P10") (pin "P$282") (pinfunction "P$1_P$282") (pintype "power_in"))
      (node (ref "P10") (pin "P$283") (pinfunction "P$1_P$283") (pintype "power_in"))
      (node (ref "P10") (pin "P$284") (pinfunction "P$1_P$284") (pintype "power_in"))
      (node (ref "P10") (pin "P$285") (pinfunction "P$1_P$285") (pintype "power_in"))
      (node (ref "P10") (pin "P$286") (pinfunction "P$1_P$286") (pintype "power_in"))
      (node (ref "P10") (pin "P$287") (pinfunction "P$1_P$287") (pintype "power_in"))
      (node (ref "P10") (pin "P$288") (pinfunction "P$1_P$288") (pintype "power_in"))
      (node (ref "P10") (pin "P$29") (pinfunction "P$1_P$29") (pintype "power_in"))
      (node (ref "P10") (pin "P$3") (pinfunction "P$1_P$3") (pintype "power_in"))
      (node (ref "P10") (pin "P$30") (pinfunction "P$1_P$30") (pintype "power_in"))
      (node (ref "P10") (pin "P$31") (pinfunction "P$1_P$31") (pintype "power_in"))
      (node (ref "P10") (pin "P$32") (pinfunction "P$1_P$32") (pintype "power_in"))
      (node (ref "P10") (pin "P$33") (pinfunction "P$1_P$33") (pintype "power_in"))
      (node (ref "P10") (pin "P$34") (pinfunction "P$1_P$34") (pintype "power_in"))
      (node (ref "P10") (pin "P$35") (pinfunction "P$1_P$35") (pintype "power_in"))
      (node (ref "P10") (pin "P$36") (pinfunction "P$1_P$36") (pintype "power_in"))
      (node (ref "P10") (pin "P$37") (pinfunction "P$1_P$37") (pintype "power_in"))
      (node (ref "P10") (pin "P$38") (pinfunction "P$1_P$38") (pintype "power_in"))
      (node (ref "P10") (pin "P$39") (pinfunction "P$1_P$39") (pintype "power_in"))
      (node (ref "P10") (pin "P$4") (pinfunction "P$1_P$4") (pintype "power_in"))
      (node (ref "P10") (pin "P$40") (pinfunction "P$1_P$40") (pintype "power_in"))
      (node (ref "P10") (pin "P$41") (pinfunction "P$1_P$41") (pintype "power_in"))
      (node (ref "P10") (pin "P$42") (pinfunction "P$1_P$42") (pintype "power_in"))
      (node (ref "P10") (pin "P$43") (pinfunction "P$1_P$43") (pintype "power_in"))
      (node (ref "P10") (pin "P$44") (pinfunction "P$1_P$44") (pintype "power_in"))
      (node (ref "P10") (pin "P$45") (pinfunction "P$1_P$45") (pintype "power_in"))
      (node (ref "P10") (pin "P$46") (pinfunction "P$1_P$46") (pintype "power_in"))
      (node (ref "P10") (pin "P$47") (pinfunction "P$1_P$47") (pintype "power_in"))
      (node (ref "P10") (pin "P$48") (pinfunction "P$1_P$48") (pintype "power_in"))
      (node (ref "P10") (pin "P$49") (pinfunction "P$1_P$49") (pintype "power_in"))
      (node (ref "P10") (pin "P$5") (pinfunction "P$1_P$5") (pintype "power_in"))
      (node (ref "P10") (pin "P$50") (pinfunction "P$1_P$50") (pintype "power_in"))
      (node (ref "P10") (pin "P$51") (pinfunction "P$1_P$51") (pintype "power_in"))
      (node (ref "P10") (pin "P$52") (pinfunction "P$1_P$52") (pintype "power_in"))
      (node (ref "P10") (pin "P$53") (pinfunction "P$1_P$53") (pintype "power_in"))
      (node (ref "P10") (pin "P$54") (pinfunction "P$1_P$54") (pintype "power_in"))
      (node (ref "P10") (pin "P$55") (pinfunction "P$1_P$55") (pintype "power_in"))
      (node (ref "P10") (pin "P$56") (pinfunction "P$1_P$56") (pintype "power_in"))
      (node (ref "P10") (pin "P$57") (pinfunction "P$1_P$57") (pintype "power_in"))
      (node (ref "P10") (pin "P$58") (pinfunction "P$1_P$58") (pintype "power_in"))
      (node (ref "P10") (pin "P$59") (pinfunction "P$1_P$59") (pintype "power_in"))
      (node (ref "P10") (pin "P$6") (pinfunction "P$1_P$6") (pintype "power_in"))
      (node (ref "P10") (pin "P$60") (pinfunction "P$1_P$60") (pintype "power_in"))
      (node (ref "P10") (pin "P$61") (pinfunction "P$1_P$61") (pintype "power_in"))
      (node (ref "P10") (pin "P$62") (pinfunction "P$1_P$62") (pintype "power_in"))
      (node (ref "P10") (pin "P$63") (pinfunction "P$1_P$63") (pintype "power_in"))
      (node (ref "P10") (pin "P$64") (pinfunction "P$1_P$64") (pintype "power_in"))
      (node (ref "P10") (pin "P$65") (pinfunction "P$1_P$65") (pintype "power_in"))
      (node (ref "P10") (pin "P$66") (pinfunction "P$1_P$66") (pintype "power_in"))
      (node (ref "P10") (pin "P$67") (pinfunction "P$1_P$67") (pintype "power_in"))
      (node (ref "P10") (pin "P$68") (pinfunction "P$1_P$68") (pintype "power_in"))
      (node (ref "P10") (pin "P$69") (pinfunction "P$1_P$69") (pintype "power_in"))
      (node (ref "P10") (pin "P$7") (pinfunction "P$1_P$7") (pintype "power_in"))
      (node (ref "P10") (pin "P$70") (pinfunction "P$1_P$70") (pintype "power_in"))
      (node (ref "P10") (pin "P$71") (pinfunction "P$1_P$71") (pintype "power_in"))
      (node (ref "P10") (pin "P$72") (pinfunction "P$1_P$72") (pintype "power_in"))
      (node (ref "P10") (pin "P$73") (pinfunction "P$1_P$73") (pintype "power_in"))
      (node (ref "P10") (pin "P$74") (pinfunction "P$1_P$74") (pintype "power_in"))
      (node (ref "P10") (pin "P$75") (pinfunction "P$1_P$75") (pintype "power_in"))
      (node (ref "P10") (pin "P$76") (pinfunction "P$1_P$76") (pintype "power_in"))
      (node (ref "P10") (pin "P$77") (pinfunction "P$1_P$77") (pintype "power_in"))
      (node (ref "P10") (pin "P$78") (pinfunction "P$1_P$78") (pintype "power_in"))
      (node (ref "P10") (pin "P$79") (pinfunction "P$1_P$79") (pintype "power_in"))
      (node (ref "P10") (pin "P$8") (pinfunction "P$1_P$8") (pintype "power_in"))
      (node (ref "P10") (pin "P$80") (pinfunction "P$1_P$80") (pintype "power_in"))
      (node (ref "P10") (pin "P$81") (pinfunction "P$1_P$81") (pintype "power_in"))
      (node (ref "P10") (pin "P$82") (pinfunction "P$1_P$82") (pintype "power_in"))
      (node (ref "P10") (pin "P$83") (pinfunction "P$1_P$83") (pintype "power_in"))
      (node (ref "P10") (pin "P$84") (pinfunction "P$1_P$84") (pintype "power_in"))
      (node (ref "P10") (pin "P$85") (pinfunction "P$1_P$85") (pintype "power_in"))
      (node (ref "P10") (pin "P$86") (pinfunction "P$1_P$86") (pintype "power_in"))
      (node (ref "P10") (pin "P$87") (pinfunction "P$1_P$87") (pintype "power_in"))
      (node (ref "P10") (pin "P$88") (pinfunction "P$1_P$88") (pintype "power_in"))
      (node (ref "P10") (pin "P$89") (pinfunction "P$1_P$89") (pintype "power_in"))
      (node (ref "P10") (pin "P$9") (pinfunction "P$1_P$9") (pintype "power_in"))
      (node (ref "P10") (pin "P$90") (pinfunction "P$1_P$90") (pintype "power_in"))
      (node (ref "P10") (pin "P$91") (pinfunction "P$1_P$91") (pintype "power_in"))
      (node (ref "P10") (pin "P$92") (pinfunction "P$1_P$92") (pintype "power_in"))
      (node (ref "P10") (pin "P$93") (pinfunction "P$1_P$93") (pintype "power_in"))
      (node (ref "P10") (pin "P$94") (pinfunction "P$1_P$94") (pintype "power_in"))
      (node (ref "P10") (pin "P$95") (pinfunction "P$1_P$95") (pintype "power_in"))
      (node (ref "P10") (pin "P$96") (pinfunction "P$1_P$96") (pintype "power_in"))
      (node (ref "P10") (pin "P$97") (pinfunction "P$1_P$97") (pintype "power_in"))
      (node (ref "P10") (pin "P$98") (pinfunction "P$1_P$98") (pintype "power_in"))
      (node (ref "P10") (pin "P$99") (pinfunction "P$1_P$99") (pintype "power_in"))
    )
    (net (code "12") (name "/P11") (class "Default")
      (node (ref "JP1") (pin "P$12") (pinfunction "11_P$12") (pintype "bidirectional"))
      (node (ref "P11") (pin "P$1") (pinfunction "P$1_P$1") (pintype "power_in"))
      (node (ref "P11") (pin "P$10") (pinfunction "P$1_P$10") (pintype "power_in"))
      (node (ref "P11") (pin "P$100") (pinfunction "P$1_P$100") (pintype "power_in"))
      (node (ref "P11") (pin "P$101") (pinfunction "P$1_P$101") (pintype "power_in"))
      (node (ref "P11") (pin "P$102") (pinfunction "P$1_P$102") (pintype "power_in"))
      (node (ref "P11") (pin "P$103") (pinfunction "P$1_P$103") (pintype "power_in"))
      (node (ref "P11") (pin "P$104") (pinfunction "P$1_P$104") (pintype "power_in"))
      (node (ref "P11") (pin "P$105") (pinfunction "P$1_P$105") (pintype "power_in"))
      (node (ref "P11") (pin "P$106") (pinfunction "P$1_P$106") (pintype "power_in"))
      (node (ref "P11") (pin "P$107") (pinfunction "P$1_P$107") (pintype "power_in"))
      (node (ref "P11") (pin "P$108") (pinfunction "P$1_P$108") (pintype "power_in"))
      (node (ref "P11") (pin "P$109") (pinfunction "P$1_P$109") (pintype "power_in"))
      (node (ref "P11") (pin "P$11") (pinfunction "P$1_P$11") (pintype "power_in"))
      (node (ref "P11") (pin "P$110") (pinfunction "P$1_P$110") (pintype "power_in"))
      (node (ref "P11") (pin "P$111") (pinfunction "P$1_P$111") (pintype "power_in"))
      (node (ref "P11") (pin "P$112") (pinfunction "P$1_P$112") (pintype "power_in"))
      (node (ref "P11") (pin "P$113") (pinfunction "P$1_P$113") (pintype "power_in"))
      (node (ref "P11") (pin "P$114") (pinfunction "P$1_P$114") (pintype "power_in"))
      (node (ref "P11") (pin "P$115") (pinfunction "P$1_P$115") (pintype "power_in"))
      (node (ref "P11") (pin "P$116") (pinfunction "P$1_P$116") (pintype "power_in"))
      (node (ref "P11") (pin "P$117") (pinfunction "P$1_P$117") (pintype "power_in"))
      (node (ref "P11") (pin "P$118") (pinfunction "P$1_P$118") (pintype "power_in"))
      (node (ref "P11") (pin "P$119") (pinfunction "P$1_P$119") (pintype "power_in"))
      (node (ref "P11") (pin "P$12") (pinfunction "P$1_P$12") (pintype "power_in"))
      (node (ref "P11") (pin "P$120") (pinfunction "P$1_P$120") (pintype "power_in"))
      (node (ref "P11") (pin "P$121") (pinfunction "P$1_P$121") (pintype "power_in"))
      (node (ref "P11") (pin "P$122") (pinfunction "P$1_P$122") (pintype "power_in"))
      (node (ref "P11") (pin "P$123") (pinfunction "P$1_P$123") (pintype "power_in"))
      (node (ref "P11") (pin "P$124") (pinfunction "P$1_P$124") (pintype "power_in"))
      (node (ref "P11") (pin "P$125") (pinfunction "P$1_P$125") (pintype "power_in"))
      (node (ref "P11") (pin "P$126") (pinfunction "P$1_P$126") (pintype "power_in"))
      (node (ref "P11") (pin "P$127") (pinfunction "P$1_P$127") (pintype "power_in"))
      (node (ref "P11") (pin "P$128") (pinfunction "P$1_P$128") (pintype "power_in"))
      (node (ref "P11") (pin "P$129") (pinfunction "P$1_P$129") (pintype "power_in"))
      (node (ref "P11") (pin "P$13") (pinfunction "P$1_P$13") (pintype "power_in"))
      (node (ref "P11") (pin "P$130") (pinfunction "P$1_P$130") (pintype "power_in"))
      (node (ref "P11") (pin "P$131") (pinfunction "P$1_P$131") (pintype "power_in"))
      (node (ref "P11") (pin "P$132") (pinfunction "P$1_P$132") (pintype "power_in"))
      (node (ref "P11") (pin "P$133") (pinfunction "P$1_P$133") (pintype "power_in"))
      (node (ref "P11") (pin "P$134") (pinfunction "P$1_P$134") (pintype "power_in"))
      (node (ref "P11") (pin "P$135") (pinfunction "P$1_P$135") (pintype "power_in"))
      (node (ref "P11") (pin "P$136") (pinfunction "P$1_P$136") (pintype "power_in"))
      (node (ref "P11") (pin "P$137") (pinfunction "P$1_P$137") (pintype "power_in"))
      (node (ref "P11") (pin "P$138") (pinfunction "P$1_P$138") (pintype "power_in"))
      (node (ref "P11") (pin "P$139") (pinfunction "P$1_P$139") (pintype "power_in"))
      (node (ref "P11") (pin "P$14") (pinfunction "P$1_P$14") (pintype "power_in"))
      (node (ref "P11") (pin "P$140") (pinfunction "P$1_P$140") (pintype "power_in"))
      (node (ref "P11") (pin "P$141") (pinfunction "P$1_P$141") (pintype "power_in"))
      (node (ref "P11") (pin "P$142") (pinfunction "P$1_P$142") (pintype "power_in"))
      (node (ref "P11") (pin "P$143") (pinfunction "P$1_P$143") (pintype "power_in"))
      (node (ref "P11") (pin "P$144") (pinfunction "P$1_P$144") (pintype "power_in"))
      (node (ref "P11") (pin "P$145") (pinfunction "P$1_P$145") (pintype "power_in"))
      (node (ref "P11") (pin "P$146") (pinfunction "P$1_P$146") (pintype "power_in"))
      (node (ref "P11") (pin "P$147") (pinfunction "P$1_P$147") (pintype "power_in"))
      (node (ref "P11") (pin "P$148") (pinfunction "P$1_P$148") (pintype "power_in"))
      (node (ref "P11") (pin "P$149") (pinfunction "P$1_P$149") (pintype "power_in"))
      (node (ref "P11") (pin "P$15") (pinfunction "P$1_P$15") (pintype "power_in"))
      (node (ref "P11") (pin "P$150") (pinfunction "P$1_P$150") (pintype "power_in"))
      (node (ref "P11") (pin "P$151") (pinfunction "P$1_P$151") (pintype "power_in"))
      (node (ref "P11") (pin "P$152") (pinfunction "P$1_P$152") (pintype "power_in"))
      (node (ref "P11") (pin "P$153") (pinfunction "P$1_P$153") (pintype "power_in"))
      (node (ref "P11") (pin "P$154") (pinfunction "P$1_P$154") (pintype "power_in"))
      (node (ref "P11") (pin "P$155") (pinfunction "P$1_P$155") (pintype "power_in"))
      (node (ref "P11") (pin "P$156") (pinfunction "P$1_P$156") (pintype "power_in"))
      (node (ref "P11") (pin "P$157") (pinfunction "P$1_P$157") (pintype "power_in"))
      (node (ref "P11") (pin "P$158") (pinfunction "P$1_P$158") (pintype "power_in"))
      (node (ref "P11") (pin "P$159") (pinfunction "P$1_P$159") (pintype "power_in"))
      (node (ref "P11") (pin "P$16") (pinfunction "P$1_P$16") (pintype "power_in"))
      (node (ref "P11") (pin "P$160") (pinfunction "P$1_P$160") (pintype "power_in"))
      (node (ref "P11") (pin "P$161") (pinfunction "P$1_P$161") (pintype "power_in"))
      (node (ref "P11") (pin "P$162") (pinfunction "P$1_P$162") (pintype "power_in"))
      (node (ref "P11") (pin "P$163") (pinfunction "P$1_P$163") (pintype "power_in"))
      (node (ref "P11") (pin "P$164") (pinfunction "P$1_P$164") (pintype "power_in"))
      (node (ref "P11") (pin "P$165") (pinfunction "P$1_P$165") (pintype "power_in"))
      (node (ref "P11") (pin "P$166") (pinfunction "P$1_P$166") (pintype "power_in"))
      (node (ref "P11") (pin "P$167") (pinfunction "P$1_P$167") (pintype "power_in"))
      (node (ref "P11") (pin "P$168") (pinfunction "P$1_P$168") (pintype "power_in"))
      (node (ref "P11") (pin "P$169") (pinfunction "P$1_P$169") (pintype "power_in"))
      (node (ref "P11") (pin "P$17") (pinfunction "P$1_P$17") (pintype "power_in"))
      (node (ref "P11") (pin "P$170") (pinfunction "P$1_P$170") (pintype "power_in"))
      (node (ref "P11") (pin "P$171") (pinfunction "P$1_P$171") (pintype "power_in"))
      (node (ref "P11") (pin "P$172") (pinfunction "P$1_P$172") (pintype "power_in"))
      (node (ref "P11") (pin "P$173") (pinfunction "P$1_P$173") (pintype "power_in"))
      (node (ref "P11") (pin "P$174") (pinfunction "P$1_P$174") (pintype "power_in"))
      (node (ref "P11") (pin "P$175") (pinfunction "P$1_P$175") (pintype "power_in"))
      (node (ref "P11") (pin "P$176") (pinfunction "P$1_P$176") (pintype "power_in"))
      (node (ref "P11") (pin "P$177") (pinfunction "P$1_P$177") (pintype "power_in"))
      (node (ref "P11") (pin "P$178") (pinfunction "P$1_P$178") (pintype "power_in"))
      (node (ref "P11") (pin "P$179") (pinfunction "P$1_P$179") (pintype "power_in"))
      (node (ref "P11") (pin "P$18") (pinfunction "P$1_P$18") (pintype "power_in"))
      (node (ref "P11") (pin "P$180") (pinfunction "P$1_P$180") (pintype "power_in"))
      (node (ref "P11") (pin "P$181") (pinfunction "P$1_P$181") (pintype "power_in"))
      (node (ref "P11") (pin "P$182") (pinfunction "P$1_P$182") (pintype "power_in"))
      (node (ref "P11") (pin "P$183") (pinfunction "P$1_P$183") (pintype "power_in"))
      (node (ref "P11") (pin "P$184") (pinfunction "P$1_P$184") (pintype "power_in"))
      (node (ref "P11") (pin "P$185") (pinfunction "P$1_P$185") (pintype "power_in"))
      (node (ref "P11") (pin "P$186") (pinfunction "P$1_P$186") (pintype "power_in"))
      (node (ref "P11") (pin "P$187") (pinfunction "P$1_P$187") (pintype "power_in"))
      (node (ref "P11") (pin "P$188") (pinfunction "P$1_P$188") (pintype "power_in"))
      (node (ref "P11") (pin "P$189") (pinfunction "P$1_P$189") (pintype "power_in"))
      (node (ref "P11") (pin "P$19") (pinfunction "P$1_P$19") (pintype "power_in"))
      (node (ref "P11") (pin "P$190") (pinfunction "P$1_P$190") (pintype "power_in"))
      (node (ref "P11") (pin "P$191") (pinfunction "P$1_P$191") (pintype "power_in"))
      (node (ref "P11") (pin "P$192") (pinfunction "P$1_P$192") (pintype "power_in"))
      (node (ref "P11") (pin "P$193") (pinfunction "P$1_P$193") (pintype "power_in"))
      (node (ref "P11") (pin "P$194") (pinfunction "P$1_P$194") (pintype "power_in"))
      (node (ref "P11") (pin "P$195") (pinfunction "P$1_P$195") (pintype "power_in"))
      (node (ref "P11") (pin "P$196") (pinfunction "P$1_P$196") (pintype "power_in"))
      (node (ref "P11") (pin "P$197") (pinfunction "P$1_P$197") (pintype "power_in"))
      (node (ref "P11") (pin "P$198") (pinfunction "P$1_P$198") (pintype "power_in"))
      (node (ref "P11") (pin "P$199") (pinfunction "P$1_P$199") (pintype "power_in"))
      (node (ref "P11") (pin "P$2") (pinfunction "P$1_P$2") (pintype "power_in"))
      (node (ref "P11") (pin "P$20") (pinfunction "P$1_P$20") (pintype "power_in"))
      (node (ref "P11") (pin "P$200") (pinfunction "P$1_P$200") (pintype "power_in"))
      (node (ref "P11") (pin "P$201") (pinfunction "P$1_P$201") (pintype "power_in"))
      (node (ref "P11") (pin "P$202") (pinfunction "P$1_P$202") (pintype "power_in"))
      (node (ref "P11") (pin "P$203") (pinfunction "P$1_P$203") (pintype "power_in"))
      (node (ref "P11") (pin "P$204") (pinfunction "P$1_P$204") (pintype "power_in"))
      (node (ref "P11") (pin "P$205") (pinfunction "P$1_P$205") (pintype "power_in"))
      (node (ref "P11") (pin "P$206") (pinfunction "P$1_P$206") (pintype "power_in"))
      (node (ref "P11") (pin "P$207") (pinfunction "P$1_P$207") (pintype "power_in"))
      (node (ref "P11") (pin "P$208") (pinfunction "P$1_P$208") (pintype "power_in"))
      (node (ref "P11") (pin "P$209") (pinfunction "P$1_P$209") (pintype "power_in"))
      (node (ref "P11") (pin "P$21") (pinfunction "P$1_P$21") (pintype "power_in"))
      (node (ref "P11") (pin "P$210") (pinfunction "P$1_P$210") (pintype "power_in"))
      (node (ref "P11") (pin "P$211") (pinfunction "P$1_P$211") (pintype "power_in"))
      (node (ref "P11") (pin "P$212") (pinfunction "P$1_P$212") (pintype "power_in"))
      (node (ref "P11") (pin "P$213") (pinfunction "P$1_P$213") (pintype "power_in"))
      (node (ref "P11") (pin "P$214") (pinfunction "P$1_P$214") (pintype "power_in"))
      (node (ref "P11") (pin "P$215") (pinfunction "P$1_P$215") (pintype "power_in"))
      (node (ref "P11") (pin "P$216") (pinfunction "P$1_P$216") (pintype "power_in"))
      (node (ref "P11") (pin "P$217") (pinfunction "P$1_P$217") (pintype "power_in"))
      (node (ref "P11") (pin "P$218") (pinfunction "P$1_P$218") (pintype "power_in"))
      (node (ref "P11") (pin "P$219") (pinfunction "P$1_P$219") (pintype "power_in"))
      (node (ref "P11") (pin "P$22") (pinfunction "P$1_P$22") (pintype "power_in"))
      (node (ref "P11") (pin "P$220") (pinfunction "P$1_P$220") (pintype "power_in"))
      (node (ref "P11") (pin "P$221") (pinfunction "P$1_P$221") (pintype "power_in"))
      (node (ref "P11") (pin "P$222") (pinfunction "P$1_P$222") (pintype "power_in"))
      (node (ref "P11") (pin "P$223") (pinfunction "P$1_P$223") (pintype "power_in"))
      (node (ref "P11") (pin "P$224") (pinfunction "P$1_P$224") (pintype "power_in"))
      (node (ref "P11") (pin "P$225") (pinfunction "P$1_P$225") (pintype "power_in"))
      (node (ref "P11") (pin "P$226") (pinfunction "P$1_P$226") (pintype "power_in"))
      (node (ref "P11") (pin "P$227") (pinfunction "P$1_P$227") (pintype "power_in"))
      (node (ref "P11") (pin "P$228") (pinfunction "P$1_P$228") (pintype "power_in"))
      (node (ref "P11") (pin "P$229") (pinfunction "P$1_P$229") (pintype "power_in"))
      (node (ref "P11") (pin "P$23") (pinfunction "P$1_P$23") (pintype "power_in"))
      (node (ref "P11") (pin "P$230") (pinfunction "P$1_P$230") (pintype "power_in"))
      (node (ref "P11") (pin "P$231") (pinfunction "P$1_P$231") (pintype "power_in"))
      (node (ref "P11") (pin "P$232") (pinfunction "P$1_P$232") (pintype "power_in"))
      (node (ref "P11") (pin "P$233") (pinfunction "P$1_P$233") (pintype "power_in"))
      (node (ref "P11") (pin "P$234") (pinfunction "P$1_P$234") (pintype "power_in"))
      (node (ref "P11") (pin "P$235") (pinfunction "P$1_P$235") (pintype "power_in"))
      (node (ref "P11") (pin "P$236") (pinfunction "P$1_P$236") (pintype "power_in"))
      (node (ref "P11") (pin "P$237") (pinfunction "P$1_P$237") (pintype "power_in"))
      (node (ref "P11") (pin "P$238") (pinfunction "P$1_P$238") (pintype "power_in"))
      (node (ref "P11") (pin "P$239") (pinfunction "P$1_P$239") (pintype "power_in"))
      (node (ref "P11") (pin "P$24") (pinfunction "P$1_P$24") (pintype "power_in"))
      (node (ref "P11") (pin "P$240") (pinfunction "P$1_P$240") (pintype "power_in"))
      (node (ref "P11") (pin "P$241") (pinfunction "P$1_P$241") (pintype "power_in"))
      (node (ref "P11") (pin "P$242") (pinfunction "P$1_P$242") (pintype "power_in"))
      (node (ref "P11") (pin "P$243") (pinfunction "P$1_P$243") (pintype "power_in"))
      (node (ref "P11") (pin "P$244") (pinfunction "P$1_P$244") (pintype "power_in"))
      (node (ref "P11") (pin "P$245") (pinfunction "P$1_P$245") (pintype "power_in"))
      (node (ref "P11") (pin "P$246") (pinfunction "P$1_P$246") (pintype "power_in"))
      (node (ref "P11") (pin "P$247") (pinfunction "P$1_P$247") (pintype "power_in"))
      (node (ref "P11") (pin "P$248") (pinfunction "P$1_P$248") (pintype "power_in"))
      (node (ref "P11") (pin "P$249") (pinfunction "P$1_P$249") (pintype "power_in"))
      (node (ref "P11") (pin "P$25") (pinfunction "P$1_P$25") (pintype "power_in"))
      (node (ref "P11") (pin "P$250") (pinfunction "P$1_P$250") (pintype "power_in"))
      (node (ref "P11") (pin "P$251") (pinfunction "P$1_P$251") (pintype "power_in"))
      (node (ref "P11") (pin "P$252") (pinfunction "P$1_P$252") (pintype "power_in"))
      (node (ref "P11") (pin "P$253") (pinfunction "P$1_P$253") (pintype "power_in"))
      (node (ref "P11") (pin "P$254") (pinfunction "P$1_P$254") (pintype "power_in"))
      (node (ref "P11") (pin "P$255") (pinfunction "P$1_P$255") (pintype "power_in"))
      (node (ref "P11") (pin "P$256") (pinfunction "P$1_P$256") (pintype "power_in"))
      (node (ref "P11") (pin "P$257") (pinfunction "P$1_P$257") (pintype "power_in"))
      (node (ref "P11") (pin "P$258") (pinfunction "P$1_P$258") (pintype "power_in"))
      (node (ref "P11") (pin "P$259") (pinfunction "P$1_P$259") (pintype "power_in"))
      (node (ref "P11") (pin "P$26") (pinfunction "P$1_P$26") (pintype "power_in"))
      (node (ref "P11") (pin "P$260") (pinfunction "P$1_P$260") (pintype "power_in"))
      (node (ref "P11") (pin "P$261") (pinfunction "P$1_P$261") (pintype "power_in"))
      (node (ref "P11") (pin "P$262") (pinfunction "P$1_P$262") (pintype "power_in"))
      (node (ref "P11") (pin "P$263") (pinfunction "P$1_P$263") (pintype "power_in"))
      (node (ref "P11") (pin "P$264") (pinfunction "P$1_P$264") (pintype "power_in"))
      (node (ref "P11") (pin "P$265") (pinfunction "P$1_P$265") (pintype "power_in"))
      (node (ref "P11") (pin "P$266") (pinfunction "P$1_P$266") (pintype "power_in"))
      (node (ref "P11") (pin "P$267") (pinfunction "P$1_P$267") (pintype "power_in"))
      (node (ref "P11") (pin "P$268") (pinfunction "P$1_P$268") (pintype "power_in"))
      (node (ref "P11") (pin "P$269") (pinfunction "P$1_P$269") (pintype "power_in"))
      (node (ref "P11") (pin "P$27") (pinfunction "P$1_P$27") (pintype "power_in"))
      (node (ref "P11") (pin "P$270") (pinfunction "P$1_P$270") (pintype "power_in"))
      (node (ref "P11") (pin "P$271") (pinfunction "P$1_P$271") (pintype "power_in"))
      (node (ref "P11") (pin "P$272") (pinfunction "P$1_P$272") (pintype "power_in"))
      (node (ref "P11") (pin "P$273") (pinfunction "P$1_P$273") (pintype "power_in"))
      (node (ref "P11") (pin "P$274") (pinfunction "P$1_P$274") (pintype "power_in"))
      (node (ref "P11") (pin "P$275") (pinfunction "P$1_P$275") (pintype "power_in"))
      (node (ref "P11") (pin "P$276") (pinfunction "P$1_P$276") (pintype "power_in"))
      (node (ref "P11") (pin "P$277") (pinfunction "P$1_P$277") (pintype "power_in"))
      (node (ref "P11") (pin "P$278") (pinfunction "P$1_P$278") (pintype "power_in"))
      (node (ref "P11") (pin "P$279") (pinfunction "P$1_P$279") (pintype "power_in"))
      (node (ref "P11") (pin "P$28") (pinfunction "P$1_P$28") (pintype "power_in"))
      (node (ref "P11") (pin "P$280") (pinfunction "P$1_P$280") (pintype "power_in"))
      (node (ref "P11") (pin "P$281") (pinfunction "P$1_P$281") (pintype "power_in"))
      (node (ref "P11") (pin "P$282") (pinfunction "P$1_P$282") (pintype "power_in"))
      (node (ref "P11") (pin "P$283") (pinfunction "P$1_P$283") (pintype "power_in"))
      (node (ref "P11") (pin "P$284") (pinfunction "P$1_P$284") (pintype "power_in"))
      (node (ref "P11") (pin "P$285") (pinfunction "P$1_P$285") (pintype "power_in"))
      (node (ref "P11") (pin "P$286") (pinfunction "P$1_P$286") (pintype "power_in"))
      (node (ref "P11") (pin "P$287") (pinfunction "P$1_P$287") (pintype "power_in"))
      (node (ref "P11") (pin "P$288") (pinfunction "P$1_P$288") (pintype "power_in"))
      (node (ref "P11") (pin "P$29") (pinfunction "P$1_P$29") (pintype "power_in"))
      (node (ref "P11") (pin "P$3") (pinfunction "P$1_P$3") (pintype "power_in"))
      (node (ref "P11") (pin "P$30") (pinfunction "P$1_P$30") (pintype "power_in"))
      (node (ref "P11") (pin "P$31") (pinfunction "P$1_P$31") (pintype "power_in"))
      (node (ref "P11") (pin "P$32") (pinfunction "P$1_P$32") (pintype "power_in"))
      (node (ref "P11") (pin "P$33") (pinfunction "P$1_P$33") (pintype "power_in"))
      (node (ref "P11") (pin "P$34") (pinfunction "P$1_P$34") (pintype "power_in"))
      (node (ref "P11") (pin "P$35") (pinfunction "P$1_P$35") (pintype "power_in"))
      (node (ref "P11") (pin "P$36") (pinfunction "P$1_P$36") (pintype "power_in"))
      (node (ref "P11") (pin "P$37") (pinfunction "P$1_P$37") (pintype "power_in"))
      (node (ref "P11") (pin "P$38") (pinfunction "P$1_P$38") (pintype "power_in"))
      (node (ref "P11") (pin "P$39") (pinfunction "P$1_P$39") (pintype "power_in"))
      (node (ref "P11") (pin "P$4") (pinfunction "P$1_P$4") (pintype "power_in"))
      (node (ref "P11") (pin "P$40") (pinfunction "P$1_P$40") (pintype "power_in"))
      (node (ref "P11") (pin "P$41") (pinfunction "P$1_P$41") (pintype "power_in"))
      (node (ref "P11") (pin "P$42") (pinfunction "P$1_P$42") (pintype "power_in"))
      (node (ref "P11") (pin "P$43") (pinfunction "P$1_P$43") (pintype "power_in"))
      (node (ref "P11") (pin "P$44") (pinfunction "P$1_P$44") (pintype "power_in"))
      (node (ref "P11") (pin "P$45") (pinfunction "P$1_P$45") (pintype "power_in"))
      (node (ref "P11") (pin "P$46") (pinfunction "P$1_P$46") (pintype "power_in"))
      (node (ref "P11") (pin "P$47") (pinfunction "P$1_P$47") (pintype "power_in"))
      (node (ref "P11") (pin "P$48") (pinfunction "P$1_P$48") (pintype "power_in"))
      (node (ref "P11") (pin "P$49") (pinfunction "P$1_P$49") (pintype "power_in"))
      (node (ref "P11") (pin "P$5") (pinfunction "P$1_P$5") (pintype "power_in"))
      (node (ref "P11") (pin "P$50") (pinfunction "P$1_P$50") (pintype "power_in"))
      (node (ref "P11") (pin "P$51") (pinfunction "P$1_P$51") (pintype "power_in"))
      (node (ref "P11") (pin "P$52") (pinfunction "P$1_P$52") (pintype "power_in"))
      (node (ref "P11") (pin "P$53") (pinfunction "P$1_P$53") (pintype "power_in"))
      (node (ref "P11") (pin "P$54") (pinfunction "P$1_P$54") (pintype "power_in"))
      (node (ref "P11") (pin "P$55") (pinfunction "P$1_P$55") (pintype "power_in"))
      (node (ref "P11") (pin "P$56") (pinfunction "P$1_P$56") (pintype "power_in"))
      (node (ref "P11") (pin "P$57") (pinfunction "P$1_P$57") (pintype "power_in"))
      (node (ref "P11") (pin "P$58") (pinfunction "P$1_P$58") (pintype "power_in"))
      (node (ref "P11") (pin "P$59") (pinfunction "P$1_P$59") (pintype "power_in"))
      (node (ref "P11") (pin "P$6") (pinfunction "P$1_P$6") (pintype "power_in"))
      (node (ref "P11") (pin "P$60") (pinfunction "P$1_P$60") (pintype "power_in"))
      (node (ref "P11") (pin "P$61") (pinfunction "P$1_P$61") (pintype "power_in"))
      (node (ref "P11") (pin "P$62") (pinfunction "P$1_P$62") (pintype "power_in"))
      (node (ref "P11") (pin "P$63") (pinfunction "P$1_P$63") (pintype "power_in"))
      (node (ref "P11") (pin "P$64") (pinfunction "P$1_P$64") (pintype "power_in"))
      (node (ref "P11") (pin "P$65") (pinfunction "P$1_P$65") (pintype "power_in"))
      (node (ref "P11") (pin "P$66") (pinfunction "P$1_P$66") (pintype "power_in"))
      (node (ref "P11") (pin "P$67") (pinfunction "P$1_P$67") (pintype "power_in"))
      (node (ref "P11") (pin "P$68") (pinfunction "P$1_P$68") (pintype "power_in"))
      (node (ref "P11") (pin "P$69") (pinfunction "P$1_P$69") (pintype "power_in"))
      (node (ref "P11") (pin "P$7") (pinfunction "P$1_P$7") (pintype "power_in"))
      (node (ref "P11") (pin "P$70") (pinfunction "P$1_P$70") (pintype "power_in"))
      (node (ref "P11") (pin "P$71") (pinfunction "P$1_P$71") (pintype "power_in"))
      (node (ref "P11") (pin "P$72") (pinfunction "P$1_P$72") (pintype "power_in"))
      (node (ref "P11") (pin "P$73") (pinfunction "P$1_P$73") (pintype "power_in"))
      (node (ref "P11") (pin "P$74") (pinfunction "P$1_P$74") (pintype "power_in"))
      (node (ref "P11") (pin "P$75") (pinfunction "P$1_P$75") (pintype "power_in"))
      (node (ref "P11") (pin "P$76") (pinfunction "P$1_P$76") (pintype "power_in"))
      (node (ref "P11") (pin "P$77") (pinfunction "P$1_P$77") (pintype "power_in"))
      (node (ref "P11") (pin "P$78") (pinfunction "P$1_P$78") (pintype "power_in"))
      (node (ref "P11") (pin "P$79") (pinfunction "P$1_P$79") (pintype "power_in"))
      (node (ref "P11") (pin "P$8") (pinfunction "P$1_P$8") (pintype "power_in"))
      (node (ref "P11") (pin "P$80") (pinfunction "P$1_P$80") (pintype "power_in"))
      (node (ref "P11") (pin "P$81") (pinfunction "P$1_P$81") (pintype "power_in"))
      (node (ref "P11") (pin "P$82") (pinfunction "P$1_P$82") (pintype "power_in"))
      (node (ref "P11") (pin "P$83") (pinfunction "P$1_P$83") (pintype "power_in"))
      (node (ref "P11") (pin "P$84") (pinfunction "P$1_P$84") (pintype "power_in"))
      (node (ref "P11") (pin "P$85") (pinfunction "P$1_P$85") (pintype "power_in"))
      (node (ref "P11") (pin "P$86") (pinfunction "P$1_P$86") (pintype "power_in"))
      (node (ref "P11") (pin "P$87") (pinfunction "P$1_P$87") (pintype "power_in"))
      (node (ref "P11") (pin "P$88") (pinfunction "P$1_P$88") (pintype "power_in"))
      (node (ref "P11") (pin "P$89") (pinfunction "P$1_P$89") (pintype "power_in"))
      (node (ref "P11") (pin "P$9") (pinfunction "P$1_P$9") (pintype "power_in"))
      (node (ref "P11") (pin "P$90") (pinfunction "P$1_P$90") (pintype "power_in"))
      (node (ref "P11") (pin "P$91") (pinfunction "P$1_P$91") (pintype "power_in"))
      (node (ref "P11") (pin "P$92") (pinfunction "P$1_P$92") (pintype "power_in"))
      (node (ref "P11") (pin "P$93") (pinfunction "P$1_P$93") (pintype "power_in"))
      (node (ref "P11") (pin "P$94") (pinfunction "P$1_P$94") (pintype "power_in"))
      (node (ref "P11") (pin "P$95") (pinfunction "P$1_P$95") (pintype "power_in"))
      (node (ref "P11") (pin "P$96") (pinfunction "P$1_P$96") (pintype "power_in"))
      (node (ref "P11") (pin "P$97") (pinfunction "P$1_P$97") (pintype "power_in"))
      (node (ref "P11") (pin "P$98") (pinfunction "P$1_P$98") (pintype "power_in"))
      (node (ref "P11") (pin "P$99") (pinfunction "P$1_P$99") (pintype "power_in"))
    )
    (net (code "13") (name "/P12+") (class "Default")
      (node (ref "J1") (pin "1") (pinfunction "1_1") (pintype "bidirectional"))
      (node (ref "J1") (pin "10") (pinfunction "10_10") (pintype "bidirectional"))
      (node (ref "J1") (pin "11") (pinfunction "11_11") (pintype "bidirectional"))
      (node (ref "J1") (pin "12") (pinfunction "12_12") (pintype "bidirectional"))
      (node (ref "J1") (pin "2") (pinfunction "2_2") (pintype "bidirectional"))
      (node (ref "J1") (pin "3") (pinfunction "3_3") (pintype "bidirectional"))
      (node (ref "J1") (pin "4") (pinfunction "4_4") (pintype "bidirectional"))
      (node (ref "J1") (pin "5") (pinfunction "5_5") (pintype "bidirectional"))
      (node (ref "J1") (pin "6") (pinfunction "6_6") (pintype "bidirectional"))
      (node (ref "J1") (pin "7") (pinfunction "7_7") (pintype "bidirectional"))
      (node (ref "J1") (pin "8") (pinfunction "8_8") (pintype "bidirectional"))
      (node (ref "J1") (pin "9") (pinfunction "9_9") (pintype "bidirectional"))
      (node (ref "JP1") (pin "P$13") (pinfunction "12_P$13") (pintype "bidirectional"))
      (node (ref "P12") (pin "P$10") (pinfunction "P$0_P$10") (pintype "power_in"))
      (node (ref "P12") (pin "P$100") (pinfunction "P$0_P$100") (pintype "power_in"))
      (node (ref "P12") (pin "P$101") (pinfunction "P$0_P$101") (pintype "power_in"))
      (node (ref "P12") (pin "P$102") (pinfunction "P$0_P$102") (pintype "power_in"))
      (node (ref "P12") (pin "P$103") (pinfunction "P$0_P$103") (pintype "power_in"))
      (node (ref "P12") (pin "P$104") (pinfunction "P$0_P$104") (pintype "power_in"))
      (node (ref "P12") (pin "P$105") (pinfunction "P$0_P$105") (pintype "power_in"))
      (node (ref "P12") (pin "P$106") (pinfunction "P$0_P$106") (pintype "power_in"))
      (node (ref "P12") (pin "P$107") (pinfunction "P$0_P$107") (pintype "power_in"))
      (node (ref "P12") (pin "P$108") (pinfunction "P$0_P$108") (pintype "power_in"))
      (node (ref "P12") (pin "P$109") (pinfunction "P$0_P$109") (pintype "power_in"))
      (node (ref "P12") (pin "P$11") (pinfunction "P$0_P$11") (pintype "power_in"))
      (node (ref "P12") (pin "P$110") (pinfunction "P$0_P$110") (pintype "power_in"))
      (node (ref "P12") (pin "P$12") (pinfunction "P$0_P$12") (pintype "power_in"))
      (node (ref "P12") (pin "P$13") (pinfunction "P$0_P$13") (pintype "power_in"))
      (node (ref "P12") (pin "P$14") (pinfunction "P$0_P$14") (pintype "power_in"))
      (node (ref "P12") (pin "P$15") (pinfunction "P$0_P$15") (pintype "power_in"))
      (node (ref "P12") (pin "P$16") (pinfunction "P$0_P$16") (pintype "power_in"))
      (node (ref "P12") (pin "P$17") (pinfunction "P$0_P$17") (pintype "power_in"))
      (node (ref "P12") (pin "P$18") (pinfunction "P$0_P$18") (pintype "power_in"))
      (node (ref "P12") (pin "P$181") (pinfunction "P$0_P$181") (pintype "power_in"))
      (node (ref "P12") (pin "P$182") (pinfunction "P$0_P$182") (pintype "power_in"))
      (node (ref "P12") (pin "P$183") (pinfunction "P$0_P$183") (pintype "power_in"))
      (node (ref "P12") (pin "P$184") (pinfunction "P$0_P$184") (pintype "power_in"))
      (node (ref "P12") (pin "P$185") (pinfunction "P$0_P$185") (pintype "power_in"))
      (node (ref "P12") (pin "P$186") (pinfunction "P$0_P$186") (pintype "power_in"))
      (node (ref "P12") (pin "P$187") (pinfunction "P$0_P$187") (pintype "power_in"))
      (node (ref "P12") (pin "P$188") (pinfunction "P$0_P$188") (pintype "power_in"))
      (node (ref "P12") (pin "P$189") (pinfunction "P$0_P$189") (pintype "power_in"))
      (node (ref "P12") (pin "P$19") (pinfunction "P$0_P$19") (pintype "power_in"))
      (node (ref "P12") (pin "P$190") (pinfunction "P$0_P$190") (pintype "power_in"))
      (node (ref "P12") (pin "P$191") (pinfunction "P$0_P$191") (pintype "power_in"))
      (node (ref "P12") (pin "P$192") (pinfunction "P$0_P$192") (pintype "power_in"))
      (node (ref "P12") (pin "P$193") (pinfunction "P$0_P$193") (pintype "power_in"))
      (node (ref "P12") (pin "P$194") (pinfunction "P$0_P$194") (pintype "power_in"))
      (node (ref "P12") (pin "P$195") (pinfunction "P$0_P$195") (pintype "power_in"))
      (node (ref "P12") (pin "P$196") (pinfunction "P$0_P$196") (pintype "power_in"))
      (node (ref "P12") (pin "P$197") (pinfunction "P$0_P$197") (pintype "power_in"))
      (node (ref "P12") (pin "P$198") (pinfunction "P$0_P$198") (pintype "power_in"))
      (node (ref "P12") (pin "P$199") (pinfunction "P$0_P$199") (pintype "power_in"))
      (node (ref "P12") (pin "P$20") (pinfunction "P$0_P$20") (pintype "power_in"))
      (node (ref "P12") (pin "P$200") (pinfunction "P$0_P$200") (pintype "power_in"))
      (node (ref "P12") (pin "P$201") (pinfunction "P$0_P$201") (pintype "power_in"))
      (node (ref "P12") (pin "P$202") (pinfunction "P$0_P$202") (pintype "power_in"))
      (node (ref "P12") (pin "P$203") (pinfunction "P$0_P$203") (pintype "power_in"))
      (node (ref "P12") (pin "P$204") (pinfunction "P$0_P$204") (pintype "power_in"))
      (node (ref "P12") (pin "P$205") (pinfunction "P$0_P$205") (pintype "power_in"))
      (node (ref "P12") (pin "P$206") (pinfunction "P$0_P$206") (pintype "power_in"))
      (node (ref "P12") (pin "P$207") (pinfunction "P$0_P$207") (pintype "power_in"))
      (node (ref "P12") (pin "P$208") (pinfunction "P$0_P$208") (pintype "power_in"))
      (node (ref "P12") (pin "P$209") (pinfunction "P$0_P$209") (pintype "power_in"))
      (node (ref "P12") (pin "P$21") (pinfunction "P$0_P$21") (pintype "power_in"))
      (node (ref "P12") (pin "P$210") (pinfunction "P$0_P$210") (pintype "power_in"))
      (node (ref "P12") (pin "P$211") (pinfunction "P$0_P$211") (pintype "power_in"))
      (node (ref "P12") (pin "P$212") (pinfunction "P$0_P$212") (pintype "power_in"))
      (node (ref "P12") (pin "P$213") (pinfunction "P$0_P$213") (pintype "power_in"))
      (node (ref "P12") (pin "P$214") (pinfunction "P$0_P$214") (pintype "power_in"))
      (node (ref "P12") (pin "P$215") (pinfunction "P$0_P$215") (pintype "power_in"))
      (node (ref "P12") (pin "P$216") (pinfunction "P$0_P$216") (pintype "power_in"))
      (node (ref "P12") (pin "P$217") (pinfunction "P$0_P$217") (pintype "power_in"))
      (node (ref "P12") (pin "P$218") (pinfunction "P$0_P$218") (pintype "power_in"))
      (node (ref "P12") (pin "P$219") (pinfunction "P$0_P$219") (pintype "power_in"))
      (node (ref "P12") (pin "P$22") (pinfunction "P$0_P$22") (pintype "power_in"))
      (node (ref "P12") (pin "P$220") (pinfunction "P$0_P$220") (pintype "power_in"))
      (node (ref "P12") (pin "P$221") (pinfunction "P$0_P$221") (pintype "power_in"))
      (node (ref "P12") (pin "P$222") (pinfunction "P$0_P$222") (pintype "power_in"))
      (node (ref "P12") (pin "P$223") (pinfunction "P$0_P$223") (pintype "power_in"))
      (node (ref "P12") (pin "P$224") (pinfunction "P$0_P$224") (pintype "power_in"))
      (node (ref "P12") (pin "P$225") (pinfunction "P$0_P$225") (pintype "power_in"))
      (node (ref "P12") (pin "P$226") (pinfunction "P$0_P$226") (pintype "power_in"))
      (node (ref "P12") (pin "P$227") (pinfunction "P$0_P$227") (pintype "power_in"))
      (node (ref "P12") (pin "P$228") (pinfunction "P$0_P$228") (pintype "power_in"))
      (node (ref "P12") (pin "P$229") (pinfunction "P$0_P$229") (pintype "power_in"))
      (node (ref "P12") (pin "P$23") (pinfunction "P$0_P$23") (pintype "power_in"))
      (node (ref "P12") (pin "P$230") (pinfunction "P$0_P$230") (pintype "power_in"))
      (node (ref "P12") (pin "P$231") (pinfunction "P$0_P$231") (pintype "power_in"))
      (node (ref "P12") (pin "P$232") (pinfunction "P$0_P$232") (pintype "power_in"))
      (node (ref "P12") (pin "P$233") (pinfunction "P$0_P$233") (pintype "power_in"))
      (node (ref "P12") (pin "P$234") (pinfunction "P$0_P$234") (pintype "power_in"))
      (node (ref "P12") (pin "P$235") (pinfunction "P$0_P$235") (pintype "power_in"))
      (node (ref "P12") (pin "P$236") (pinfunction "P$0_P$236") (pintype "power_in"))
      (node (ref "P12") (pin "P$237") (pinfunction "P$0_P$237") (pintype "power_in"))
      (node (ref "P12") (pin "P$238") (pinfunction "P$0_P$238") (pintype "power_in"))
      (node (ref "P12") (pin "P$239") (pinfunction "P$0_P$239") (pintype "power_in"))
      (node (ref "P12") (pin "P$24") (pinfunction "P$0_P$24") (pintype "power_in"))
      (node (ref "P12") (pin "P$240") (pinfunction "P$0_P$240") (pintype "power_in"))
      (node (ref "P12") (pin "P$241") (pinfunction "P$0_P$241") (pintype "power_in"))
      (node (ref "P12") (pin "P$242") (pinfunction "P$0_P$242") (pintype "power_in"))
      (node (ref "P12") (pin "P$243") (pinfunction "P$0_P$243") (pintype "power_in"))
      (node (ref "P12") (pin "P$244") (pinfunction "P$0_P$244") (pintype "power_in"))
      (node (ref "P12") (pin "P$245") (pinfunction "P$0_P$245") (pintype "power_in"))
      (node (ref "P12") (pin "P$246") (pinfunction "P$0_P$246") (pintype "power_in"))
      (node (ref "P12") (pin "P$247") (pinfunction "P$0_P$247") (pintype "power_in"))
      (node (ref "P12") (pin "P$248") (pinfunction "P$0_P$248") (pintype "power_in"))
      (node (ref "P12") (pin "P$249") (pinfunction "P$0_P$249") (pintype "power_in"))
      (node (ref "P12") (pin "P$25") (pinfunction "P$0_P$25") (pintype "power_in"))
      (node (ref "P12") (pin "P$250") (pinfunction "P$0_P$250") (pintype "power_in"))
      (node (ref "P12") (pin "P$251") (pinfunction "P$0_P$251") (pintype "power_in"))
      (node (ref "P12") (pin "P$252") (pinfunction "P$0_P$252") (pintype "power_in"))
      (node (ref "P12") (pin "P$253") (pinfunction "P$0_P$253") (pintype "power_in"))
      (node (ref "P12") (pin "P$254") (pinfunction "P$0_P$254") (pintype "power_in"))
      (node (ref "P12") (pin "P$255") (pinfunction "P$0_P$255") (pintype "power_in"))
      (node (ref "P12") (pin "P$256") (pinfunction "P$0_P$256") (pintype "power_in"))
      (node (ref "P12") (pin "P$257") (pinfunction "P$0_P$257") (pintype "power_in"))
      (node (ref "P12") (pin "P$258") (pinfunction "P$0_P$258") (pintype "power_in"))
      (node (ref "P12") (pin "P$259") (pinfunction "P$0_P$259") (pintype "power_in"))
      (node (ref "P12") (pin "P$26") (pinfunction "P$0_P$26") (pintype "power_in"))
      (node (ref "P12") (pin "P$260") (pinfunction "P$0_P$260") (pintype "power_in"))
      (node (ref "P12") (pin "P$261") (pinfunction "P$0_P$261") (pintype "power_in"))
      (node (ref "P12") (pin "P$262") (pinfunction "P$0_P$262") (pintype "power_in"))
      (node (ref "P12") (pin "P$263") (pinfunction "P$0_P$263") (pintype "power_in"))
      (node (ref "P12") (pin "P$264") (pinfunction "P$0_P$264") (pintype "power_in"))
      (node (ref "P12") (pin "P$265") (pinfunction "P$0_P$265") (pintype "power_in"))
      (node (ref "P12") (pin "P$266") (pinfunction "P$0_P$266") (pintype "power_in"))
      (node (ref "P12") (pin "P$267") (pinfunction "P$0_P$267") (pintype "power_in"))
      (node (ref "P12") (pin "P$268") (pinfunction "P$0_P$268") (pintype "power_in"))
      (node (ref "P12") (pin "P$269") (pinfunction "P$0_P$269") (pintype "power_in"))
      (node (ref "P12") (pin "P$27") (pinfunction "P$0_P$27") (pintype "power_in"))
      (node (ref "P12") (pin "P$270") (pinfunction "P$0_P$270") (pintype "power_in"))
      (node (ref "P12") (pin "P$271") (pinfunction "P$0_P$271") (pintype "power_in"))
      (node (ref "P12") (pin "P$272") (pinfunction "P$0_P$272") (pintype "power_in"))
      (node (ref "P12") (pin "P$273") (pinfunction "P$0_P$273") (pintype "power_in"))
      (node (ref "P12") (pin "P$274") (pinfunction "P$0_P$274") (pintype "power_in"))
      (node (ref "P12") (pin "P$275") (pinfunction "P$0_P$275") (pintype "power_in"))
      (node (ref "P12") (pin "P$276") (pinfunction "P$0_P$276") (pintype "power_in"))
      (node (ref "P12") (pin "P$277") (pinfunction "P$0_P$277") (pintype "power_in"))
      (node (ref "P12") (pin "P$278") (pinfunction "P$0_P$278") (pintype "power_in"))
      (node (ref "P12") (pin "P$279") (pinfunction "P$0_P$279") (pintype "power_in"))
      (node (ref "P12") (pin "P$28") (pinfunction "P$0_P$28") (pintype "power_in"))
      (node (ref "P12") (pin "P$280") (pinfunction "P$0_P$280") (pintype "power_in"))
      (node (ref "P12") (pin "P$281") (pinfunction "P$0_P$281") (pintype "power_in"))
      (node (ref "P12") (pin "P$282") (pinfunction "P$0_P$282") (pintype "power_in"))
      (node (ref "P12") (pin "P$283") (pinfunction "P$0_P$283") (pintype "power_in"))
      (node (ref "P12") (pin "P$284") (pinfunction "P$0_P$284") (pintype "power_in"))
      (node (ref "P12") (pin "P$285") (pinfunction "P$0_P$285") (pintype "power_in"))
      (node (ref "P12") (pin "P$286") (pinfunction "P$0_P$286") (pintype "power_in"))
      (node (ref "P12") (pin "P$287") (pinfunction "P$0_P$287") (pintype "power_in"))
      (node (ref "P12") (pin "P$288") (pinfunction "P$0_P$288") (pintype "power_in"))
      (node (ref "P12") (pin "P$289") (pinfunction "P$0_P$289") (pintype "power_in"))
      (node (ref "P12") (pin "P$29") (pinfunction "P$0_P$29") (pintype "power_in"))
      (node (ref "P12") (pin "P$290") (pinfunction "P$0_P$290") (pintype "power_in"))
      (node (ref "P12") (pin "P$291") (pinfunction "P$0_P$291") (pintype "power_in"))
      (node (ref "P12") (pin "P$292") (pinfunction "P$0_P$292") (pintype "power_in"))
      (node (ref "P12") (pin "P$293") (pinfunction "P$0_P$293") (pintype "power_in"))
      (node (ref "P12") (pin "P$294") (pinfunction "P$0_P$294") (pintype "power_in"))
      (node (ref "P12") (pin "P$295") (pinfunction "P$0_P$295") (pintype "power_in"))
      (node (ref "P12") (pin "P$296") (pinfunction "P$0_P$296") (pintype "power_in"))
      (node (ref "P12") (pin "P$297") (pinfunction "P$0_P$297") (pintype "power_in"))
      (node (ref "P12") (pin "P$298") (pinfunction "P$0_P$298") (pintype "power_in"))
      (node (ref "P12") (pin "P$299") (pinfunction "P$0_P$299") (pintype "power_in"))
      (node (ref "P12") (pin "P$3") (pinfunction "P$0_P$3") (pintype "power_in"))
      (node (ref "P12") (pin "P$30") (pinfunction "P$0_P$30") (pintype "power_in"))
      (node (ref "P12") (pin "P$300") (pinfunction "P$0_P$300") (pintype "power_in"))
      (node (ref "P12") (pin "P$301") (pinfunction "P$0_P$301") (pintype "power_in"))
      (node (ref "P12") (pin "P$302") (pinfunction "P$0_P$302") (pintype "power_in"))
      (node (ref "P12") (pin "P$303") (pinfunction "P$0_P$303") (pintype "power_in"))
      (node (ref "P12") (pin "P$304") (pinfunction "P$0_P$304") (pintype "power_in"))
      (node (ref "P12") (pin "P$305") (pinfunction "P$0_P$305") (pintype "power_in"))
      (node (ref "P12") (pin "P$306") (pinfunction "P$0_P$306") (pintype "power_in"))
      (node (ref "P12") (pin "P$307") (pinfunction "P$0_P$307") (pintype "power_in"))
      (node (ref "P12") (pin "P$308") (pinfunction "P$0_P$308") (pintype "power_in"))
      (node (ref "P12") (pin "P$309") (pinfunction "P$0_P$309") (pintype "power_in"))
      (node (ref "P12") (pin "P$31") (pinfunction "P$0_P$31") (pintype "power_in"))
      (node (ref "P12") (pin "P$310") (pinfunction "P$0_P$310") (pintype "power_in"))
      (node (ref "P12") (pin "P$311") (pinfunction "P$0_P$311") (pintype "power_in"))
      (node (ref "P12") (pin "P$312") (pinfunction "P$0_P$312") (pintype "power_in"))
      (node (ref "P12") (pin "P$313") (pinfunction "P$0_P$313") (pintype "power_in"))
      (node (ref "P12") (pin "P$314") (pinfunction "P$0_P$314") (pintype "power_in"))
      (node (ref "P12") (pin "P$315") (pinfunction "P$0_P$315") (pintype "power_in"))
      (node (ref "P12") (pin "P$316") (pinfunction "P$0_P$316") (pintype "power_in"))
      (node (ref "P12") (pin "P$317") (pinfunction "P$0_P$317") (pintype "power_in"))
      (node (ref "P12") (pin "P$318") (pinfunction "P$0_P$318") (pintype "power_in"))
      (node (ref "P12") (pin "P$319") (pinfunction "P$0_P$319") (pintype "power_in"))
      (node (ref "P12") (pin "P$32") (pinfunction "P$0_P$32") (pintype "power_in"))
      (node (ref "P12") (pin "P$320") (pinfunction "P$0_P$320") (pintype "power_in"))
      (node (ref "P12") (pin "P$321") (pinfunction "P$0_P$321") (pintype "power_in"))
      (node (ref "P12") (pin "P$322") (pinfunction "P$0_P$322") (pintype "power_in"))
      (node (ref "P12") (pin "P$323") (pinfunction "P$0_P$323") (pintype "power_in"))
      (node (ref "P12") (pin "P$324") (pinfunction "P$0_P$324") (pintype "power_in"))
      (node (ref "P12") (pin "P$325") (pinfunction "P$0_P$325") (pintype "power_in"))
      (node (ref "P12") (pin "P$326") (pinfunction "P$0_P$326") (pintype "power_in"))
      (node (ref "P12") (pin "P$327") (pinfunction "P$0_P$327") (pintype "power_in"))
      (node (ref "P12") (pin "P$328") (pinfunction "P$0_P$328") (pintype "power_in"))
      (node (ref "P12") (pin "P$329") (pinfunction "P$0_P$329") (pintype "power_in"))
      (node (ref "P12") (pin "P$33") (pinfunction "P$0_P$33") (pintype "power_in"))
      (node (ref "P12") (pin "P$330") (pinfunction "P$0_P$330") (pintype "power_in"))
      (node (ref "P12") (pin "P$331") (pinfunction "P$0_P$331") (pintype "power_in"))
      (node (ref "P12") (pin "P$332") (pinfunction "P$0_P$332") (pintype "power_in"))
      (node (ref "P12") (pin "P$333") (pinfunction "P$0_P$333") (pintype "power_in"))
      (node (ref "P12") (pin "P$334") (pinfunction "P$0_P$334") (pintype "power_in"))
      (node (ref "P12") (pin "P$335") (pinfunction "P$0_P$335") (pintype "power_in"))
      (node (ref "P12") (pin "P$336") (pinfunction "P$0_P$336") (pintype "power_in"))
      (node (ref "P12") (pin "P$337") (pinfunction "P$0_P$337") (pintype "power_in"))
      (node (ref "P12") (pin "P$338") (pinfunction "P$0_P$338") (pintype "power_in"))
      (node (ref "P12") (pin "P$339") (pinfunction "P$0_P$339") (pintype "power_in"))
      (node (ref "P12") (pin "P$34") (pinfunction "P$0_P$34") (pintype "power_in"))
      (node (ref "P12") (pin "P$340") (pinfunction "P$0_P$340") (pintype "power_in"))
      (node (ref "P12") (pin "P$341") (pinfunction "P$0_P$341") (pintype "power_in"))
      (node (ref "P12") (pin "P$342") (pinfunction "P$0_P$342") (pintype "power_in"))
      (node (ref "P12") (pin "P$343") (pinfunction "P$0_P$343") (pintype "power_in"))
      (node (ref "P12") (pin "P$344") (pinfunction "P$0_P$344") (pintype "power_in"))
      (node (ref "P12") (pin "P$345") (pinfunction "P$0_P$345") (pintype "power_in"))
      (node (ref "P12") (pin "P$346") (pinfunction "P$0_P$346") (pintype "power_in"))
      (node (ref "P12") (pin "P$347") (pinfunction "P$0_P$347") (pintype "power_in"))
      (node (ref "P12") (pin "P$348") (pinfunction "P$0_P$348") (pintype "power_in"))
      (node (ref "P12") (pin "P$349") (pinfunction "P$0_P$349") (pintype "power_in"))
      (node (ref "P12") (pin "P$35") (pinfunction "P$0_P$35") (pintype "power_in"))
      (node (ref "P12") (pin "P$350") (pinfunction "P$0_P$350") (pintype "power_in"))
      (node (ref "P12") (pin "P$351") (pinfunction "P$0_P$351") (pintype "power_in"))
      (node (ref "P12") (pin "P$352") (pinfunction "P$0_P$352") (pintype "power_in"))
      (node (ref "P12") (pin "P$353") (pinfunction "P$0_P$353") (pintype "power_in"))
      (node (ref "P12") (pin "P$354") (pinfunction "P$0_P$354") (pintype "power_in"))
      (node (ref "P12") (pin "P$355") (pinfunction "P$0_P$355") (pintype "power_in"))
      (node (ref "P12") (pin "P$356") (pinfunction "P$0_P$356") (pintype "power_in"))
      (node (ref "P12") (pin "P$357") (pinfunction "P$0_P$357") (pintype "power_in"))
      (node (ref "P12") (pin "P$358") (pinfunction "P$0_P$358") (pintype "power_in"))
      (node (ref "P12") (pin "P$359") (pinfunction "P$0_P$359") (pintype "power_in"))
      (node (ref "P12") (pin "P$36") (pinfunction "P$0_P$36") (pintype "power_in"))
      (node (ref "P12") (pin "P$360") (pinfunction "P$0_P$360") (pintype "power_in"))
      (node (ref "P12") (pin "P$37") (pinfunction "P$0_P$37") (pintype "power_in"))
      (node (ref "P12") (pin "P$38") (pinfunction "P$0_P$38") (pintype "power_in"))
      (node (ref "P12") (pin "P$39") (pinfunction "P$0_P$39") (pintype "power_in"))
      (node (ref "P12") (pin "P$4") (pinfunction "P$0_P$4") (pintype "power_in"))
      (node (ref "P12") (pin "P$40") (pinfunction "P$0_P$40") (pintype "power_in"))
      (node (ref "P12") (pin "P$41") (pinfunction "P$0_P$41") (pintype "power_in"))
      (node (ref "P12") (pin "P$42") (pinfunction "P$0_P$42") (pintype "power_in"))
      (node (ref "P12") (pin "P$43") (pinfunction "P$0_P$43") (pintype "power_in"))
      (node (ref "P12") (pin "P$44") (pinfunction "P$0_P$44") (pintype "power_in"))
      (node (ref "P12") (pin "P$45") (pinfunction "P$0_P$45") (pintype "power_in"))
      (node (ref "P12") (pin "P$46") (pinfunction "P$0_P$46") (pintype "power_in"))
      (node (ref "P12") (pin "P$47") (pinfunction "P$0_P$47") (pintype "power_in"))
      (node (ref "P12") (pin "P$48") (pinfunction "P$0_P$48") (pintype "power_in"))
      (node (ref "P12") (pin "P$49") (pinfunction "P$0_P$49") (pintype "power_in"))
      (node (ref "P12") (pin "P$5") (pinfunction "P$0_P$5") (pintype "power_in"))
      (node (ref "P12") (pin "P$50") (pinfunction "P$0_P$50") (pintype "power_in"))
      (node (ref "P12") (pin "P$51") (pinfunction "P$0_P$51") (pintype "power_in"))
      (node (ref "P12") (pin "P$52") (pinfunction "P$0_P$52") (pintype "power_in"))
      (node (ref "P12") (pin "P$53") (pinfunction "P$0_P$53") (pintype "power_in"))
      (node (ref "P12") (pin "P$54") (pinfunction "P$0_P$54") (pintype "power_in"))
      (node (ref "P12") (pin "P$55") (pinfunction "P$0_P$55") (pintype "power_in"))
      (node (ref "P12") (pin "P$56") (pinfunction "P$0_P$56") (pintype "power_in"))
      (node (ref "P12") (pin "P$57") (pinfunction "P$0_P$57") (pintype "power_in"))
      (node (ref "P12") (pin "P$58") (pinfunction "P$0_P$58") (pintype "power_in"))
      (node (ref "P12") (pin "P$59") (pinfunction "P$0_P$59") (pintype "power_in"))
      (node (ref "P12") (pin "P$6") (pinfunction "P$0_P$6") (pintype "power_in"))
      (node (ref "P12") (pin "P$60") (pinfunction "P$0_P$60") (pintype "power_in"))
      (node (ref "P12") (pin "P$61") (pinfunction "P$0_P$61") (pintype "power_in"))
      (node (ref "P12") (pin "P$62") (pinfunction "P$0_P$62") (pintype "power_in"))
      (node (ref "P12") (pin "P$63") (pinfunction "P$0_P$63") (pintype "power_in"))
      (node (ref "P12") (pin "P$64") (pinfunction "P$0_P$64") (pintype "power_in"))
      (node (ref "P12") (pin "P$65") (pinfunction "P$0_P$65") (pintype "power_in"))
      (node (ref "P12") (pin "P$66") (pinfunction "P$0_P$66") (pintype "power_in"))
      (node (ref "P12") (pin "P$67") (pinfunction "P$0_P$67") (pintype "power_in"))
      (node (ref "P12") (pin "P$68") (pinfunction "P$0_P$68") (pintype "power_in"))
      (node (ref "P12") (pin "P$69") (pinfunction "P$0_P$69") (pintype "power_in"))
      (node (ref "P12") (pin "P$7") (pinfunction "P$0_P$7") (pintype "power_in"))
      (node (ref "P12") (pin "P$70") (pinfunction "P$0_P$70") (pintype "power_in"))
      (node (ref "P12") (pin "P$71") (pinfunction "P$0_P$71") (pintype "power_in"))
      (node (ref "P12") (pin "P$72") (pinfunction "P$0_P$72") (pintype "power_in"))
      (node (ref "P12") (pin "P$73") (pinfunction "P$0_P$73") (pintype "power_in"))
      (node (ref "P12") (pin "P$74") (pinfunction "P$0_P$74") (pintype "power_in"))
      (node (ref "P12") (pin "P$75") (pinfunction "P$0_P$75") (pintype "power_in"))
      (node (ref "P12") (pin "P$76") (pinfunction "P$0_P$76") (pintype "power_in"))
      (node (ref "P12") (pin "P$77") (pinfunction "P$0_P$77") (pintype "power_in"))
      (node (ref "P12") (pin "P$78") (pinfunction "P$0_P$78") (pintype "power_in"))
      (node (ref "P12") (pin "P$79") (pinfunction "P$0_P$79") (pintype "power_in"))
      (node (ref "P12") (pin "P$8") (pinfunction "P$0_P$8") (pintype "power_in"))
      (node (ref "P12") (pin "P$80") (pinfunction "P$0_P$80") (pintype "power_in"))
      (node (ref "P12") (pin "P$81") (pinfunction "P$0_P$81") (pintype "power_in"))
      (node (ref "P12") (pin "P$82") (pinfunction "P$0_P$82") (pintype "power_in"))
      (node (ref "P12") (pin "P$83") (pinfunction "P$0_P$83") (pintype "power_in"))
      (node (ref "P12") (pin "P$84") (pinfunction "P$0_P$84") (pintype "power_in"))
      (node (ref "P12") (pin "P$85") (pinfunction "P$0_P$85") (pintype "power_in"))
      (node (ref "P12") (pin "P$86") (pinfunction "P$0_P$86") (pintype "power_in"))
      (node (ref "P12") (pin "P$87") (pinfunction "P$0_P$87") (pintype "power_in"))
      (node (ref "P12") (pin "P$88") (pinfunction "P$0_P$88") (pintype "power_in"))
      (node (ref "P12") (pin "P$89") (pinfunction "P$0_P$89") (pintype "power_in"))
      (node (ref "P12") (pin "P$9") (pinfunction "P$0_P$9") (pintype "power_in"))
      (node (ref "P12") (pin "P$90") (pinfunction "P$0_P$90") (pintype "power_in"))
      (node (ref "P12") (pin "P$91") (pinfunction "P$0_P$91") (pintype "power_in"))
      (node (ref "P12") (pin "P$92") (pinfunction "P$0_P$92") (pintype "power_in"))
      (node (ref "P12") (pin "P$93") (pinfunction "P$0_P$93") (pintype "power_in"))
      (node (ref "P12") (pin "P$94") (pinfunction "P$0_P$94") (pintype "power_in"))
      (node (ref "P12") (pin "P$95") (pinfunction "P$0_P$95") (pintype "power_in"))
      (node (ref "P12") (pin "P$96") (pinfunction "P$0_P$96") (pintype "power_in"))
      (node (ref "P12") (pin "P$97") (pinfunction "P$0_P$97") (pintype "power_in"))
      (node (ref "P12") (pin "P$98") (pinfunction "P$0_P$98") (pintype "power_in"))
      (node (ref "P12") (pin "P$99") (pinfunction "P$0_P$99") (pintype "power_in"))
    )
  )
)
